# BEP32_6panel_Seed_wdrills.net
KiCad netlist of a schematic drawn in EAGLE
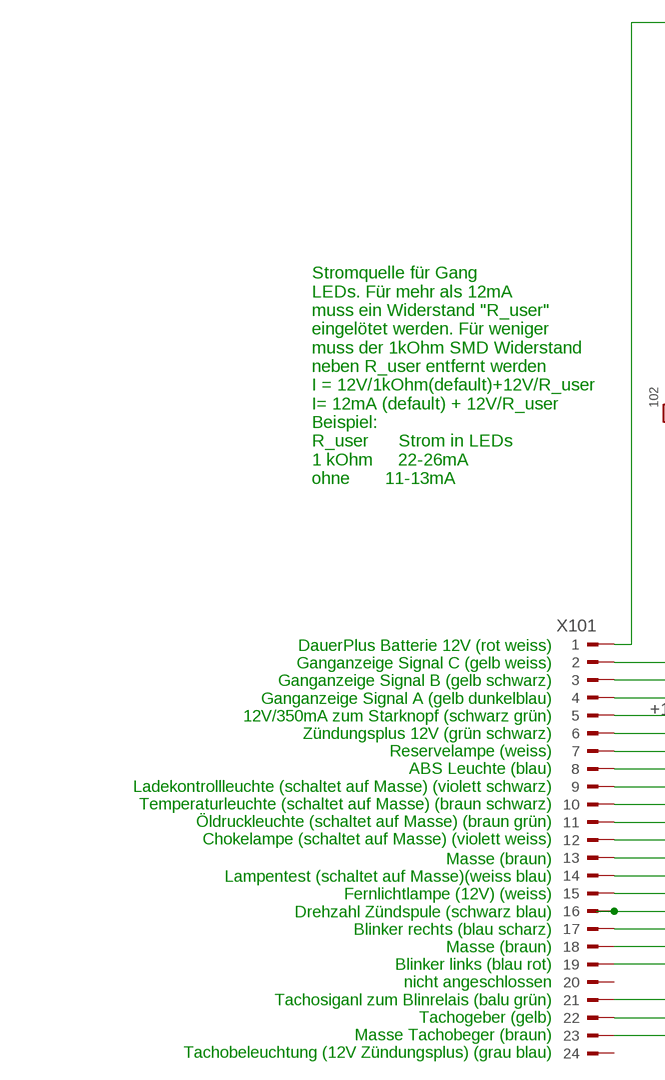
[diagram p0: schematic, sheet 1, part 1 of 2]
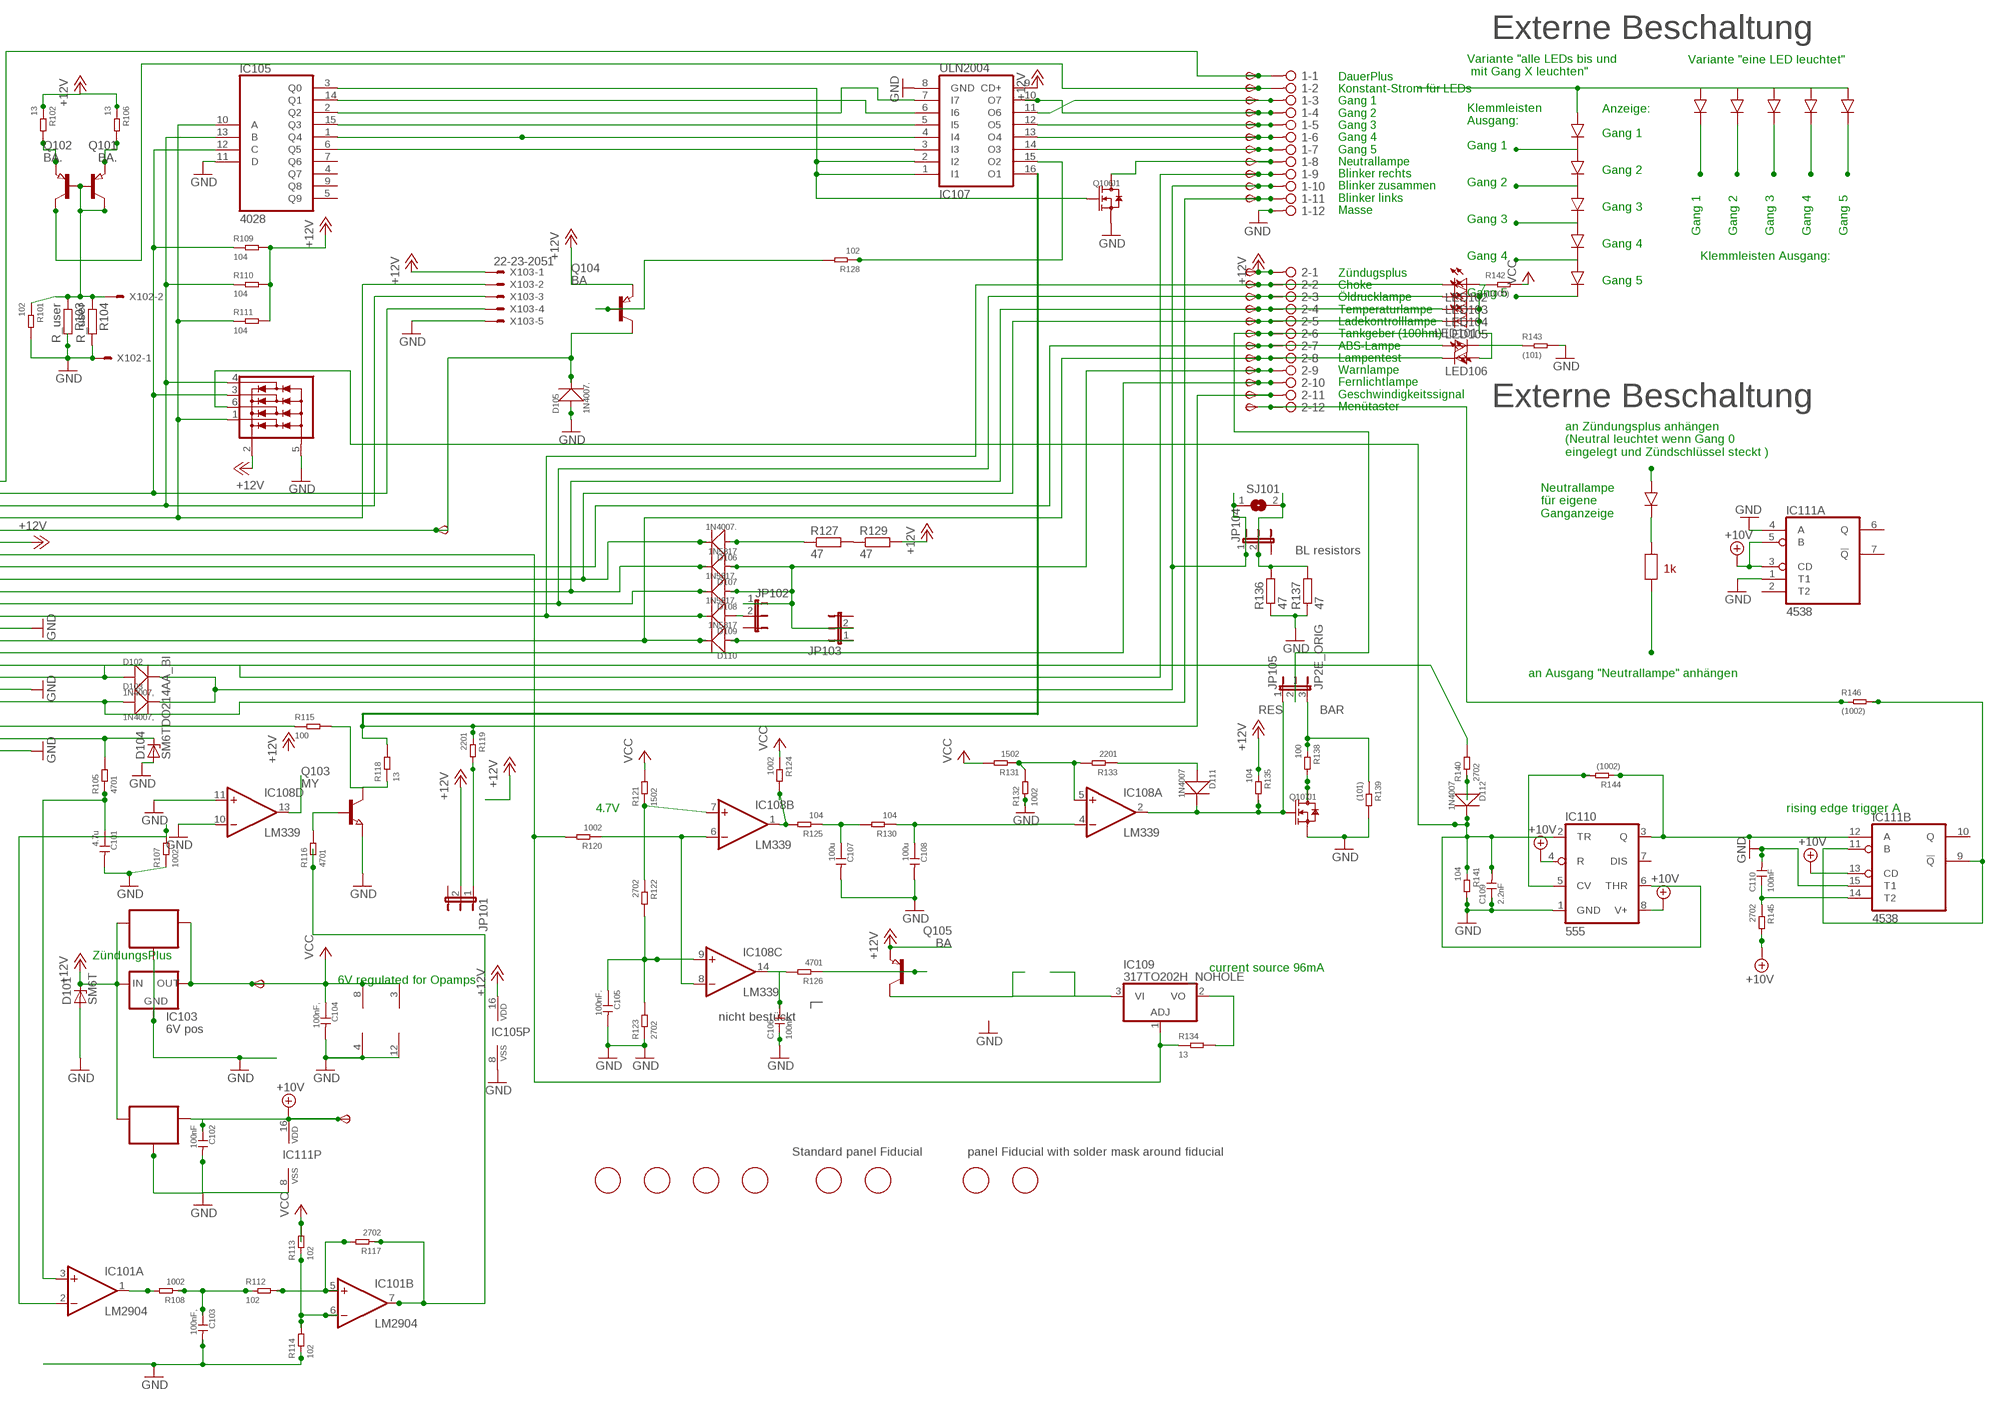
[diagram p1: schematic, sheet 1, part 2 of 2]
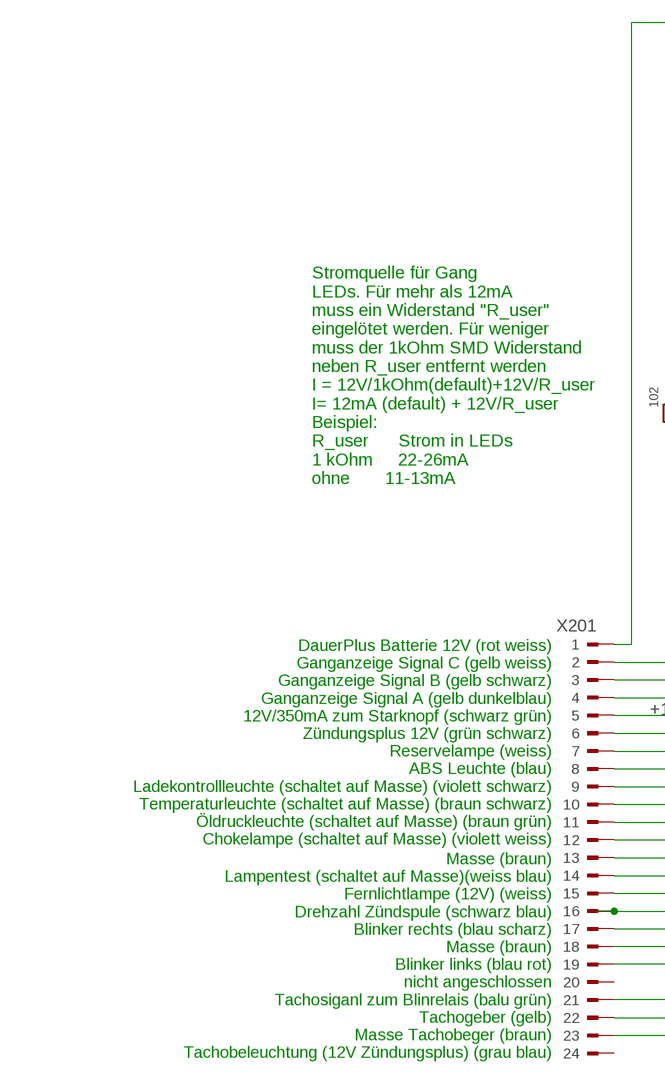
[diagram p2: schematic, sheet 2, part 1 of 2]
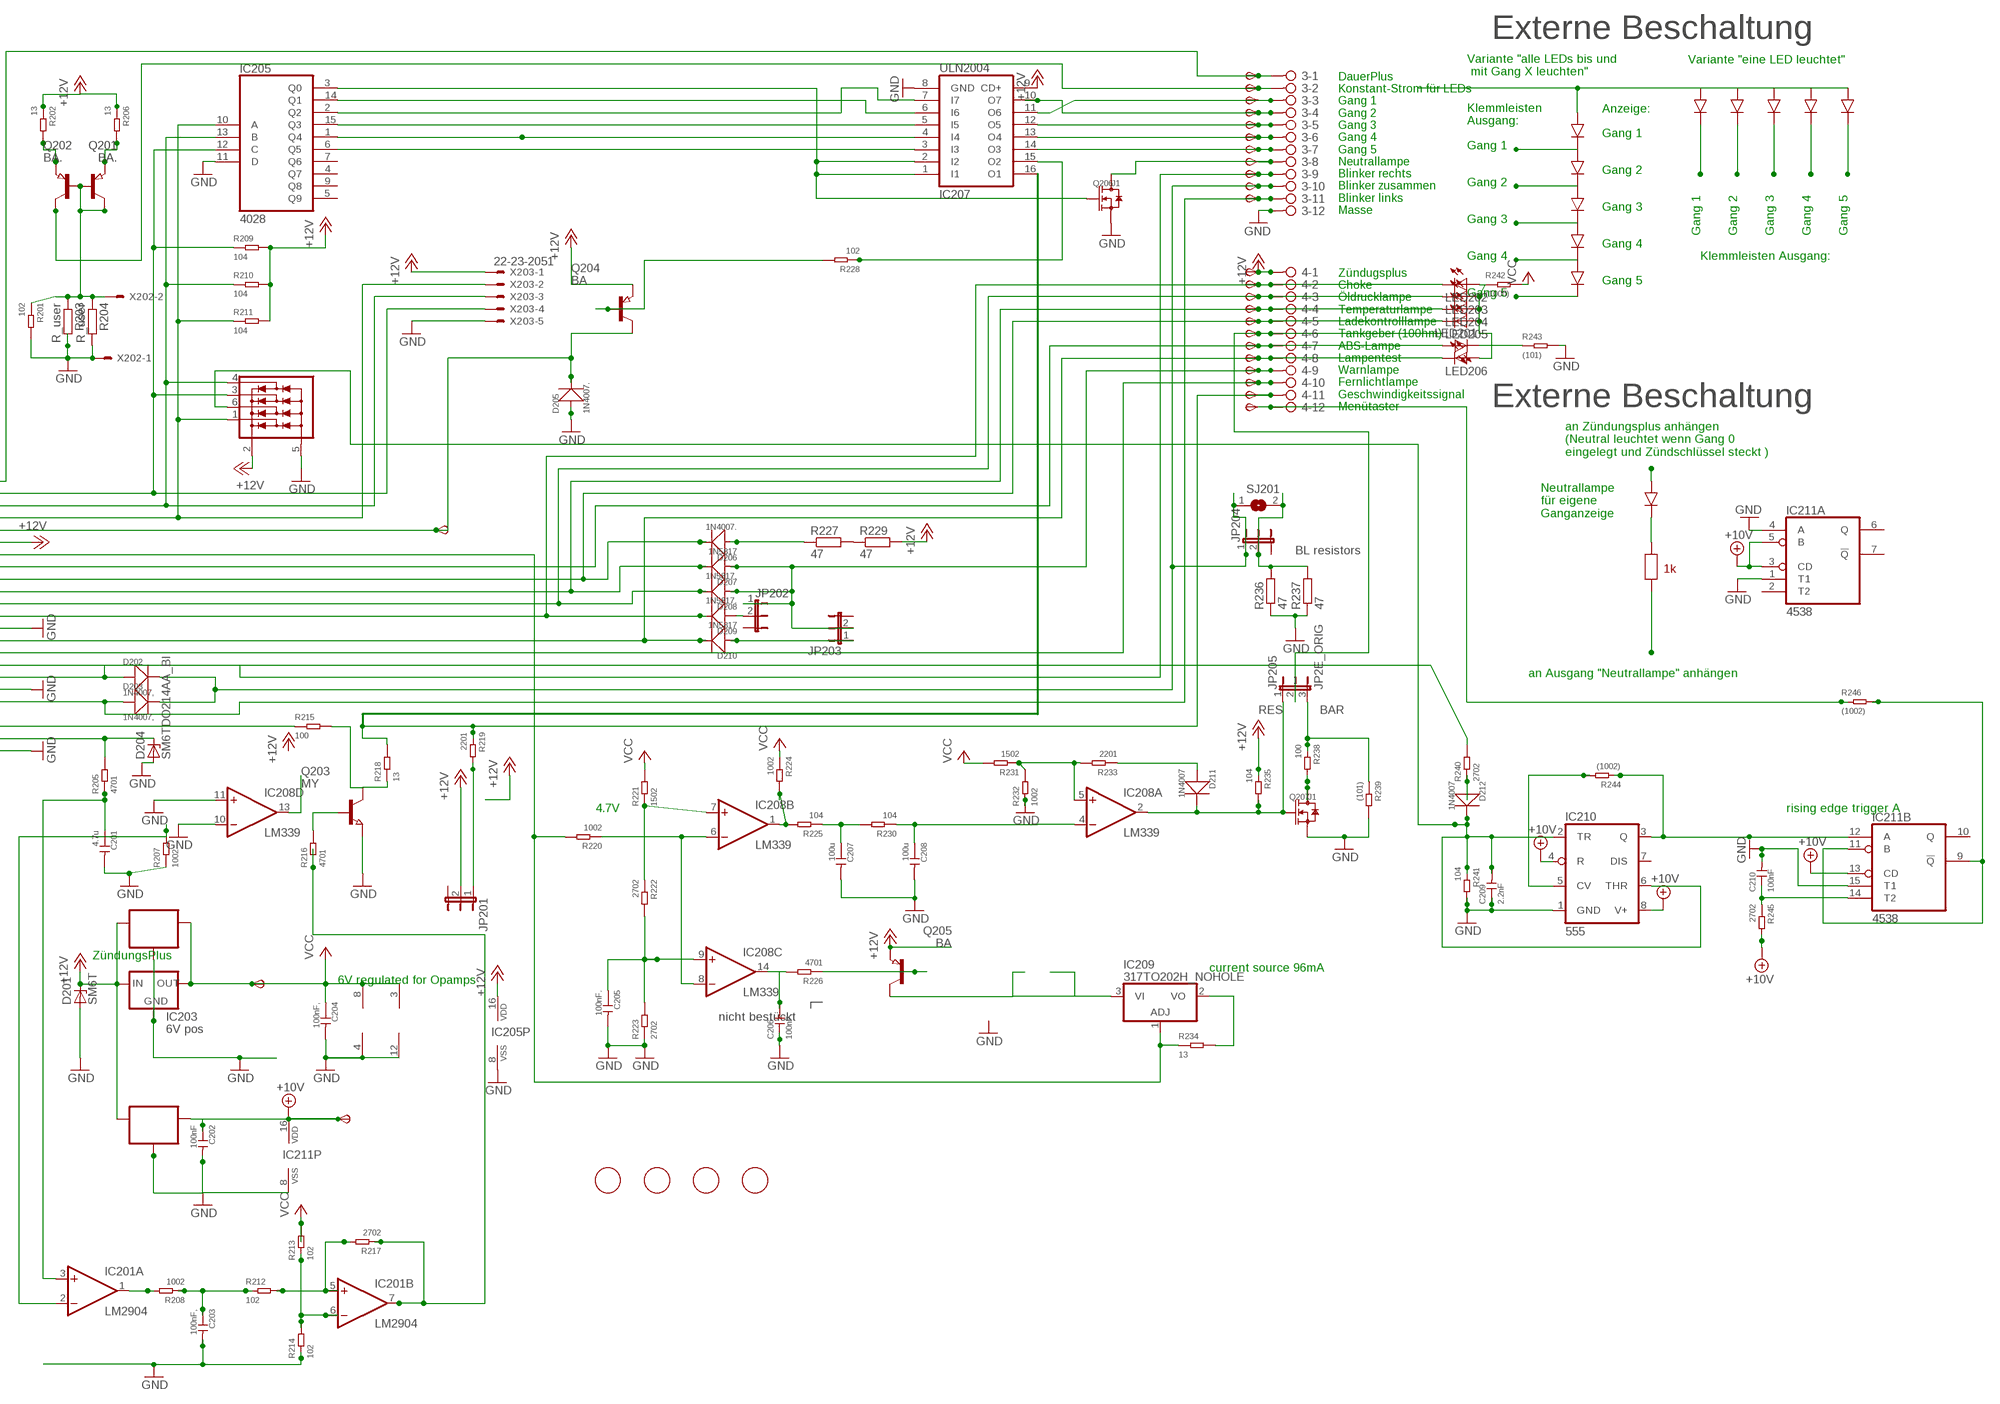
[diagram p3: schematic, sheet 2, part 2 of 2]
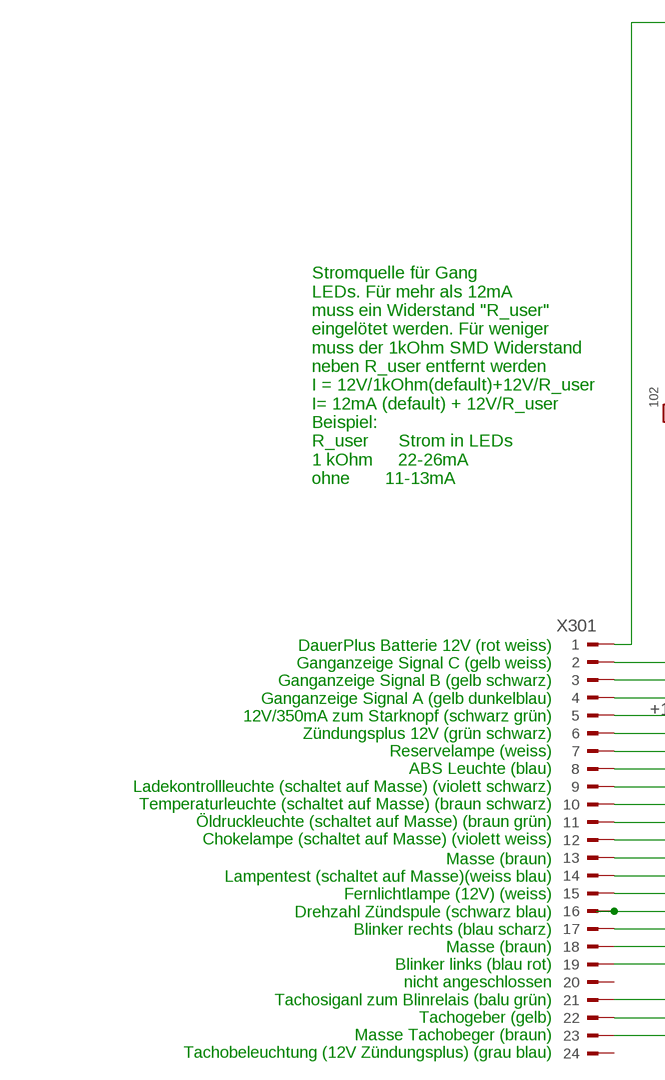
[diagram p4: schematic, sheet 3, part 1 of 2]
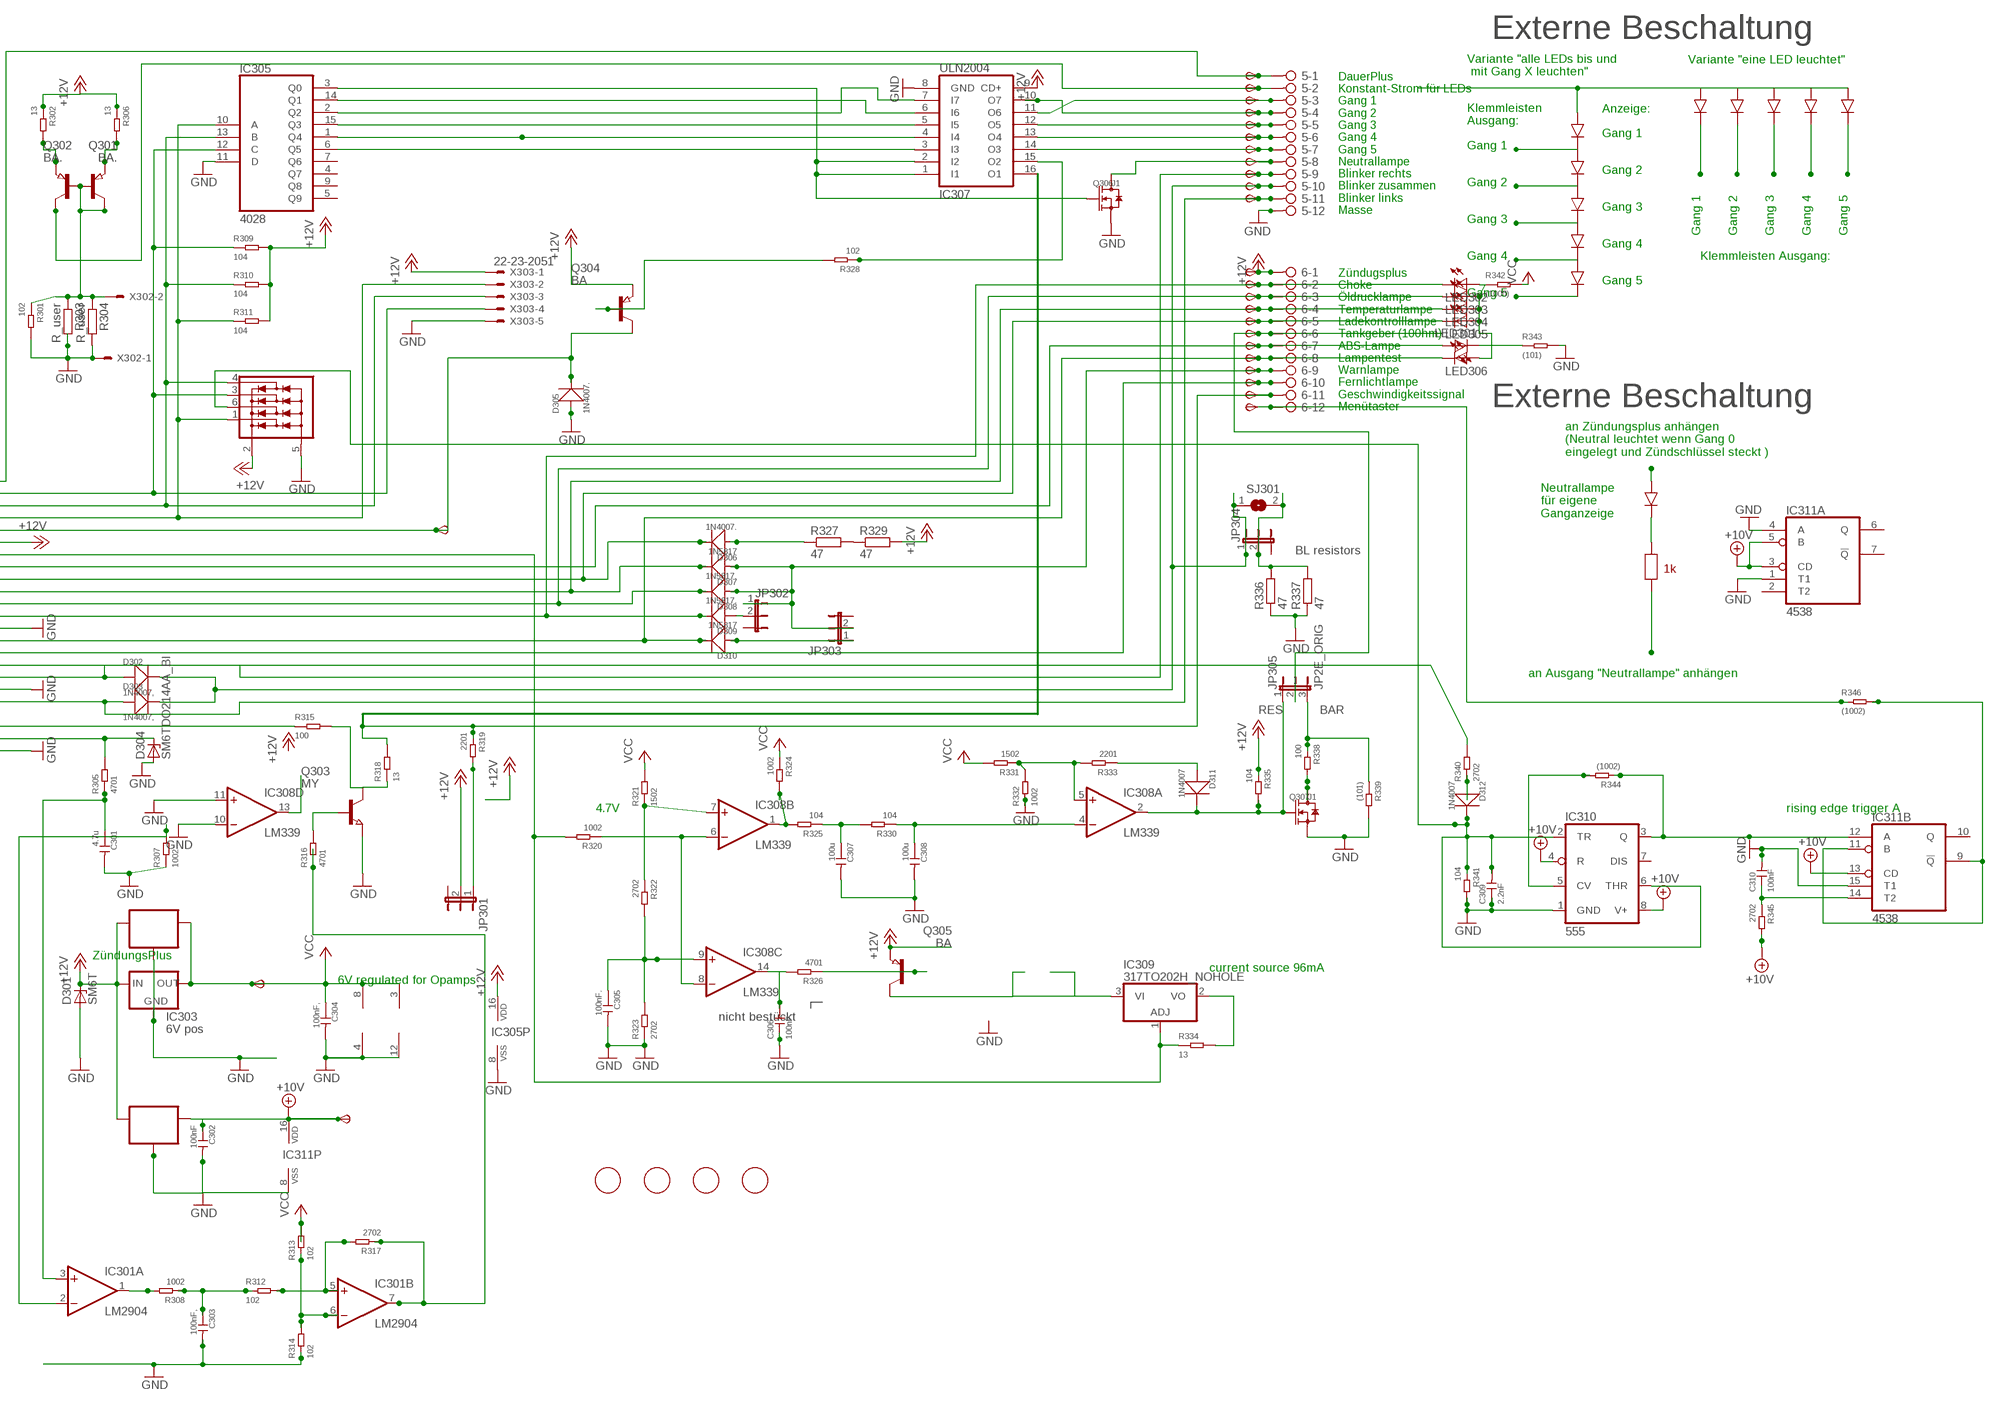
[diagram p5: schematic, sheet 3, part 2 of 2]
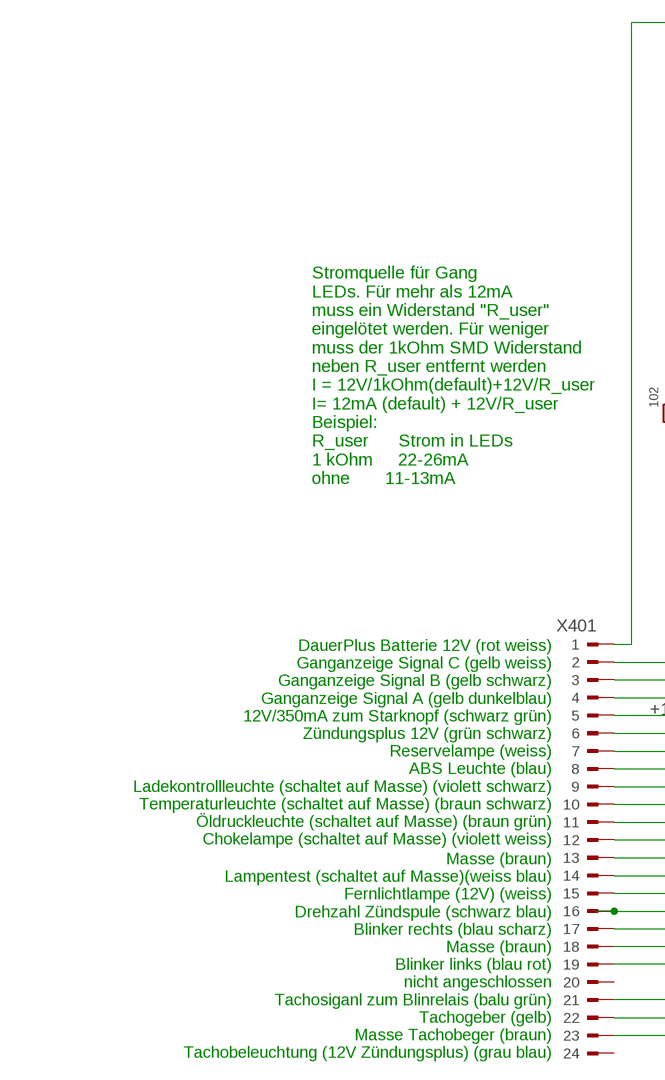
[diagram p6: schematic, sheet 4, part 1 of 2]
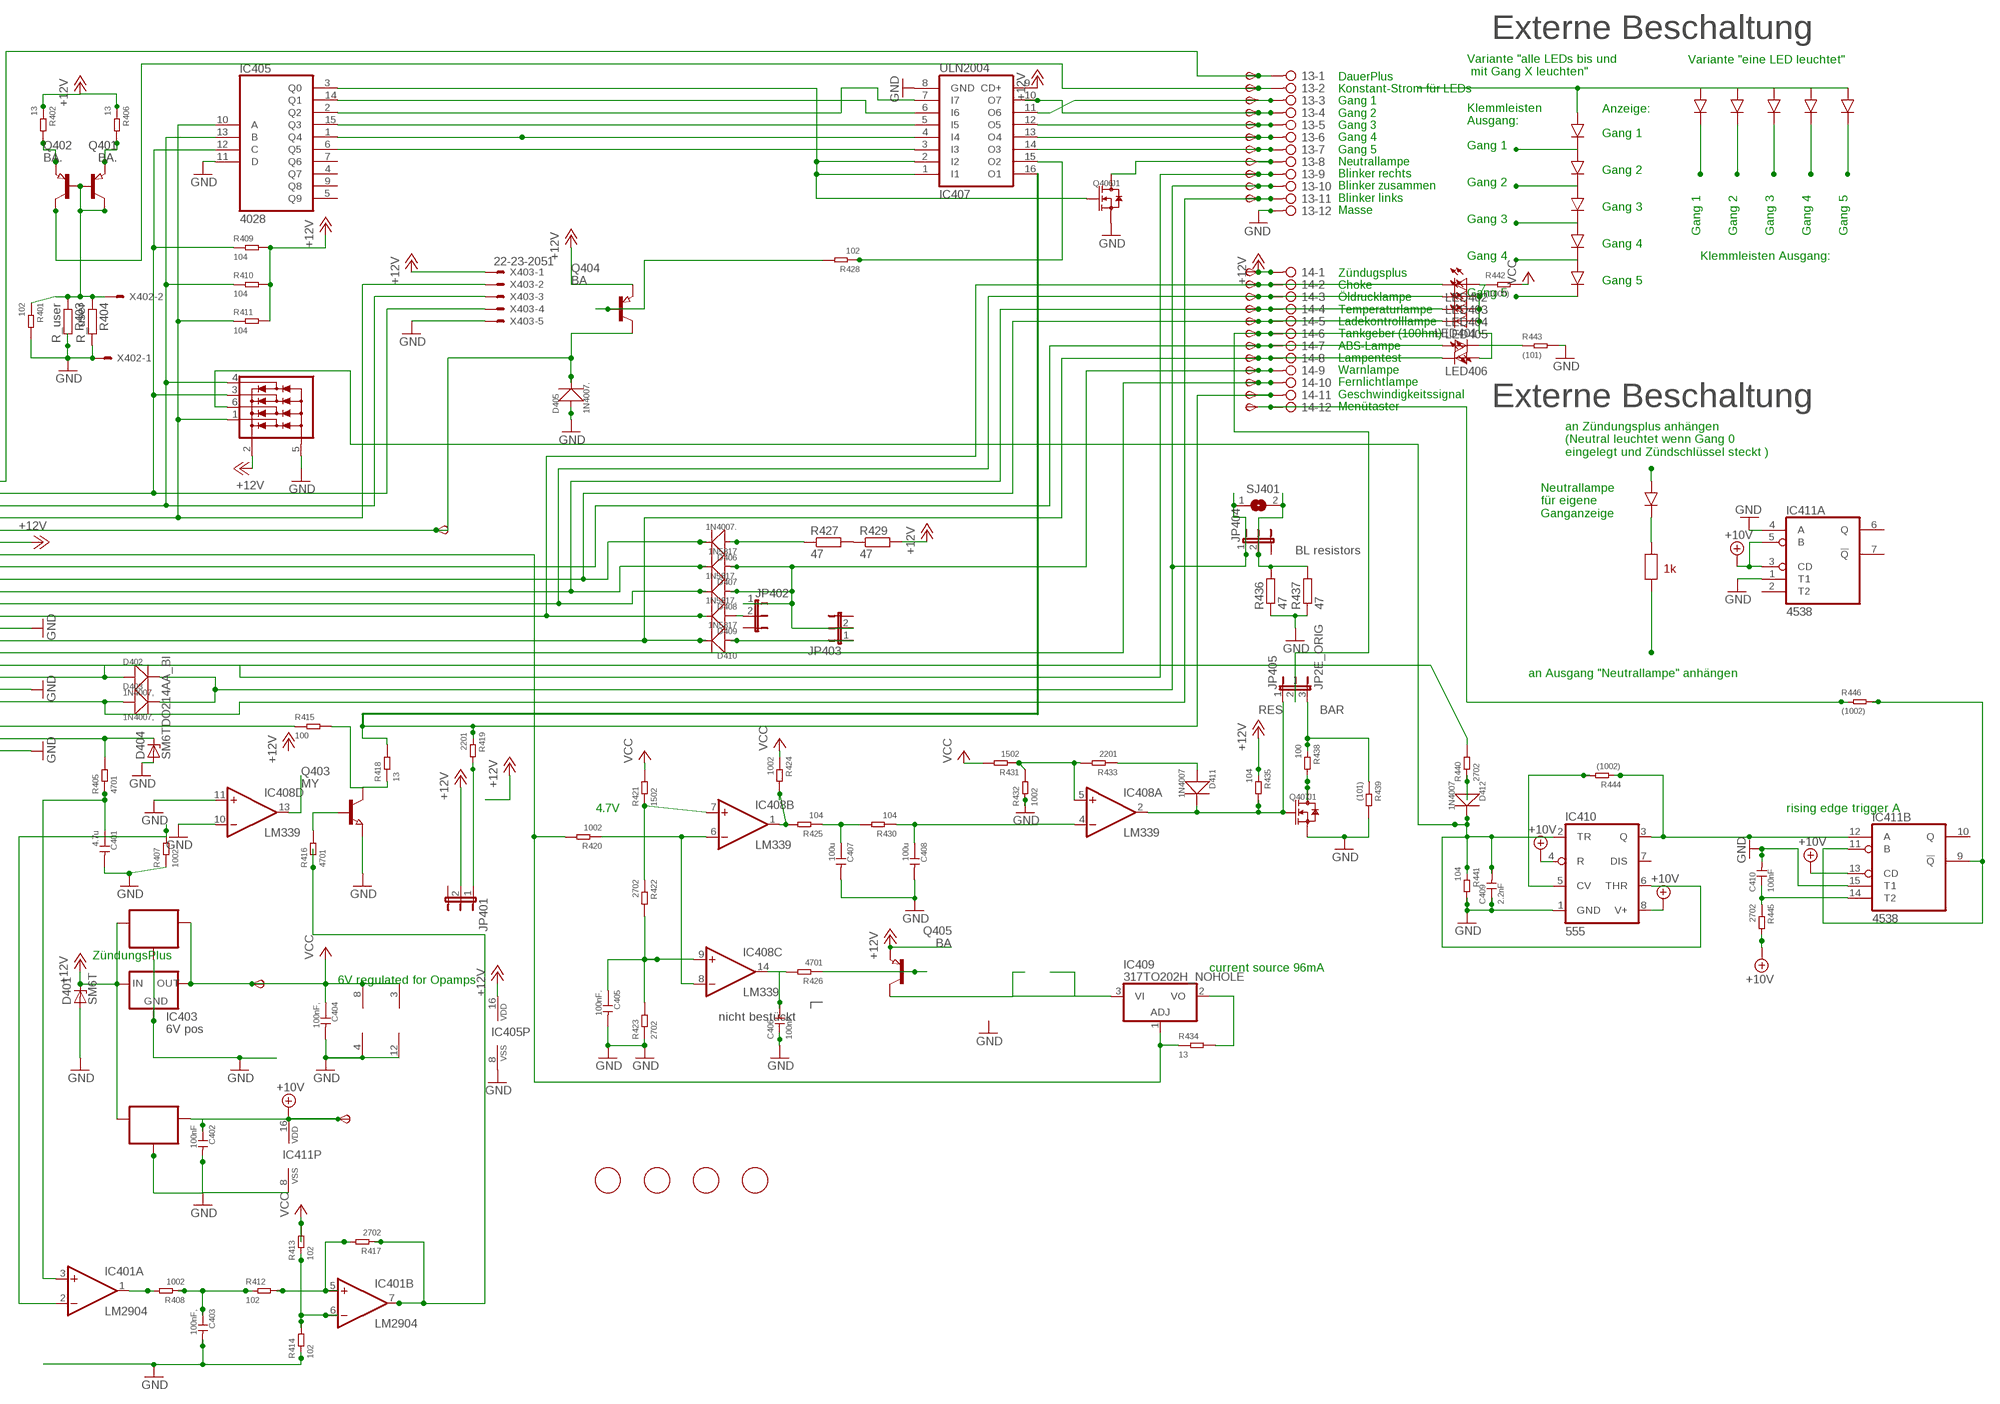
[diagram p7: schematic, sheet 4, part 2 of 2]
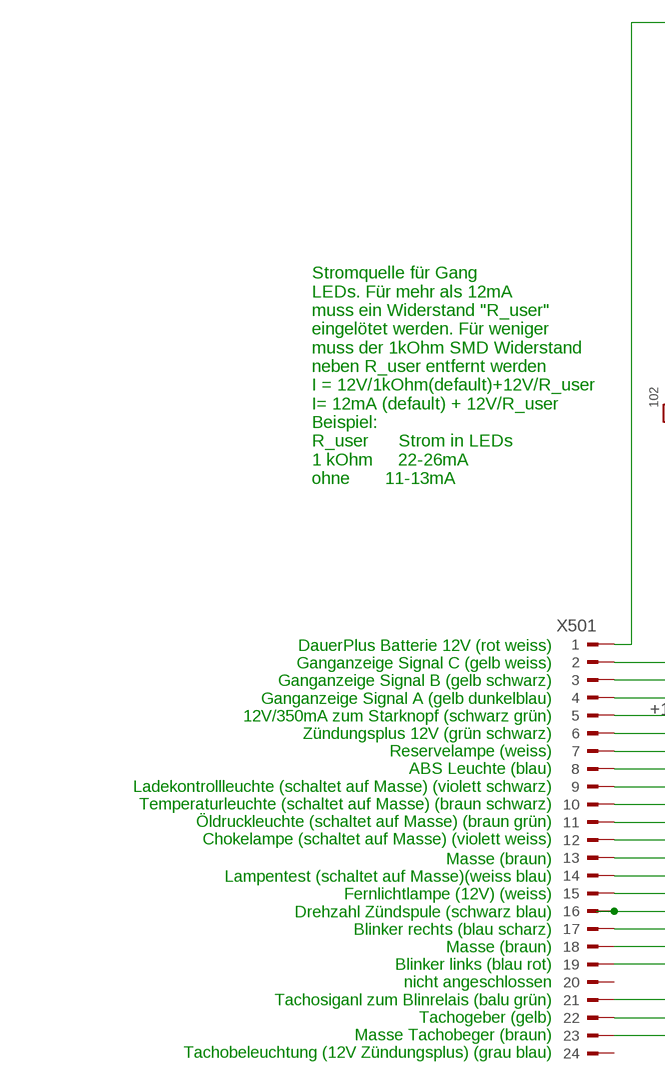
[diagram p8: schematic, sheet 5, part 1 of 2]
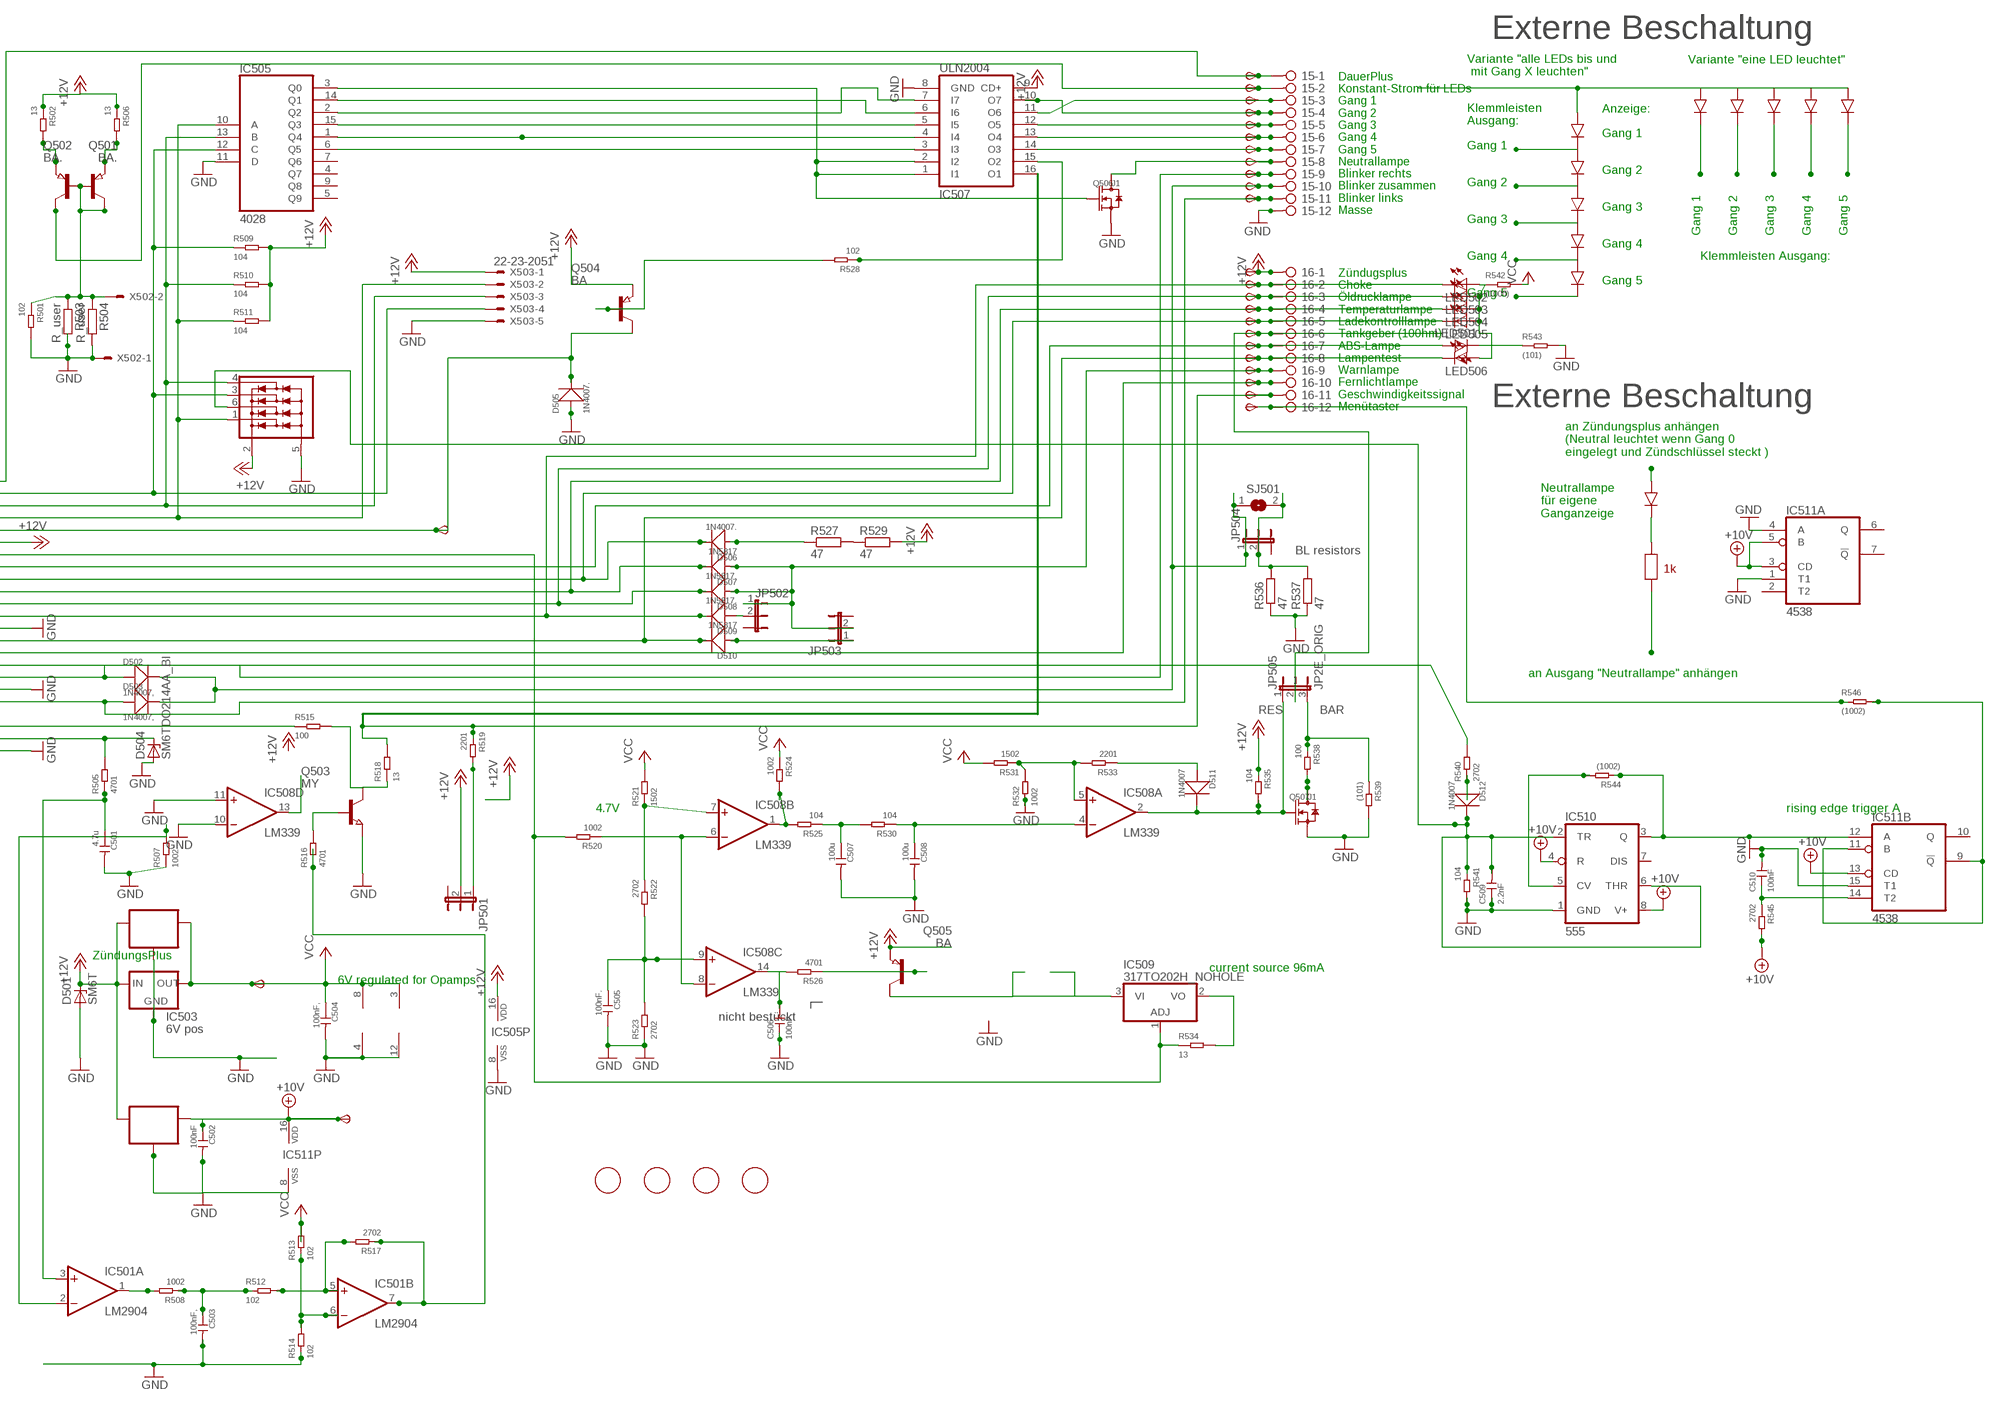
[diagram p9: schematic, sheet 5, part 2 of 2]
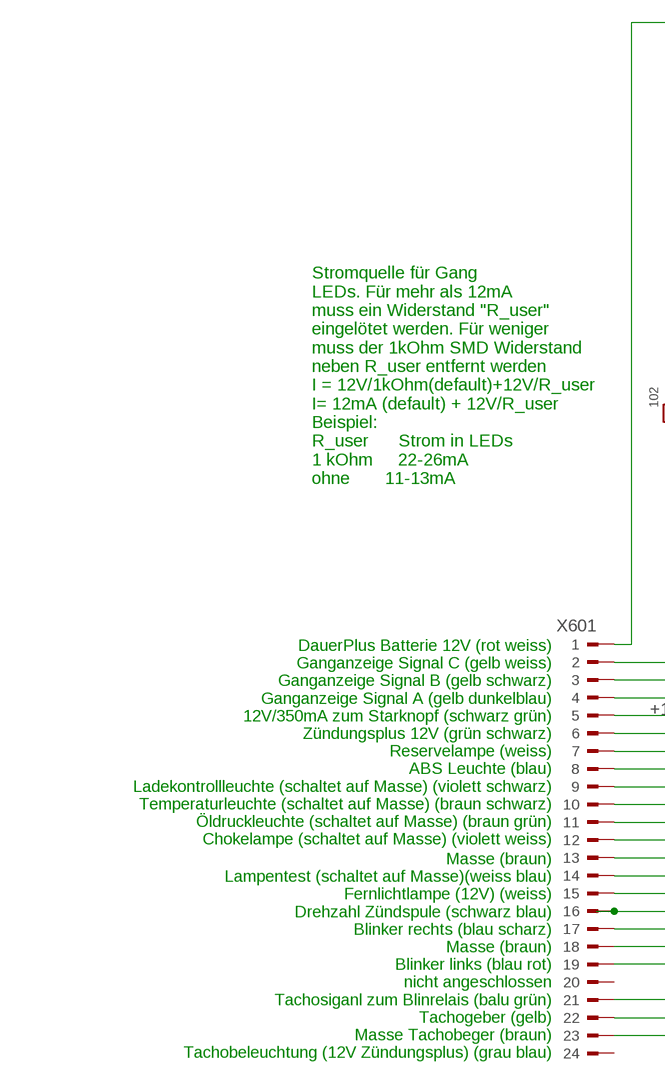
[diagram p10: schematic, sheet 6, part 1 of 2]
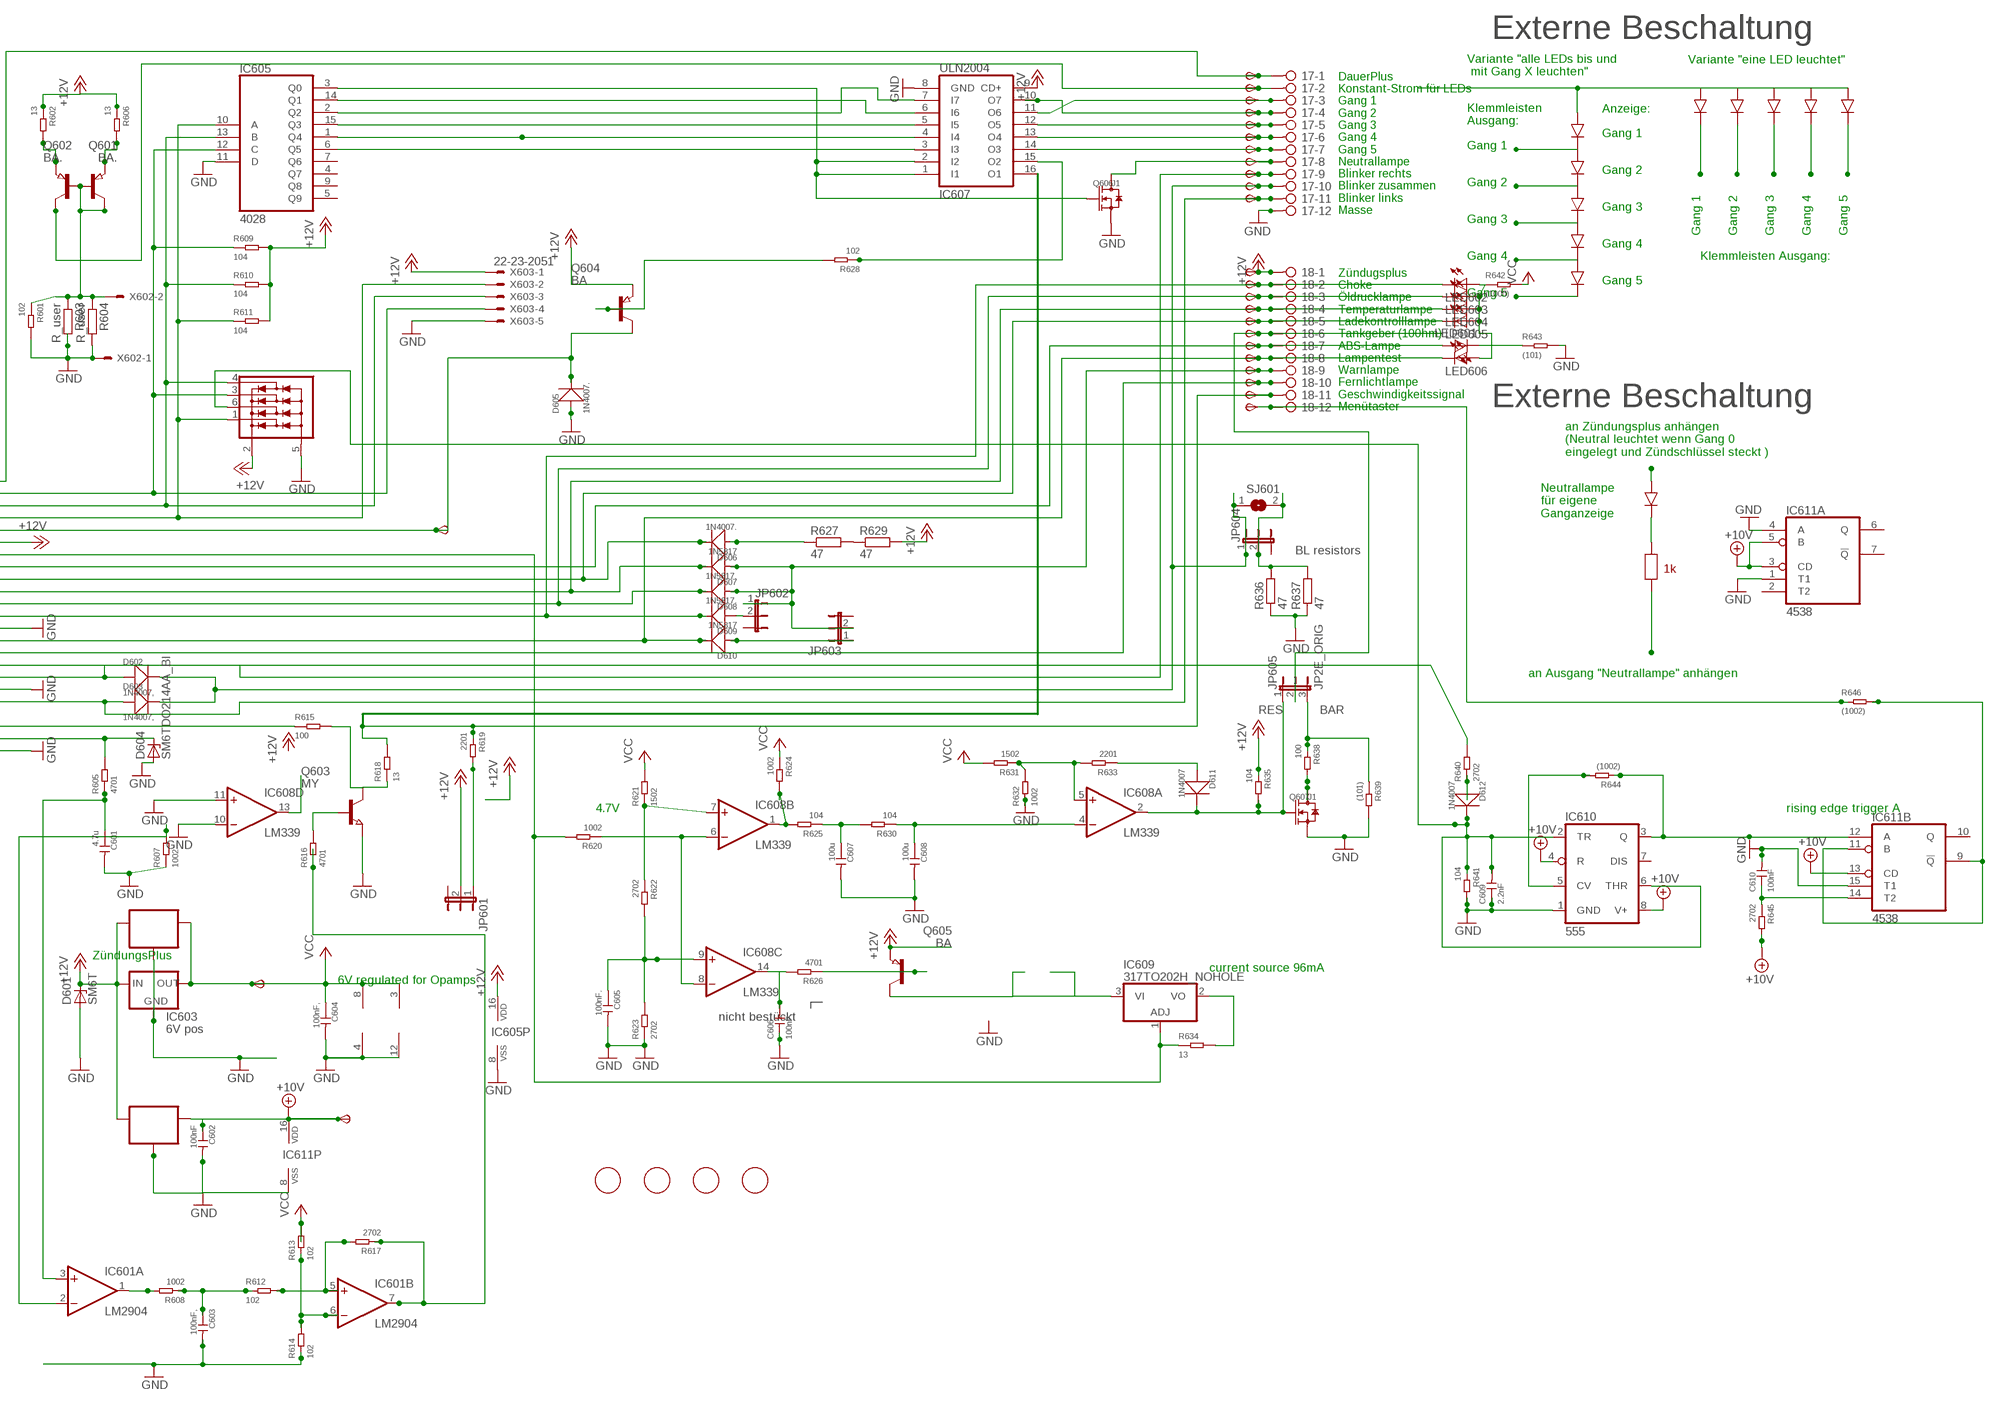
[diagram p11: schematic, sheet 6, part 2 of 2]

(export (version "E")
  (design (tool "Eeschema 10.0.6"))
  (components
    (comp (ref "6V401")
      (value "TPSB2.0")
      (footprint "eagle-import:B2.0")
      (libsource (lib "eagle-import") (part "TPSB2.0"))
    )
    (comp (ref "10V401")
      (value "TPSB2.0")
      (footprint "eagle-import:B2.0")
      (libsource (lib "eagle-import") (part "TPSB2.0"))
    )
    (comp (ref "13")
      (value "2081-1132")
      (footprint "eagle-import:12-PIN")
      (libsource (lib "eagle-import") (part "2081-1132"))
    )
    (comp (ref "14")
      (value "2081-1132")
      (footprint "eagle-import:12-PIN")
      (libsource (lib "eagle-import") (part "2081-1132"))
    )
    (comp (ref "C401")
      (value "4.7u")
      (footprint "eagle-import:C0805")
      (fields (field (name "MPN") "CC0805KKX5R8BB475"))
      (libsource (lib "eagle-import") (part "CERAMIC-4.7UF-25V-10%-X5R(0805)"))
    )
    (comp (ref "C402")
      (value "100nF")
      (footprint "eagle-import:C0805")
      (fields (field (name "MPN") "CC0805KRX7R9BB104"))
      (libsource (lib "eagle-import") (part "CERAMIC-100NF-50V-10%-X7R(0805)"))
    )
    (comp (ref "C403")
      (value "100nF,")
      (footprint "eagle-import:C0805")
      (fields (field (name "MPN") "CC0805KRX7R9BB104"))
      (libsource (lib "eagle-import") (part "CERAMIC-100NF-50V-10%-X7R(0805)"))
    )
    (comp (ref "C404")
      (value "100nF,")
      (footprint "eagle-import:C0805")
      (fields (field (name "MPN") "CC0805KRX7R9BB104"))
      (libsource (lib "eagle-import") (part "CERAMIC-100NF-50V-10%-X7R(0805)"))
    )
    (comp (ref "C405")
      (value "100nF.")
      (footprint "eagle-import:C0805")
      (fields (field (name "MPN") "CC0805KRX7R9BB104"))
      (libsource (lib "eagle-import") (part "CERAMIC-100NF-50V-10%-X7R(0805)"))
    )
    (comp (ref "C406")
      (value "100nF.")
      (footprint "eagle-import:C0805")
      (fields (field (name "MPN") "CC0805KRX7R9BB104"))
      (libsource (lib "eagle-import") (part "CERAMIC-100NF-50V-10%-X7R(0805)"))
    )
    (comp (ref "C407")
      (value "100u")
      (footprint "eagle-import:C1206")
      (fields (field (name "MPN") "GRM31CR60J107ME39L"))
      (libsource (lib "eagle-import") (part "CERAMIC-100UF-6.3V-20%-X5R(1206)"))
    )
    (comp (ref "C408")
      (value "100u")
      (footprint "eagle-import:C1206")
      (fields (field (name "MPN") "GRM31CR60J107ME39L"))
      (libsource (lib "eagle-import") (part "CERAMIC-100UF-6.3V-20%-X5R(1206)"))
    )
    (comp (ref "C409")
      (value "2.2nF")
      (footprint "eagle-import:C0805")
      (fields (field (name "MPN") "CC0805KRX7R9BB104"))
      (libsource (lib "eagle-import") (part "CERAMIC-100NF-50V-10%-X7R(0805)"))
    )
    (comp (ref "C410")
      (value "100nF")
      (footprint "eagle-import:C0805")
      (fields (field (name "MPN") "CC0805KRX7R9BB104"))
      (libsource (lib "eagle-import") (part "CERAMIC-100NF-50V-10%-X7R(0805)"))
    )
    (comp (ref "D401")
      (value "SM6T")
      (footprint "eagle-import:DO214AA")
      (libsource (lib "eagle-import") (part "SM6T"))
    )
    (comp (ref "D402")
      (value "1N4007,")
      (footprint "eagle-import:DO-214AC")
      (fields (field (name "MPN") "1N4007"))
      (libsource (lib "eagle-import") (part "DIODE-GEN-PURPOSE-1KV-1A(DO-214AC)"))
    )
    (comp (ref "D403")
      (value "1N4007,")
      (footprint "eagle-import:DO-214AC")
      (fields (field (name "MPN") "1N4007"))
      (libsource (lib "eagle-import") (part "DIODE-GEN-PURPOSE-1KV-1A(DO-214AC)"))
    )
    (comp (ref "D404")
      (value "SM6TDO214AA_BI")
      (footprint "eagle-import:DO214AA_BI")
      (libsource (lib "eagle-import") (part "SM6TDO214AA_BI"))
    )
    (comp (ref "D405")
      (value "1N4007.")
      (footprint "eagle-import:DO-214AC")
      (fields (field (name "MPN") "1N4007"))
      (libsource (lib "eagle-import") (part "DIODE-GEN-PURPOSE-1KV-1A(DO-214AC)"))
    )
    (comp (ref "D406")
      (value "1N4007.")
      (footprint "eagle-import:DO-214AC")
      (fields (field (name "MPN") "1N4007"))
      (libsource (lib "eagle-import") (part "DIODE-GEN-PURPOSE-1KV-1A(DO-214AC)"))
    )
    (comp (ref "D407")
      (value "1N5817")
      (footprint "eagle-import:DO-214AC_SLIM")
      (libsource (lib "eagle-import") (part "DIODE-GEN-PURPOSE-1KV-1A(DO-214AC)DO-214AC/1206"))
    )
    (comp (ref "D408")
      (value "1N5817.")
      (footprint "eagle-import:DO-214AC_SLIM")
      (libsource (lib "eagle-import") (part "DIODE-GEN-PURPOSE-1KV-1A(DO-214AC)DO-214AC/1206"))
    )
    (comp (ref "D409")
      (value "1N5817.")
      (footprint "eagle-import:DO-214AC_SLIM")
      (libsource (lib "eagle-import") (part "DIODE-GEN-PURPOSE-1KV-1A(DO-214AC)DO-214AC/1206"))
    )
    (comp (ref "D410")
      (value "1N5817")
      (footprint "eagle-import:DO-214AC_SLIM")
      (libsource (lib "eagle-import") (part "DIODE-GEN-PURPOSE-1KV-1A(DO-214AC)DO-214AC/1206"))
    )
    (comp (ref "D411")
      (value "1N4007")
      (footprint "eagle-import:DO-214AC")
      (libsource (lib "eagle-import") (part "DIODE-GEN-PURPOSE-1KV-1A(DO-214AC)"))
    )
    (comp (ref "D412")
      (value "1N4007")
      (footprint "eagle-import:DO-214AC")
      (libsource (lib "eagle-import") (part "DIODE-GEN-PURPOSE-1KV-1A(DO-214AC)"))
    )
    (comp (ref "FID401")
      (value "FIDUCIAL")
      (footprint "eagle-import:FIDUCIAL_1MM")
      (libsource (lib "eagle-import") (part "FIDUCIAL"))
    )
    (comp (ref "FID402")
      (value "FIDUCIAL")
      (footprint "eagle-import:FIDUCIAL_1MM")
      (libsource (lib "eagle-import") (part "FIDUCIAL"))
    )
    (comp (ref "FID403")
      (value "FIDUCIAL")
      (footprint "eagle-import:FIDUCIAL_1MM")
      (libsource (lib "eagle-import") (part "FIDUCIAL"))
    )
    (comp (ref "FID404")
      (value "FIDUCIAL")
      (footprint "eagle-import:FIDUCIAL_1MM")
      (libsource (lib "eagle-import") (part "FIDUCIAL"))
    )
    (comp (ref "IC401")
      (value "LM2904")
      (footprint "eagle-import:SO08")
      (libsource (lib "eagle-import") (part "LM358D"))
    )
    (comp (ref "IC402")
      (value "78L06")
      (footprint "eagle-import:SOT89_ROUND")
      (libsource (lib "eagle-import") (part "78LXXSOT89_ROUND"))
    )
    (comp (ref "IC403")
      (value "6V pos")
      (footprint "eagle-import:78LXX")
      (libsource (lib "eagle-import") (part "v-reg_78LXX"))
    )
    (comp (ref "IC404")
      (value "78L10")
      (footprint "eagle-import:SOT89_ROUND")
      (libsource (lib "eagle-import") (part "78LXXSOT89_ROUND"))
    )
    (comp (ref "IC405")
      (value "4028")
      (footprint "eagle-import:SO16")
      (libsource (lib "eagle-import") (part "4028D"))
    )
    (comp (ref "IC406")
      (value "NUP4304SOT457_R")
      (footprint "eagle-import:SOT457R_PHILIPS")
      (libsource (lib "eagle-import") (part "NUP4304SOT457_R"))
    )
    (comp (ref "IC407")
      (value "ULN2004")
      (footprint "eagle-import:SO16")
      (libsource (lib "eagle-import") (part "ULN2004AD"))
    )
    (comp (ref "IC408")
      (value "LM339")
      (footprint "eagle-import:SO14")
      (libsource (lib "eagle-import") (part "LM339D"))
    )
    (comp (ref "IC409")
      (value "317TO202H_NOHOLE")
      (footprint "eagle-import:TO220H_NOHOLE")
      (libsource (lib "eagle-import") (part "317TO202H_NOHOLE"))
    )
    (comp (ref "IC410")
      (value "555")
      (footprint "eagle-import:SO08")
      (libsource (lib "eagle-import") (part "555DNE"))
    )
    (comp (ref "IC411")
      (value "4538")
      (footprint "eagle-import:SO16")
      (libsource (lib "eagle-import") (part "4538D"))
    )
    (comp (ref "JP401")
      (value "JP2EJP2_SMALLPADS")
      (footprint "eagle-import:JP2_SMALLPADS")
      (libsource (lib "eagle-import") (part "JP2EJP2_SMALLPADS"))
    )
    (comp (ref "JP402")
      (value "JP2EJP2_SMALLPADS")
      (footprint "eagle-import:JP2_SMALLPADS")
      (libsource (lib "eagle-import") (part "JP2EJP2_SMALLPADS"))
    )
    (comp (ref "JP403")
      (value "JP2EJP2_SMALLPADS")
      (footprint "eagle-import:JP2_SMALLPADS")
      (libsource (lib "eagle-import") (part "JP2EJP2_SMALLPADS"))
    )
    (comp (ref "JP404")
      (value "JP2EJP2_SMALLPADS")
      (footprint "eagle-import:JP2_SMALLPADS")
      (libsource (lib "eagle-import") (part "JP2EJP2_SMALLPADS"))
    )
    (comp (ref "JP405")
      (value "JP2E_ORIG")
      (footprint "eagle-import:JP2_ORIG_SMALLPADS")
      (libsource (lib "eagle-import") (part "JP2E_ORIG"))
    )
    (comp (ref "LED401")
      (value "LEDLD260")
      (footprint "eagle-import:LD260")
      (libsource (lib "eagle-import") (part "LEDLD260"))
    )
    (comp (ref "LED402")
      (value "LEDLD260")
      (footprint "eagle-import:LD260")
      (libsource (lib "eagle-import") (part "LEDLD260"))
    )
    (comp (ref "LED403")
      (value "LEDLD260")
      (footprint "eagle-import:LD260")
      (libsource (lib "eagle-import") (part "LEDLD260"))
    )
    (comp (ref "LED404")
      (value "LEDLD260")
      (footprint "eagle-import:LD260")
      (libsource (lib "eagle-import") (part "LEDLD260"))
    )
    (comp (ref "LED405")
      (value "LEDLD260")
      (footprint "eagle-import:LD260")
      (libsource (lib "eagle-import") (part "LEDLD260"))
    )
    (comp (ref "LED406")
      (value "LEDLD260")
      (footprint "eagle-import:LD260")
      (libsource (lib "eagle-import") (part "LEDLD260"))
    )
    (comp (ref "Q401")
      (value "BA.")
      (footprint "eagle-import:SOT89")
      (libsource (lib "eagle-import") (part "PNP-TRANSISTOR_SOT89"))
    )
    (comp (ref "Q402")
      (value "BA.")
      (footprint "eagle-import:SOT89")
      (libsource (lib "eagle-import") (part "PNP-TRANSISTOR_SOT89"))
    )
    (comp (ref "Q403")
      (value "MY")
      (footprint "eagle-import:SOT89")
      (libsource (lib "eagle-import") (part "NPN-TRANSISTOR_SOT89"))
    )
    (comp (ref "Q404")
      (value "BA")
      (footprint "eagle-import:SOT89")
      (libsource (lib "eagle-import") (part "PNP-TRANSISTOR_SOT89"))
    )
    (comp (ref "Q405")
      (value "BA")
      (footprint "eagle-import:SOT89")
      (libsource (lib "eagle-import") (part "PNP-TRANSISTOR_SOT89"))
    )
    (comp (ref "Q406")
      (value "J1")
      (footprint "eagle-import:SOT-23")
      (fields (field (name "MPN") "BSS138W-7-F"))
      (libsource (lib "eagle-import") (part "SMD-MOSFET-N-CH-50V-200MA-BSS138W-7-F(SOT-23)"))
    )
    (comp (ref "Q407")
      (value "J1")
      (footprint "eagle-import:SOT-23")
      (fields (field (name "MPN") "BSS138W-7-F"))
      (libsource (lib "eagle-import") (part "SMD-MOSFET-N-CH-50V-200MA-BSS138W-7-F(SOT-23)"))
    )
    (comp (ref "R401")
      (value "102")
      (footprint "eagle-import:R0805")
      (fields (field (name "MPN") "RC0805JR-071KL"))
      (libsource (lib "eagle-import") (part "SMD-RES-1K-5%-1/8W(0805)"))
    )
    (comp (ref "R402")
      (value "13")
      (footprint "eagle-import:R1206")
      (fields (field (name "MPN") "RC1206JR-0713RL"))
      (libsource (lib "eagle-import") (part "SMD-RES-13R-5%-1/4W(1206)"))
    )
    (comp (ref "R403")
      (value "R_user")
      (footprint "eagle-import:R0805")
      (libsource (lib "eagle-import") (part "R-EU_R0805"))
    )
    (comp (ref "R404")
      (value "R_user")
      (footprint "eagle-import:R0805")
      (libsource (lib "eagle-import") (part "R-EU_R0805"))
    )
    (comp (ref "R405")
      (value "4701")
      (footprint "eagle-import:R0805")
      (fields (field (name "MPN") "RC0805JR-074K7L"))
      (libsource (lib "eagle-import") (part "SMD-RES-4.7K-5%-1/8W(0805)"))
    )
    (comp (ref "R406")
      (value "13")
      (footprint "eagle-import:R1206")
      (fields (field (name "MPN") "RC1206JR-0713RL"))
      (libsource (lib "eagle-import") (part "SMD-RES-13R-5%-1/4W(1206)"))
    )
    (comp (ref "R407")
      (value "1002")
      (footprint "eagle-import:R0805")
      (fields (field (name "MPN") "RC0805FR-0710KL"))
      (libsource (lib "eagle-import") (part "SMD-RES-10K-1%-1/8W(0805)"))
    )
    (comp (ref "R408")
      (value "1002")
      (footprint "eagle-import:R0805")
      (fields (field (name "MPN") "RC0805FR-0710KL"))
      (libsource (lib "eagle-import") (part "SMD-RES-10K-1%-1/8W(0805)"))
    )
    (comp (ref "R409")
      (value "104")
      (footprint "eagle-import:R0805")
      (fields (field (name "MPN") "RC0805FR-0710KL"))
      (libsource (lib "eagle-import") (part "SMD-RES-10K-1%-1/8W(0805)"))
    )
    (comp (ref "R410")
      (value "104")
      (footprint "eagle-import:R0805")
      (fields (field (name "MPN") "RC0805FR-0710KL"))
      (libsource (lib "eagle-import") (part "SMD-RES-10K-1%-1/8W(0805)"))
    )
    (comp (ref "R411")
      (value "104")
      (footprint "eagle-import:R0805")
      (fields (field (name "MPN") "RC0805FR-0710KL"))
      (libsource (lib "eagle-import") (part "SMD-RES-10K-1%-1/8W(0805)"))
    )
    (comp (ref "R412")
      (value "102")
      (footprint "eagle-import:R0805")
      (fields (field (name "MPN") "RC0805JR-071KL"))
      (libsource (lib "eagle-import") (part "SMD-RES-1K-5%-1/8W(0805)"))
    )
    (comp (ref "R413")
      (value "102")
      (footprint "eagle-import:R0805")
      (fields (field (name "MPN") "RC0805JR-071KL"))
      (libsource (lib "eagle-import") (part "SMD-RES-1K-5%-1/8W(0805)"))
    )
    (comp (ref "R414")
      (value "102")
      (footprint "eagle-import:R0805")
      (fields (field (name "MPN") "RC0805JR-071KL"))
      (libsource (lib "eagle-import") (part "SMD-RES-1K-5%-1/8W(0805)"))
    )
    (comp (ref "R415")
      (value "100")
      (footprint "eagle-import:R0805")
      (fields (field (name "MPN") "RC0805JR-07220RL"))
      (libsource (lib "eagle-import") (part "SMD-RES-220R-5%-1/8W(0805)"))
    )
    (comp (ref "R416")
      (value "4701")
      (footprint "eagle-import:R0805")
      (fields (field (name "MPN") "RC0805JR-074K7L"))
      (libsource (lib "eagle-import") (part "SMD-RES-4.7K-5%-1/8W(0805)"))
    )
    (comp (ref "R417")
      (value "2702")
      (footprint "eagle-import:R0805")
      (fields (field (name "MPN") "RC0805JR-074K7L"))
      (libsource (lib "eagle-import") (part "SMD-RES-4.7K-5%-1/8W(0805)"))
    )
    (comp (ref "R418")
      (value "13")
      (footprint "eagle-import:R1206")
      (fields (field (name "MPN") "RC1206JR-0713RL"))
      (libsource (lib "eagle-import") (part "SMD-RES-13R-5%-1/4W(1206)"))
    )
    (comp (ref "R419")
      (value "2201")
      (footprint "eagle-import:R0805")
      (fields (field (name "MPN") "RC0805JR-072K2L"))
      (libsource (lib "eagle-import") (part "SMD-RES-2.2K-5%-1/8W(0805)"))
    )
    (comp (ref "R420")
      (value "1002")
      (footprint "eagle-import:R0805")
      (fields (field (name "MPN") "RC0805FR-0710KL"))
      (libsource (lib "eagle-import") (part "SMD-RES-10K-1%-1/8W(0805)"))
    )
    (comp (ref "R421")
      (value "1502")
      (footprint "eagle-import:R0805")
      (fields (field (name "MPN") "RC0805FR-0710KL"))
      (libsource (lib "eagle-import") (part "SMD-RES-10K-1%-1/8W(0805)"))
    )
    (comp (ref "R422")
      (value "2702")
      (footprint "eagle-import:R0805")
      (fields (field (name "MPN") "RC0805JR-074K7L"))
      (libsource (lib "eagle-import") (part "SMD-RES-4.7K-5%-1/8W(0805)"))
    )
    (comp (ref "R423")
      (value "2702")
      (footprint "eagle-import:R0805")
      (fields (field (name "MPN") "RC0805JR-074K7L"))
      (libsource (lib "eagle-import") (part "SMD-RES-4.7K-5%-1/8W(0805)"))
    )
    (comp (ref "R424")
      (value "1002")
      (footprint "eagle-import:R0805")
      (fields (field (name "MPN") "RC0805FR-0710KL"))
      (libsource (lib "eagle-import") (part "SMD-RES-10K-1%-1/8W(0805)"))
    )
    (comp (ref "R425")
      (value "104")
      (footprint "eagle-import:R0805")
      (fields (field (name "MPN") "RC0805FR-0710KL"))
      (libsource (lib "eagle-import") (part "SMD-RES-10K-1%-1/8W(0805)"))
    )
    (comp (ref "R426")
      (value "4701")
      (footprint "eagle-import:R0805")
      (fields (field (name "MPN") "RC0805JR-074K7L"))
      (libsource (lib "eagle-import") (part "SMD-RES-4.7K-5%-1/8W(0805)"))
    )
    (comp (ref "R427")
      (value "47")
      (footprint "eagle-import:V235_17_1MM")
      (libsource (lib "eagle-import") (part "R-EU_V235/17_1MM"))
    )
    (comp (ref "R428")
      (value "102")
      (footprint "eagle-import:R0805")
      (fields (field (name "MPN") "RC0805JR-071KL"))
      (libsource (lib "eagle-import") (part "SMD-RES-1K-5%-1/8W(0805)"))
    )
    (comp (ref "R429")
      (value "47")
      (footprint "eagle-import:V235_17_1MM")
      (libsource (lib "eagle-import") (part "R-EU_V235/17_1MM"))
    )
    (comp (ref "R430")
      (value "104")
      (footprint "eagle-import:R0805")
      (fields (field (name "MPN") "RC0805FR-0710KL"))
      (libsource (lib "eagle-import") (part "SMD-RES-10K-1%-1/8W(0805)"))
    )
    (comp (ref "R431")
      (value "1502")
      (footprint "eagle-import:R0805")
      (fields (field (name "MPN") "RC0805FR-0710KL"))
      (libsource (lib "eagle-import") (part "SMD-RES-10K-1%-1/8W(0805)"))
    )
    (comp (ref "R432")
      (value "1002")
      (footprint "eagle-import:R0805")
      (fields (field (name "MPN") "RC0805FR-0710KL"))
      (libsource (lib "eagle-import") (part "SMD-RES-10K-1%-1/8W(0805)"))
    )
    (comp (ref "R433")
      (value "2201")
      (footprint "eagle-import:R0805")
      (fields (field (name "MPN") "RC0805JR-072K2L"))
      (libsource (lib "eagle-import") (part "SMD-RES-2.2K-5%-1/8W(0805)"))
    )
    (comp (ref "R434")
      (value "13")
      (footprint "eagle-import:R1206")
      (fields (field (name "MPN") "RC1206JR-0713RL"))
      (libsource (lib "eagle-import") (part "SMD-RES-13R-5%-1/4W(1206)"))
    )
    (comp (ref "R435")
      (value "104")
      (footprint "eagle-import:R0805")
      (fields (field (name "MPN") "RC0805FR-0710KL"))
      (libsource (lib "eagle-import") (part "SMD-RES-10K-1%-1/8W(0805)"))
    )
    (comp (ref "R436")
      (value "47")
      (footprint "eagle-import:V235_17_1MM")
      (libsource (lib "eagle-import") (part "R-EU_V235/17_1MM"))
    )
    (comp (ref "R437")
      (value "47")
      (footprint "eagle-import:V235_17_1MM")
      (libsource (lib "eagle-import") (part "R-EU_V235/17_1MM"))
    )
    (comp (ref "R438")
      (value "100")
      (footprint "eagle-import:R0805")
      (fields (field (name "MPN") "RC0805JR-072K2L"))
      (libsource (lib "eagle-import") (part "SMD-RES-2.2K-5%-1/8W(0805)"))
    )
    (comp (ref "R439")
      (value "(101)")
      (footprint "eagle-import:R0805")
      (fields (field (name "MPN") "RC0805JR-072K2L"))
      (libsource (lib "eagle-import") (part "SMD-RES-2.2K-5%-1/8W(0805)"))
    )
    (comp (ref "R440")
      (value "2702")
      (footprint "eagle-import:R0805")
      (fields (field (name "MPN") "RC0805FR-0710KL"))
      (libsource (lib "eagle-import") (part "SMD-RES-10K-1%-1/8W(0805)"))
    )
    (comp (ref "R441")
      (value "104")
      (footprint "eagle-import:R0805")
      (fields (field (name "MPN") "RC0805FR-0710KL"))
      (libsource (lib "eagle-import") (part "SMD-RES-10K-1%-1/8W(0805)"))
    )
    (comp (ref "R442")
      (value "(1000)")
      (footprint "eagle-import:R0805")
      (fields (field (name "MPN") "RC0805JR-07100RL"))
      (libsource (lib "eagle-import") (part "SMD-RES-100R-5%-1/8W(0805)"))
    )
    (comp (ref "R443")
      (value "(101)")
      (footprint "eagle-import:R0805")
      (fields (field (name "MPN") "RC0805JR-07100RL"))
      (libsource (lib "eagle-import") (part "SMD-RES-100R-5%-1/8W(0805)"))
    )
    (comp (ref "R444")
      (value "(1002)")
      (footprint "eagle-import:R0805")
      (fields (field (name "MPN") "RC0805FR-0710KL"))
      (libsource (lib "eagle-import") (part "SMD-RES-10K-1%-1/8W(0805)"))
    )
    (comp (ref "R445")
      (value "2702")
      (footprint "eagle-import:R0805")
      (fields (field (name "MPN") "RC0805JR-074K7L"))
      (libsource (lib "eagle-import") (part "SMD-RES-4.7K-5%-1/8W(0805)"))
    )
    (comp (ref "R446")
      (value "(1002)")
      (footprint "eagle-import:R0805")
      (fields (field (name "MPN") "RC0805JR-074K7L"))
      (libsource (lib "eagle-import") (part "SMD-RES-4.7K-5%-1/8W(0805)"))
    )
    (comp (ref "SJ401")
      (value "SJ")
      (footprint "eagle-import:SJ")
      (libsource (lib "eagle-import") (part "SJ"))
    )
    (comp (ref "START401")
      (value "TPSB2.0")
      (footprint "eagle-import:B2.0")
      (libsource (lib "eagle-import") (part "TPSB2.0"))
    )
    (comp (ref "TP139")
      (value "TPSB2.0")
      (footprint "eagle-import:B2.0")
      (libsource (lib "eagle-import") (part "TPSB2.0"))
    )
    (comp (ref "TP140")
      (value "TPSB2.0")
      (footprint "eagle-import:B2.0")
      (libsource (lib "eagle-import") (part "TPSB2.0"))
    )
    (comp (ref "TP141")
      (value "TPSB2.0")
      (footprint "eagle-import:B2.0")
      (libsource (lib "eagle-import") (part "TPSB2.0"))
    )
    (comp (ref "TP142")
      (value "TPSB2.0")
      (footprint "eagle-import:B2.0")
      (libsource (lib "eagle-import") (part "TPSB2.0"))
    )
    (comp (ref "TP143")
      (value "TPSB2.0")
      (footprint "eagle-import:B2.0")
      (libsource (lib "eagle-import") (part "TPSB2.0"))
    )
    (comp (ref "TP144")
      (value "TPSB2.0")
      (footprint "eagle-import:B2.0")
      (libsource (lib "eagle-import") (part "TPSB2.0"))
    )
    (comp (ref "TP145")
      (value "TPSB2.0")
      (footprint "eagle-import:B2.0")
      (libsource (lib "eagle-import") (part "TPSB2.0"))
    )
    (comp (ref "TP146")
      (value "TPSB2.0")
      (footprint "eagle-import:B2.0")
      (libsource (lib "eagle-import") (part "TPSB2.0"))
    )
    (comp (ref "TP147")
      (value "TPSB2.0")
      (footprint "eagle-import:B2.0")
      (libsource (lib "eagle-import") (part "TPSB2.0"))
    )
    (comp (ref "TP148")
      (value "TPSB2.0")
      (footprint "eagle-import:B2.0")
      (libsource (lib "eagle-import") (part "TPSB2.0"))
    )
    (comp (ref "TP149")
      (value "TPSB2.0")
      (footprint "eagle-import:B2.0")
      (libsource (lib "eagle-import") (part "TPSB2.0"))
    )
    (comp (ref "TP150")
      (value "TPSB2.0")
      (footprint "eagle-import:B2.0")
      (libsource (lib "eagle-import") (part "TPSB2.0"))
    )
    (comp (ref "TP151")
      (value "TPSB2.0")
      (footprint "eagle-import:B2.0")
      (libsource (lib "eagle-import") (part "TPSB2.0"))
    )
    (comp (ref "TP152")
      (value "TPSB2.0")
      (footprint "eagle-import:B2.0")
      (libsource (lib "eagle-import") (part "TPSB2.0"))
    )
    (comp (ref "TP153")
      (value "TPSB2.0")
      (footprint "eagle-import:B2.0")
      (libsource (lib "eagle-import") (part "TPSB2.0"))
    )
    (comp (ref "TP154")
      (value "TPSB2.0")
      (footprint "eagle-import:B2.0")
      (libsource (lib "eagle-import") (part "TPSB2.0"))
    )
    (comp (ref "TP155")
      (value "TPSB2.0")
      (footprint "eagle-import:B2.0")
      (libsource (lib "eagle-import") (part "TPSB2.0"))
    )
    (comp (ref "TP156")
      (value "TPSB2.0")
      (footprint "eagle-import:B2.0")
      (libsource (lib "eagle-import") (part "TPSB2.0"))
    )
    (comp (ref "TP157")
      (value "TPSB1,27")
      (footprint "eagle-import:B1,27")
      (libsource (lib "eagle-import") (part "TPSB1,27"))
    )
    (comp (ref "TP158")
      (value "TPSB2.0")
      (footprint "eagle-import:B2.0")
      (libsource (lib "eagle-import") (part "TPSB2.0"))
    )
    (comp (ref "TP159")
      (value "TPSB2.0")
      (footprint "eagle-import:B2.0")
      (libsource (lib "eagle-import") (part "TPSB2.0"))
    )
    (comp (ref "TP160")
      (value "TPSB2.0")
      (footprint "eagle-import:B2.0")
      (libsource (lib "eagle-import") (part "TPSB2.0"))
    )
    (comp (ref "TP161")
      (value "TPSB2.0")
      (footprint "eagle-import:B2.0")
      (libsource (lib "eagle-import") (part "TPSB2.0"))
    )
    (comp (ref "X401")
      (value "CON_BMWV2")
      (footprint "eagle-import:24-PIN_V2")
      (libsource (lib "eagle-import") (part "CON_BMWV2"))
    )
    (comp (ref "X402")
      (value "22-23-2021")
      (footprint "eagle-import:22-23-2021")
      (fields (field (name "MF") "MOLEX"))
      (libsource (lib "eagle-import") (part "22-23-2021"))
    )
    (comp (ref "X403")
      (value "22-23-2051")
      (footprint "eagle-import:22-23-2051")
      (fields (field (name "MF") "MOLEX"))
      (libsource (lib "eagle-import") (part "22-23-2051"))
    )
    (comp (ref "5")
      (value "2081-1132")
      (footprint "eagle-import:12-PIN")
      (libsource (lib "eagle-import") (part "2081-1132"))
    )
    (comp (ref "6")
      (value "2081-1132")
      (footprint "eagle-import:12-PIN")
      (libsource (lib "eagle-import") (part "2081-1132"))
    )
    (comp (ref "6V301")
      (value "TPSB2.0")
      (footprint "eagle-import:B2.0")
      (libsource (lib "eagle-import") (part "TPSB2.0"))
    )
    (comp (ref "10V301")
      (value "TPSB2.0")
      (footprint "eagle-import:B2.0")
      (libsource (lib "eagle-import") (part "TPSB2.0"))
    )
    (comp (ref "C301")
      (value "4.7u")
      (footprint "eagle-import:C0805")
      (fields (field (name "MPN") "CC0805KKX5R8BB475"))
      (libsource (lib "eagle-import") (part "CERAMIC-4.7UF-25V-10%-X5R(0805)"))
    )
    (comp (ref "C302")
      (value "100nF")
      (footprint "eagle-import:C0805")
      (fields (field (name "MPN") "CC0805KRX7R9BB104"))
      (libsource (lib "eagle-import") (part "CERAMIC-100NF-50V-10%-X7R(0805)"))
    )
    (comp (ref "C303")
      (value "100nF,")
      (footprint "eagle-import:C0805")
      (fields (field (name "MPN") "CC0805KRX7R9BB104"))
      (libsource (lib "eagle-import") (part "CERAMIC-100NF-50V-10%-X7R(0805)"))
    )
    (comp (ref "C304")
      (value "100nF,")
      (footprint "eagle-import:C0805")
      (fields (field (name "MPN") "CC0805KRX7R9BB104"))
      (libsource (lib "eagle-import") (part "CERAMIC-100NF-50V-10%-X7R(0805)"))
    )
    (comp (ref "C305")
      (value "100nF.")
      (footprint "eagle-import:C0805")
      (fields (field (name "MPN") "CC0805KRX7R9BB104"))
      (libsource (lib "eagle-import") (part "CERAMIC-100NF-50V-10%-X7R(0805)"))
    )
    (comp (ref "C306")
      (value "100nF.")
      (footprint "eagle-import:C0805")
      (fields (field (name "MPN") "CC0805KRX7R9BB104"))
      (libsource (lib "eagle-import") (part "CERAMIC-100NF-50V-10%-X7R(0805)"))
    )
    (comp (ref "C307")
      (value "100u")
      (footprint "eagle-import:C1206")
      (fields (field (name "MPN") "GRM31CR60J107ME39L"))
      (libsource (lib "eagle-import") (part "CERAMIC-100UF-6.3V-20%-X5R(1206)"))
    )
    (comp (ref "C308")
      (value "100u")
      (footprint "eagle-import:C1206")
      (fields (field (name "MPN") "GRM31CR60J107ME39L"))
      (libsource (lib "eagle-import") (part "CERAMIC-100UF-6.3V-20%-X5R(1206)"))
    )
    (comp (ref "C309")
      (value "2.2nF")
      (footprint "eagle-import:C0805")
      (fields (field (name "MPN") "CC0805KRX7R9BB104"))
      (libsource (lib "eagle-import") (part "CERAMIC-100NF-50V-10%-X7R(0805)"))
    )
    (comp (ref "C310")
      (value "100nF")
      (footprint "eagle-import:C0805")
      (fields (field (name "MPN") "CC0805KRX7R9BB104"))
      (libsource (lib "eagle-import") (part "CERAMIC-100NF-50V-10%-X7R(0805)"))
    )
    (comp (ref "D301")
      (value "SM6T")
      (footprint "eagle-import:DO214AA")
      (libsource (lib "eagle-import") (part "SM6T"))
    )
    (comp (ref "D302")
      (value "1N4007,")
      (footprint "eagle-import:DO-214AC")
      (fields (field (name "MPN") "1N4007"))
      (libsource (lib "eagle-import") (part "DIODE-GEN-PURPOSE-1KV-1A(DO-214AC)"))
    )
    (comp (ref "D303")
      (value "1N4007,")
      (footprint "eagle-import:DO-214AC")
      (fields (field (name "MPN") "1N4007"))
      (libsource (lib "eagle-import") (part "DIODE-GEN-PURPOSE-1KV-1A(DO-214AC)"))
    )
    (comp (ref "D304")
      (value "SM6TDO214AA_BI")
      (footprint "eagle-import:DO214AA_BI")
      (libsource (lib "eagle-import") (part "SM6TDO214AA_BI"))
    )
    (comp (ref "D305")
      (value "1N4007.")
      (footprint "eagle-import:DO-214AC")
      (fields (field (name "MPN") "1N4007"))
      (libsource (lib "eagle-import") (part "DIODE-GEN-PURPOSE-1KV-1A(DO-214AC)"))
    )
    (comp (ref "D306")
      (value "1N4007.")
      (footprint "eagle-import:DO-214AC")
      (fields (field (name "MPN") "1N4007"))
      (libsource (lib "eagle-import") (part "DIODE-GEN-PURPOSE-1KV-1A(DO-214AC)"))
    )
    (comp (ref "D307")
      (value "1N5817")
      (footprint "eagle-import:DO-214AC_SLIM")
      (libsource (lib "eagle-import") (part "DIODE-GEN-PURPOSE-1KV-1A(DO-214AC)DO-214AC/1206"))
    )
    (comp (ref "D308")
      (value "1N5817.")
      (footprint "eagle-import:DO-214AC_SLIM")
      (libsource (lib "eagle-import") (part "DIODE-GEN-PURPOSE-1KV-1A(DO-214AC)DO-214AC/1206"))
    )
    (comp (ref "D309")
      (value "1N5817.")
      (footprint "eagle-import:DO-214AC_SLIM")
      (libsource (lib "eagle-import") (part "DIODE-GEN-PURPOSE-1KV-1A(DO-214AC)DO-214AC/1206"))
    )
    (comp (ref "D310")
      (value "1N5817")
      (footprint "eagle-import:DO-214AC_SLIM")
      (libsource (lib "eagle-import") (part "DIODE-GEN-PURPOSE-1KV-1A(DO-214AC)DO-214AC/1206"))
    )
    (comp (ref "D311")
      (value "1N4007")
      (footprint "eagle-import:DO-214AC")
      (libsource (lib "eagle-import") (part "DIODE-GEN-PURPOSE-1KV-1A(DO-214AC)"))
    )
    (comp (ref "D312")
      (value "1N4007")
      (footprint "eagle-import:DO-214AC")
      (libsource (lib "eagle-import") (part "DIODE-GEN-PURPOSE-1KV-1A(DO-214AC)"))
    )
    (comp (ref "FID301")
      (value "FIDUCIAL")
      (footprint "eagle-import:FIDUCIAL_1MM")
      (libsource (lib "eagle-import") (part "FIDUCIAL"))
    )
    (comp (ref "FID302")
      (value "FIDUCIAL")
      (footprint "eagle-import:FIDUCIAL_1MM")
      (libsource (lib "eagle-import") (part "FIDUCIAL"))
    )
    (comp (ref "FID303")
      (value "FIDUCIAL")
      (footprint "eagle-import:FIDUCIAL_1MM")
      (libsource (lib "eagle-import") (part "FIDUCIAL"))
    )
    (comp (ref "FID304")
      (value "FIDUCIAL")
      (footprint "eagle-import:FIDUCIAL_1MM")
      (libsource (lib "eagle-import") (part "FIDUCIAL"))
    )
    (comp (ref "IC301")
      (value "LM2904")
      (footprint "eagle-import:SO08")
      (libsource (lib "eagle-import") (part "LM358D"))
    )
    (comp (ref "IC302")
      (value "78L06")
      (footprint "eagle-import:SOT89_ROUND")
      (libsource (lib "eagle-import") (part "78LXXSOT89_ROUND"))
    )
    (comp (ref "IC303")
      (value "6V pos")
      (footprint "eagle-import:78LXX")
      (libsource (lib "eagle-import") (part "v-reg_78LXX"))
    )
    (comp (ref "IC304")
      (value "78L10")
      (footprint "eagle-import:SOT89_ROUND")
      (libsource (lib "eagle-import") (part "78LXXSOT89_ROUND"))
    )
    (comp (ref "IC305")
      (value "4028")
      (footprint "eagle-import:SO16")
      (libsource (lib "eagle-import") (part "4028D"))
    )
    (comp (ref "IC306")
      (value "NUP4304SOT457_R")
      (footprint "eagle-import:SOT457R_PHILIPS")
      (libsource (lib "eagle-import") (part "NUP4304SOT457_R"))
    )
    (comp (ref "IC307")
      (value "ULN2004")
      (footprint "eagle-import:SO16")
      (libsource (lib "eagle-import") (part "ULN2004AD"))
    )
    (comp (ref "IC308")
      (value "LM339")
      (footprint "eagle-import:SO14")
      (libsource (lib "eagle-import") (part "LM339D"))
    )
    (comp (ref "IC309")
      (value "317TO202H_NOHOLE")
      (footprint "eagle-import:TO220H_NOHOLE")
      (libsource (lib "eagle-import") (part "317TO202H_NOHOLE"))
    )
    (comp (ref "IC310")
      (value "555")
      (footprint "eagle-import:SO08")
      (libsource (lib "eagle-import") (part "555DNE"))
    )
    (comp (ref "IC311")
      (value "4538")
      (footprint "eagle-import:SO16")
      (libsource (lib "eagle-import") (part "4538D"))
    )
    (comp (ref "JP301")
      (value "JP2EJP2_SMALLPADS")
      (footprint "eagle-import:JP2_SMALLPADS")
      (libsource (lib "eagle-import") (part "JP2EJP2_SMALLPADS"))
    )
    (comp (ref "JP302")
      (value "JP2EJP2_SMALLPADS")
      (footprint "eagle-import:JP2_SMALLPADS")
      (libsource (lib "eagle-import") (part "JP2EJP2_SMALLPADS"))
    )
    (comp (ref "JP303")
      (value "JP2EJP2_SMALLPADS")
      (footprint "eagle-import:JP2_SMALLPADS")
      (libsource (lib "eagle-import") (part "JP2EJP2_SMALLPADS"))
    )
    (comp (ref "JP304")
      (value "JP2EJP2_SMALLPADS")
      (footprint "eagle-import:JP2_SMALLPADS")
      (libsource (lib "eagle-import") (part "JP2EJP2_SMALLPADS"))
    )
    (comp (ref "JP305")
      (value "JP2E_ORIG")
      (footprint "eagle-import:JP2_ORIG_SMALLPADS")
      (libsource (lib "eagle-import") (part "JP2E_ORIG"))
    )
    (comp (ref "LED301")
      (value "LEDLD260")
      (footprint "eagle-import:LD260")
      (libsource (lib "eagle-import") (part "LEDLD260"))
    )
    (comp (ref "LED302")
      (value "LEDLD260")
      (footprint "eagle-import:LD260")
      (libsource (lib "eagle-import") (part "LEDLD260"))
    )
    (comp (ref "LED303")
      (value "LEDLD260")
      (footprint "eagle-import:LD260")
      (libsource (lib "eagle-import") (part "LEDLD260"))
    )
    (comp (ref "LED304")
      (value "LEDLD260")
      (footprint "eagle-import:LD260")
      (libsource (lib "eagle-import") (part "LEDLD260"))
    )
    (comp (ref "LED305")
      (value "LEDLD260")
      (footprint "eagle-import:LD260")
      (libsource (lib "eagle-import") (part "LEDLD260"))
    )
    (comp (ref "LED306")
      (value "LEDLD260")
      (footprint "eagle-import:LD260")
      (libsource (lib "eagle-import") (part "LEDLD260"))
    )
    (comp (ref "Q301")
      (value "BA.")
      (footprint "eagle-import:SOT89")
      (libsource (lib "eagle-import") (part "PNP-TRANSISTOR_SOT89"))
    )
    (comp (ref "Q302")
      (value "BA.")
      (footprint "eagle-import:SOT89")
      (libsource (lib "eagle-import") (part "PNP-TRANSISTOR_SOT89"))
    )
    (comp (ref "Q303")
      (value "MY")
      (footprint "eagle-import:SOT89")
      (libsource (lib "eagle-import") (part "NPN-TRANSISTOR_SOT89"))
    )
    (comp (ref "Q304")
      (value "BA")
      (footprint "eagle-import:SOT89")
      (libsource (lib "eagle-import") (part "PNP-TRANSISTOR_SOT89"))
    )
    (comp (ref "Q305")
      (value "BA")
      (footprint "eagle-import:SOT89")
      (libsource (lib "eagle-import") (part "PNP-TRANSISTOR_SOT89"))
    )
    (comp (ref "Q306")
      (value "J1")
      (footprint "eagle-import:SOT-23")
      (fields (field (name "MPN") "BSS138W-7-F"))
      (libsource (lib "eagle-import") (part "SMD-MOSFET-N-CH-50V-200MA-BSS138W-7-F(SOT-23)"))
    )
    (comp (ref "Q307")
      (value "J1")
      (footprint "eagle-import:SOT-23")
      (fields (field (name "MPN") "BSS138W-7-F"))
      (libsource (lib "eagle-import") (part "SMD-MOSFET-N-CH-50V-200MA-BSS138W-7-F(SOT-23)"))
    )
    (comp (ref "R301")
      (value "102")
      (footprint "eagle-import:R0805")
      (fields (field (name "MPN") "RC0805JR-071KL"))
      (libsource (lib "eagle-import") (part "SMD-RES-1K-5%-1/8W(0805)"))
    )
    (comp (ref "R302")
      (value "13")
      (footprint "eagle-import:R1206")
      (fields (field (name "MPN") "RC1206JR-0713RL"))
      (libsource (lib "eagle-import") (part "SMD-RES-13R-5%-1/4W(1206)"))
    )
    (comp (ref "R303")
      (value "R_user")
      (footprint "eagle-import:R0805")
      (libsource (lib "eagle-import") (part "R-EU_R0805"))
    )
    (comp (ref "R304")
      (value "R_user")
      (footprint "eagle-import:R0805")
      (libsource (lib "eagle-import") (part "R-EU_R0805"))
    )
    (comp (ref "R305")
      (value "4701")
      (footprint "eagle-import:R0805")
      (fields (field (name "MPN") "RC0805JR-074K7L"))
      (libsource (lib "eagle-import") (part "SMD-RES-4.7K-5%-1/8W(0805)"))
    )
    (comp (ref "R306")
      (value "13")
      (footprint "eagle-import:R1206")
      (fields (field (name "MPN") "RC1206JR-0713RL"))
      (libsource (lib "eagle-import") (part "SMD-RES-13R-5%-1/4W(1206)"))
    )
    (comp (ref "R307")
      (value "1002")
      (footprint "eagle-import:R0805")
      (fields (field (name "MPN") "RC0805FR-0710KL"))
      (libsource (lib "eagle-import") (part "SMD-RES-10K-1%-1/8W(0805)"))
    )
    (comp (ref "R308")
      (value "1002")
      (footprint "eagle-import:R0805")
      (fields (field (name "MPN") "RC0805FR-0710KL"))
      (libsource (lib "eagle-import") (part "SMD-RES-10K-1%-1/8W(0805)"))
    )
    (comp (ref "R309")
      (value "104")
      (footprint "eagle-import:R0805")
      (fields (field (name "MPN") "RC0805FR-0710KL"))
      (libsource (lib "eagle-import") (part "SMD-RES-10K-1%-1/8W(0805)"))
    )
    (comp (ref "R310")
      (value "104")
      (footprint "eagle-import:R0805")
      (fields (field (name "MPN") "RC0805FR-0710KL"))
      (libsource (lib "eagle-import") (part "SMD-RES-10K-1%-1/8W(0805)"))
    )
    (comp (ref "R311")
      (value "104")
      (footprint "eagle-import:R0805")
      (fields (field (name "MPN") "RC0805FR-0710KL"))
      (libsource (lib "eagle-import") (part "SMD-RES-10K-1%-1/8W(0805)"))
    )
    (comp (ref "R312")
      (value "102")
      (footprint "eagle-import:R0805")
      (fields (field (name "MPN") "RC0805JR-071KL"))
      (libsource (lib "eagle-import") (part "SMD-RES-1K-5%-1/8W(0805)"))
    )
    (comp (ref "R313")
      (value "102")
      (footprint "eagle-import:R0805")
      (fields (field (name "MPN") "RC0805JR-071KL"))
      (libsource (lib "eagle-import") (part "SMD-RES-1K-5%-1/8W(0805)"))
    )
    (comp (ref "R314")
      (value "102")
      (footprint "eagle-import:R0805")
      (fields (field (name "MPN") "RC0805JR-071KL"))
      (libsource (lib "eagle-import") (part "SMD-RES-1K-5%-1/8W(0805)"))
    )
    (comp (ref "R315")
      (value "100")
      (footprint "eagle-import:R0805")
      (fields (field (name "MPN") "RC0805JR-07220RL"))
      (libsource (lib "eagle-import") (part "SMD-RES-220R-5%-1/8W(0805)"))
    )
    (comp (ref "R316")
      (value "4701")
      (footprint "eagle-import:R0805")
      (fields (field (name "MPN") "RC0805JR-074K7L"))
      (libsource (lib "eagle-import") (part "SMD-RES-4.7K-5%-1/8W(0805)"))
    )
    (comp (ref "R317")
      (value "2702")
      (footprint "eagle-import:R0805")
      (fields (field (name "MPN") "RC0805JR-074K7L"))
      (libsource (lib "eagle-import") (part "SMD-RES-4.7K-5%-1/8W(0805)"))
    )
    (comp (ref "R318")
      (value "13")
      (footprint "eagle-import:R1206")
      (fields (field (name "MPN") "RC1206JR-0713RL"))
      (libsource (lib "eagle-import") (part "SMD-RES-13R-5%-1/4W(1206)"))
    )
    (comp (ref "R319")
      (value "2201")
      (footprint "eagle-import:R0805")
      (fields (field (name "MPN") "RC0805JR-072K2L"))
      (libsource (lib "eagle-import") (part "SMD-RES-2.2K-5%-1/8W(0805)"))
    )
    (comp (ref "R320")
      (value "1002")
      (footprint "eagle-import:R0805")
      (fields (field (name "MPN") "RC0805FR-0710KL"))
      (libsource (lib "eagle-import") (part "SMD-RES-10K-1%-1/8W(0805)"))
    )
    (comp (ref "R321")
      (value "1502")
      (footprint "eagle-import:R0805")
      (fields (field (name "MPN") "RC0805FR-0710KL"))
      (libsource (lib "eagle-import") (part "SMD-RES-10K-1%-1/8W(0805)"))
    )
    (comp (ref "R322")
      (value "2702")
      (footprint "eagle-import:R0805")
      (fields (field (name "MPN") "RC0805JR-074K7L"))
      (libsource (lib "eagle-import") (part "SMD-RES-4.7K-5%-1/8W(0805)"))
    )
    (comp (ref "R323")
      (value "2702")
      (footprint "eagle-import:R0805")
      (fields (field (name "MPN") "RC0805JR-074K7L"))
      (libsource (lib "eagle-import") (part "SMD-RES-4.7K-5%-1/8W(0805)"))
    )
    (comp (ref "R324")
      (value "1002")
      (footprint "eagle-import:R0805")
      (fields (field (name "MPN") "RC0805FR-0710KL"))
      (libsource (lib "eagle-import") (part "SMD-RES-10K-1%-1/8W(0805)"))
    )
    (comp (ref "R325")
      (value "104")
      (footprint "eagle-import:R0805")
      (fields (field (name "MPN") "RC0805FR-0710KL"))
      (libsource (lib "eagle-import") (part "SMD-RES-10K-1%-1/8W(0805)"))
    )
    (comp (ref "R326")
      (value "4701")
      (footprint "eagle-import:R0805")
      (fields (field (name "MPN") "RC0805JR-074K7L"))
      (libsource (lib "eagle-import") (part "SMD-RES-4.7K-5%-1/8W(0805)"))
    )
    (comp (ref "R327")
      (value "47")
      (footprint "eagle-import:V235_17_1MM")
      (libsource (lib "eagle-import") (part "R-EU_V235/17_1MM"))
    )
    (comp (ref "R328")
      (value "102")
      (footprint "eagle-import:R0805")
      (fields (field (name "MPN") "RC0805JR-071KL"))
      (libsource (lib "eagle-import") (part "SMD-RES-1K-5%-1/8W(0805)"))
    )
    (comp (ref "R329")
      (value "47")
      (footprint "eagle-import:V235_17_1MM")
      (libsource (lib "eagle-import") (part "R-EU_V235/17_1MM"))
    )
    (comp (ref "R330")
      (value "104")
      (footprint "eagle-import:R0805")
      (fields (field (name "MPN") "RC0805FR-0710KL"))
      (libsource (lib "eagle-import") (part "SMD-RES-10K-1%-1/8W(0805)"))
    )
    (comp (ref "R331")
      (value "1502")
      (footprint "eagle-import:R0805")
      (fields (field (name "MPN") "RC0805FR-0710KL"))
      (libsource (lib "eagle-import") (part "SMD-RES-10K-1%-1/8W(0805)"))
    )
    (comp (ref "R332")
      (value "1002")
      (footprint "eagle-import:R0805")
      (fields (field (name "MPN") "RC0805FR-0710KL"))
      (libsource (lib "eagle-import") (part "SMD-RES-10K-1%-1/8W(0805)"))
    )
    (comp (ref "R333")
      (value "2201")
      (footprint "eagle-import:R0805")
      (fields (field (name "MPN") "RC0805JR-072K2L"))
      (libsource (lib "eagle-import") (part "SMD-RES-2.2K-5%-1/8W(0805)"))
    )
    (comp (ref "R334")
      (value "13")
      (footprint "eagle-import:R1206")
      (fields (field (name "MPN") "RC1206JR-0713RL"))
      (libsource (lib "eagle-import") (part "SMD-RES-13R-5%-1/4W(1206)"))
    )
    (comp (ref "R335")
      (value "104")
      (footprint "eagle-import:R0805")
      (fields (field (name "MPN") "RC0805FR-0710KL"))
      (libsource (lib "eagle-import") (part "SMD-RES-10K-1%-1/8W(0805)"))
    )
    (comp (ref "R336")
      (value "47")
      (footprint "eagle-import:V235_17_1MM")
      (libsource (lib "eagle-import") (part "R-EU_V235/17_1MM"))
    )
    (comp (ref "R337")
      (value "47")
      (footprint "eagle-import:V235_17_1MM")
      (libsource (lib "eagle-import") (part "R-EU_V235/17_1MM"))
    )
    (comp (ref "R338")
      (value "100")
      (footprint "eagle-import:R0805")
      (fields (field (name "MPN") "RC0805JR-072K2L"))
      (libsource (lib "eagle-import") (part "SMD-RES-2.2K-5%-1/8W(0805)"))
    )
    (comp (ref "R339")
      (value "(101)")
      (footprint "eagle-import:R0805")
      (fields (field (name "MPN") "RC0805JR-072K2L"))
      (libsource (lib "eagle-import") (part "SMD-RES-2.2K-5%-1/8W(0805)"))
    )
    (comp (ref "R340")
      (value "2702")
      (footprint "eagle-import:R0805")
      (fields (field (name "MPN") "RC0805FR-0710KL"))
      (libsource (lib "eagle-import") (part "SMD-RES-10K-1%-1/8W(0805)"))
    )
    (comp (ref "R341")
      (value "104")
      (footprint "eagle-import:R0805")
      (fields (field (name "MPN") "RC0805FR-0710KL"))
      (libsource (lib "eagle-import") (part "SMD-RES-10K-1%-1/8W(0805)"))
    )
    (comp (ref "R342")
      (value "(1000)")
      (footprint "eagle-import:R0805")
      (fields (field (name "MPN") "RC0805JR-07100RL"))
      (libsource (lib "eagle-import") (part "SMD-RES-100R-5%-1/8W(0805)"))
    )
    (comp (ref "R343")
      (value "(101)")
      (footprint "eagle-import:R0805")
      (fields (field (name "MPN") "RC0805JR-07100RL"))
      (libsource (lib "eagle-import") (part "SMD-RES-100R-5%-1/8W(0805)"))
    )
    (comp (ref "R344")
      (value "(1002)")
      (footprint "eagle-import:R0805")
      (fields (field (name "MPN") "RC0805FR-0710KL"))
      (libsource (lib "eagle-import") (part "SMD-RES-10K-1%-1/8W(0805)"))
    )
    (comp (ref "R345")
      (value "2702")
      (footprint "eagle-import:R0805")
      (fields (field (name "MPN") "RC0805JR-074K7L"))
      (libsource (lib "eagle-import") (part "SMD-RES-4.7K-5%-1/8W(0805)"))
    )
    (comp (ref "R346")
      (value "(1002)")
      (footprint "eagle-import:R0805")
      (fields (field (name "MPN") "RC0805JR-074K7L"))
      (libsource (lib "eagle-import") (part "SMD-RES-4.7K-5%-1/8W(0805)"))
    )
    (comp (ref "SJ301")
      (value "SJ")
      (footprint "eagle-import:SJ")
      (libsource (lib "eagle-import") (part "SJ"))
    )
    (comp (ref "START301")
      (value "TPSB2.0")
      (footprint "eagle-import:B2.0")
      (libsource (lib "eagle-import") (part "TPSB2.0"))
    )
    (comp (ref "TP47")
      (value "TPSB2.0")
      (footprint "eagle-import:B2.0")
      (libsource (lib "eagle-import") (part "TPSB2.0"))
    )
    (comp (ref "TP48")
      (value "TPSB2.0")
      (footprint "eagle-import:B2.0")
      (libsource (lib "eagle-import") (part "TPSB2.0"))
    )
    (comp (ref "TP49")
      (value "TPSB2.0")
      (footprint "eagle-import:B2.0")
      (libsource (lib "eagle-import") (part "TPSB2.0"))
    )
    (comp (ref "TP50")
      (value "TPSB2.0")
      (footprint "eagle-import:B2.0")
      (libsource (lib "eagle-import") (part "TPSB2.0"))
    )
    (comp (ref "TP51")
      (value "TPSB2.0")
      (footprint "eagle-import:B2.0")
      (libsource (lib "eagle-import") (part "TPSB2.0"))
    )
    (comp (ref "TP52")
      (value "TPSB2.0")
      (footprint "eagle-import:B2.0")
      (libsource (lib "eagle-import") (part "TPSB2.0"))
    )
    (comp (ref "TP53")
      (value "TPSB2.0")
      (footprint "eagle-import:B2.0")
      (libsource (lib "eagle-import") (part "TPSB2.0"))
    )
    (comp (ref "TP54")
      (value "TPSB2.0")
      (footprint "eagle-import:B2.0")
      (libsource (lib "eagle-import") (part "TPSB2.0"))
    )
    (comp (ref "TP55")
      (value "TPSB2.0")
      (footprint "eagle-import:B2.0")
      (libsource (lib "eagle-import") (part "TPSB2.0"))
    )
    (comp (ref "TP56")
      (value "TPSB2.0")
      (footprint "eagle-import:B2.0")
      (libsource (lib "eagle-import") (part "TPSB2.0"))
    )
    (comp (ref "TP57")
      (value "TPSB2.0")
      (footprint "eagle-import:B2.0")
      (libsource (lib "eagle-import") (part "TPSB2.0"))
    )
    (comp (ref "TP58")
      (value "TPSB2.0")
      (footprint "eagle-import:B2.0")
      (libsource (lib "eagle-import") (part "TPSB2.0"))
    )
    (comp (ref "TP59")
      (value "TPSB2.0")
      (footprint "eagle-import:B2.0")
      (libsource (lib "eagle-import") (part "TPSB2.0"))
    )
    (comp (ref "TP60")
      (value "TPSB2.0")
      (footprint "eagle-import:B2.0")
      (libsource (lib "eagle-import") (part "TPSB2.0"))
    )
    (comp (ref "TP61")
      (value "TPSB2.0")
      (footprint "eagle-import:B2.0")
      (libsource (lib "eagle-import") (part "TPSB2.0"))
    )
    (comp (ref "TP62")
      (value "TPSB2.0")
      (footprint "eagle-import:B2.0")
      (libsource (lib "eagle-import") (part "TPSB2.0"))
    )
    (comp (ref "TP63")
      (value "TPSB2.0")
      (footprint "eagle-import:B2.0")
      (libsource (lib "eagle-import") (part "TPSB2.0"))
    )
    (comp (ref "TP64")
      (value "TPSB2.0")
      (footprint "eagle-import:B2.0")
      (libsource (lib "eagle-import") (part "TPSB2.0"))
    )
    (comp (ref "TP65")
      (value "TPSB1,27")
      (footprint "eagle-import:B1,27")
      (libsource (lib "eagle-import") (part "TPSB1,27"))
    )
    (comp (ref "TP66")
      (value "TPSB2.0")
      (footprint "eagle-import:B2.0")
      (libsource (lib "eagle-import") (part "TPSB2.0"))
    )
    (comp (ref "TP67")
      (value "TPSB2.0")
      (footprint "eagle-import:B2.0")
      (libsource (lib "eagle-import") (part "TPSB2.0"))
    )
    (comp (ref "TP68")
      (value "TPSB2.0")
      (footprint "eagle-import:B2.0")
      (libsource (lib "eagle-import") (part "TPSB2.0"))
    )
    (comp (ref "TP69")
      (value "TPSB2.0")
      (footprint "eagle-import:B2.0")
      (libsource (lib "eagle-import") (part "TPSB2.0"))
    )
    (comp (ref "X301")
      (value "CON_BMWV2")
      (footprint "eagle-import:24-PIN_V2")
      (libsource (lib "eagle-import") (part "CON_BMWV2"))
    )
    (comp (ref "X302")
      (value "22-23-2021")
      (footprint "eagle-import:22-23-2021")
      (fields (field (name "MF") "MOLEX"))
      (libsource (lib "eagle-import") (part "22-23-2021"))
    )
    (comp (ref "X303")
      (value "22-23-2051")
      (footprint "eagle-import:22-23-2051")
      (fields (field (name "MF") "MOLEX"))
      (libsource (lib "eagle-import") (part "22-23-2051"))
    )
    (comp (ref "1")
      (value "2081-1132")
      (footprint "eagle-import:12-PIN")
      (libsource (lib "eagle-import") (part "2081-1132"))
    )
    (comp (ref "2")
      (value "2081-1132")
      (footprint "eagle-import:12-PIN")
      (libsource (lib "eagle-import") (part "2081-1132"))
    )
    (comp (ref "6V")
      (value "TPSB2.0")
      (footprint "eagle-import:B2.0")
      (libsource (lib "eagle-import") (part "TPSB2.0"))
    )
    (comp (ref "10V")
      (value "TPSB2.0")
      (footprint "eagle-import:B2.0")
      (libsource (lib "eagle-import") (part "TPSB2.0"))
    )
    (comp (ref "C101")
      (value "4.7u")
      (footprint "eagle-import:C0805")
      (fields (field (name "MPN") "CC0805KKX5R8BB475"))
      (libsource (lib "eagle-import") (part "CERAMIC-4.7UF-25V-10%-X5R(0805)"))
    )
    (comp (ref "C102")
      (value "100nF")
      (footprint "eagle-import:C0805")
      (fields (field (name "MPN") "CC0805KRX7R9BB104"))
      (libsource (lib "eagle-import") (part "CERAMIC-100NF-50V-10%-X7R(0805)"))
    )
    (comp (ref "C103")
      (value "100nF,")
      (footprint "eagle-import:C0805")
      (fields (field (name "MPN") "CC0805KRX7R9BB104"))
      (libsource (lib "eagle-import") (part "CERAMIC-100NF-50V-10%-X7R(0805)"))
    )
    (comp (ref "C104")
      (value "100nF,")
      (footprint "eagle-import:C0805")
      (fields (field (name "MPN") "CC0805KRX7R9BB104"))
      (libsource (lib "eagle-import") (part "CERAMIC-100NF-50V-10%-X7R(0805)"))
    )
    (comp (ref "C105")
      (value "100nF.")
      (footprint "eagle-import:C0805")
      (fields (field (name "MPN") "CC0805KRX7R9BB104"))
      (libsource (lib "eagle-import") (part "CERAMIC-100NF-50V-10%-X7R(0805)"))
    )
    (comp (ref "C106")
      (value "100nF.")
      (footprint "eagle-import:C0805")
      (fields (field (name "MPN") "CC0805KRX7R9BB104"))
      (libsource (lib "eagle-import") (part "CERAMIC-100NF-50V-10%-X7R(0805)"))
    )
    (comp (ref "C107")
      (value "100u")
      (footprint "eagle-import:C1206")
      (fields (field (name "MPN") "GRM31CR60J107ME39L"))
      (libsource (lib "eagle-import") (part "CERAMIC-100UF-6.3V-20%-X5R(1206)"))
    )
    (comp (ref "C108")
      (value "100u")
      (footprint "eagle-import:C1206")
      (fields (field (name "MPN") "GRM31CR60J107ME39L"))
      (libsource (lib "eagle-import") (part "CERAMIC-100UF-6.3V-20%-X5R(1206)"))
    )
    (comp (ref "C109")
      (value "2.2nF")
      (footprint "eagle-import:C0805")
      (fields (field (name "MPN") "CC0805KRX7R9BB104"))
      (libsource (lib "eagle-import") (part "CERAMIC-100NF-50V-10%-X7R(0805)"))
    )
    (comp (ref "C110")
      (value "100nF")
      (footprint "eagle-import:C0805")
      (fields (field (name "MPN") "CC0805KRX7R9BB104"))
      (libsource (lib "eagle-import") (part "CERAMIC-100NF-50V-10%-X7R(0805)"))
    )
    (comp (ref "D101")
      (value "SM6T")
      (footprint "eagle-import:DO214AA")
      (libsource (lib "eagle-import") (part "SM6T"))
    )
    (comp (ref "D102")
      (value "1N4007,")
      (footprint "eagle-import:DO-214AC")
      (fields (field (name "MPN") "1N4007"))
      (libsource (lib "eagle-import") (part "DIODE-GEN-PURPOSE-1KV-1A(DO-214AC)"))
    )
    (comp (ref "D103")
      (value "1N4007,")
      (footprint "eagle-import:DO-214AC")
      (fields (field (name "MPN") "1N4007"))
      (libsource (lib "eagle-import") (part "DIODE-GEN-PURPOSE-1KV-1A(DO-214AC)"))
    )
    (comp (ref "D104")
      (value "SM6TDO214AA_BI")
      (footprint "eagle-import:DO214AA_BI")
      (libsource (lib "eagle-import") (part "SM6TDO214AA_BI"))
    )
    (comp (ref "D105")
      (value "1N4007.")
      (footprint "eagle-import:DO-214AC")
      (fields (field (name "MPN") "1N4007"))
      (libsource (lib "eagle-import") (part "DIODE-GEN-PURPOSE-1KV-1A(DO-214AC)"))
    )
    (comp (ref "D106")
      (value "1N4007.")
      (footprint "eagle-import:DO-214AC")
      (fields (field (name "MPN") "1N4007"))
      (libsource (lib "eagle-import") (part "DIODE-GEN-PURPOSE-1KV-1A(DO-214AC)"))
    )
    (comp (ref "D107")
      (value "1N5817")
      (footprint "eagle-import:DO-214AC_SLIM")
      (libsource (lib "eagle-import") (part "DIODE-GEN-PURPOSE-1KV-1A(DO-214AC)DO-214AC/1206"))
    )
    (comp (ref "D108")
      (value "1N5817.")
      (footprint "eagle-import:DO-214AC_SLIM")
      (libsource (lib "eagle-import") (part "DIODE-GEN-PURPOSE-1KV-1A(DO-214AC)DO-214AC/1206"))
    )
    (comp (ref "D109")
      (value "1N5817.")
      (footprint "eagle-import:DO-214AC_SLIM")
      (libsource (lib "eagle-import") (part "DIODE-GEN-PURPOSE-1KV-1A(DO-214AC)DO-214AC/1206"))
    )
    (comp (ref "D110")
      (value "1N5817")
      (footprint "eagle-import:DO-214AC_SLIM")
      (libsource (lib "eagle-import") (part "DIODE-GEN-PURPOSE-1KV-1A(DO-214AC)DO-214AC/1206"))
    )
    (comp (ref "D111")
      (value "1N4007")
      (footprint "eagle-import:DO-214AC")
      (libsource (lib "eagle-import") (part "DIODE-GEN-PURPOSE-1KV-1A(DO-214AC)"))
    )
    (comp (ref "D112")
      (value "1N4007")
      (footprint "eagle-import:DO-214AC")
      (libsource (lib "eagle-import") (part "DIODE-GEN-PURPOSE-1KV-1A(DO-214AC)"))
    )
    (comp (ref "FID1")
      (value "FIDUCIAL")
      (footprint "eagle-import:FIDUCIAL_1MM")
      (libsource (lib "eagle-import") (part "FIDUCIAL"))
    )
    (comp (ref "FID1B")
      (value "FIDUCIALFIDUCIAL_1MM_WITH_SOLDERMASK")
      (footprint "eagle-import:FIDUCIAL_1MM_WITH_SOLDERMASK")
      (libsource (lib "eagle-import") (part "FIDUCIALFIDUCIAL_1MM_WITH_SOLDERMASK"))
    )
    (comp (ref "FID2")
      (value "FIDUCIAL")
      (footprint "eagle-import:FIDUCIAL_1MM")
      (libsource (lib "eagle-import") (part "FIDUCIAL"))
    )
    (comp (ref "FID2B")
      (value "FIDUCIALFIDUCIAL_1MM_WITH_SOLDERMASK")
      (footprint "eagle-import:FIDUCIAL_1MM_WITH_SOLDERMASK")
      (libsource (lib "eagle-import") (part "FIDUCIALFIDUCIAL_1MM_WITH_SOLDERMASK"))
    )
    (comp (ref "FID101")
      (value "FIDUCIAL")
      (footprint "eagle-import:FIDUCIAL_1MM")
      (libsource (lib "eagle-import") (part "FIDUCIAL"))
    )
    (comp (ref "FID102")
      (value "FIDUCIAL")
      (footprint "eagle-import:FIDUCIAL_1MM")
      (libsource (lib "eagle-import") (part "FIDUCIAL"))
    )
    (comp (ref "FID103")
      (value "FIDUCIAL")
      (footprint "eagle-import:FIDUCIAL_1MM")
      (libsource (lib "eagle-import") (part "FIDUCIAL"))
    )
    (comp (ref "FID104")
      (value "FIDUCIAL")
      (footprint "eagle-import:FIDUCIAL_1MM")
      (libsource (lib "eagle-import") (part "FIDUCIAL"))
    )
    (comp (ref "IC101")
      (value "LM2904")
      (footprint "eagle-import:SO08")
      (libsource (lib "eagle-import") (part "LM358D"))
    )
    (comp (ref "IC102")
      (value "78L06")
      (footprint "eagle-import:SOT89_ROUND")
      (libsource (lib "eagle-import") (part "78LXXSOT89_ROUND"))
    )
    (comp (ref "IC103")
      (value "6V pos")
      (footprint "eagle-import:78LXX")
      (libsource (lib "eagle-import") (part "v-reg_78LXX"))
    )
    (comp (ref "IC104")
      (value "78L10")
      (footprint "eagle-import:SOT89_ROUND")
      (libsource (lib "eagle-import") (part "78LXXSOT89_ROUND"))
    )
    (comp (ref "IC105")
      (value "4028")
      (footprint "eagle-import:SO16")
      (libsource (lib "eagle-import") (part "4028D"))
    )
    (comp (ref "IC106")
      (value "NUP4304SOT457_R")
      (footprint "eagle-import:SOT457R_PHILIPS")
      (libsource (lib "eagle-import") (part "NUP4304SOT457_R"))
    )
    (comp (ref "IC107")
      (value "ULN2004")
      (footprint "eagle-import:SO16")
      (libsource (lib "eagle-import") (part "ULN2004AD"))
    )
    (comp (ref "IC108")
      (value "LM339")
      (footprint "eagle-import:SO14")
      (libsource (lib "eagle-import") (part "LM339D"))
    )
    (comp (ref "IC109")
      (value "317TO202H_NOHOLE")
      (footprint "eagle-import:TO220H_NOHOLE")
      (libsource (lib "eagle-import") (part "317TO202H_NOHOLE"))
    )
    (comp (ref "IC110")
      (value "555")
      (footprint "eagle-import:SO08")
      (libsource (lib "eagle-import") (part "555DNE"))
    )
    (comp (ref "IC111")
      (value "4538")
      (footprint "eagle-import:SO16")
      (libsource (lib "eagle-import") (part "4538D"))
    )
    (comp (ref "JP101")
      (value "JP2EJP2_SMALLPADS")
      (footprint "eagle-import:JP2_SMALLPADS")
      (libsource (lib "eagle-import") (part "JP2EJP2_SMALLPADS"))
    )
    (comp (ref "JP102")
      (value "JP2EJP2_SMALLPADS")
      (footprint "eagle-import:JP2_SMALLPADS")
      (libsource (lib "eagle-import") (part "JP2EJP2_SMALLPADS"))
    )
    (comp (ref "JP103")
      (value "JP2EJP2_SMALLPADS")
      (footprint "eagle-import:JP2_SMALLPADS")
      (libsource (lib "eagle-import") (part "JP2EJP2_SMALLPADS"))
    )
    (comp (ref "JP104")
      (value "JP2EJP2_SMALLPADS")
      (footprint "eagle-import:JP2_SMALLPADS")
      (libsource (lib "eagle-import") (part "JP2EJP2_SMALLPADS"))
    )
    (comp (ref "JP105")
      (value "JP2E_ORIG")
      (footprint "eagle-import:JP2_ORIG_SMALLPADS")
      (libsource (lib "eagle-import") (part "JP2E_ORIG"))
    )
    (comp (ref "LED101")
      (value "LEDLD260")
      (footprint "eagle-import:LD260")
      (libsource (lib "eagle-import") (part "LEDLD260"))
    )
    (comp (ref "LED102")
      (value "LEDLD260")
      (footprint "eagle-import:LD260")
      (libsource (lib "eagle-import") (part "LEDLD260"))
    )
    (comp (ref "LED103")
      (value "LEDLD260")
      (footprint "eagle-import:LD260")
      (libsource (lib "eagle-import") (part "LEDLD260"))
    )
    (comp (ref "LED104")
      (value "LEDLD260")
      (footprint "eagle-import:LD260")
      (libsource (lib "eagle-import") (part "LEDLD260"))
    )
    (comp (ref "LED105")
      (value "LEDLD260")
      (footprint "eagle-import:LD260")
      (libsource (lib "eagle-import") (part "LEDLD260"))
    )
    (comp (ref "LED106")
      (value "LEDLD260")
      (footprint "eagle-import:LD260")
      (libsource (lib "eagle-import") (part "LEDLD260"))
    )
    (comp (ref "Q101")
      (value "BA.")
      (footprint "eagle-import:SOT89")
      (libsource (lib "eagle-import") (part "PNP-TRANSISTOR_SOT89"))
    )
    (comp (ref "Q102")
      (value "BA.")
      (footprint "eagle-import:SOT89")
      (libsource (lib "eagle-import") (part "PNP-TRANSISTOR_SOT89"))
    )
    (comp (ref "Q103")
      (value "MY")
      (footprint "eagle-import:SOT89")
      (libsource (lib "eagle-import") (part "NPN-TRANSISTOR_SOT89"))
    )
    (comp (ref "Q104")
      (value "BA")
      (footprint "eagle-import:SOT89")
      (libsource (lib "eagle-import") (part "PNP-TRANSISTOR_SOT89"))
    )
    (comp (ref "Q105")
      (value "BA")
      (footprint "eagle-import:SOT89")
      (libsource (lib "eagle-import") (part "PNP-TRANSISTOR_SOT89"))
    )
    (comp (ref "Q106")
      (value "J1")
      (footprint "eagle-import:SOT-23")
      (fields (field (name "MPN") "BSS138W-7-F"))
      (libsource (lib "eagle-import") (part "SMD-MOSFET-N-CH-50V-200MA-BSS138W-7-F(SOT-23)"))
    )
    (comp (ref "Q107")
      (value "J1")
      (footprint "eagle-import:SOT-23")
      (fields (field (name "MPN") "BSS138W-7-F"))
      (libsource (lib "eagle-import") (part "SMD-MOSFET-N-CH-50V-200MA-BSS138W-7-F(SOT-23)"))
    )
    (comp (ref "R101")
      (value "102")
      (footprint "eagle-import:R0805")
      (fields (field (name "MPN") "RC0805JR-071KL"))
      (libsource (lib "eagle-import") (part "SMD-RES-1K-5%-1/8W(0805)"))
    )
    (comp (ref "R102")
      (value "13")
      (footprint "eagle-import:R1206")
      (fields (field (name "MPN") "RC1206JR-0713RL"))
      (libsource (lib "eagle-import") (part "SMD-RES-13R-5%-1/4W(1206)"))
    )
    (comp (ref "R103")
      (value "R_user")
      (footprint "eagle-import:R0805")
      (libsource (lib "eagle-import") (part "R-EU_R0805"))
    )
    (comp (ref "R104")
      (value "R_user")
      (footprint "eagle-import:R0805")
      (libsource (lib "eagle-import") (part "R-EU_R0805"))
    )
    (comp (ref "R105")
      (value "4701")
      (footprint "eagle-import:R0805")
      (fields (field (name "MPN") "RC0805JR-074K7L"))
      (libsource (lib "eagle-import") (part "SMD-RES-4.7K-5%-1/8W(0805)"))
    )
    (comp (ref "R106")
      (value "13")
      (footprint "eagle-import:R1206")
      (fields (field (name "MPN") "RC1206JR-0713RL"))
      (libsource (lib "eagle-import") (part "SMD-RES-13R-5%-1/4W(1206)"))
    )
    (comp (ref "R107")
      (value "1002")
      (footprint "eagle-import:R0805")
      (fields (field (name "MPN") "RC0805FR-0710KL"))
      (libsource (lib "eagle-import") (part "SMD-RES-10K-1%-1/8W(0805)"))
    )
    (comp (ref "R108")
      (value "1002")
      (footprint "eagle-import:R0805")
      (fields (field (name "MPN") "RC0805FR-0710KL"))
      (libsource (lib "eagle-import") (part "SMD-RES-10K-1%-1/8W(0805)"))
    )
    (comp (ref "R109")
      (value "104")
      (footprint "eagle-import:R0805")
      (fields (field (name "MPN") "RC0805FR-0710KL"))
      (libsource (lib "eagle-import") (part "SMD-RES-10K-1%-1/8W(0805)"))
    )
    (comp (ref "R110")
      (value "104")
      (footprint "eagle-import:R0805")
      (fields (field (name "MPN") "RC0805FR-0710KL"))
      (libsource (lib "eagle-import") (part "SMD-RES-10K-1%-1/8W(0805)"))
    )
    (comp (ref "R111")
      (value "104")
      (footprint "eagle-import:R0805")
      (fields (field (name "MPN") "RC0805FR-0710KL"))
      (libsource (lib "eagle-import") (part "SMD-RES-10K-1%-1/8W(0805)"))
    )
    (comp (ref "R112")
      (value "102")
      (footprint "eagle-import:R0805")
      (fields (field (name "MPN") "RC0805JR-071KL"))
      (libsource (lib "eagle-import") (part "SMD-RES-1K-5%-1/8W(0805)"))
    )
    (comp (ref "R113")
      (value "102")
      (footprint "eagle-import:R0805")
      (fields (field (name "MPN") "RC0805JR-071KL"))
      (libsource (lib "eagle-import") (part "SMD-RES-1K-5%-1/8W(0805)"))
    )
    (comp (ref "R114")
      (value "102")
      (footprint "eagle-import:R0805")
      (fields (field (name "MPN") "RC0805JR-071KL"))
      (libsource (lib "eagle-import") (part "SMD-RES-1K-5%-1/8W(0805)"))
    )
    (comp (ref "R115")
      (value "100")
      (footprint "eagle-import:R0805")
      (fields (field (name "MPN") "RC0805JR-07220RL"))
      (libsource (lib "eagle-import") (part "SMD-RES-220R-5%-1/8W(0805)"))
    )
    (comp (ref "R116")
      (value "4701")
      (footprint "eagle-import:R0805")
      (fields (field (name "MPN") "RC0805JR-074K7L"))
      (libsource (lib "eagle-import") (part "SMD-RES-4.7K-5%-1/8W(0805)"))
    )
    (comp (ref "R117")
      (value "2702")
      (footprint "eagle-import:R0805")
      (fields (field (name "MPN") "RC0805JR-074K7L"))
      (libsource (lib "eagle-import") (part "SMD-RES-4.7K-5%-1/8W(0805)"))
    )
    (comp (ref "R118")
      (value "13")
      (footprint "eagle-import:R1206")
      (fields (field (name "MPN") "RC1206JR-0713RL"))
      (libsource (lib "eagle-import") (part "SMD-RES-13R-5%-1/4W(1206)"))
    )
    (comp (ref "R119")
      (value "2201")
      (footprint "eagle-import:R0805")
      (fields (field (name "MPN") "RC0805JR-072K2L"))
      (libsource (lib "eagle-import") (part "SMD-RES-2.2K-5%-1/8W(0805)"))
    )
    (comp (ref "R120")
      (value "1002")
      (footprint "eagle-import:R0805")
      (fields (field (name "MPN") "RC0805FR-0710KL"))
      (libsource (lib "eagle-import") (part "SMD-RES-10K-1%-1/8W(0805)"))
    )
    (comp (ref "R121")
      (value "1502")
      (footprint "eagle-import:R0805")
      (fields (field (name "MPN") "RC0805FR-0710KL"))
      (libsource (lib "eagle-import") (part "SMD-RES-10K-1%-1/8W(0805)"))
    )
    (comp (ref "R122")
      (value "2702")
      (footprint "eagle-import:R0805")
      (fields (field (name "MPN") "RC0805JR-074K7L"))
      (libsource (lib "eagle-import") (part "SMD-RES-4.7K-5%-1/8W(0805)"))
    )
    (comp (ref "R123")
      (value "2702")
      (footprint "eagle-import:R0805")
      (fields (field (name "MPN") "RC0805JR-074K7L"))
      (libsource (lib "eagle-import") (part "SMD-RES-4.7K-5%-1/8W(0805)"))
    )
    (comp (ref "R124")
      (value "1002")
      (footprint "eagle-import:R0805")
      (fields (field (name "MPN") "RC0805FR-0710KL"))
      (libsource (lib "eagle-import") (part "SMD-RES-10K-1%-1/8W(0805)"))
    )
    (comp (ref "R125")
      (value "104")
      (footprint "eagle-import:R0805")
      (fields (field (name "MPN") "RC0805FR-0710KL"))
      (libsource (lib "eagle-import") (part "SMD-RES-10K-1%-1/8W(0805)"))
    )
    (comp (ref "R126")
      (value "4701")
      (footprint "eagle-import:R0805")
      (fields (field (name "MPN") "RC0805JR-074K7L"))
      (libsource (lib "eagle-import") (part "SMD-RES-4.7K-5%-1/8W(0805)"))
    )
    (comp (ref "R127")
      (value "47")
      (footprint "eagle-import:V235_17_1MM")
      (libsource (lib "eagle-import") (part "R-EU_V235/17_1MM"))
    )
    (comp (ref "R128")
      (value "102")
      (footprint "eagle-import:R0805")
      (fields (field (name "MPN") "RC0805JR-071KL"))
      (libsource (lib "eagle-import") (part "SMD-RES-1K-5%-1/8W(0805)"))
    )
    (comp (ref "R129")
      (value "47")
      (footprint "eagle-import:V235_17_1MM")
      (libsource (lib "eagle-import") (part "R-EU_V235/17_1MM"))
    )
    (comp (ref "R130")
      (value "104")
      (footprint "eagle-import:R0805")
      (fields (field (name "MPN") "RC0805FR-0710KL"))
      (libsource (lib "eagle-import") (part "SMD-RES-10K-1%-1/8W(0805)"))
    )
    (comp (ref "R131")
      (value "1502")
      (footprint "eagle-import:R0805")
      (fields (field (name "MPN") "RC0805FR-0710KL"))
      (libsource (lib "eagle-import") (part "SMD-RES-10K-1%-1/8W(0805)"))
    )
    (comp (ref "R132")
      (value "1002")
      (footprint "eagle-import:R0805")
      (fields (field (name "MPN") "RC0805FR-0710KL"))
      (libsource (lib "eagle-import") (part "SMD-RES-10K-1%-1/8W(0805)"))
    )
    (comp (ref "R133")
      (value "2201")
      (footprint "eagle-import:R0805")
      (fields (field (name "MPN") "RC0805JR-072K2L"))
      (libsource (lib "eagle-import") (part "SMD-RES-2.2K-5%-1/8W(0805)"))
    )
    (comp (ref "R134")
      (value "13")
      (footprint "eagle-import:R1206")
      (fields (field (name "MPN") "RC1206JR-0713RL"))
      (libsource (lib "eagle-import") (part "SMD-RES-13R-5%-1/4W(1206)"))
    )
    (comp (ref "R135")
      (value "104")
      (footprint "eagle-import:R0805")
      (fields (field (name "MPN") "RC0805FR-0710KL"))
      (libsource (lib "eagle-import") (part "SMD-RES-10K-1%-1/8W(0805)"))
    )
    (comp (ref "R136")
      (value "47")
      (footprint "eagle-import:V235_17_1MM")
      (libsource (lib "eagle-import") (part "R-EU_V235/17_1MM"))
    )
    (comp (ref "R137")
      (value "47")
      (footprint "eagle-import:V235_17_1MM")
      (libsource (lib "eagle-import") (part "R-EU_V235/17_1MM"))
    )
    (comp (ref "R138")
      (value "100")
      (footprint "eagle-import:R0805")
      (fields (field (name "MPN") "RC0805JR-072K2L"))
      (libsource (lib "eagle-import") (part "SMD-RES-2.2K-5%-1/8W(0805)"))
    )
    (comp (ref "R139")
      (value "(101)")
      (footprint "eagle-import:R0805")
      (fields (field (name "MPN") "RC0805JR-072K2L"))
      (libsource (lib "eagle-import") (part "SMD-RES-2.2K-5%-1/8W(0805)"))
    )
    (comp (ref "R140")
      (value "2702")
      (footprint "eagle-import:R0805")
      (fields (field (name "MPN") "RC0805FR-0710KL"))
      (libsource (lib "eagle-import") (part "SMD-RES-10K-1%-1/8W(0805)"))
    )
    (comp (ref "R141")
      (value "104")
      (footprint "eagle-import:R0805")
      (fields (field (name "MPN") "RC0805FR-0710KL"))
      (libsource (lib "eagle-import") (part "SMD-RES-10K-1%-1/8W(0805)"))
    )
    (comp (ref "R142")
      (value "(1000)")
      (footprint "eagle-import:R0805")
      (fields (field (name "MPN") "RC0805JR-07100RL"))
      (libsource (lib "eagle-import") (part "SMD-RES-100R-5%-1/8W(0805)"))
    )
    (comp (ref "R143")
      (value "(101)")
      (footprint "eagle-import:R0805")
      (fields (field (name "MPN") "RC0805JR-07100RL"))
      (libsource (lib "eagle-import") (part "SMD-RES-100R-5%-1/8W(0805)"))
    )
    (comp (ref "R144")
      (value "(1002)")
      (footprint "eagle-import:R0805")
      (fields (field (name "MPN") "RC0805FR-0710KL"))
      (libsource (lib "eagle-import") (part "SMD-RES-10K-1%-1/8W(0805)"))
    )
    (comp (ref "R145")
      (value "2702")
      (footprint "eagle-import:R0805")
      (fields (field (name "MPN") "RC0805JR-074K7L"))
      (libsource (lib "eagle-import") (part "SMD-RES-4.7K-5%-1/8W(0805)"))
    )
    (comp (ref "R146")
      (value "(1002)")
      (footprint "eagle-import:R0805")
      (fields (field (name "MPN") "RC0805JR-074K7L"))
      (libsource (lib "eagle-import") (part "SMD-RES-4.7K-5%-1/8W(0805)"))
    )
    (comp (ref "SJ101")
      (value "SJ")
      (footprint "eagle-import:SJ")
      (libsource (lib "eagle-import") (part "SJ"))
    )
    (comp (ref "START")
      (value "TPSB2.0")
      (footprint "eagle-import:B2.0")
      (libsource (lib "eagle-import") (part "TPSB2.0"))
    )
    (comp (ref "TP1")
      (value "TPSB2.0")
      (footprint "eagle-import:B2.0")
      (libsource (lib "eagle-import") (part "TPSB2.0"))
    )
    (comp (ref "TP2")
      (value "TPSB2.0")
      (footprint "eagle-import:B2.0")
      (libsource (lib "eagle-import") (part "TPSB2.0"))
    )
    (comp (ref "TP3")
      (value "TPSB2.0")
      (footprint "eagle-import:B2.0")
      (libsource (lib "eagle-import") (part "TPSB2.0"))
    )
    (comp (ref "TP4")
      (value "TPSB2.0")
      (footprint "eagle-import:B2.0")
      (libsource (lib "eagle-import") (part "TPSB2.0"))
    )
    (comp (ref "TP5")
      (value "TPSB2.0")
      (footprint "eagle-import:B2.0")
      (libsource (lib "eagle-import") (part "TPSB2.0"))
    )
    (comp (ref "TP6")
      (value "TPSB2.0")
      (footprint "eagle-import:B2.0")
      (libsource (lib "eagle-import") (part "TPSB2.0"))
    )
    (comp (ref "TP7")
      (value "TPSB2.0")
      (footprint "eagle-import:B2.0")
      (libsource (lib "eagle-import") (part "TPSB2.0"))
    )
    (comp (ref "TP8")
      (value "TPSB2.0")
      (footprint "eagle-import:B2.0")
      (libsource (lib "eagle-import") (part "TPSB2.0"))
    )
    (comp (ref "TP9")
      (value "TPSB2.0")
      (footprint "eagle-import:B2.0")
      (libsource (lib "eagle-import") (part "TPSB2.0"))
    )
    (comp (ref "TP10")
      (value "TPSB2.0")
      (footprint "eagle-import:B2.0")
      (libsource (lib "eagle-import") (part "TPSB2.0"))
    )
    (comp (ref "TP11")
      (value "TPSB2.0")
      (footprint "eagle-import:B2.0")
      (libsource (lib "eagle-import") (part "TPSB2.0"))
    )
    (comp (ref "TP12")
      (value "TPSB2.0")
      (footprint "eagle-import:B2.0")
      (libsource (lib "eagle-import") (part "TPSB2.0"))
    )
    (comp (ref "TP13")
      (value "TPSB2.0")
      (footprint "eagle-import:B2.0")
      (libsource (lib "eagle-import") (part "TPSB2.0"))
    )
    (comp (ref "TP16")
      (value "TPSB2.0")
      (footprint "eagle-import:B2.0")
      (libsource (lib "eagle-import") (part "TPSB2.0"))
    )
    (comp (ref "TP17")
      (value "TPSB2.0")
      (footprint "eagle-import:B2.0")
      (libsource (lib "eagle-import") (part "TPSB2.0"))
    )
    (comp (ref "TP18")
      (value "TPSB2.0")
      (footprint "eagle-import:B2.0")
      (libsource (lib "eagle-import") (part "TPSB2.0"))
    )
    (comp (ref "TP19")
      (value "TPSB2.0")
      (footprint "eagle-import:B2.0")
      (libsource (lib "eagle-import") (part "TPSB2.0"))
    )
    (comp (ref "TP21")
      (value "TPSB2.0")
      (footprint "eagle-import:B2.0")
      (libsource (lib "eagle-import") (part "TPSB2.0"))
    )
    (comp (ref "TP22")
      (value "TPSB2.0")
      (footprint "eagle-import:B2.0")
      (libsource (lib "eagle-import") (part "TPSB2.0"))
    )
    (comp (ref "TP23")
      (value "TPSB2.0")
      (footprint "eagle-import:B2.0")
      (libsource (lib "eagle-import") (part "TPSB2.0"))
    )
    (comp (ref "TP24")
      (value "TPSB1,27")
      (footprint "eagle-import:B1,27")
      (libsource (lib "eagle-import") (part "TPSB1,27"))
    )
    (comp (ref "TP25")
      (value "TPSB2.0")
      (footprint "eagle-import:B2.0")
      (libsource (lib "eagle-import") (part "TPSB2.0"))
    )
    (comp (ref "TP26")
      (value "TPSB2.0")
      (footprint "eagle-import:B2.0")
      (libsource (lib "eagle-import") (part "TPSB2.0"))
    )
    (comp (ref "X101")
      (value "CON_BMWV2")
      (footprint "eagle-import:24-PIN_V2")
      (libsource (lib "eagle-import") (part "CON_BMWV2"))
    )
    (comp (ref "X102")
      (value "22-23-2021")
      (footprint "eagle-import:22-23-2021")
      (fields (field (name "MF") "MOLEX"))
      (libsource (lib "eagle-import") (part "22-23-2021"))
    )
    (comp (ref "X103")
      (value "22-23-2051")
      (footprint "eagle-import:22-23-2051")
      (fields (field (name "MF") "MOLEX"))
      (libsource (lib "eagle-import") (part "22-23-2051"))
    )
    (comp (ref "6V501")
      (value "TPSB2.0")
      (footprint "eagle-import:B2.0")
      (libsource (lib "eagle-import") (part "TPSB2.0"))
    )
    (comp (ref "10V501")
      (value "TPSB2.0")
      (footprint "eagle-import:B2.0")
      (libsource (lib "eagle-import") (part "TPSB2.0"))
    )
    (comp (ref "15")
      (value "2081-1132")
      (footprint "eagle-import:12-PIN")
      (libsource (lib "eagle-import") (part "2081-1132"))
    )
    (comp (ref "16")
      (value "2081-1132")
      (footprint "eagle-import:12-PIN")
      (libsource (lib "eagle-import") (part "2081-1132"))
    )
    (comp (ref "C501")
      (value "4.7u")
      (footprint "eagle-import:C0805")
      (fields (field (name "MPN") "CC0805KKX5R8BB475"))
      (libsource (lib "eagle-import") (part "CERAMIC-4.7UF-25V-10%-X5R(0805)"))
    )
    (comp (ref "C502")
      (value "100nF")
      (footprint "eagle-import:C0805")
      (fields (field (name "MPN") "CC0805KRX7R9BB104"))
      (libsource (lib "eagle-import") (part "CERAMIC-100NF-50V-10%-X7R(0805)"))
    )
    (comp (ref "C503")
      (value "100nF,")
      (footprint "eagle-import:C0805")
      (fields (field (name "MPN") "CC0805KRX7R9BB104"))
      (libsource (lib "eagle-import") (part "CERAMIC-100NF-50V-10%-X7R(0805)"))
    )
    (comp (ref "C504")
      (value "100nF,")
      (footprint "eagle-import:C0805")
      (fields (field (name "MPN") "CC0805KRX7R9BB104"))
      (libsource (lib "eagle-import") (part "CERAMIC-100NF-50V-10%-X7R(0805)"))
    )
    (comp (ref "C505")
      (value "100nF.")
      (footprint "eagle-import:C0805")
      (fields (field (name "MPN") "CC0805KRX7R9BB104"))
      (libsource (lib "eagle-import") (part "CERAMIC-100NF-50V-10%-X7R(0805)"))
    )
    (comp (ref "C506")
      (value "100nF.")
      (footprint "eagle-import:C0805")
      (fields (field (name "MPN") "CC0805KRX7R9BB104"))
      (libsource (lib "eagle-import") (part "CERAMIC-100NF-50V-10%-X7R(0805)"))
    )
    (comp (ref "C507")
      (value "100u")
      (footprint "eagle-import:C1206")
      (fields (field (name "MPN") "GRM31CR60J107ME39L"))
      (libsource (lib "eagle-import") (part "CERAMIC-100UF-6.3V-20%-X5R(1206)"))
    )
    (comp (ref "C508")
      (value "100u")
      (footprint "eagle-import:C1206")
      (fields (field (name "MPN") "GRM31CR60J107ME39L"))
      (libsource (lib "eagle-import") (part "CERAMIC-100UF-6.3V-20%-X5R(1206)"))
    )
    (comp (ref "C509")
      (value "2.2nF")
      (footprint "eagle-import:C0805")
      (fields (field (name "MPN") "CC0805KRX7R9BB104"))
      (libsource (lib "eagle-import") (part "CERAMIC-100NF-50V-10%-X7R(0805)"))
    )
    (comp (ref "C510")
      (value "100nF")
      (footprint "eagle-import:C0805")
      (fields (field (name "MPN") "CC0805KRX7R9BB104"))
      (libsource (lib "eagle-import") (part "CERAMIC-100NF-50V-10%-X7R(0805)"))
    )
    (comp (ref "D501")
      (value "SM6T")
      (footprint "eagle-import:DO214AA")
      (libsource (lib "eagle-import") (part "SM6T"))
    )
    (comp (ref "D502")
      (value "1N4007,")
      (footprint "eagle-import:DO-214AC")
      (fields (field (name "MPN") "1N4007"))
      (libsource (lib "eagle-import") (part "DIODE-GEN-PURPOSE-1KV-1A(DO-214AC)"))
    )
    (comp (ref "D503")
      (value "1N4007,")
      (footprint "eagle-import:DO-214AC")
      (fields (field (name "MPN") "1N4007"))
      (libsource (lib "eagle-import") (part "DIODE-GEN-PURPOSE-1KV-1A(DO-214AC)"))
    )
    (comp (ref "D504")
      (value "SM6TDO214AA_BI")
      (footprint "eagle-import:DO214AA_BI")
      (libsource (lib "eagle-import") (part "SM6TDO214AA_BI"))
    )
    (comp (ref "D505")
      (value "1N4007.")
      (footprint "eagle-import:DO-214AC")
      (fields (field (name "MPN") "1N4007"))
      (libsource (lib "eagle-import") (part "DIODE-GEN-PURPOSE-1KV-1A(DO-214AC)"))
    )
    (comp (ref "D506")
      (value "1N4007.")
      (footprint "eagle-import:DO-214AC")
      (fields (field (name "MPN") "1N4007"))
      (libsource (lib "eagle-import") (part "DIODE-GEN-PURPOSE-1KV-1A(DO-214AC)"))
    )
    (comp (ref "D507")
      (value "1N5817")
      (footprint "eagle-import:DO-214AC_SLIM")
      (libsource (lib "eagle-import") (part "DIODE-GEN-PURPOSE-1KV-1A(DO-214AC)DO-214AC/1206"))
    )
    (comp (ref "D508")
      (value "1N5817.")
      (footprint "eagle-import:DO-214AC_SLIM")
      (libsource (lib "eagle-import") (part "DIODE-GEN-PURPOSE-1KV-1A(DO-214AC)DO-214AC/1206"))
    )
    (comp (ref "D509")
      (value "1N5817.")
      (footprint "eagle-import:DO-214AC_SLIM")
      (libsource (lib "eagle-import") (part "DIODE-GEN-PURPOSE-1KV-1A(DO-214AC)DO-214AC/1206"))
    )
    (comp (ref "D510")
      (value "1N5817")
      (footprint "eagle-import:DO-214AC_SLIM")
      (libsource (lib "eagle-import") (part "DIODE-GEN-PURPOSE-1KV-1A(DO-214AC)DO-214AC/1206"))
    )
    (comp (ref "D511")
      (value "1N4007")
      (footprint "eagle-import:DO-214AC")
      (libsource (lib "eagle-import") (part "DIODE-GEN-PURPOSE-1KV-1A(DO-214AC)"))
    )
    (comp (ref "D512")
      (value "1N4007")
      (footprint "eagle-import:DO-214AC")
      (libsource (lib "eagle-import") (part "DIODE-GEN-PURPOSE-1KV-1A(DO-214AC)"))
    )
    (comp (ref "FID501")
      (value "FIDUCIAL")
      (footprint "eagle-import:FIDUCIAL_1MM")
      (libsource (lib "eagle-import") (part "FIDUCIAL"))
    )
    (comp (ref "FID502")
      (value "FIDUCIAL")
      (footprint "eagle-import:FIDUCIAL_1MM")
      (libsource (lib "eagle-import") (part "FIDUCIAL"))
    )
    (comp (ref "FID503")
      (value "FIDUCIAL")
      (footprint "eagle-import:FIDUCIAL_1MM")
      (libsource (lib "eagle-import") (part "FIDUCIAL"))
    )
    (comp (ref "FID504")
      (value "FIDUCIAL")
      (footprint "eagle-import:FIDUCIAL_1MM")
      (libsource (lib "eagle-import") (part "FIDUCIAL"))
    )
    (comp (ref "IC501")
      (value "LM2904")
      (footprint "eagle-import:SO08")
      (libsource (lib "eagle-import") (part "LM358D"))
    )
    (comp (ref "IC502")
      (value "78L06")
      (footprint "eagle-import:SOT89_ROUND")
      (libsource (lib "eagle-import") (part "78LXXSOT89_ROUND"))
    )
    (comp (ref "IC503")
      (value "6V pos")
      (footprint "eagle-import:78LXX")
      (libsource (lib "eagle-import") (part "v-reg_78LXX"))
    )
    (comp (ref "IC504")
      (value "78L10")
      (footprint "eagle-import:SOT89_ROUND")
      (libsource (lib "eagle-import") (part "78LXXSOT89_ROUND"))
    )
    (comp (ref "IC505")
      (value "4028")
      (footprint "eagle-import:SO16")
      (libsource (lib "eagle-import") (part "4028D"))
    )
    (comp (ref "IC506")
      (value "NUP4304SOT457_R")
      (footprint "eagle-import:SOT457R_PHILIPS")
      (libsource (lib "eagle-import") (part "NUP4304SOT457_R"))
    )
    (comp (ref "IC507")
      (value "ULN2004")
      (footprint "eagle-import:SO16")
      (libsource (lib "eagle-import") (part "ULN2004AD"))
    )
    (comp (ref "IC508")
      (value "LM339")
      (footprint "eagle-import:SO14")
      (libsource (lib "eagle-import") (part "LM339D"))
    )
    (comp (ref "IC509")
      (value "317TO202H_NOHOLE")
      (footprint "eagle-import:TO220H_NOHOLE")
      (libsource (lib "eagle-import") (part "317TO202H_NOHOLE"))
    )
    (comp (ref "IC510")
      (value "555")
      (footprint "eagle-import:SO08")
      (libsource (lib "eagle-import") (part "555DNE"))
    )
    (comp (ref "IC511")
      (value "4538")
      (footprint "eagle-import:SO16")
      (libsource (lib "eagle-import") (part "4538D"))
    )
    (comp (ref "JP501")
      (value "JP2EJP2_SMALLPADS")
      (footprint "eagle-import:JP2_SMALLPADS")
      (libsource (lib "eagle-import") (part "JP2EJP2_SMALLPADS"))
    )
    (comp (ref "JP502")
      (value "JP2EJP2_SMALLPADS")
      (footprint "eagle-import:JP2_SMALLPADS")
      (libsource (lib "eagle-import") (part "JP2EJP2_SMALLPADS"))
    )
    (comp (ref "JP503")
      (value "JP2EJP2_SMALLPADS")
      (footprint "eagle-import:JP2_SMALLPADS")
      (libsource (lib "eagle-import") (part "JP2EJP2_SMALLPADS"))
    )
    (comp (ref "JP504")
      (value "JP2EJP2_SMALLPADS")
      (footprint "eagle-import:JP2_SMALLPADS")
      (libsource (lib "eagle-import") (part "JP2EJP2_SMALLPADS"))
    )
    (comp (ref "JP505")
      (value "JP2E_ORIG")
      (footprint "eagle-import:JP2_ORIG_SMALLPADS")
      (libsource (lib "eagle-import") (part "JP2E_ORIG"))
    )
    (comp (ref "LED501")
      (value "LEDLD260")
      (footprint "eagle-import:LD260")
      (libsource (lib "eagle-import") (part "LEDLD260"))
    )
    (comp (ref "LED502")
      (value "LEDLD260")
      (footprint "eagle-import:LD260")
      (libsource (lib "eagle-import") (part "LEDLD260"))
    )
    (comp (ref "LED503")
      (value "LEDLD260")
      (footprint "eagle-import:LD260")
      (libsource (lib "eagle-import") (part "LEDLD260"))
    )
    (comp (ref "LED504")
      (value "LEDLD260")
      (footprint "eagle-import:LD260")
      (libsource (lib "eagle-import") (part "LEDLD260"))
    )
    (comp (ref "LED505")
      (value "LEDLD260")
      (footprint "eagle-import:LD260")
      (libsource (lib "eagle-import") (part "LEDLD260"))
    )
    (comp (ref "LED506")
      (value "LEDLD260")
      (footprint "eagle-import:LD260")
      (libsource (lib "eagle-import") (part "LEDLD260"))
    )
    (comp (ref "Q501")
      (value "BA.")
      (footprint "eagle-import:SOT89")
      (libsource (lib "eagle-import") (part "PNP-TRANSISTOR_SOT89"))
    )
    (comp (ref "Q502")
      (value "BA.")
      (footprint "eagle-import:SOT89")
      (libsource (lib "eagle-import") (part "PNP-TRANSISTOR_SOT89"))
    )
    (comp (ref "Q503")
      (value "MY")
      (footprint "eagle-import:SOT89")
      (libsource (lib "eagle-import") (part "NPN-TRANSISTOR_SOT89"))
    )
    (comp (ref "Q504")
      (value "BA")
      (footprint "eagle-import:SOT89")
      (libsource (lib "eagle-import") (part "PNP-TRANSISTOR_SOT89"))
    )
    (comp (ref "Q505")
      (value "BA")
      (footprint "eagle-import:SOT89")
      (libsource (lib "eagle-import") (part "PNP-TRANSISTOR_SOT89"))
    )
    (comp (ref "Q506")
      (value "J1")
      (footprint "eagle-import:SOT-23")
      (fields (field (name "MPN") "BSS138W-7-F"))
      (libsource (lib "eagle-import") (part "SMD-MOSFET-N-CH-50V-200MA-BSS138W-7-F(SOT-23)"))
    )
    (comp (ref "Q507")
      (value "J1")
      (footprint "eagle-import:SOT-23")
      (fields (field (name "MPN") "BSS138W-7-F"))
      (libsource (lib "eagle-import") (part "SMD-MOSFET-N-CH-50V-200MA-BSS138W-7-F(SOT-23)"))
    )
    (comp (ref "R501")
      (value "102")
      (footprint "eagle-import:R0805")
      (fields (field (name "MPN") "RC0805JR-071KL"))
      (libsource (lib "eagle-import") (part "SMD-RES-1K-5%-1/8W(0805)"))
    )
    (comp (ref "R502")
      (value "13")
      (footprint "eagle-import:R1206")
      (fields (field (name "MPN") "RC1206JR-0713RL"))
      (libsource (lib "eagle-import") (part "SMD-RES-13R-5%-1/4W(1206)"))
    )
    (comp (ref "R503")
      (value "R_user")
      (footprint "eagle-import:R0805")
      (libsource (lib "eagle-import") (part "R-EU_R0805"))
    )
    (comp (ref "R504")
      (value "R_user")
      (footprint "eagle-import:R0805")
      (libsource (lib "eagle-import") (part "R-EU_R0805"))
    )
    (comp (ref "R505")
      (value "4701")
      (footprint "eagle-import:R0805")
      (fields (field (name "MPN") "RC0805JR-074K7L"))
      (libsource (lib "eagle-import") (part "SMD-RES-4.7K-5%-1/8W(0805)"))
    )
    (comp (ref "R506")
      (value "13")
      (footprint "eagle-import:R1206")
      (fields (field (name "MPN") "RC1206JR-0713RL"))
      (libsource (lib "eagle-import") (part "SMD-RES-13R-5%-1/4W(1206)"))
    )
    (comp (ref "R507")
      (value "1002")
      (footprint "eagle-import:R0805")
      (fields (field (name "MPN") "RC0805FR-0710KL"))
      (libsource (lib "eagle-import") (part "SMD-RES-10K-1%-1/8W(0805)"))
    )
    (comp (ref "R508")
      (value "1002")
      (footprint "eagle-import:R0805")
      (fields (field (name "MPN") "RC0805FR-0710KL"))
      (libsource (lib "eagle-import") (part "SMD-RES-10K-1%-1/8W(0805)"))
    )
    (comp (ref "R509")
      (value "104")
      (footprint "eagle-import:R0805")
      (fields (field (name "MPN") "RC0805FR-0710KL"))
      (libsource (lib "eagle-import") (part "SMD-RES-10K-1%-1/8W(0805)"))
    )
    (comp (ref "R510")
      (value "104")
      (footprint "eagle-import:R0805")
      (fields (field (name "MPN") "RC0805FR-0710KL"))
      (libsource (lib "eagle-import") (part "SMD-RES-10K-1%-1/8W(0805)"))
    )
    (comp (ref "R511")
      (value "104")
      (footprint "eagle-import:R0805")
      (fields (field (name "MPN") "RC0805FR-0710KL"))
      (libsource (lib "eagle-import") (part "SMD-RES-10K-1%-1/8W(0805)"))
    )
    (comp (ref "R512")
      (value "102")
      (footprint "eagle-import:R0805")
      (fields (field (name "MPN") "RC0805JR-071KL"))
      (libsource (lib "eagle-import") (part "SMD-RES-1K-5%-1/8W(0805)"))
    )
    (comp (ref "R513")
      (value "102")
      (footprint "eagle-import:R0805")
      (fields (field (name "MPN") "RC0805JR-071KL"))
      (libsource (lib "eagle-import") (part "SMD-RES-1K-5%-1/8W(0805)"))
    )
    (comp (ref "R514")
      (value "102")
      (footprint "eagle-import:R0805")
      (fields (field (name "MPN") "RC0805JR-071KL"))
      (libsource (lib "eagle-import") (part "SMD-RES-1K-5%-1/8W(0805)"))
    )
    (comp (ref "R515")
      (value "100")
      (footprint "eagle-import:R0805")
      (fields (field (name "MPN") "RC0805JR-07220RL"))
      (libsource (lib "eagle-import") (part "SMD-RES-220R-5%-1/8W(0805)"))
    )
    (comp (ref "R516")
      (value "4701")
      (footprint "eagle-import:R0805")
      (fields (field (name "MPN") "RC0805JR-074K7L"))
      (libsource (lib "eagle-import") (part "SMD-RES-4.7K-5%-1/8W(0805)"))
    )
    (comp (ref "R517")
      (value "2702")
      (footprint "eagle-import:R0805")
      (fields (field (name "MPN") "RC0805JR-074K7L"))
      (libsource (lib "eagle-import") (part "SMD-RES-4.7K-5%-1/8W(0805)"))
    )
    (comp (ref "R518")
      (value "13")
      (footprint "eagle-import:R1206")
      (fields (field (name "MPN") "RC1206JR-0713RL"))
      (libsource (lib "eagle-import") (part "SMD-RES-13R-5%-1/4W(1206)"))
    )
    (comp (ref "R519")
      (value "2201")
      (footprint "eagle-import:R0805")
      (fields (field (name "MPN") "RC0805JR-072K2L"))
      (libsource (lib "eagle-import") (part "SMD-RES-2.2K-5%-1/8W(0805)"))
    )
    (comp (ref "R520")
      (value "1002")
      (footprint "eagle-import:R0805")
      (fields (field (name "MPN") "RC0805FR-0710KL"))
      (libsource (lib "eagle-import") (part "SMD-RES-10K-1%-1/8W(0805)"))
    )
    (comp (ref "R521")
      (value "1502")
      (footprint "eagle-import:R0805")
      (fields (field (name "MPN") "RC0805FR-0710KL"))
      (libsource (lib "eagle-import") (part "SMD-RES-10K-1%-1/8W(0805)"))
    )
    (comp (ref "R522")
      (value "2702")
      (footprint "eagle-import:R0805")
      (fields (field (name "MPN") "RC0805JR-074K7L"))
      (libsource (lib "eagle-import") (part "SMD-RES-4.7K-5%-1/8W(0805)"))
    )
    (comp (ref "R523")
      (value "2702")
      (footprint "eagle-import:R0805")
      (fields (field (name "MPN") "RC0805JR-074K7L"))
      (libsource (lib "eagle-import") (part "SMD-RES-4.7K-5%-1/8W(0805)"))
    )
    (comp (ref "R524")
      (value "1002")
      (footprint "eagle-import:R0805")
      (fields (field (name "MPN") "RC0805FR-0710KL"))
      (libsource (lib "eagle-import") (part "SMD-RES-10K-1%-1/8W(0805)"))
    )
    (comp (ref "R525")
      (value "104")
      (footprint "eagle-import:R0805")
      (fields (field (name "MPN") "RC0805FR-0710KL"))
      (libsource (lib "eagle-import") (part "SMD-RES-10K-1%-1/8W(0805)"))
    )
    (comp (ref "R526")
      (value "4701")
      (footprint "eagle-import:R0805")
      (fields (field (name "MPN") "RC0805JR-074K7L"))
      (libsource (lib "eagle-import") (part "SMD-RES-4.7K-5%-1/8W(0805)"))
    )
    (comp (ref "R527")
      (value "47")
      (footprint "eagle-import:V235_17_1MM")
      (libsource (lib "eagle-import") (part "R-EU_V235/17_1MM"))
    )
    (comp (ref "R528")
      (value "102")
      (footprint "eagle-import:R0805")
      (fields (field (name "MPN") "RC0805JR-071KL"))
      (libsource (lib "eagle-import") (part "SMD-RES-1K-5%-1/8W(0805)"))
    )
    (comp (ref "R529")
      (value "47")
      (footprint "eagle-import:V235_17_1MM")
      (libsource (lib "eagle-import") (part "R-EU_V235/17_1MM"))
    )
    (comp (ref "R530")
      (value "104")
      (footprint "eagle-import:R0805")
      (fields (field (name "MPN") "RC0805FR-0710KL"))
      (libsource (lib "eagle-import") (part "SMD-RES-10K-1%-1/8W(0805)"))
    )
    (comp (ref "R531")
      (value "1502")
      (footprint "eagle-import:R0805")
      (fields (field (name "MPN") "RC0805FR-0710KL"))
      (libsource (lib "eagle-import") (part "SMD-RES-10K-1%-1/8W(0805)"))
    )
    (comp (ref "R532")
      (value "1002")
      (footprint "eagle-import:R0805")
      (fields (field (name "MPN") "RC0805FR-0710KL"))
      (libsource (lib "eagle-import") (part "SMD-RES-10K-1%-1/8W(0805)"))
    )
    (comp (ref "R533")
      (value "2201")
      (footprint "eagle-import:R0805")
      (fields (field (name "MPN") "RC0805JR-072K2L"))
      (libsource (lib "eagle-import") (part "SMD-RES-2.2K-5%-1/8W(0805)"))
    )
    (comp (ref "R534")
      (value "13")
      (footprint "eagle-import:R1206")
      (fields (field (name "MPN") "RC1206JR-0713RL"))
      (libsource (lib "eagle-import") (part "SMD-RES-13R-5%-1/4W(1206)"))
    )
    (comp (ref "R535")
      (value "104")
      (footprint "eagle-import:R0805")
      (fields (field (name "MPN") "RC0805FR-0710KL"))
      (libsource (lib "eagle-import") (part "SMD-RES-10K-1%-1/8W(0805)"))
    )
    (comp (ref "R536")
      (value "47")
      (footprint "eagle-import:V235_17_1MM")
      (libsource (lib "eagle-import") (part "R-EU_V235/17_1MM"))
    )
    (comp (ref "R537")
      (value "47")
      (footprint "eagle-import:V235_17_1MM")
      (libsource (lib "eagle-import") (part "R-EU_V235/17_1MM"))
    )
    (comp (ref "R538")
      (value "100")
      (footprint "eagle-import:R0805")
      (fields (field (name "MPN") "RC0805JR-072K2L"))
      (libsource (lib "eagle-import") (part "SMD-RES-2.2K-5%-1/8W(0805)"))
    )
    (comp (ref "R539")
      (value "(101)")
      (footprint "eagle-import:R0805")
      (fields (field (name "MPN") "RC0805JR-072K2L"))
      (libsource (lib "eagle-import") (part "SMD-RES-2.2K-5%-1/8W(0805)"))
    )
    (comp (ref "R540")
      (value "2702")
      (footprint "eagle-import:R0805")
      (fields (field (name "MPN") "RC0805FR-0710KL"))
      (libsource (lib "eagle-import") (part "SMD-RES-10K-1%-1/8W(0805)"))
    )
    (comp (ref "R541")
      (value "104")
      (footprint "eagle-import:R0805")
      (fields (field (name "MPN") "RC0805FR-0710KL"))
      (libsource (lib "eagle-import") (part "SMD-RES-10K-1%-1/8W(0805)"))
    )
    (comp (ref "R542")
      (value "(1000)")
      (footprint "eagle-import:R0805")
      (fields (field (name "MPN") "RC0805JR-07100RL"))
      (libsource (lib "eagle-import") (part "SMD-RES-100R-5%-1/8W(0805)"))
    )
    (comp (ref "R543")
      (value "(101)")
      (footprint "eagle-import:R0805")
      (fields (field (name "MPN") "RC0805JR-07100RL"))
      (libsource (lib "eagle-import") (part "SMD-RES-100R-5%-1/8W(0805)"))
    )
    (comp (ref "R544")
      (value "(1002)")
      (footprint "eagle-import:R0805")
      (fields (field (name "MPN") "RC0805FR-0710KL"))
      (libsource (lib "eagle-import") (part "SMD-RES-10K-1%-1/8W(0805)"))
    )
    (comp (ref "R545")
      (value "2702")
      (footprint "eagle-import:R0805")
      (fields (field (name "MPN") "RC0805JR-074K7L"))
      (libsource (lib "eagle-import") (part "SMD-RES-4.7K-5%-1/8W(0805)"))
    )
    (comp (ref "R546")
      (value "(1002)")
      (footprint "eagle-import:R0805")
      (fields (field (name "MPN") "RC0805JR-074K7L"))
      (libsource (lib "eagle-import") (part "SMD-RES-4.7K-5%-1/8W(0805)"))
    )
    (comp (ref "SJ501")
      (value "SJ")
      (footprint "eagle-import:SJ")
      (libsource (lib "eagle-import") (part "SJ"))
    )
    (comp (ref "START501")
      (value "TPSB2.0")
      (footprint "eagle-import:B2.0")
      (libsource (lib "eagle-import") (part "TPSB2.0"))
    )
    (comp (ref "TP162")
      (value "TPSB2.0")
      (footprint "eagle-import:B2.0")
      (libsource (lib "eagle-import") (part "TPSB2.0"))
    )
    (comp (ref "TP163")
      (value "TPSB2.0")
      (footprint "eagle-import:B2.0")
      (libsource (lib "eagle-import") (part "TPSB2.0"))
    )
    (comp (ref "TP164")
      (value "TPSB2.0")
      (footprint "eagle-import:B2.0")
      (libsource (lib "eagle-import") (part "TPSB2.0"))
    )
    (comp (ref "TP165")
      (value "TPSB2.0")
      (footprint "eagle-import:B2.0")
      (libsource (lib "eagle-import") (part "TPSB2.0"))
    )
    (comp (ref "TP166")
      (value "TPSB2.0")
      (footprint "eagle-import:B2.0")
      (libsource (lib "eagle-import") (part "TPSB2.0"))
    )
    (comp (ref "TP167")
      (value "TPSB2.0")
      (footprint "eagle-import:B2.0")
      (libsource (lib "eagle-import") (part "TPSB2.0"))
    )
    (comp (ref "TP168")
      (value "TPSB2.0")
      (footprint "eagle-import:B2.0")
      (libsource (lib "eagle-import") (part "TPSB2.0"))
    )
    (comp (ref "TP169")
      (value "TPSB2.0")
      (footprint "eagle-import:B2.0")
      (libsource (lib "eagle-import") (part "TPSB2.0"))
    )
    (comp (ref "TP170")
      (value "TPSB2.0")
      (footprint "eagle-import:B2.0")
      (libsource (lib "eagle-import") (part "TPSB2.0"))
    )
    (comp (ref "TP171")
      (value "TPSB2.0")
      (footprint "eagle-import:B2.0")
      (libsource (lib "eagle-import") (part "TPSB2.0"))
    )
    (comp (ref "TP172")
      (value "TPSB2.0")
      (footprint "eagle-import:B2.0")
      (libsource (lib "eagle-import") (part "TPSB2.0"))
    )
    (comp (ref "TP173")
      (value "TPSB2.0")
      (footprint "eagle-import:B2.0")
      (libsource (lib "eagle-import") (part "TPSB2.0"))
    )
    (comp (ref "TP174")
      (value "TPSB2.0")
      (footprint "eagle-import:B2.0")
      (libsource (lib "eagle-import") (part "TPSB2.0"))
    )
    (comp (ref "TP175")
      (value "TPSB2.0")
      (footprint "eagle-import:B2.0")
      (libsource (lib "eagle-import") (part "TPSB2.0"))
    )
    (comp (ref "TP176")
      (value "TPSB2.0")
      (footprint "eagle-import:B2.0")
      (libsource (lib "eagle-import") (part "TPSB2.0"))
    )
    (comp (ref "TP177")
      (value "TPSB2.0")
      (footprint "eagle-import:B2.0")
      (libsource (lib "eagle-import") (part "TPSB2.0"))
    )
    (comp (ref "TP178")
      (value "TPSB2.0")
      (footprint "eagle-import:B2.0")
      (libsource (lib "eagle-import") (part "TPSB2.0"))
    )
    (comp (ref "TP179")
      (value "TPSB2.0")
      (footprint "eagle-import:B2.0")
      (libsource (lib "eagle-import") (part "TPSB2.0"))
    )
    (comp (ref "TP180")
      (value "TPSB1,27")
      (footprint "eagle-import:B1,27")
      (libsource (lib "eagle-import") (part "TPSB1,27"))
    )
    (comp (ref "TP181")
      (value "TPSB2.0")
      (footprint "eagle-import:B2.0")
      (libsource (lib "eagle-import") (part "TPSB2.0"))
    )
    (comp (ref "TP182")
      (value "TPSB2.0")
      (footprint "eagle-import:B2.0")
      (libsource (lib "eagle-import") (part "TPSB2.0"))
    )
    (comp (ref "TP183")
      (value "TPSB2.0")
      (footprint "eagle-import:B2.0")
      (libsource (lib "eagle-import") (part "TPSB2.0"))
    )
    (comp (ref "TP184")
      (value "TPSB2.0")
      (footprint "eagle-import:B2.0")
      (libsource (lib "eagle-import") (part "TPSB2.0"))
    )
    (comp (ref "X501")
      (value "CON_BMWV2")
      (footprint "eagle-import:24-PIN_V2")
      (libsource (lib "eagle-import") (part "CON_BMWV2"))
    )
    (comp (ref "X502")
      (value "22-23-2021")
      (footprint "eagle-import:22-23-2021")
      (fields (field (name "MF") "MOLEX"))
      (libsource (lib "eagle-import") (part "22-23-2021"))
    )
    (comp (ref "X503")
      (value "22-23-2051")
      (footprint "eagle-import:22-23-2051")
      (fields (field (name "MF") "MOLEX"))
      (libsource (lib "eagle-import") (part "22-23-2051"))
    )
    (comp (ref "3")
      (value "2081-1132")
      (footprint "eagle-import:12-PIN")
      (libsource (lib "eagle-import") (part "2081-1132"))
    )
    (comp (ref "4")
      (value "2081-1132")
      (footprint "eagle-import:12-PIN")
      (libsource (lib "eagle-import") (part "2081-1132"))
    )
    (comp (ref "6V201")
      (value "TPSB2.0")
      (footprint "eagle-import:B2.0")
      (libsource (lib "eagle-import") (part "TPSB2.0"))
    )
    (comp (ref "10V201")
      (value "TPSB2.0")
      (footprint "eagle-import:B2.0")
      (libsource (lib "eagle-import") (part "TPSB2.0"))
    )
    (comp (ref "C201")
      (value "4.7u")
      (footprint "eagle-import:C0805")
      (fields (field (name "MPN") "CC0805KKX5R8BB475"))
      (libsource (lib "eagle-import") (part "CERAMIC-4.7UF-25V-10%-X5R(0805)"))
    )
    (comp (ref "C202")
      (value "100nF")
      (footprint "eagle-import:C0805")
      (fields (field (name "MPN") "CC0805KRX7R9BB104"))
      (libsource (lib "eagle-import") (part "CERAMIC-100NF-50V-10%-X7R(0805)"))
    )
    (comp (ref "C203")
      (value "100nF,")
      (footprint "eagle-import:C0805")
      (fields (field (name "MPN") "CC0805KRX7R9BB104"))
      (libsource (lib "eagle-import") (part "CERAMIC-100NF-50V-10%-X7R(0805)"))
    )
    (comp (ref "C204")
      (value "100nF,")
      (footprint "eagle-import:C0805")
      (fields (field (name "MPN") "CC0805KRX7R9BB104"))
      (libsource (lib "eagle-import") (part "CERAMIC-100NF-50V-10%-X7R(0805)"))
    )
    (comp (ref "C205")
      (value "100nF.")
      (footprint "eagle-import:C0805")
      (fields (field (name "MPN") "CC0805KRX7R9BB104"))
      (libsource (lib "eagle-import") (part "CERAMIC-100NF-50V-10%-X7R(0805)"))
    )
    (comp (ref "C206")
      (value "100nF.")
      (footprint "eagle-import:C0805")
      (fields (field (name "MPN") "CC0805KRX7R9BB104"))
      (libsource (lib "eagle-import") (part "CERAMIC-100NF-50V-10%-X7R(0805)"))
    )
    (comp (ref "C207")
      (value "100u")
      (footprint "eagle-import:C1206")
      (fields (field (name "MPN") "GRM31CR60J107ME39L"))
      (libsource (lib "eagle-import") (part "CERAMIC-100UF-6.3V-20%-X5R(1206)"))
    )
    (comp (ref "C208")
      (value "100u")
      (footprint "eagle-import:C1206")
      (fields (field (name "MPN") "GRM31CR60J107ME39L"))
      (libsource (lib "eagle-import") (part "CERAMIC-100UF-6.3V-20%-X5R(1206)"))
    )
    (comp (ref "C209")
      (value "2.2nF")
      (footprint "eagle-import:C0805")
      (fields (field (name "MPN") "CC0805KRX7R9BB104"))
      (libsource (lib "eagle-import") (part "CERAMIC-100NF-50V-10%-X7R(0805)"))
    )
    (comp (ref "C210")
      (value "100nF")
      (footprint "eagle-import:C0805")
      (fields (field (name "MPN") "CC0805KRX7R9BB104"))
      (libsource (lib "eagle-import") (part "CERAMIC-100NF-50V-10%-X7R(0805)"))
    )
    (comp (ref "D201")
      (value "SM6T")
      (footprint "eagle-import:DO214AA")
      (libsource (lib "eagle-import") (part "SM6T"))
    )
    (comp (ref "D202")
      (value "1N4007,")
      (footprint "eagle-import:DO-214AC")
      (fields (field (name "MPN") "1N4007"))
      (libsource (lib "eagle-import") (part "DIODE-GEN-PURPOSE-1KV-1A(DO-214AC)"))
    )
    (comp (ref "D203")
      (value "1N4007,")
      (footprint "eagle-import:DO-214AC")
      (fields (field (name "MPN") "1N4007"))
      (libsource (lib "eagle-import") (part "DIODE-GEN-PURPOSE-1KV-1A(DO-214AC)"))
    )
    (comp (ref "D204")
      (value "SM6TDO214AA_BI")
      (footprint "eagle-import:DO214AA_BI")
      (libsource (lib "eagle-import") (part "SM6TDO214AA_BI"))
    )
    (comp (ref "D205")
      (value "1N4007.")
      (footprint "eagle-import:DO-214AC")
      (fields (field (name "MPN") "1N4007"))
      (libsource (lib "eagle-import") (part "DIODE-GEN-PURPOSE-1KV-1A(DO-214AC)"))
    )
    (comp (ref "D206")
      (value "1N4007.")
      (footprint "eagle-import:DO-214AC")
      (fields (field (name "MPN") "1N4007"))
      (libsource (lib "eagle-import") (part "DIODE-GEN-PURPOSE-1KV-1A(DO-214AC)"))
    )
    (comp (ref "D207")
      (value "1N5817")
      (footprint "eagle-import:DO-214AC_SLIM")
      (libsource (lib "eagle-import") (part "DIODE-GEN-PURPOSE-1KV-1A(DO-214AC)DO-214AC/1206"))
    )
    (comp (ref "D208")
      (value "1N5817.")
      (footprint "eagle-import:DO-214AC_SLIM")
      (libsource (lib "eagle-import") (part "DIODE-GEN-PURPOSE-1KV-1A(DO-214AC)DO-214AC/1206"))
    )
    (comp (ref "D209")
      (value "1N5817.")
      (footprint "eagle-import:DO-214AC_SLIM")
      (libsource (lib "eagle-import") (part "DIODE-GEN-PURPOSE-1KV-1A(DO-214AC)DO-214AC/1206"))
    )
    (comp (ref "D210")
      (value "1N5817")
      (footprint "eagle-import:DO-214AC_SLIM")
      (libsource (lib "eagle-import") (part "DIODE-GEN-PURPOSE-1KV-1A(DO-214AC)DO-214AC/1206"))
    )
    (comp (ref "D211")
      (value "1N4007")
      (footprint "eagle-import:DO-214AC")
      (libsource (lib "eagle-import") (part "DIODE-GEN-PURPOSE-1KV-1A(DO-214AC)"))
    )
    (comp (ref "D212")
      (value "1N4007")
      (footprint "eagle-import:DO-214AC")
      (libsource (lib "eagle-import") (part "DIODE-GEN-PURPOSE-1KV-1A(DO-214AC)"))
    )
    (comp (ref "FID201")
      (value "FIDUCIAL")
      (footprint "eagle-import:FIDUCIAL_1MM")
      (libsource (lib "eagle-import") (part "FIDUCIAL"))
    )
    (comp (ref "FID202")
      (value "FIDUCIAL")
      (footprint "eagle-import:FIDUCIAL_1MM")
      (libsource (lib "eagle-import") (part "FIDUCIAL"))
    )
    (comp (ref "FID203")
      (value "FIDUCIAL")
      (footprint "eagle-import:FIDUCIAL_1MM")
      (libsource (lib "eagle-import") (part "FIDUCIAL"))
    )
    (comp (ref "FID204")
      (value "FIDUCIAL")
      (footprint "eagle-import:FIDUCIAL_1MM")
      (libsource (lib "eagle-import") (part "FIDUCIAL"))
    )
    (comp (ref "IC201")
      (value "LM2904")
      (footprint "eagle-import:SO08")
      (libsource (lib "eagle-import") (part "LM358D"))
    )
    (comp (ref "IC202")
      (value "78L06")
      (footprint "eagle-import:SOT89_ROUND")
      (libsource (lib "eagle-import") (part "78LXXSOT89_ROUND"))
    )
    (comp (ref "IC203")
      (value "6V pos")
      (footprint "eagle-import:78LXX")
      (libsource (lib "eagle-import") (part "v-reg_78LXX"))
    )
    (comp (ref "IC204")
      (value "78L10")
      (footprint "eagle-import:SOT89_ROUND")
      (libsource (lib "eagle-import") (part "78LXXSOT89_ROUND"))
    )
    (comp (ref "IC205")
      (value "4028")
      (footprint "eagle-import:SO16")
      (libsource (lib "eagle-import") (part "4028D"))
    )
    (comp (ref "IC206")
      (value "NUP4304SOT457_R")
      (footprint "eagle-import:SOT457R_PHILIPS")
      (libsource (lib "eagle-import") (part "NUP4304SOT457_R"))
    )
    (comp (ref "IC207")
      (value "ULN2004")
      (footprint "eagle-import:SO16")
      (libsource (lib "eagle-import") (part "ULN2004AD"))
    )
    (comp (ref "IC208")
      (value "LM339")
      (footprint "eagle-import:SO14")
      (libsource (lib "eagle-import") (part "LM339D"))
    )
    (comp (ref "IC209")
      (value "317TO202H_NOHOLE")
      (footprint "eagle-import:TO220H_NOHOLE")
      (libsource (lib "eagle-import") (part "317TO202H_NOHOLE"))
    )
    (comp (ref "IC210")
      (value "555")
      (footprint "eagle-import:SO08")
      (libsource (lib "eagle-import") (part "555DNE"))
    )
    (comp (ref "IC211")
      (value "4538")
      (footprint "eagle-import:SO16")
      (libsource (lib "eagle-import") (part "4538D"))
    )
    (comp (ref "JP201")
      (value "JP2EJP2_SMALLPADS")
      (footprint "eagle-import:JP2_SMALLPADS")
      (libsource (lib "eagle-import") (part "JP2EJP2_SMALLPADS"))
    )
    (comp (ref "JP202")
      (value "JP2EJP2_SMALLPADS")
      (footprint "eagle-import:JP2_SMALLPADS")
      (libsource (lib "eagle-import") (part "JP2EJP2_SMALLPADS"))
    )
    (comp (ref "JP203")
      (value "JP2EJP2_SMALLPADS")
      (footprint "eagle-import:JP2_SMALLPADS")
      (libsource (lib "eagle-import") (part "JP2EJP2_SMALLPADS"))
    )
    (comp (ref "JP204")
      (value "JP2EJP2_SMALLPADS")
      (footprint "eagle-import:JP2_SMALLPADS")
      (libsource (lib "eagle-import") (part "JP2EJP2_SMALLPADS"))
    )
    (comp (ref "JP205")
      (value "JP2E_ORIG")
      (footprint "eagle-import:JP2_ORIG_SMALLPADS")
      (libsource (lib "eagle-import") (part "JP2E_ORIG"))
    )
    (comp (ref "LED201")
      (value "LEDLD260")
      (footprint "eagle-import:LD260")
      (libsource (lib "eagle-import") (part "LEDLD260"))
    )
    (comp (ref "LED202")
      (value "LEDLD260")
      (footprint "eagle-import:LD260")
      (libsource (lib "eagle-import") (part "LEDLD260"))
    )
    (comp (ref "LED203")
      (value "LEDLD260")
      (footprint "eagle-import:LD260")
      (libsource (lib "eagle-import") (part "LEDLD260"))
    )
    (comp (ref "LED204")
      (value "LEDLD260")
      (footprint "eagle-import:LD260")
      (libsource (lib "eagle-import") (part "LEDLD260"))
    )
    (comp (ref "LED205")
      (value "LEDLD260")
      (footprint "eagle-import:LD260")
      (libsource (lib "eagle-import") (part "LEDLD260"))
    )
    (comp (ref "LED206")
      (value "LEDLD260")
      (footprint "eagle-import:LD260")
      (libsource (lib "eagle-import") (part "LEDLD260"))
    )
    (comp (ref "Q201")
      (value "BA.")
      (footprint "eagle-import:SOT89")
      (libsource (lib "eagle-import") (part "PNP-TRANSISTOR_SOT89"))
    )
    (comp (ref "Q202")
      (value "BA.")
      (footprint "eagle-import:SOT89")
      (libsource (lib "eagle-import") (part "PNP-TRANSISTOR_SOT89"))
    )
    (comp (ref "Q203")
      (value "MY")
      (footprint "eagle-import:SOT89")
      (libsource (lib "eagle-import") (part "NPN-TRANSISTOR_SOT89"))
    )
    (comp (ref "Q204")
      (value "BA")
      (footprint "eagle-import:SOT89")
      (libsource (lib "eagle-import") (part "PNP-TRANSISTOR_SOT89"))
    )
    (comp (ref "Q205")
      (value "BA")
      (footprint "eagle-import:SOT89")
      (libsource (lib "eagle-import") (part "PNP-TRANSISTOR_SOT89"))
    )
    (comp (ref "Q206")
      (value "J1")
      (footprint "eagle-import:SOT-23")
      (fields (field (name "MPN") "BSS138W-7-F"))
      (libsource (lib "eagle-import") (part "SMD-MOSFET-N-CH-50V-200MA-BSS138W-7-F(SOT-23)"))
    )
    (comp (ref "Q207")
      (value "J1")
      (footprint "eagle-import:SOT-23")
      (fields (field (name "MPN") "BSS138W-7-F"))
      (libsource (lib "eagle-import") (part "SMD-MOSFET-N-CH-50V-200MA-BSS138W-7-F(SOT-23)"))
    )
    (comp (ref "R201")
      (value "102")
      (footprint "eagle-import:R0805")
      (fields (field (name "MPN") "RC0805JR-071KL"))
      (libsource (lib "eagle-import") (part "SMD-RES-1K-5%-1/8W(0805)"))
    )
    (comp (ref "R202")
      (value "13")
      (footprint "eagle-import:R1206")
      (fields (field (name "MPN") "RC1206JR-0713RL"))
      (libsource (lib "eagle-import") (part "SMD-RES-13R-5%-1/4W(1206)"))
    )
    (comp (ref "R203")
      (value "R_user")
      (footprint "eagle-import:R0805")
      (libsource (lib "eagle-import") (part "R-EU_R0805"))
    )
    (comp (ref "R204")
      (value "R_user")
      (footprint "eagle-import:R0805")
      (libsource (lib "eagle-import") (part "R-EU_R0805"))
    )
    (comp (ref "R205")
      (value "4701")
      (footprint "eagle-import:R0805")
      (fields (field (name "MPN") "RC0805JR-074K7L"))
      (libsource (lib "eagle-import") (part "SMD-RES-4.7K-5%-1/8W(0805)"))
    )
    (comp (ref "R206")
      (value "13")
      (footprint "eagle-import:R1206")
      (fields (field (name "MPN") "RC1206JR-0713RL"))
      (libsource (lib "eagle-import") (part "SMD-RES-13R-5%-1/4W(1206)"))
    )
    (comp (ref "R207")
      (value "1002")
      (footprint "eagle-import:R0805")
      (fields (field (name "MPN") "RC0805FR-0710KL"))
      (libsource (lib "eagle-import") (part "SMD-RES-10K-1%-1/8W(0805)"))
    )
    (comp (ref "R208")
      (value "1002")
      (footprint "eagle-import:R0805")
      (fields (field (name "MPN") "RC0805FR-0710KL"))
      (libsource (lib "eagle-import") (part "SMD-RES-10K-1%-1/8W(0805)"))
    )
    (comp (ref "R209")
      (value "104")
      (footprint "eagle-import:R0805")
      (fields (field (name "MPN") "RC0805FR-0710KL"))
      (libsource (lib "eagle-import") (part "SMD-RES-10K-1%-1/8W(0805)"))
    )
    (comp (ref "R210")
      (value "104")
      (footprint "eagle-import:R0805")
      (fields (field (name "MPN") "RC0805FR-0710KL"))
      (libsource (lib "eagle-import") (part "SMD-RES-10K-1%-1/8W(0805)"))
    )
    (comp (ref "R211")
      (value "104")
      (footprint "eagle-import:R0805")
      (fields (field (name "MPN") "RC0805FR-0710KL"))
      (libsource (lib "eagle-import") (part "SMD-RES-10K-1%-1/8W(0805)"))
    )
    (comp (ref "R212")
      (value "102")
      (footprint "eagle-import:R0805")
      (fields (field (name "MPN") "RC0805JR-071KL"))
      (libsource (lib "eagle-import") (part "SMD-RES-1K-5%-1/8W(0805)"))
    )
    (comp (ref "R213")
      (value "102")
      (footprint "eagle-import:R0805")
      (fields (field (name "MPN") "RC0805JR-071KL"))
      (libsource (lib "eagle-import") (part "SMD-RES-1K-5%-1/8W(0805)"))
    )
    (comp (ref "R214")
      (value "102")
      (footprint "eagle-import:R0805")
      (fields (field (name "MPN") "RC0805JR-071KL"))
      (libsource (lib "eagle-import") (part "SMD-RES-1K-5%-1/8W(0805)"))
    )
    (comp (ref "R215")
      (value "100")
      (footprint "eagle-import:R0805")
      (fields (field (name "MPN") "RC0805JR-07220RL"))
      (libsource (lib "eagle-import") (part "SMD-RES-220R-5%-1/8W(0805)"))
    )
    (comp (ref "R216")
      (value "4701")
      (footprint "eagle-import:R0805")
      (fields (field (name "MPN") "RC0805JR-074K7L"))
      (libsource (lib "eagle-import") (part "SMD-RES-4.7K-5%-1/8W(0805)"))
    )
    (comp (ref "R217")
      (value "2702")
      (footprint "eagle-import:R0805")
      (fields (field (name "MPN") "RC0805JR-074K7L"))
      (libsource (lib "eagle-import") (part "SMD-RES-4.7K-5%-1/8W(0805)"))
    )
    (comp (ref "R218")
      (value "13")
      (footprint "eagle-import:R1206")
      (fields (field (name "MPN") "RC1206JR-0713RL"))
      (libsource (lib "eagle-import") (part "SMD-RES-13R-5%-1/4W(1206)"))
    )
    (comp (ref "R219")
      (value "2201")
      (footprint "eagle-import:R0805")
      (fields (field (name "MPN") "RC0805JR-072K2L"))
      (libsource (lib "eagle-import") (part "SMD-RES-2.2K-5%-1/8W(0805)"))
    )
    (comp (ref "R220")
      (value "1002")
      (footprint "eagle-import:R0805")
      (fields (field (name "MPN") "RC0805FR-0710KL"))
      (libsource (lib "eagle-import") (part "SMD-RES-10K-1%-1/8W(0805)"))
    )
    (comp (ref "R221")
      (value "1502")
      (footprint "eagle-import:R0805")
      (fields (field (name "MPN") "RC0805FR-0710KL"))
      (libsource (lib "eagle-import") (part "SMD-RES-10K-1%-1/8W(0805)"))
    )
    (comp (ref "R222")
      (value "2702")
      (footprint "eagle-import:R0805")
      (fields (field (name "MPN") "RC0805JR-074K7L"))
      (libsource (lib "eagle-import") (part "SMD-RES-4.7K-5%-1/8W(0805)"))
    )
    (comp (ref "R223")
      (value "2702")
      (footprint "eagle-import:R0805")
      (fields (field (name "MPN") "RC0805JR-074K7L"))
      (libsource (lib "eagle-import") (part "SMD-RES-4.7K-5%-1/8W(0805)"))
    )
    (comp (ref "R224")
      (value "1002")
      (footprint "eagle-import:R0805")
      (fields (field (name "MPN") "RC0805FR-0710KL"))
      (libsource (lib "eagle-import") (part "SMD-RES-10K-1%-1/8W(0805)"))
    )
    (comp (ref "R225")
      (value "104")
      (footprint "eagle-import:R0805")
      (fields (field (name "MPN") "RC0805FR-0710KL"))
      (libsource (lib "eagle-import") (part "SMD-RES-10K-1%-1/8W(0805)"))
    )
    (comp (ref "R226")
      (value "4701")
      (footprint "eagle-import:R0805")
      (fields (field (name "MPN") "RC0805JR-074K7L"))
      (libsource (lib "eagle-import") (part "SMD-RES-4.7K-5%-1/8W(0805)"))
    )
    (comp (ref "R227")
      (value "47")
      (footprint "eagle-import:V235_17_1MM")
      (libsource (lib "eagle-import") (part "R-EU_V235/17_1MM"))
    )
    (comp (ref "R228")
      (value "102")
      (footprint "eagle-import:R0805")
      (fields (field (name "MPN") "RC0805JR-071KL"))
      (libsource (lib "eagle-import") (part "SMD-RES-1K-5%-1/8W(0805)"))
    )
    (comp (ref "R229")
      (value "47")
      (footprint "eagle-import:V235_17_1MM")
      (libsource (lib "eagle-import") (part "R-EU_V235/17_1MM"))
    )
    (comp (ref "R230")
      (value "104")
      (footprint "eagle-import:R0805")
      (fields (field (name "MPN") "RC0805FR-0710KL"))
      (libsource (lib "eagle-import") (part "SMD-RES-10K-1%-1/8W(0805)"))
    )
    (comp (ref "R231")
      (value "1502")
      (footprint "eagle-import:R0805")
      (fields (field (name "MPN") "RC0805FR-0710KL"))
      (libsource (lib "eagle-import") (part "SMD-RES-10K-1%-1/8W(0805)"))
    )
    (comp (ref "R232")
      (value "1002")
      (footprint "eagle-import:R0805")
      (fields (field (name "MPN") "RC0805FR-0710KL"))
      (libsource (lib "eagle-import") (part "SMD-RES-10K-1%-1/8W(0805)"))
    )
    (comp (ref "R233")
      (value "2201")
      (footprint "eagle-import:R0805")
      (fields (field (name "MPN") "RC0805JR-072K2L"))
      (libsource (lib "eagle-import") (part "SMD-RES-2.2K-5%-1/8W(0805)"))
    )
    (comp (ref "R234")
      (value "13")
      (footprint "eagle-import:R1206")
      (fields (field (name "MPN") "RC1206JR-0713RL"))
      (libsource (lib "eagle-import") (part "SMD-RES-13R-5%-1/4W(1206)"))
    )
    (comp (ref "R235")
      (value "104")
      (footprint "eagle-import:R0805")
      (fields (field (name "MPN") "RC0805FR-0710KL"))
      (libsource (lib "eagle-import") (part "SMD-RES-10K-1%-1/8W(0805)"))
    )
    (comp (ref "R236")
      (value "47")
      (footprint "eagle-import:V235_17_1MM")
      (libsource (lib "eagle-import") (part "R-EU_V235/17_1MM"))
    )
    (comp (ref "R237")
      (value "47")
      (footprint "eagle-import:V235_17_1MM")
      (libsource (lib "eagle-import") (part "R-EU_V235/17_1MM"))
    )
    (comp (ref "R238")
      (value "100")
      (footprint "eagle-import:R0805")
      (fields (field (name "MPN") "RC0805JR-072K2L"))
      (libsource (lib "eagle-import") (part "SMD-RES-2.2K-5%-1/8W(0805)"))
    )
    (comp (ref "R239")
      (value "(101)")
      (footprint "eagle-import:R0805")
      (fields (field (name "MPN") "RC0805JR-072K2L"))
      (libsource (lib "eagle-import") (part "SMD-RES-2.2K-5%-1/8W(0805)"))
    )
    (comp (ref "R240")
      (value "2702")
      (footprint "eagle-import:R0805")
      (fields (field (name "MPN") "RC0805FR-0710KL"))
      (libsource (lib "eagle-import") (part "SMD-RES-10K-1%-1/8W(0805)"))
    )
    (comp (ref "R241")
      (value "104")
      (footprint "eagle-import:R0805")
      (fields (field (name "MPN") "RC0805FR-0710KL"))
      (libsource (lib "eagle-import") (part "SMD-RES-10K-1%-1/8W(0805)"))
    )
    (comp (ref "R242")
      (value "(1000)")
      (footprint "eagle-import:R0805")
      (fields (field (name "MPN") "RC0805JR-07100RL"))
      (libsource (lib "eagle-import") (part "SMD-RES-100R-5%-1/8W(0805)"))
    )
    (comp (ref "R243")
      (value "(101)")
      (footprint "eagle-import:R0805")
      (fields (field (name "MPN") "RC0805JR-07100RL"))
      (libsource (lib "eagle-import") (part "SMD-RES-100R-5%-1/8W(0805)"))
    )
    (comp (ref "R244")
      (value "(1002)")
      (footprint "eagle-import:R0805")
      (fields (field (name "MPN") "RC0805FR-0710KL"))
      (libsource (lib "eagle-import") (part "SMD-RES-10K-1%-1/8W(0805)"))
    )
    (comp (ref "R245")
      (value "2702")
      (footprint "eagle-import:R0805")
      (fields (field (name "MPN") "RC0805JR-074K7L"))
      (libsource (lib "eagle-import") (part "SMD-RES-4.7K-5%-1/8W(0805)"))
    )
    (comp (ref "R246")
      (value "(1002)")
      (footprint "eagle-import:R0805")
      (fields (field (name "MPN") "RC0805JR-074K7L"))
      (libsource (lib "eagle-import") (part "SMD-RES-4.7K-5%-1/8W(0805)"))
    )
    (comp (ref "SJ201")
      (value "SJ")
      (footprint "eagle-import:SJ")
      (libsource (lib "eagle-import") (part "SJ"))
    )
    (comp (ref "START201")
      (value "TPSB2.0")
      (footprint "eagle-import:B2.0")
      (libsource (lib "eagle-import") (part "TPSB2.0"))
    )
    (comp (ref "TP14")
      (value "TPSB2.0")
      (footprint "eagle-import:B2.0")
      (libsource (lib "eagle-import") (part "TPSB2.0"))
    )
    (comp (ref "TP15")
      (value "TPSB2.0")
      (footprint "eagle-import:B2.0")
      (libsource (lib "eagle-import") (part "TPSB2.0"))
    )
    (comp (ref "TP20")
      (value "TPSB2.0")
      (footprint "eagle-import:B2.0")
      (libsource (lib "eagle-import") (part "TPSB2.0"))
    )
    (comp (ref "TP27")
      (value "TPSB2.0")
      (footprint "eagle-import:B2.0")
      (libsource (lib "eagle-import") (part "TPSB2.0"))
    )
    (comp (ref "TP28")
      (value "TPSB2.0")
      (footprint "eagle-import:B2.0")
      (libsource (lib "eagle-import") (part "TPSB2.0"))
    )
    (comp (ref "TP29")
      (value "TPSB2.0")
      (footprint "eagle-import:B2.0")
      (libsource (lib "eagle-import") (part "TPSB2.0"))
    )
    (comp (ref "TP30")
      (value "TPSB2.0")
      (footprint "eagle-import:B2.0")
      (libsource (lib "eagle-import") (part "TPSB2.0"))
    )
    (comp (ref "TP31")
      (value "TPSB2.0")
      (footprint "eagle-import:B2.0")
      (libsource (lib "eagle-import") (part "TPSB2.0"))
    )
    (comp (ref "TP32")
      (value "TPSB2.0")
      (footprint "eagle-import:B2.0")
      (libsource (lib "eagle-import") (part "TPSB2.0"))
    )
    (comp (ref "TP33")
      (value "TPSB2.0")
      (footprint "eagle-import:B2.0")
      (libsource (lib "eagle-import") (part "TPSB2.0"))
    )
    (comp (ref "TP34")
      (value "TPSB2.0")
      (footprint "eagle-import:B2.0")
      (libsource (lib "eagle-import") (part "TPSB2.0"))
    )
    (comp (ref "TP35")
      (value "TPSB2.0")
      (footprint "eagle-import:B2.0")
      (libsource (lib "eagle-import") (part "TPSB2.0"))
    )
    (comp (ref "TP36")
      (value "TPSB2.0")
      (footprint "eagle-import:B2.0")
      (libsource (lib "eagle-import") (part "TPSB2.0"))
    )
    (comp (ref "TP37")
      (value "TPSB2.0")
      (footprint "eagle-import:B2.0")
      (libsource (lib "eagle-import") (part "TPSB2.0"))
    )
    (comp (ref "TP38")
      (value "TPSB2.0")
      (footprint "eagle-import:B2.0")
      (libsource (lib "eagle-import") (part "TPSB2.0"))
    )
    (comp (ref "TP39")
      (value "TPSB2.0")
      (footprint "eagle-import:B2.0")
      (libsource (lib "eagle-import") (part "TPSB2.0"))
    )
    (comp (ref "TP40")
      (value "TPSB2.0")
      (footprint "eagle-import:B2.0")
      (libsource (lib "eagle-import") (part "TPSB2.0"))
    )
    (comp (ref "TP41")
      (value "TPSB2.0")
      (footprint "eagle-import:B2.0")
      (libsource (lib "eagle-import") (part "TPSB2.0"))
    )
    (comp (ref "TP42")
      (value "TPSB1,27")
      (footprint "eagle-import:B1,27")
      (libsource (lib "eagle-import") (part "TPSB1,27"))
    )
    (comp (ref "TP43")
      (value "TPSB2.0")
      (footprint "eagle-import:B2.0")
      (libsource (lib "eagle-import") (part "TPSB2.0"))
    )
    (comp (ref "TP44")
      (value "TPSB2.0")
      (footprint "eagle-import:B2.0")
      (libsource (lib "eagle-import") (part "TPSB2.0"))
    )
    (comp (ref "TP45")
      (value "TPSB2.0")
      (footprint "eagle-import:B2.0")
      (libsource (lib "eagle-import") (part "TPSB2.0"))
    )
    (comp (ref "TP46")
      (value "TPSB2.0")
      (footprint "eagle-import:B2.0")
      (libsource (lib "eagle-import") (part "TPSB2.0"))
    )
    (comp (ref "X201")
      (value "CON_BMWV2")
      (footprint "eagle-import:24-PIN_V2")
      (libsource (lib "eagle-import") (part "CON_BMWV2"))
    )
    (comp (ref "X202")
      (value "22-23-2021")
      (footprint "eagle-import:22-23-2021")
      (fields (field (name "MF") "MOLEX"))
      (libsource (lib "eagle-import") (part "22-23-2021"))
    )
    (comp (ref "X203")
      (value "22-23-2051")
      (footprint "eagle-import:22-23-2051")
      (fields (field (name "MF") "MOLEX"))
      (libsource (lib "eagle-import") (part "22-23-2051"))
    )
    (comp (ref "6V601")
      (value "TPSB2.0")
      (footprint "eagle-import:B2.0")
      (libsource (lib "eagle-import") (part "TPSB2.0"))
    )
    (comp (ref "10V601")
      (value "TPSB2.0")
      (footprint "eagle-import:B2.0")
      (libsource (lib "eagle-import") (part "TPSB2.0"))
    )
    (comp (ref "17")
      (value "2081-1132")
      (footprint "eagle-import:12-PIN")
      (libsource (lib "eagle-import") (part "2081-1132"))
    )
    (comp (ref "18")
      (value "2081-1132")
      (footprint "eagle-import:12-PIN")
      (libsource (lib "eagle-import") (part "2081-1132"))
    )
    (comp (ref "C601")
      (value "4.7u")
      (footprint "eagle-import:C0805")
      (fields (field (name "MPN") "CC0805KKX5R8BB475"))
      (libsource (lib "eagle-import") (part "CERAMIC-4.7UF-25V-10%-X5R(0805)"))
    )
    (comp (ref "C602")
      (value "100nF")
      (footprint "eagle-import:C0805")
      (fields (field (name "MPN") "CC0805KRX7R9BB104"))
      (libsource (lib "eagle-import") (part "CERAMIC-100NF-50V-10%-X7R(0805)"))
    )
    (comp (ref "C603")
      (value "100nF,")
      (footprint "eagle-import:C0805")
      (fields (field (name "MPN") "CC0805KRX7R9BB104"))
      (libsource (lib "eagle-import") (part "CERAMIC-100NF-50V-10%-X7R(0805)"))
    )
    (comp (ref "C604")
      (value "100nF,")
      (footprint "eagle-import:C0805")
      (fields (field (name "MPN") "CC0805KRX7R9BB104"))
      (libsource (lib "eagle-import") (part "CERAMIC-100NF-50V-10%-X7R(0805)"))
    )
    (comp (ref "C605")
      (value "100nF.")
      (footprint "eagle-import:C0805")
      (fields (field (name "MPN") "CC0805KRX7R9BB104"))
      (libsource (lib "eagle-import") (part "CERAMIC-100NF-50V-10%-X7R(0805)"))
    )
    (comp (ref "C606")
      (value "100nF.")
      (footprint "eagle-import:C0805")
      (fields (field (name "MPN") "CC0805KRX7R9BB104"))
      (libsource (lib "eagle-import") (part "CERAMIC-100NF-50V-10%-X7R(0805)"))
    )
    (comp (ref "C607")
      (value "100u")
      (footprint "eagle-import:C1206")
      (fields (field (name "MPN") "GRM31CR60J107ME39L"))
      (libsource (lib "eagle-import") (part "CERAMIC-100UF-6.3V-20%-X5R(1206)"))
    )
    (comp (ref "C608")
      (value "100u")
      (footprint "eagle-import:C1206")
      (fields (field (name "MPN") "GRM31CR60J107ME39L"))
      (libsource (lib "eagle-import") (part "CERAMIC-100UF-6.3V-20%-X5R(1206)"))
    )
    (comp (ref "C609")
      (value "2.2nF")
      (footprint "eagle-import:C0805")
      (fields (field (name "MPN") "CC0805KRX7R9BB104"))
      (libsource (lib "eagle-import") (part "CERAMIC-100NF-50V-10%-X7R(0805)"))
    )
    (comp (ref "C610")
      (value "100nF")
      (footprint "eagle-import:C0805")
      (fields (field (name "MPN") "CC0805KRX7R9BB104"))
      (libsource (lib "eagle-import") (part "CERAMIC-100NF-50V-10%-X7R(0805)"))
    )
    (comp (ref "D601")
      (value "SM6T")
      (footprint "eagle-import:DO214AA")
      (libsource (lib "eagle-import") (part "SM6T"))
    )
    (comp (ref "D602")
      (value "1N4007,")
      (footprint "eagle-import:DO-214AC")
      (fields (field (name "MPN") "1N4007"))
      (libsource (lib "eagle-import") (part "DIODE-GEN-PURPOSE-1KV-1A(DO-214AC)"))
    )
    (comp (ref "D603")
      (value "1N4007,")
      (footprint "eagle-import:DO-214AC")
      (fields (field (name "MPN") "1N4007"))
      (libsource (lib "eagle-import") (part "DIODE-GEN-PURPOSE-1KV-1A(DO-214AC)"))
    )
    (comp (ref "D604")
      (value "SM6TDO214AA_BI")
      (footprint "eagle-import:DO214AA_BI")
      (libsource (lib "eagle-import") (part "SM6TDO214AA_BI"))
    )
    (comp (ref "D605")
      (value "1N4007.")
      (footprint "eagle-import:DO-214AC")
      (fields (field (name "MPN") "1N4007"))
      (libsource (lib "eagle-import") (part "DIODE-GEN-PURPOSE-1KV-1A(DO-214AC)"))
    )
    (comp (ref "D606")
      (value "1N4007.")
      (footprint "eagle-import:DO-214AC")
      (fields (field (name "MPN") "1N4007"))
      (libsource (lib "eagle-import") (part "DIODE-GEN-PURPOSE-1KV-1A(DO-214AC)"))
    )
    (comp (ref "D607")
      (value "1N5817")
      (footprint "eagle-import:DO-214AC_SLIM")
      (libsource (lib "eagle-import") (part "DIODE-GEN-PURPOSE-1KV-1A(DO-214AC)DO-214AC/1206"))
    )
    (comp (ref "D608")
      (value "1N5817.")
      (footprint "eagle-import:DO-214AC_SLIM")
      (libsource (lib "eagle-import") (part "DIODE-GEN-PURPOSE-1KV-1A(DO-214AC)DO-214AC/1206"))
    )
    (comp (ref "D609")
      (value "1N5817.")
      (footprint "eagle-import:DO-214AC_SLIM")
      (libsource (lib "eagle-import") (part "DIODE-GEN-PURPOSE-1KV-1A(DO-214AC)DO-214AC/1206"))
    )
    (comp (ref "D610")
      (value "1N5817")
      (footprint "eagle-import:DO-214AC_SLIM")
      (libsource (lib "eagle-import") (part "DIODE-GEN-PURPOSE-1KV-1A(DO-214AC)DO-214AC/1206"))
    )
    (comp (ref "D611")
      (value "1N4007")
      (footprint "eagle-import:DO-214AC")
      (libsource (lib "eagle-import") (part "DIODE-GEN-PURPOSE-1KV-1A(DO-214AC)"))
    )
    (comp (ref "D612")
      (value "1N4007")
      (footprint "eagle-import:DO-214AC")
      (libsource (lib "eagle-import") (part "DIODE-GEN-PURPOSE-1KV-1A(DO-214AC)"))
    )
    (comp (ref "FID601")
      (value "FIDUCIAL")
      (footprint "eagle-import:FIDUCIAL_1MM")
      (libsource (lib "eagle-import") (part "FIDUCIAL"))
    )
    (comp (ref "FID602")
      (value "FIDUCIAL")
      (footprint "eagle-import:FIDUCIAL_1MM")
      (libsource (lib "eagle-import") (part "FIDUCIAL"))
    )
    (comp (ref "FID603")
      (value "FIDUCIAL")
      (footprint "eagle-import:FIDUCIAL_1MM")
      (libsource (lib "eagle-import") (part "FIDUCIAL"))
    )
    (comp (ref "FID604")
      (value "FIDUCIAL")
      (footprint "eagle-import:FIDUCIAL_1MM")
      (libsource (lib "eagle-import") (part "FIDUCIAL"))
    )
    (comp (ref "IC601")
      (value "LM2904")
      (footprint "eagle-import:SO08")
      (libsource (lib "eagle-import") (part "LM358D"))
    )
    (comp (ref "IC602")
      (value "78L06")
      (footprint "eagle-import:SOT89_ROUND")
      (libsource (lib "eagle-import") (part "78LXXSOT89_ROUND"))
    )
    (comp (ref "IC603")
      (value "6V pos")
      (footprint "eagle-import:78LXX")
      (libsource (lib "eagle-import") (part "v-reg_78LXX"))
    )
    (comp (ref "IC604")
      (value "78L10")
      (footprint "eagle-import:SOT89_ROUND")
      (libsource (lib "eagle-import") (part "78LXXSOT89_ROUND"))
    )
    (comp (ref "IC605")
      (value "4028")
      (footprint "eagle-import:SO16")
      (libsource (lib "eagle-import") (part "4028D"))
    )
    (comp (ref "IC606")
      (value "NUP4304SOT457_R")
      (footprint "eagle-import:SOT457R_PHILIPS")
      (libsource (lib "eagle-import") (part "NUP4304SOT457_R"))
    )
    (comp (ref "IC607")
      (value "ULN2004")
      (footprint "eagle-import:SO16")
      (libsource (lib "eagle-import") (part "ULN2004AD"))
    )
    (comp (ref "IC608")
      (value "LM339")
      (footprint "eagle-import:SO14")
      (libsource (lib "eagle-import") (part "LM339D"))
    )
    (comp (ref "IC609")
      (value "317TO202H_NOHOLE")
      (footprint "eagle-import:TO220H_NOHOLE")
      (libsource (lib "eagle-import") (part "317TO202H_NOHOLE"))
    )
    (comp (ref "IC610")
      (value "555")
      (footprint "eagle-import:SO08")
      (libsource (lib "eagle-import") (part "555DNE"))
    )
    (comp (ref "IC611")
      (value "4538")
      (footprint "eagle-import:SO16")
      (libsource (lib "eagle-import") (part "4538D"))
    )
    (comp (ref "JP601")
      (value "JP2EJP2_SMALLPADS")
      (footprint "eagle-import:JP2_SMALLPADS")
      (libsource (lib "eagle-import") (part "JP2EJP2_SMALLPADS"))
    )
    (comp (ref "JP602")
      (value "JP2EJP2_SMALLPADS")
      (footprint "eagle-import:JP2_SMALLPADS")
      (libsource (lib "eagle-import") (part "JP2EJP2_SMALLPADS"))
    )
    (comp (ref "JP603")
      (value "JP2EJP2_SMALLPADS")
      (footprint "eagle-import:JP2_SMALLPADS")
      (libsource (lib "eagle-import") (part "JP2EJP2_SMALLPADS"))
    )
    (comp (ref "JP604")
      (value "JP2EJP2_SMALLPADS")
      (footprint "eagle-import:JP2_SMALLPADS")
      (libsource (lib "eagle-import") (part "JP2EJP2_SMALLPADS"))
    )
    (comp (ref "JP605")
      (value "JP2E_ORIG")
      (footprint "eagle-import:JP2_ORIG_SMALLPADS")
      (libsource (lib "eagle-import") (part "JP2E_ORIG"))
    )
    (comp (ref "LED601")
      (value "LEDLD260")
      (footprint "eagle-import:LD260")
      (libsource (lib "eagle-import") (part "LEDLD260"))
    )
    (comp (ref "LED602")
      (value "LEDLD260")
      (footprint "eagle-import:LD260")
      (libsource (lib "eagle-import") (part "LEDLD260"))
    )
    (comp (ref "LED603")
      (value "LEDLD260")
      (footprint "eagle-import:LD260")
      (libsource (lib "eagle-import") (part "LEDLD260"))
    )
    (comp (ref "LED604")
      (value "LEDLD260")
      (footprint "eagle-import:LD260")
      (libsource (lib "eagle-import") (part "LEDLD260"))
    )
    (comp (ref "LED605")
      (value "LEDLD260")
      (footprint "eagle-import:LD260")
      (libsource (lib "eagle-import") (part "LEDLD260"))
    )
    (comp (ref "LED606")
      (value "LEDLD260")
      (footprint "eagle-import:LD260")
      (libsource (lib "eagle-import") (part "LEDLD260"))
    )
    (comp (ref "Q601")
      (value "BA.")
      (footprint "eagle-import:SOT89")
      (libsource (lib "eagle-import") (part "PNP-TRANSISTOR_SOT89"))
    )
    (comp (ref "Q602")
      (value "BA.")
      (footprint "eagle-import:SOT89")
      (libsource (lib "eagle-import") (part "PNP-TRANSISTOR_SOT89"))
    )
    (comp (ref "Q603")
      (value "MY")
      (footprint "eagle-import:SOT89")
      (libsource (lib "eagle-import") (part "NPN-TRANSISTOR_SOT89"))
    )
    (comp (ref "Q604")
      (value "BA")
      (footprint "eagle-import:SOT89")
      (libsource (lib "eagle-import") (part "PNP-TRANSISTOR_SOT89"))
    )
    (comp (ref "Q605")
      (value "BA")
      (footprint "eagle-import:SOT89")
      (libsource (lib "eagle-import") (part "PNP-TRANSISTOR_SOT89"))
    )
    (comp (ref "Q606")
      (value "J1")
      (footprint "eagle-import:SOT-23")
      (fields (field (name "MPN") "BSS138W-7-F"))
      (libsource (lib "eagle-import") (part "SMD-MOSFET-N-CH-50V-200MA-BSS138W-7-F(SOT-23)"))
    )
    (comp (ref "Q607")
      (value "J1")
      (footprint "eagle-import:SOT-23")
      (fields (field (name "MPN") "BSS138W-7-F"))
      (libsource (lib "eagle-import") (part "SMD-MOSFET-N-CH-50V-200MA-BSS138W-7-F(SOT-23)"))
    )
    (comp (ref "R601")
      (value "102")
      (footprint "eagle-import:R0805")
      (fields (field (name "MPN") "RC0805JR-071KL"))
      (libsource (lib "eagle-import") (part "SMD-RES-1K-5%-1/8W(0805)"))
    )
    (comp (ref "R602")
      (value "13")
      (footprint "eagle-import:R1206")
      (fields (field (name "MPN") "RC1206JR-0713RL"))
      (libsource (lib "eagle-import") (part "SMD-RES-13R-5%-1/4W(1206)"))
    )
    (comp (ref "R603")
      (value "R_user")
      (footprint "eagle-import:R0805")
      (libsource (lib "eagle-import") (part "R-EU_R0805"))
    )
    (comp (ref "R604")
      (value "R_user")
      (footprint "eagle-import:R0805")
      (libsource (lib "eagle-import") (part "R-EU_R0805"))
    )
    (comp (ref "R605")
      (value "4701")
      (footprint "eagle-import:R0805")
      (fields (field (name "MPN") "RC0805JR-074K7L"))
      (libsource (lib "eagle-import") (part "SMD-RES-4.7K-5%-1/8W(0805)"))
    )
    (comp (ref "R606")
      (value "13")
      (footprint "eagle-import:R1206")
      (fields (field (name "MPN") "RC1206JR-0713RL"))
      (libsource (lib "eagle-import") (part "SMD-RES-13R-5%-1/4W(1206)"))
    )
    (comp (ref "R607")
      (value "1002")
      (footprint "eagle-import:R0805")
      (fields (field (name "MPN") "RC0805FR-0710KL"))
      (libsource (lib "eagle-import") (part "SMD-RES-10K-1%-1/8W(0805)"))
    )
    (comp (ref "R608")
      (value "1002")
      (footprint "eagle-import:R0805")
      (fields (field (name "MPN") "RC0805FR-0710KL"))
      (libsource (lib "eagle-import") (part "SMD-RES-10K-1%-1/8W(0805)"))
    )
    (comp (ref "R609")
      (value "104")
      (footprint "eagle-import:R0805")
      (fields (field (name "MPN") "RC0805FR-0710KL"))
      (libsource (lib "eagle-import") (part "SMD-RES-10K-1%-1/8W(0805)"))
    )
    (comp (ref "R610")
      (value "104")
      (footprint "eagle-import:R0805")
      (fields (field (name "MPN") "RC0805FR-0710KL"))
      (libsource (lib "eagle-import") (part "SMD-RES-10K-1%-1/8W(0805)"))
    )
    (comp (ref "R611")
      (value "104")
      (footprint "eagle-import:R0805")
      (fields (field (name "MPN") "RC0805FR-0710KL"))
      (libsource (lib "eagle-import") (part "SMD-RES-10K-1%-1/8W(0805)"))
    )
    (comp (ref "R612")
      (value "102")
      (footprint "eagle-import:R0805")
      (fields (field (name "MPN") "RC0805JR-071KL"))
      (libsource (lib "eagle-import") (part "SMD-RES-1K-5%-1/8W(0805)"))
    )
    (comp (ref "R613")
      (value "102")
      (footprint "eagle-import:R0805")
      (fields (field (name "MPN") "RC0805JR-071KL"))
      (libsource (lib "eagle-import") (part "SMD-RES-1K-5%-1/8W(0805)"))
    )
    (comp (ref "R614")
      (value "102")
      (footprint "eagle-import:R0805")
      (fields (field (name "MPN") "RC0805JR-071KL"))
      (libsource (lib "eagle-import") (part "SMD-RES-1K-5%-1/8W(0805)"))
    )
    (comp (ref "R615")
      (value "100")
      (footprint "eagle-import:R0805")
      (fields (field (name "MPN") "RC0805JR-07220RL"))
      (libsource (lib "eagle-import") (part "SMD-RES-220R-5%-1/8W(0805)"))
    )
    (comp (ref "R616")
      (value "4701")
      (footprint "eagle-import:R0805")
      (fields (field (name "MPN") "RC0805JR-074K7L"))
      (libsource (lib "eagle-import") (part "SMD-RES-4.7K-5%-1/8W(0805)"))
    )
    (comp (ref "R617")
      (value "2702")
      (footprint "eagle-import:R0805")
      (fields (field (name "MPN") "RC0805JR-074K7L"))
      (libsource (lib "eagle-import") (part "SMD-RES-4.7K-5%-1/8W(0805)"))
    )
    (comp (ref "R618")
      (value "13")
      (footprint "eagle-import:R1206")
      (fields (field (name "MPN") "RC1206JR-0713RL"))
      (libsource (lib "eagle-import") (part "SMD-RES-13R-5%-1/4W(1206)"))
    )
    (comp (ref "R619")
      (value "2201")
      (footprint "eagle-import:R0805")
      (fields (field (name "MPN") "RC0805JR-072K2L"))
      (libsource (lib "eagle-import") (part "SMD-RES-2.2K-5%-1/8W(0805)"))
    )
    (comp (ref "R620")
      (value "1002")
      (footprint "eagle-import:R0805")
      (fields (field (name "MPN") "RC0805FR-0710KL"))
      (libsource (lib "eagle-import") (part "SMD-RES-10K-1%-1/8W(0805)"))
    )
    (comp (ref "R621")
      (value "1502")
      (footprint "eagle-import:R0805")
      (fields (field (name "MPN") "RC0805FR-0710KL"))
      (libsource (lib "eagle-import") (part "SMD-RES-10K-1%-1/8W(0805)"))
    )
    (comp (ref "R622")
      (value "2702")
      (footprint "eagle-import:R0805")
      (fields (field (name "MPN") "RC0805JR-074K7L"))
      (libsource (lib "eagle-import") (part "SMD-RES-4.7K-5%-1/8W(0805)"))
    )
    (comp (ref "R623")
      (value "2702")
      (footprint "eagle-import:R0805")
      (fields (field (name "MPN") "RC0805JR-074K7L"))
      (libsource (lib "eagle-import") (part "SMD-RES-4.7K-5%-1/8W(0805)"))
    )
    (comp (ref "R624")
      (value "1002")
      (footprint "eagle-import:R0805")
      (fields (field (name "MPN") "RC0805FR-0710KL"))
      (libsource (lib "eagle-import") (part "SMD-RES-10K-1%-1/8W(0805)"))
    )
    (comp (ref "R625")
      (value "104")
      (footprint "eagle-import:R0805")
      (fields (field (name "MPN") "RC0805FR-0710KL"))
      (libsource (lib "eagle-import") (part "SMD-RES-10K-1%-1/8W(0805)"))
    )
    (comp (ref "R626")
      (value "4701")
      (footprint "eagle-import:R0805")
      (fields (field (name "MPN") "RC0805JR-074K7L"))
      (libsource (lib "eagle-import") (part "SMD-RES-4.7K-5%-1/8W(0805)"))
    )
    (comp (ref "R627")
      (value "47")
      (footprint "eagle-import:V235_17_1MM")
      (libsource (lib "eagle-import") (part "R-EU_V235/17_1MM"))
    )
    (comp (ref "R628")
      (value "102")
      (footprint "eagle-import:R0805")
      (fields (field (name "MPN") "RC0805JR-071KL"))
      (libsource (lib "eagle-import") (part "SMD-RES-1K-5%-1/8W(0805)"))
    )
    (comp (ref "R629")
      (value "47")
      (footprint "eagle-import:V235_17_1MM")
      (libsource (lib "eagle-import") (part "R-EU_V235/17_1MM"))
    )
    (comp (ref "R630")
      (value "104")
      (footprint "eagle-import:R0805")
      (fields (field (name "MPN") "RC0805FR-0710KL"))
      (libsource (lib "eagle-import") (part "SMD-RES-10K-1%-1/8W(0805)"))
    )
    (comp (ref "R631")
      (value "1502")
      (footprint "eagle-import:R0805")
      (fields (field (name "MPN") "RC0805FR-0710KL"))
      (libsource (lib "eagle-import") (part "SMD-RES-10K-1%-1/8W(0805)"))
    )
    (comp (ref "R632")
      (value "1002")
      (footprint "eagle-import:R0805")
      (fields (field (name "MPN") "RC0805FR-0710KL"))
      (libsource (lib "eagle-import") (part "SMD-RES-10K-1%-1/8W(0805)"))
    )
    (comp (ref "R633")
      (value "2201")
      (footprint "eagle-import:R0805")
      (fields (field (name "MPN") "RC0805JR-072K2L"))
      (libsource (lib "eagle-import") (part "SMD-RES-2.2K-5%-1/8W(0805)"))
    )
    (comp (ref "R634")
      (value "13")
      (footprint "eagle-import:R1206")
      (fields (field (name "MPN") "RC1206JR-0713RL"))
      (libsource (lib "eagle-import") (part "SMD-RES-13R-5%-1/4W(1206)"))
    )
    (comp (ref "R635")
      (value "104")
      (footprint "eagle-import:R0805")
      (fields (field (name "MPN") "RC0805FR-0710KL"))
      (libsource (lib "eagle-import") (part "SMD-RES-10K-1%-1/8W(0805)"))
    )
    (comp (ref "R636")
      (value "47")
      (footprint "eagle-import:V235_17_1MM")
      (libsource (lib "eagle-import") (part "R-EU_V235/17_1MM"))
    )
    (comp (ref "R637")
      (value "47")
      (footprint "eagle-import:V235_17_1MM")
      (libsource (lib "eagle-import") (part "R-EU_V235/17_1MM"))
    )
    (comp (ref "R638")
      (value "100")
      (footprint "eagle-import:R0805")
      (fields (field (name "MPN") "RC0805JR-072K2L"))
      (libsource (lib "eagle-import") (part "SMD-RES-2.2K-5%-1/8W(0805)"))
    )
    (comp (ref "R639")
      (value "(101)")
      (footprint "eagle-import:R0805")
      (fields (field (name "MPN") "RC0805JR-072K2L"))
      (libsource (lib "eagle-import") (part "SMD-RES-2.2K-5%-1/8W(0805)"))
    )
    (comp (ref "R640")
      (value "2702")
      (footprint "eagle-import:R0805")
      (fields (field (name "MPN") "RC0805FR-0710KL"))
      (libsource (lib "eagle-import") (part "SMD-RES-10K-1%-1/8W(0805)"))
    )
    (comp (ref "R641")
      (value "104")
      (footprint "eagle-import:R0805")
      (fields (field (name "MPN") "RC0805FR-0710KL"))
      (libsource (lib "eagle-import") (part "SMD-RES-10K-1%-1/8W(0805)"))
    )
    (comp (ref "R642")
      (value "(1000)")
      (footprint "eagle-import:R0805")
      (fields (field (name "MPN") "RC0805JR-07100RL"))
      (libsource (lib "eagle-import") (part "SMD-RES-100R-5%-1/8W(0805)"))
    )
    (comp (ref "R643")
      (value "(101)")
      (footprint "eagle-import:R0805")
      (fields (field (name "MPN") "RC0805JR-07100RL"))
      (libsource (lib "eagle-import") (part "SMD-RES-100R-5%-1/8W(0805)"))
    )
    (comp (ref "R644")
      (value "(1002)")
      (footprint "eagle-import:R0805")
      (fields (field (name "MPN") "RC0805FR-0710KL"))
      (libsource (lib "eagle-import") (part "SMD-RES-10K-1%-1/8W(0805)"))
    )
    (comp (ref "R645")
      (value "2702")
      (footprint "eagle-import:R0805")
      (fields (field (name "MPN") "RC0805JR-074K7L"))
      (libsource (lib "eagle-import") (part "SMD-RES-4.7K-5%-1/8W(0805)"))
    )
    (comp (ref "R646")
      (value "(1002)")
      (footprint "eagle-import:R0805")
      (fields (field (name "MPN") "RC0805JR-074K7L"))
      (libsource (lib "eagle-import") (part "SMD-RES-4.7K-5%-1/8W(0805)"))
    )
    (comp (ref "SJ601")
      (value "SJ")
      (footprint "eagle-import:SJ")
      (libsource (lib "eagle-import") (part "SJ"))
    )
    (comp (ref "START601")
      (value "TPSB2.0")
      (footprint "eagle-import:B2.0")
      (libsource (lib "eagle-import") (part "TPSB2.0"))
    )
    (comp (ref "TP185")
      (value "TPSB2.0")
      (footprint "eagle-import:B2.0")
      (libsource (lib "eagle-import") (part "TPSB2.0"))
    )
    (comp (ref "TP186")
      (value "TPSB2.0")
      (footprint "eagle-import:B2.0")
      (libsource (lib "eagle-import") (part "TPSB2.0"))
    )
    (comp (ref "TP187")
      (value "TPSB2.0")
      (footprint "eagle-import:B2.0")
      (libsource (lib "eagle-import") (part "TPSB2.0"))
    )
    (comp (ref "TP188")
      (value "TPSB2.0")
      (footprint "eagle-import:B2.0")
      (libsource (lib "eagle-import") (part "TPSB2.0"))
    )
    (comp (ref "TP189")
      (value "TPSB2.0")
      (footprint "eagle-import:B2.0")
      (libsource (lib "eagle-import") (part "TPSB2.0"))
    )
    (comp (ref "TP190")
      (value "TPSB2.0")
      (footprint "eagle-import:B2.0")
      (libsource (lib "eagle-import") (part "TPSB2.0"))
    )
    (comp (ref "TP191")
      (value "TPSB2.0")
      (footprint "eagle-import:B2.0")
      (libsource (lib "eagle-import") (part "TPSB2.0"))
    )
    (comp (ref "TP192")
      (value "TPSB2.0")
      (footprint "eagle-import:B2.0")
      (libsource (lib "eagle-import") (part "TPSB2.0"))
    )
    (comp (ref "TP193")
      (value "TPSB2.0")
      (footprint "eagle-import:B2.0")
      (libsource (lib "eagle-import") (part "TPSB2.0"))
    )
    (comp (ref "TP194")
      (value "TPSB2.0")
      (footprint "eagle-import:B2.0")
      (libsource (lib "eagle-import") (part "TPSB2.0"))
    )
    (comp (ref "TP195")
      (value "TPSB2.0")
      (footprint "eagle-import:B2.0")
      (libsource (lib "eagle-import") (part "TPSB2.0"))
    )
    (comp (ref "TP196")
      (value "TPSB2.0")
      (footprint "eagle-import:B2.0")
      (libsource (lib "eagle-import") (part "TPSB2.0"))
    )
    (comp (ref "TP197")
      (value "TPSB2.0")
      (footprint "eagle-import:B2.0")
      (libsource (lib "eagle-import") (part "TPSB2.0"))
    )
    (comp (ref "TP198")
      (value "TPSB2.0")
      (footprint "eagle-import:B2.0")
      (libsource (lib "eagle-import") (part "TPSB2.0"))
    )
    (comp (ref "TP199")
      (value "TPSB2.0")
      (footprint "eagle-import:B2.0")
      (libsource (lib "eagle-import") (part "TPSB2.0"))
    )
    (comp (ref "TP200")
      (value "TPSB2.0")
      (footprint "eagle-import:B2.0")
      (libsource (lib "eagle-import") (part "TPSB2.0"))
    )
    (comp (ref "TP201")
      (value "TPSB2.0")
      (footprint "eagle-import:B2.0")
      (libsource (lib "eagle-import") (part "TPSB2.0"))
    )
    (comp (ref "TP202")
      (value "TPSB2.0")
      (footprint "eagle-import:B2.0")
      (libsource (lib "eagle-import") (part "TPSB2.0"))
    )
    (comp (ref "TP203")
      (value "TPSB1,27")
      (footprint "eagle-import:B1,27")
      (libsource (lib "eagle-import") (part "TPSB1,27"))
    )
    (comp (ref "TP204")
      (value "TPSB2.0")
      (footprint "eagle-import:B2.0")
      (libsource (lib "eagle-import") (part "TPSB2.0"))
    )
    (comp (ref "TP205")
      (value "TPSB2.0")
      (footprint "eagle-import:B2.0")
      (libsource (lib "eagle-import") (part "TPSB2.0"))
    )
    (comp (ref "TP206")
      (value "TPSB2.0")
      (footprint "eagle-import:B2.0")
      (libsource (lib "eagle-import") (part "TPSB2.0"))
    )
    (comp (ref "TP207")
      (value "TPSB2.0")
      (footprint "eagle-import:B2.0")
      (libsource (lib "eagle-import") (part "TPSB2.0"))
    )
    (comp (ref "X601")
      (value "CON_BMWV2")
      (footprint "eagle-import:24-PIN_V2")
      (libsource (lib "eagle-import") (part "CON_BMWV2"))
    )
    (comp (ref "X602")
      (value "22-23-2021")
      (footprint "eagle-import:22-23-2021")
      (fields (field (name "MF") "MOLEX"))
      (libsource (lib "eagle-import") (part "22-23-2021"))
    )
    (comp (ref "X603")
      (value "22-23-2051")
      (footprint "eagle-import:22-23-2051")
      (fields (field (name "MF") "MOLEX"))
      (libsource (lib "eagle-import") (part "22-23-2051"))
    )
  )
  (nets
    (net (code "1") (name "+10V") (class "Default")
      (node (ref "10V") (pin "TP") (pinfunction "PP_TP") (pintype "input"))
      (node (ref "10V201") (pin "TP") (pinfunction "PP_TP") (pintype "input"))
      (node (ref "10V301") (pin "TP") (pinfunction "PP_TP") (pintype "input"))
      (node (ref "10V401") (pin "TP") (pinfunction "PP_TP") (pintype "input"))
      (node (ref "10V501") (pin "TP") (pinfunction "PP_TP") (pintype "input"))
      (node (ref "10V601") (pin "TP") (pinfunction "PP_TP") (pintype "input"))
      (node (ref "C102") (pin "1") (pinfunction "1_1") (pintype "passive"))
      (node (ref "C202") (pin "1") (pinfunction "1_1") (pintype "passive"))
      (node (ref "C302") (pin "1") (pinfunction "1_1") (pintype "passive"))
      (node (ref "C402") (pin "1") (pinfunction "1_1") (pintype "passive"))
      (node (ref "C502") (pin "1") (pinfunction "1_1") (pintype "passive"))
      (node (ref "C602") (pin "1") (pinfunction "1_1") (pintype "passive"))
      (node (ref "IC104") (pin "1") (pinfunction "OUT_1") (pintype "passive"))
      (node (ref "IC110") (pin "4") (pinfunction "R_4") (pintype "input"))
      (node (ref "IC110") (pin "8") (pinfunction "V+_8") (pintype "power_in"))
      (node (ref "IC111") (pin "13") (pinfunction "CD_13") (pintype "input"))
      (node (ref "IC111") (pin "16") (pinfunction "VDD_16") (pintype "power_in"))
      (node (ref "IC111") (pin "3") (pinfunction "CD_3") (pintype "input"))
      (node (ref "IC111") (pin "5") (pinfunction "B_5") (pintype "input"))
      (node (ref "IC204") (pin "1") (pinfunction "OUT_1") (pintype "passive"))
      (node (ref "IC210") (pin "4") (pinfunction "R_4") (pintype "input"))
      (node (ref "IC210") (pin "8") (pinfunction "V+_8") (pintype "power_in"))
      (node (ref "IC211") (pin "13") (pinfunction "CD_13") (pintype "input"))
      (node (ref "IC211") (pin "16") (pinfunction "VDD_16") (pintype "power_in"))
      (node (ref "IC211") (pin "3") (pinfunction "CD_3") (pintype "input"))
      (node (ref "IC211") (pin "5") (pinfunction "B_5") (pintype "input"))
      (node (ref "IC304") (pin "1") (pinfunction "OUT_1") (pintype "passive"))
      (node (ref "IC310") (pin "4") (pinfunction "R_4") (pintype "input"))
      (node (ref "IC310") (pin "8") (pinfunction "V+_8") (pintype "power_in"))
      (node (ref "IC311") (pin "13") (pinfunction "CD_13") (pintype "input"))
      (node (ref "IC311") (pin "16") (pinfunction "VDD_16") (pintype "power_in"))
      (node (ref "IC311") (pin "3") (pinfunction "CD_3") (pintype "input"))
      (node (ref "IC311") (pin "5") (pinfunction "B_5") (pintype "input"))
      (node (ref "IC404") (pin "1") (pinfunction "OUT_1") (pintype "passive"))
      (node (ref "IC410") (pin "4") (pinfunction "R_4") (pintype "input"))
      (node (ref "IC410") (pin "8") (pinfunction "V+_8") (pintype "power_in"))
      (node (ref "IC411") (pin "13") (pinfunction "CD_13") (pintype "input"))
      (node (ref "IC411") (pin "16") (pinfunction "VDD_16") (pintype "power_in"))
      (node (ref "IC411") (pin "3") (pinfunction "CD_3") (pintype "input"))
      (node (ref "IC411") (pin "5") (pinfunction "B_5") (pintype "input"))
      (node (ref "IC504") (pin "1") (pinfunction "OUT_1") (pintype "passive"))
      (node (ref "IC510") (pin "4") (pinfunction "R_4") (pintype "input"))
      (node (ref "IC510") (pin "8") (pinfunction "V+_8") (pintype "power_in"))
      (node (ref "IC511") (pin "13") (pinfunction "CD_13") (pintype "input"))
      (node (ref "IC511") (pin "16") (pinfunction "VDD_16") (pintype "power_in"))
      (node (ref "IC511") (pin "3") (pinfunction "CD_3") (pintype "input"))
      (node (ref "IC511") (pin "5") (pinfunction "B_5") (pintype "input"))
      (node (ref "IC604") (pin "1") (pinfunction "OUT_1") (pintype "passive"))
      (node (ref "IC610") (pin "4") (pinfunction "R_4") (pintype "input"))
      (node (ref "IC610") (pin "8") (pinfunction "V+_8") (pintype "power_in"))
      (node (ref "IC611") (pin "13") (pinfunction "CD_13") (pintype "input"))
      (node (ref "IC611") (pin "16") (pinfunction "VDD_16") (pintype "power_in"))
      (node (ref "IC611") (pin "3") (pinfunction "CD_3") (pintype "input"))
      (node (ref "IC611") (pin "5") (pinfunction "B_5") (pintype "input"))
      (node (ref "R145") (pin "2") (pinfunction "2_2") (pintype "passive"))
      (node (ref "R245") (pin "2") (pinfunction "2_2") (pintype "passive"))
      (node (ref "R345") (pin "2") (pinfunction "2_2") (pintype "passive"))
      (node (ref "R445") (pin "2") (pinfunction "2_2") (pintype "passive"))
      (node (ref "R545") (pin "2") (pinfunction "2_2") (pintype "passive"))
      (node (ref "R645") (pin "2") (pinfunction "2_2") (pintype "passive"))
    )
    (net (code "2") (name "+12V") (class "Default")
      (node (ref "14") (pin "1") (pinfunction "KL_1") (pintype "passive"))
      (node (ref "16") (pin "1") (pinfunction "KL_1") (pintype "passive"))
      (node (ref "18") (pin "1") (pinfunction "KL_1") (pintype "passive"))
      (node (ref "2") (pin "1") (pinfunction "KL_1") (pintype "passive"))
      (node (ref "4") (pin "1") (pinfunction "KL_1") (pintype "passive"))
      (node (ref "6") (pin "1") (pinfunction "KL_1") (pintype "passive"))
      (node (ref "D101") (pin "C") (pinfunction "C_C") (pintype "passive"))
      (node (ref "D201") (pin "C") (pinfunction "C_C") (pintype "passive"))
      (node (ref "D301") (pin "C") (pinfunction "C_C") (pintype "passive"))
      (node (ref "D401") (pin "C") (pinfunction "C_C") (pintype "passive"))
      (node (ref "D501") (pin "C") (pinfunction "C_C") (pintype "passive"))
      (node (ref "D601") (pin "C") (pinfunction "C_C") (pintype "passive"))
      (node (ref "IC102") (pin "3") (pinfunction "IN_3") (pintype "input"))
      (node (ref "IC103") (pin "IN") (pinfunction "IN_IN") (pintype "input"))
      (node (ref "IC104") (pin "3") (pinfunction "IN_3") (pintype "input"))
      (node (ref "IC105") (pin "16") (pinfunction "VDD_16") (pintype "power_in"))
      (node (ref "IC106") (pin "2") (pinfunction "V+_2") (pintype "passive"))
      (node (ref "IC107") (pin "9") (pinfunction "CD+_9") (pintype "passive"))
      (node (ref "IC202") (pin "3") (pinfunction "IN_3") (pintype "input"))
      (node (ref "IC203") (pin "IN") (pinfunction "IN_IN") (pintype "input"))
      (node (ref "IC204") (pin "3") (pinfunction "IN_3") (pintype "input"))
      (node (ref "IC205") (pin "16") (pinfunction "VDD_16") (pintype "power_in"))
      (node (ref "IC206") (pin "2") (pinfunction "V+_2") (pintype "passive"))
      (node (ref "IC207") (pin "9") (pinfunction "CD+_9") (pintype "passive"))
      (node (ref "IC302") (pin "3") (pinfunction "IN_3") (pintype "input"))
      (node (ref "IC303") (pin "IN") (pinfunction "IN_IN") (pintype "input"))
      (node (ref "IC304") (pin "3") (pinfunction "IN_3") (pintype "input"))
      (node (ref "IC305") (pin "16") (pinfunction "VDD_16") (pintype "power_in"))
      (node (ref "IC306") (pin "2") (pinfunction "V+_2") (pintype "passive"))
      (node (ref "IC307") (pin "9") (pinfunction "CD+_9") (pintype "passive"))
      (node (ref "IC402") (pin "3") (pinfunction "IN_3") (pintype "input"))
      (node (ref "IC403") (pin "IN") (pinfunction "IN_IN") (pintype "input"))
      (node (ref "IC404") (pin "3") (pinfunction "IN_3") (pintype "input"))
      (node (ref "IC405") (pin "16") (pinfunction "VDD_16") (pintype "power_in"))
      (node (ref "IC406") (pin "2") (pinfunction "V+_2") (pintype "passive"))
      (node (ref "IC407") (pin "9") (pinfunction "CD+_9") (pintype "passive"))
      (node (ref "IC502") (pin "3") (pinfunction "IN_3") (pintype "input"))
      (node (ref "IC503") (pin "IN") (pinfunction "IN_IN") (pintype "input"))
      (node (ref "IC504") (pin "3") (pinfunction "IN_3") (pintype "input"))
      (node (ref "IC505") (pin "16") (pinfunction "VDD_16") (pintype "power_in"))
      (node (ref "IC506") (pin "2") (pinfunction "V+_2") (pintype "passive"))
      (node (ref "IC507") (pin "9") (pinfunction "CD+_9") (pintype "passive"))
      (node (ref "IC602") (pin "3") (pinfunction "IN_3") (pintype "input"))
      (node (ref "IC603") (pin "IN") (pinfunction "IN_IN") (pintype "input"))
      (node (ref "IC604") (pin "3") (pinfunction "IN_3") (pintype "input"))
      (node (ref "IC605") (pin "16") (pinfunction "VDD_16") (pintype "power_in"))
      (node (ref "IC606") (pin "2") (pinfunction "V+_2") (pintype "passive"))
      (node (ref "IC607") (pin "9") (pinfunction "CD+_9") (pintype "passive"))
      (node (ref "JP101") (pin "2") (pinfunction "2_2") (pintype "passive"))
      (node (ref "JP201") (pin "2") (pinfunction "2_2") (pintype "passive"))
      (node (ref "JP301") (pin "2") (pinfunction "2_2") (pintype "passive"))
      (node (ref "JP401") (pin "2") (pinfunction "2_2") (pintype "passive"))
      (node (ref "JP501") (pin "2") (pinfunction "2_2") (pintype "passive"))
      (node (ref "JP601") (pin "2") (pinfunction "2_2") (pintype "passive"))
      (node (ref "Q104") (pin "3") (pinfunction "E_3") (pintype "passive"))
      (node (ref "Q105") (pin "3") (pinfunction "E_3") (pintype "passive"))
      (node (ref "Q204") (pin "3") (pinfunction "E_3") (pintype "passive"))
      (node (ref "Q205") (pin "3") (pinfunction "E_3") (pintype "passive"))
      (node (ref "Q304") (pin "3") (pinfunction "E_3") (pintype "passive"))
      (node (ref "Q305") (pin "3") (pinfunction "E_3") (pintype "passive"))
      (node (ref "Q404") (pin "3") (pinfunction "E_3") (pintype "passive"))
      (node (ref "Q405") (pin "3") (pinfunction "E_3") (pintype "passive"))
      (node (ref "Q504") (pin "3") (pinfunction "E_3") (pintype "passive"))
      (node (ref "Q505") (pin "3") (pinfunction "E_3") (pintype "passive"))
      (node (ref "Q604") (pin "3") (pinfunction "E_3") (pintype "passive"))
      (node (ref "Q605") (pin "3") (pinfunction "E_3") (pintype "passive"))
      (node (ref "R102") (pin "1") (pinfunction "1_1") (pintype "passive"))
      (node (ref "R106") (pin "1") (pinfunction "1_1") (pintype "passive"))
      (node (ref "R109") (pin "2") (pinfunction "2_2") (pintype "passive"))
      (node (ref "R110") (pin "2") (pinfunction "2_2") (pintype "passive"))
      (node (ref "R111") (pin "2") (pinfunction "2_2") (pintype "passive"))
      (node (ref "R129") (pin "2") (pinfunction "2_2") (pintype "passive"))
      (node (ref "R135") (pin "1") (pinfunction "1_1") (pintype "passive"))
      (node (ref "R202") (pin "1") (pinfunction "1_1") (pintype "passive"))
      (node (ref "R206") (pin "1") (pinfunction "1_1") (pintype "passive"))
      (node (ref "R209") (pin "2") (pinfunction "2_2") (pintype "passive"))
      (node (ref "R210") (pin "2") (pinfunction "2_2") (pintype "passive"))
      (node (ref "R211") (pin "2") (pinfunction "2_2") (pintype "passive"))
      (node (ref "R229") (pin "2") (pinfunction "2_2") (pintype "passive"))
      (node (ref "R235") (pin "1") (pinfunction "1_1") (pintype "passive"))
      (node (ref "R302") (pin "1") (pinfunction "1_1") (pintype "passive"))
      (node (ref "R306") (pin "1") (pinfunction "1_1") (pintype "passive"))
      (node (ref "R309") (pin "2") (pinfunction "2_2") (pintype "passive"))
      (node (ref "R310") (pin "2") (pinfunction "2_2") (pintype "passive"))
      (node (ref "R311") (pin "2") (pinfunction "2_2") (pintype "passive"))
      (node (ref "R329") (pin "2") (pinfunction "2_2") (pintype "passive"))
      (node (ref "R335") (pin "1") (pinfunction "1_1") (pintype "passive"))
      (node (ref "R402") (pin "1") (pinfunction "1_1") (pintype "passive"))
      (node (ref "R406") (pin "1") (pinfunction "1_1") (pintype "passive"))
      (node (ref "R409") (pin "2") (pinfunction "2_2") (pintype "passive"))
      (node (ref "R410") (pin "2") (pinfunction "2_2") (pintype "passive"))
      (node (ref "R411") (pin "2") (pinfunction "2_2") (pintype "passive"))
      (node (ref "R429") (pin "2") (pinfunction "2_2") (pintype "passive"))
      (node (ref "R435") (pin "1") (pinfunction "1_1") (pintype "passive"))
      (node (ref "R502") (pin "1") (pinfunction "1_1") (pintype "passive"))
      (node (ref "R506") (pin "1") (pinfunction "1_1") (pintype "passive"))
      (node (ref "R509") (pin "2") (pinfunction "2_2") (pintype "passive"))
      (node (ref "R510") (pin "2") (pinfunction "2_2") (pintype "passive"))
      (node (ref "R511") (pin "2") (pinfunction "2_2") (pintype "passive"))
      (node (ref "R529") (pin "2") (pinfunction "2_2") (pintype "passive"))
      (node (ref "R535") (pin "1") (pinfunction "1_1") (pintype "passive"))
      (node (ref "R602") (pin "1") (pinfunction "1_1") (pintype "passive"))
      (node (ref "R606") (pin "1") (pinfunction "1_1") (pintype "passive"))
      (node (ref "R609") (pin "2") (pinfunction "2_2") (pintype "passive"))
      (node (ref "R610") (pin "2") (pinfunction "2_2") (pintype "passive"))
      (node (ref "R611") (pin "2") (pinfunction "2_2") (pintype "passive"))
      (node (ref "R629") (pin "2") (pinfunction "2_2") (pintype "passive"))
      (node (ref "R635") (pin "1") (pinfunction "1_1") (pintype "passive"))
      (node (ref "TP12") (pin "TP") (pinfunction "PP_TP") (pintype "input"))
      (node (ref "TP160") (pin "TP") (pinfunction "PP_TP") (pintype "input"))
      (node (ref "TP183") (pin "TP") (pinfunction "PP_TP") (pintype "input"))
      (node (ref "TP206") (pin "TP") (pinfunction "PP_TP") (pintype "input"))
      (node (ref "TP45") (pin "TP") (pinfunction "PP_TP") (pintype "input"))
      (node (ref "TP68") (pin "TP") (pinfunction "PP_TP") (pintype "input"))
      (node (ref "X101") (pin "6") (pinfunction "6_6") (pintype "passive"))
      (node (ref "X103") (pin "1") (pinfunction "S_1") (pintype "passive"))
      (node (ref "X201") (pin "6") (pinfunction "6_6") (pintype "passive"))
      (node (ref "X203") (pin "1") (pinfunction "S_1") (pintype "passive"))
      (node (ref "X301") (pin "6") (pinfunction "6_6") (pintype "passive"))
      (node (ref "X303") (pin "1") (pinfunction "S_1") (pintype "passive"))
      (node (ref "X401") (pin "6") (pinfunction "6_6") (pintype "passive"))
      (node (ref "X403") (pin "1") (pinfunction "S_1") (pintype "passive"))
      (node (ref "X501") (pin "6") (pinfunction "6_6") (pintype "passive"))
      (node (ref "X503") (pin "1") (pinfunction "S_1") (pintype "passive"))
      (node (ref "X601") (pin "6") (pinfunction "6_6") (pintype "passive"))
      (node (ref "X603") (pin "1") (pinfunction "S_1") (pintype "passive"))
    )
    (net (code "3") (name "GND") (class "Default")
      (node (ref "1") (pin "12") (pinfunction "KL_12") (pintype "passive"))
      (node (ref "13") (pin "12") (pinfunction "KL_12") (pintype "passive"))
      (node (ref "15") (pin "12") (pinfunction "KL_12") (pintype "passive"))
      (node (ref "17") (pin "12") (pinfunction "KL_12") (pintype "passive"))
      (node (ref "3") (pin "12") (pinfunction "KL_12") (pintype "passive"))
      (node (ref "5") (pin "12") (pinfunction "KL_12") (pintype "passive"))
      (node (ref "C101") (pin "2") (pinfunction "2_2") (pintype "passive"))
      (node (ref "C102") (pin "2") (pinfunction "2_2") (pintype "passive"))
      (node (ref "C103") (pin "2") (pinfunction "2_2") (pintype "passive"))
      (node (ref "C104") (pin "2") (pinfunction "2_2") (pintype "passive"))
      (node (ref "C105") (pin "2") (pinfunction "2_2") (pintype "passive"))
      (node (ref "C106") (pin "1") (pinfunction "1_1") (pintype "passive"))
      (node (ref "C107") (pin "2") (pinfunction "2_2") (pintype "passive"))
      (node (ref "C108") (pin "2") (pinfunction "2_2") (pintype "passive"))
      (node (ref "C109") (pin "1") (pinfunction "1_1") (pintype "passive"))
      (node (ref "C110") (pin "2") (pinfunction "2_2") (pintype "passive"))
      (node (ref "C201") (pin "2") (pinfunction "2_2") (pintype "passive"))
      (node (ref "C202") (pin "2") (pinfunction "2_2") (pintype "passive"))
      (node (ref "C203") (pin "2") (pinfunction "2_2") (pintype "passive"))
      (node (ref "C204") (pin "2") (pinfunction "2_2") (pintype "passive"))
      (node (ref "C205") (pin "2") (pinfunction "2_2") (pintype "passive"))
      (node (ref "C206") (pin "1") (pinfunction "1_1") (pintype "passive"))
      (node (ref "C207") (pin "2") (pinfunction "2_2") (pintype "passive"))
      (node (ref "C208") (pin "2") (pinfunction "2_2") (pintype "passive"))
      (node (ref "C209") (pin "1") (pinfunction "1_1") (pintype "passive"))
      (node (ref "C210") (pin "2") (pinfunction "2_2") (pintype "passive"))
      (node (ref "C301") (pin "2") (pinfunction "2_2") (pintype "passive"))
      (node (ref "C302") (pin "2") (pinfunction "2_2") (pintype "passive"))
      (node (ref "C303") (pin "2") (pinfunction "2_2") (pintype "passive"))
      (node (ref "C304") (pin "2") (pinfunction "2_2") (pintype "passive"))
      (node (ref "C305") (pin "2") (pinfunction "2_2") (pintype "passive"))
      (node (ref "C306") (pin "1") (pinfunction "1_1") (pintype "passive"))
      (node (ref "C307") (pin "2") (pinfunction "2_2") (pintype "passive"))
      (node (ref "C308") (pin "2") (pinfunction "2_2") (pintype "passive"))
      (node (ref "C309") (pin "1") (pinfunction "1_1") (pintype "passive"))
      (node (ref "C310") (pin "2") (pinfunction "2_2") (pintype "passive"))
      (node (ref "C401") (pin "2") (pinfunction "2_2") (pintype "passive"))
      (node (ref "C402") (pin "2") (pinfunction "2_2") (pintype "passive"))
      (node (ref "C403") (pin "2") (pinfunction "2_2") (pintype "passive"))
      (node (ref "C404") (pin "2") (pinfunction "2_2") (pintype "passive"))
      (node (ref "C405") (pin "2") (pinfunction "2_2") (pintype "passive"))
      (node (ref "C406") (pin "1") (pinfunction "1_1") (pintype "passive"))
      (node (ref "C407") (pin "2") (pinfunction "2_2") (pintype "passive"))
      (node (ref "C408") (pin "2") (pinfunction "2_2") (pintype "passive"))
      (node (ref "C409") (pin "1") (pinfunction "1_1") (pintype "passive"))
      (node (ref "C410") (pin "2") (pinfunction "2_2") (pintype "passive"))
      (node (ref "C501") (pin "2") (pinfunction "2_2") (pintype "passive"))
      (node (ref "C502") (pin "2") (pinfunction "2_2") (pintype "passive"))
      (node (ref "C503") (pin "2") (pinfunction "2_2") (pintype "passive"))
      (node (ref "C504") (pin "2") (pinfunction "2_2") (pintype "passive"))
      (node (ref "C505") (pin "2") (pinfunction "2_2") (pintype "passive"))
      (node (ref "C506") (pin "1") (pinfunction "1_1") (pintype "passive"))
      (node (ref "C507") (pin "2") (pinfunction "2_2") (pintype "passive"))
      (node (ref "C508") (pin "2") (pinfunction "2_2") (pintype "passive"))
      (node (ref "C509") (pin "1") (pinfunction "1_1") (pintype "passive"))
      (node (ref "C510") (pin "2") (pinfunction "2_2") (pintype "passive"))
      (node (ref "C601") (pin "2") (pinfunction "2_2") (pintype "passive"))
      (node (ref "C602") (pin "2") (pinfunction "2_2") (pintype "passive"))
      (node (ref "C603") (pin "2") (pinfunction "2_2") (pintype "passive"))
      (node (ref "C604") (pin "2") (pinfunction "2_2") (pintype "passive"))
      (node (ref "C605") (pin "2") (pinfunction "2_2") (pintype "passive"))
      (node (ref "C606") (pin "1") (pinfunction "1_1") (pintype "passive"))
      (node (ref "C607") (pin "2") (pinfunction "2_2") (pintype "passive"))
      (node (ref "C608") (pin "2") (pinfunction "2_2") (pintype "passive"))
      (node (ref "C609") (pin "1") (pinfunction "1_1") (pintype "passive"))
      (node (ref "C610") (pin "2") (pinfunction "2_2") (pintype "passive"))
      (node (ref "D101") (pin "A") (pinfunction "A_A") (pintype "passive"))
      (node (ref "D104") (pin "A") (pinfunction "A_A") (pintype "passive"))
      (node (ref "D105") (pin "1") (pinfunction "+_1") (pintype "passive"))
      (node (ref "D201") (pin "A") (pinfunction "A_A") (pintype "passive"))
      (node (ref "D204") (pin "A") (pinfunction "A_A") (pintype "passive"))
      (node (ref "D205") (pin "1") (pinfunction "+_1") (pintype "passive"))
      (node (ref "D301") (pin "A") (pinfunction "A_A") (pintype "passive"))
      (node (ref "D304") (pin "A") (pinfunction "A_A") (pintype "passive"))
      (node (ref "D305") (pin "1") (pinfunction "+_1") (pintype "passive"))
      (node (ref "D401") (pin "A") (pinfunction "A_A") (pintype "passive"))
      (node (ref "D404") (pin "A") (pinfunction "A_A") (pintype "passive"))
      (node (ref "D405") (pin "1") (pinfunction "+_1") (pintype "passive"))
      (node (ref "D501") (pin "A") (pinfunction "A_A") (pintype "passive"))
      (node (ref "D504") (pin "A") (pinfunction "A_A") (pintype "passive"))
      (node (ref "D505") (pin "1") (pinfunction "+_1") (pintype "passive"))
      (node (ref "D601") (pin "A") (pinfunction "A_A") (pintype "passive"))
      (node (ref "D604") (pin "A") (pinfunction "A_A") (pintype "passive"))
      (node (ref "D605") (pin "1") (pinfunction "+_1") (pintype "passive"))
      (node (ref "IC101") (pin "4") (pinfunction "V-_4") (pintype "power_in"))
      (node (ref "IC102") (pin "2") (pinfunction "GND_2") (pintype "input"))
      (node (ref "IC102") (pin "2@1") (pinfunction "GND_2@1") (pintype "input"))
      (node (ref "IC103") (pin "GND") (pinfunction "GND_GND") (pintype "input"))
      (node (ref "IC104") (pin "2") (pinfunction "GND_2") (pintype "input"))
      (node (ref "IC104") (pin "2@1") (pinfunction "GND_2@1") (pintype "input"))
      (node (ref "IC105") (pin "11") (pinfunction "D_11") (pintype "input"))
      (node (ref "IC105") (pin "8") (pinfunction "VSS_8") (pintype "power_in"))
      (node (ref "IC106") (pin "5") (pinfunction "V-_5") (pintype "passive"))
      (node (ref "IC107") (pin "8") (pinfunction "GND_8") (pintype "power_in"))
      (node (ref "IC108") (pin "10") (pinfunction "-IN_10") (pintype "input"))
      (node (ref "IC108") (pin "11") (pinfunction "+IN_11") (pintype "input"))
      (node (ref "IC108") (pin "12") (pinfunction "GND_12") (pintype "power_in"))
      (node (ref "IC110") (pin "1") (pinfunction "GND_1") (pintype "power_in"))
      (node (ref "IC111") (pin "1") (pinfunction "T1_1") (pintype "input"))
      (node (ref "IC111") (pin "15") (pinfunction "T1_15") (pintype "input"))
      (node (ref "IC111") (pin "4") (pinfunction "A_4") (pintype "input"))
      (node (ref "IC111") (pin "8") (pinfunction "VSS_8") (pintype "power_in"))
      (node (ref "IC201") (pin "4") (pinfunction "V-_4") (pintype "power_in"))
      (node (ref "IC202") (pin "2") (pinfunction "GND_2") (pintype "input"))
      (node (ref "IC202") (pin "2@1") (pinfunction "GND_2@1") (pintype "input"))
      (node (ref "IC203") (pin "GND") (pinfunction "GND_GND") (pintype "input"))
      (node (ref "IC204") (pin "2") (pinfunction "GND_2") (pintype "input"))
      (node (ref "IC204") (pin "2@1") (pinfunction "GND_2@1") (pintype "input"))
      (node (ref "IC205") (pin "11") (pinfunction "D_11") (pintype "input"))
      (node (ref "IC205") (pin "8") (pinfunction "VSS_8") (pintype "power_in"))
      (node (ref "IC206") (pin "5") (pinfunction "V-_5") (pintype "passive"))
      (node (ref "IC207") (pin "8") (pinfunction "GND_8") (pintype "power_in"))
      (node (ref "IC208") (pin "10") (pinfunction "-IN_10") (pintype "input"))
      (node (ref "IC208") (pin "11") (pinfunction "+IN_11") (pintype "input"))
      (node (ref "IC208") (pin "12") (pinfunction "GND_12") (pintype "power_in"))
      (node (ref "IC210") (pin "1") (pinfunction "GND_1") (pintype "power_in"))
      (node (ref "IC211") (pin "1") (pinfunction "T1_1") (pintype "input"))
      (node (ref "IC211") (pin "15") (pinfunction "T1_15") (pintype "input"))
      (node (ref "IC211") (pin "4") (pinfunction "A_4") (pintype "input"))
      (node (ref "IC211") (pin "8") (pinfunction "VSS_8") (pintype "power_in"))
      (node (ref "IC301") (pin "4") (pinfunction "V-_4") (pintype "power_in"))
      (node (ref "IC302") (pin "2") (pinfunction "GND_2") (pintype "input"))
      (node (ref "IC302") (pin "2@1") (pinfunction "GND_2@1") (pintype "input"))
      (node (ref "IC303") (pin "GND") (pinfunction "GND_GND") (pintype "input"))
      (node (ref "IC304") (pin "2") (pinfunction "GND_2") (pintype "input"))
      (node (ref "IC304") (pin "2@1") (pinfunction "GND_2@1") (pintype "input"))
      (node (ref "IC305") (pin "11") (pinfunction "D_11") (pintype "input"))
      (node (ref "IC305") (pin "8") (pinfunction "VSS_8") (pintype "power_in"))
      (node (ref "IC306") (pin "5") (pinfunction "V-_5") (pintype "passive"))
      (node (ref "IC307") (pin "8") (pinfunction "GND_8") (pintype "power_in"))
      (node (ref "IC308") (pin "10") (pinfunction "-IN_10") (pintype "input"))
      (node (ref "IC308") (pin "11") (pinfunction "+IN_11") (pintype "input"))
      (node (ref "IC308") (pin "12") (pinfunction "GND_12") (pintype "power_in"))
      (node (ref "IC310") (pin "1") (pinfunction "GND_1") (pintype "power_in"))
      (node (ref "IC311") (pin "1") (pinfunction "T1_1") (pintype "input"))
      (node (ref "IC311") (pin "15") (pinfunction "T1_15") (pintype "input"))
      (node (ref "IC311") (pin "4") (pinfunction "A_4") (pintype "input"))
      (node (ref "IC311") (pin "8") (pinfunction "VSS_8") (pintype "power_in"))
      (node (ref "IC401") (pin "4") (pinfunction "V-_4") (pintype "power_in"))
      (node (ref "IC402") (pin "2") (pinfunction "GND_2") (pintype "input"))
      (node (ref "IC402") (pin "2@1") (pinfunction "GND_2@1") (pintype "input"))
      (node (ref "IC403") (pin "GND") (pinfunction "GND_GND") (pintype "input"))
      (node (ref "IC404") (pin "2") (pinfunction "GND_2") (pintype "input"))
      (node (ref "IC404") (pin "2@1") (pinfunction "GND_2@1") (pintype "input"))
      (node (ref "IC405") (pin "11") (pinfunction "D_11") (pintype "input"))
      (node (ref "IC405") (pin "8") (pinfunction "VSS_8") (pintype "power_in"))
      (node (ref "IC406") (pin "5") (pinfunction "V-_5") (pintype "passive"))
      (node (ref "IC407") (pin "8") (pinfunction "GND_8") (pintype "power_in"))
      (node (ref "IC408") (pin "10") (pinfunction "-IN_10") (pintype "input"))
      (node (ref "IC408") (pin "11") (pinfunction "+IN_11") (pintype "input"))
      (node (ref "IC408") (pin "12") (pinfunction "GND_12") (pintype "power_in"))
      (node (ref "IC410") (pin "1") (pinfunction "GND_1") (pintype "power_in"))
      (node (ref "IC411") (pin "1") (pinfunction "T1_1") (pintype "input"))
      (node (ref "IC411") (pin "15") (pinfunction "T1_15") (pintype "input"))
      (node (ref "IC411") (pin "4") (pinfunction "A_4") (pintype "input"))
      (node (ref "IC411") (pin "8") (pinfunction "VSS_8") (pintype "power_in"))
      (node (ref "IC501") (pin "4") (pinfunction "V-_4") (pintype "power_in"))
      (node (ref "IC502") (pin "2") (pinfunction "GND_2") (pintype "input"))
      (node (ref "IC502") (pin "2@1") (pinfunction "GND_2@1") (pintype "input"))
      (node (ref "IC503") (pin "GND") (pinfunction "GND_GND") (pintype "input"))
      (node (ref "IC504") (pin "2") (pinfunction "GND_2") (pintype "input"))
      (node (ref "IC504") (pin "2@1") (pinfunction "GND_2@1") (pintype "input"))
      (node (ref "IC505") (pin "11") (pinfunction "D_11") (pintype "input"))
      (node (ref "IC505") (pin "8") (pinfunction "VSS_8") (pintype "power_in"))
      (node (ref "IC506") (pin "5") (pinfunction "V-_5") (pintype "passive"))
      (node (ref "IC507") (pin "8") (pinfunction "GND_8") (pintype "power_in"))
      (node (ref "IC508") (pin "10") (pinfunction "-IN_10") (pintype "input"))
      (node (ref "IC508") (pin "11") (pinfunction "+IN_11") (pintype "input"))
      (node (ref "IC508") (pin "12") (pinfunction "GND_12") (pintype "power_in"))
      (node (ref "IC510") (pin "1") (pinfunction "GND_1") (pintype "power_in"))
      (node (ref "IC511") (pin "1") (pinfunction "T1_1") (pintype "input"))
      (node (ref "IC511") (pin "15") (pinfunction "T1_15") (pintype "input"))
      (node (ref "IC511") (pin "4") (pinfunction "A_4") (pintype "input"))
      (node (ref "IC511") (pin "8") (pinfunction "VSS_8") (pintype "power_in"))
      (node (ref "IC601") (pin "4") (pinfunction "V-_4") (pintype "power_in"))
      (node (ref "IC602") (pin "2") (pinfunction "GND_2") (pintype "input"))
      (node (ref "IC602") (pin "2@1") (pinfunction "GND_2@1") (pintype "input"))
      (node (ref "IC603") (pin "GND") (pinfunction "GND_GND") (pintype "input"))
      (node (ref "IC604") (pin "2") (pinfunction "GND_2") (pintype "input"))
      (node (ref "IC604") (pin "2@1") (pinfunction "GND_2@1") (pintype "input"))
      (node (ref "IC605") (pin "11") (pinfunction "D_11") (pintype "input"))
      (node (ref "IC605") (pin "8") (pinfunction "VSS_8") (pintype "power_in"))
      (node (ref "IC606") (pin "5") (pinfunction "V-_5") (pintype "passive"))
      (node (ref "IC607") (pin "8") (pinfunction "GND_8") (pintype "power_in"))
      (node (ref "IC608") (pin "10") (pinfunction "-IN_10") (pintype "input"))
      (node (ref "IC608") (pin "11") (pinfunction "+IN_11") (pintype "input"))
      (node (ref "IC608") (pin "12") (pinfunction "GND_12") (pintype "power_in"))
      (node (ref "IC610") (pin "1") (pinfunction "GND_1") (pintype "power_in"))
      (node (ref "IC611") (pin "1") (pinfunction "T1_1") (pintype "input"))
      (node (ref "IC611") (pin "15") (pinfunction "T1_15") (pintype "input"))
      (node (ref "IC611") (pin "4") (pinfunction "A_4") (pintype "input"))
      (node (ref "IC611") (pin "8") (pinfunction "VSS_8") (pintype "power_in"))
      (node (ref "Q103") (pin "3") (pinfunction "E_3") (pintype "passive"))
      (node (ref "Q106") (pin "2") (pinfunction "S_2") (pintype "passive"))
      (node (ref "Q107") (pin "2") (pinfunction "S_2") (pintype "passive"))
      (node (ref "Q203") (pin "3") (pinfunction "E_3") (pintype "passive"))
      (node (ref "Q206") (pin "2") (pinfunction "S_2") (pintype "passive"))
      (node (ref "Q207") (pin "2") (pinfunction "S_2") (pintype "passive"))
      (node (ref "Q303") (pin "3") (pinfunction "E_3") (pintype "passive"))
      (node (ref "Q306") (pin "2") (pinfunction "S_2") (pintype "passive"))
      (node (ref "Q307") (pin "2") (pinfunction "S_2") (pintype "passive"))
      (node (ref "Q403") (pin "3") (pinfunction "E_3") (pintype "passive"))
      (node (ref "Q406") (pin "2") (pinfunction "S_2") (pintype "passive"))
      (node (ref "Q407") (pin "2") (pinfunction "S_2") (pintype "passive"))
      (node (ref "Q503") (pin "3") (pinfunction "E_3") (pintype "passive"))
      (node (ref "Q506") (pin "2") (pinfunction "S_2") (pintype "passive"))
      (node (ref "Q507") (pin "2") (pinfunction "S_2") (pintype "passive"))
      (node (ref "Q603") (pin "3") (pinfunction "E_3") (pintype "passive"))
      (node (ref "Q606") (pin "2") (pinfunction "S_2") (pintype "passive"))
      (node (ref "Q607") (pin "2") (pinfunction "S_2") (pintype "passive"))
      (node (ref "R101") (pin "2") (pinfunction "2_2") (pintype "passive"))
      (node (ref "R103") (pin "2") (pinfunction "2_2") (pintype "passive"))
      (node (ref "R104") (pin "2") (pinfunction "2_2") (pintype "passive"))
      (node (ref "R107") (pin "1") (pinfunction "1_1") (pintype "passive"))
      (node (ref "R114") (pin "1") (pinfunction "1_1") (pintype "passive"))
      (node (ref "R123") (pin "1") (pinfunction "1_1") (pintype "passive"))
      (node (ref "R132") (pin "1") (pinfunction "1_1") (pintype "passive"))
      (node (ref "R136") (pin "1") (pinfunction "1_1") (pintype "passive"))
      (node (ref "R137") (pin "1") (pinfunction "1_1") (pintype "passive"))
      (node (ref "R139") (pin "2") (pinfunction "2_2") (pintype "passive"))
      (node (ref "R141") (pin "2") (pinfunction "2_2") (pintype "passive"))
      (node (ref "R143") (pin "2") (pinfunction "2_2") (pintype "passive"))
      (node (ref "R201") (pin "2") (pinfunction "2_2") (pintype "passive"))
      (node (ref "R203") (pin "2") (pinfunction "2_2") (pintype "passive"))
      (node (ref "R204") (pin "2") (pinfunction "2_2") (pintype "passive"))
      (node (ref "R207") (pin "1") (pinfunction "1_1") (pintype "passive"))
      (node (ref "R214") (pin "1") (pinfunction "1_1") (pintype "passive"))
      (node (ref "R223") (pin "1") (pinfunction "1_1") (pintype "passive"))
      (node (ref "R232") (pin "1") (pinfunction "1_1") (pintype "passive"))
      (node (ref "R236") (pin "1") (pinfunction "1_1") (pintype "passive"))
      (node (ref "R237") (pin "1") (pinfunction "1_1") (pintype "passive"))
      (node (ref "R239") (pin "2") (pinfunction "2_2") (pintype "passive"))
      (node (ref "R241") (pin "2") (pinfunction "2_2") (pintype "passive"))
      (node (ref "R243") (pin "2") (pinfunction "2_2") (pintype "passive"))
      (node (ref "R301") (pin "2") (pinfunction "2_2") (pintype "passive"))
      (node (ref "R303") (pin "2") (pinfunction "2_2") (pintype "passive"))
      (node (ref "R304") (pin "2") (pinfunction "2_2") (pintype "passive"))
      (node (ref "R307") (pin "1") (pinfunction "1_1") (pintype "passive"))
      (node (ref "R314") (pin "1") (pinfunction "1_1") (pintype "passive"))
      (node (ref "R323") (pin "1") (pinfunction "1_1") (pintype "passive"))
      (node (ref "R332") (pin "1") (pinfunction "1_1") (pintype "passive"))
      (node (ref "R336") (pin "1") (pinfunction "1_1") (pintype "passive"))
      (node (ref "R337") (pin "1") (pinfunction "1_1") (pintype "passive"))
      (node (ref "R339") (pin "2") (pinfunction "2_2") (pintype "passive"))
      (node (ref "R341") (pin "2") (pinfunction "2_2") (pintype "passive"))
      (node (ref "R343") (pin "2") (pinfunction "2_2") (pintype "passive"))
      (node (ref "R401") (pin "2") (pinfunction "2_2") (pintype "passive"))
      (node (ref "R403") (pin "2") (pinfunction "2_2") (pintype "passive"))
      (node (ref "R404") (pin "2") (pinfunction "2_2") (pintype "passive"))
      (node (ref "R407") (pin "1") (pinfunction "1_1") (pintype "passive"))
      (node (ref "R414") (pin "1") (pinfunction "1_1") (pintype "passive"))
      (node (ref "R423") (pin "1") (pinfunction "1_1") (pintype "passive"))
      (node (ref "R432") (pin "1") (pinfunction "1_1") (pintype "passive"))
      (node (ref "R436") (pin "1") (pinfunction "1_1") (pintype "passive"))
      (node (ref "R437") (pin "1") (pinfunction "1_1") (pintype "passive"))
      (node (ref "R439") (pin "2") (pinfunction "2_2") (pintype "passive"))
      (node (ref "R441") (pin "2") (pinfunction "2_2") (pintype "passive"))
      (node (ref "R443") (pin "2") (pinfunction "2_2") (pintype "passive"))
      (node (ref "R501") (pin "2") (pinfunction "2_2") (pintype "passive"))
      (node (ref "R503") (pin "2") (pinfunction "2_2") (pintype "passive"))
      (node (ref "R504") (pin "2") (pinfunction "2_2") (pintype "passive"))
      (node (ref "R507") (pin "1") (pinfunction "1_1") (pintype "passive"))
      (node (ref "R514") (pin "1") (pinfunction "1_1") (pintype "passive"))
      (node (ref "R523") (pin "1") (pinfunction "1_1") (pintype "passive"))
      (node (ref "R532") (pin "1") (pinfunction "1_1") (pintype "passive"))
      (node (ref "R536") (pin "1") (pinfunction "1_1") (pintype "passive"))
      (node (ref "R537") (pin "1") (pinfunction "1_1") (pintype "passive"))
      (node (ref "R539") (pin "2") (pinfunction "2_2") (pintype "passive"))
      (node (ref "R541") (pin "2") (pinfunction "2_2") (pintype "passive"))
      (node (ref "R543") (pin "2") (pinfunction "2_2") (pintype "passive"))
      (node (ref "R601") (pin "2") (pinfunction "2_2") (pintype "passive"))
      (node (ref "R603") (pin "2") (pinfunction "2_2") (pintype "passive"))
      (node (ref "R604") (pin "2") (pinfunction "2_2") (pintype "passive"))
      (node (ref "R607") (pin "1") (pinfunction "1_1") (pintype "passive"))
      (node (ref "R614") (pin "1") (pinfunction "1_1") (pintype "passive"))
      (node (ref "R623") (pin "1") (pinfunction "1_1") (pintype "passive"))
      (node (ref "R632") (pin "1") (pinfunction "1_1") (pintype "passive"))
      (node (ref "R636") (pin "1") (pinfunction "1_1") (pintype "passive"))
      (node (ref "R637") (pin "1") (pinfunction "1_1") (pintype "passive"))
      (node (ref "R639") (pin "2") (pinfunction "2_2") (pintype "passive"))
      (node (ref "R641") (pin "2") (pinfunction "2_2") (pintype "passive"))
      (node (ref "R643") (pin "2") (pinfunction "2_2") (pintype "passive"))
      (node (ref "X101") (pin "13") (pinfunction "13_13") (pintype "passive"))
      (node (ref "X101") (pin "18") (pinfunction "18_18") (pintype "passive"))
      (node (ref "X101") (pin "23") (pinfunction "23_23") (pintype "passive"))
      (node (ref "X102") (pin "1") (pinfunction "S_1") (pintype "passive"))
      (node (ref "X103") (pin "5") (pinfunction "S_5") (pintype "passive"))
      (node (ref "X201") (pin "13") (pinfunction "13_13") (pintype "passive"))
      (node (ref "X201") (pin "18") (pinfunction "18_18") (pintype "passive"))
      (node (ref "X201") (pin "23") (pinfunction "23_23") (pintype "passive"))
      (node (ref "X202") (pin "1") (pinfunction "S_1") (pintype "passive"))
      (node (ref "X203") (pin "5") (pinfunction "S_5") (pintype "passive"))
      (node (ref "X301") (pin "13") (pinfunction "13_13") (pintype "passive"))
      (node (ref "X301") (pin "18") (pinfunction "18_18") (pintype "passive"))
      (node (ref "X301") (pin "23") (pinfunction "23_23") (pintype "passive"))
      (node (ref "X302") (pin "1") (pinfunction "S_1") (pintype "passive"))
      (node (ref "X303") (pin "5") (pinfunction "S_5") (pintype "passive"))
      (node (ref "X401") (pin "13") (pinfunction "13_13") (pintype "passive"))
      (node (ref "X401") (pin "18") (pinfunction "18_18") (pintype "passive"))
      (node (ref "X401") (pin "23") (pinfunction "23_23") (pintype "passive"))
      (node (ref "X402") (pin "1") (pinfunction "S_1") (pintype "passive"))
      (node (ref "X403") (pin "5") (pinfunction "S_5") (pintype "passive"))
      (node (ref "X501") (pin "13") (pinfunction "13_13") (pintype "passive"))
      (node (ref "X501") (pin "18") (pinfunction "18_18") (pintype "passive"))
      (node (ref "X501") (pin "23") (pinfunction "23_23") (pintype "passive"))
      (node (ref "X502") (pin "1") (pinfunction "S_1") (pintype "passive"))
      (node (ref "X503") (pin "5") (pinfunction "S_5") (pintype "passive"))
      (node (ref "X601") (pin "13") (pinfunction "13_13") (pintype "passive"))
      (node (ref "X601") (pin "18") (pinfunction "18_18") (pintype "passive"))
      (node (ref "X601") (pin "23") (pinfunction "23_23") (pintype "passive"))
      (node (ref "X602") (pin "1") (pinfunction "S_1") (pintype "passive"))
      (node (ref "X603") (pin "5") (pinfunction "S_5") (pintype "passive"))
    )
    (net (code "4") (name "Net-(1A-KL)") (class "Default")
      (node (ref "1") (pin "1") (pinfunction "KL_1") (pintype "passive"))
      (node (ref "TP1") (pin "TP") (pinfunction "PP_TP") (pintype "input"))
      (node (ref "X101") (pin "1") (pinfunction "1_1") (pintype "passive"))
    )
    (net (code "5") (name "Net-(1B-KL)") (class "Default")
      (node (ref "1") (pin "10") (pinfunction "KL_10") (pintype "passive"))
      (node (ref "D102") (pin "2") (pinfunction "-_2") (pintype "passive"))
      (node (ref "D103") (pin "2") (pinfunction "-_2") (pintype "passive"))
      (node (ref "JP104") (pin "1") (pinfunction "1_1") (pintype "passive"))
      (node (ref "SJ101") (pin "1") (pinfunction "1_1") (pintype "passive"))
      (node (ref "TP10") (pin "TP") (pinfunction "PP_TP") (pintype "input"))
    )
    (net (code "6") (name "Net-(1C-KL)") (class "Default")
      (node (ref "1") (pin "11") (pinfunction "KL_11") (pintype "passive"))
      (node (ref "D103") (pin "1") (pinfunction "+_1") (pintype "passive"))
      (node (ref "TP11") (pin "TP") (pinfunction "PP_TP") (pintype "input"))
      (node (ref "X101") (pin "19") (pinfunction "19_19") (pintype "passive"))
    )
    (net (code "7") (name "Net-(1E-KL)") (class "Default")
      (node (ref "1") (pin "2") (pinfunction "KL_2") (pintype "passive"))
      (node (ref "Q101") (pin "2") (pinfunction "C_2") (pintype "passive"))
      (node (ref "TP2") (pin "TP") (pinfunction "PP_TP") (pintype "input"))
    )
    (net (code "8") (name "Net-(1F-KL)") (class "Default")
      (node (ref "1") (pin "3") (pinfunction "KL_3") (pintype "passive"))
      (node (ref "IC107") (pin "11") (pinfunction "O6_11") (pintype "open_collector"))
      (node (ref "TP3") (pin "TP") (pinfunction "PP_TP") (pintype "input"))
    )
    (net (code "9") (name "Net-(1G-KL)") (class "Default")
      (node (ref "1") (pin "4") (pinfunction "KL_4") (pintype "passive"))
      (node (ref "IC107") (pin "10") (pinfunction "O7_10") (pintype "open_collector"))
      (node (ref "TP4") (pin "TP") (pinfunction "PP_TP") (pintype "input"))
    )
    (net (code "10") (name "Net-(1H-KL)") (class "Default")
      (node (ref "1") (pin "5") (pinfunction "KL_5") (pintype "passive"))
      (node (ref "IC107") (pin "12") (pinfunction "O5_12") (pintype "open_collector"))
      (node (ref "TP5") (pin "TP") (pinfunction "PP_TP") (pintype "input"))
    )
    (net (code "11") (name "Net-(1I-KL)") (class "Default")
      (node (ref "1") (pin "6") (pinfunction "KL_6") (pintype "passive"))
      (node (ref "IC107") (pin "13") (pinfunction "O4_13") (pintype "open_collector"))
      (node (ref "TP6") (pin "TP") (pinfunction "PP_TP") (pintype "input"))
    )
    (net (code "12") (name "Net-(1J-KL)") (class "Default")
      (node (ref "1") (pin "7") (pinfunction "KL_7") (pintype "passive"))
      (node (ref "IC107") (pin "14") (pinfunction "O3_14") (pintype "open_collector"))
      (node (ref "TP7") (pin "TP") (pinfunction "PP_TP") (pintype "input"))
    )
    (net (code "13") (name "Net-(1K-KL)") (class "Default")
      (node (ref "1") (pin "8") (pinfunction "KL_8") (pintype "passive"))
      (node (ref "Q106") (pin "3") (pinfunction "D_3") (pintype "passive"))
      (node (ref "TP8") (pin "TP") (pinfunction "PP_TP") (pintype "input"))
    )
    (net (code "14") (name "Net-(1L-KL)") (class "Default")
      (node (ref "1") (pin "9") (pinfunction "KL_9") (pintype "passive"))
      (node (ref "D102") (pin "1") (pinfunction "+_1") (pintype "passive"))
      (node (ref "TP9") (pin "TP") (pinfunction "PP_TP") (pintype "input"))
      (node (ref "X101") (pin "17") (pinfunction "17_17") (pintype "passive"))
    )
    (net (code "15") (name "Net-(2B-KL)") (class "Default")
      (node (ref "2") (pin "10") (pinfunction "KL_10") (pintype "passive"))
      (node (ref "TP25") (pin "TP") (pinfunction "PP_TP") (pintype "input"))
      (node (ref "X101") (pin "15") (pinfunction "15_15") (pintype "passive"))
    )
    (net (code "16") (name "Net-(2C-KL)") (class "Default")
      (node (ref "2") (pin "11") (pinfunction "KL_11") (pintype "passive"))
      (node (ref "IC107") (pin "16") (pinfunction "O1_16") (pintype "open_collector"))
      (node (ref "R118") (pin "2") (pinfunction "2_2") (pintype "passive"))
      (node (ref "R119") (pin "1") (pinfunction "1_1") (pintype "passive"))
      (node (ref "TP26") (pin "TP") (pinfunction "PP_TP") (pintype "input"))
    )
    (net (code "17") (name "Net-(2D-KL)") (class "Default")
      (node (ref "2") (pin "12") (pinfunction "KL_12") (pintype "passive"))
      (node (ref "R146") (pin "1") (pinfunction "1_1") (pintype "passive"))
      (node (ref "TP13") (pin "TP") (pinfunction "PP_TP") (pintype "input"))
    )
    (net (code "18") (name "Net-(2E-KL)") (class "Default")
      (node (ref "2") (pin "2") (pinfunction "KL_2") (pintype "passive"))
      (node (ref "D109") (pin "2") (pinfunction "-_2") (pintype "passive"))
      (node (ref "LED102") (pin "K") (pinfunction "C_K") (pintype "passive"))
      (node (ref "TP16") (pin "TP") (pinfunction "PP_TP") (pintype "input"))
      (node (ref "X101") (pin "12") (pinfunction "12_12") (pintype "passive"))
    )
    (net (code "19") (name "Net-(2F-KL)") (class "Default")
      (node (ref "2") (pin "3") (pinfunction "KL_3") (pintype "passive"))
      (node (ref "D108") (pin "2") (pinfunction "-_2") (pintype "passive"))
      (node (ref "LED103") (pin "K") (pinfunction "C_K") (pintype "passive"))
      (node (ref "TP17") (pin "TP") (pinfunction "PP_TP") (pintype "input"))
      (node (ref "X101") (pin "11") (pinfunction "11_11") (pintype "passive"))
    )
    (net (code "20") (name "Net-(2G-KL)") (class "Default")
      (node (ref "2") (pin "4") (pinfunction "KL_4") (pintype "passive"))
      (node (ref "D107") (pin "2") (pinfunction "-_2") (pintype "passive"))
      (node (ref "LED104") (pin "K") (pinfunction "C_K") (pintype "passive"))
      (node (ref "TP18") (pin "TP") (pinfunction "PP_TP") (pintype "input"))
      (node (ref "X101") (pin "10") (pinfunction "10_10") (pintype "passive"))
    )
    (net (code "21") (name "Net-(2H-KL)") (class "Default")
      (node (ref "2") (pin "5") (pinfunction "KL_5") (pintype "passive"))
      (node (ref "D106") (pin "2") (pinfunction "-_2") (pintype "passive"))
      (node (ref "LED105") (pin "K") (pinfunction "C_K") (pintype "passive"))
      (node (ref "TP19") (pin "TP") (pinfunction "PP_TP") (pintype "input"))
      (node (ref "X101") (pin "9") (pinfunction "9_9") (pintype "passive"))
    )
    (net (code "22") (name "Net-(2I-KL)") (class "Default")
      (node (ref "2") (pin "6") (pinfunction "KL_6") (pintype "passive"))
      (node (ref "JP105") (pin "2") (pinfunction "2_2") (pintype "passive"))
      (node (ref "TP21") (pin "TP") (pinfunction "PP_TP") (pintype "input"))
    )
    (net (code "23") (name "Net-(2J-KL)") (class "Default")
      (node (ref "2") (pin "7") (pinfunction "KL_7") (pintype "passive"))
      (node (ref "LED101") (pin "A") (pinfunction "A_A") (pintype "passive"))
      (node (ref "TP22") (pin "TP") (pinfunction "PP_TP") (pintype "input"))
      (node (ref "X101") (pin "8") (pinfunction "8_8") (pintype "passive"))
    )
    (net (code "24") (name "Net-(2K-KL)") (class "Default")
      (node (ref "2") (pin "8") (pinfunction "KL_8") (pintype "passive"))
      (node (ref "D110") (pin "2") (pinfunction "-_2") (pintype "passive"))
      (node (ref "LED106") (pin "K") (pinfunction "C_K") (pintype "passive"))
      (node (ref "TP23") (pin "TP") (pinfunction "PP_TP") (pintype "input"))
      (node (ref "X101") (pin "14") (pinfunction "14_14") (pintype "passive"))
    )
    (net (code "25") (name "Net-(2L-KL)") (class "Default")
      (node (ref "2") (pin "9") (pinfunction "KL_9") (pintype "passive"))
      (node (ref "D107") (pin "1") (pinfunction "+_1") (pintype "passive"))
      (node (ref "D108") (pin "1") (pinfunction "+_1") (pintype "passive"))
      (node (ref "JP102") (pin "1") (pinfunction "1_1") (pintype "passive"))
      (node (ref "JP103") (pin "2") (pinfunction "2_2") (pintype "passive"))
      (node (ref "TP24") (pin "TP") (pinfunction "PP_TP") (pintype "input"))
    )
    (net (code "26") (name "Net-(3A-KL)") (class "Default")
      (node (ref "3") (pin "1") (pinfunction "KL_1") (pintype "passive"))
      (node (ref "TP14") (pin "TP") (pinfunction "PP_TP") (pintype "input"))
      (node (ref "X201") (pin "1") (pinfunction "1_1") (pintype "passive"))
    )
    (net (code "27") (name "Net-(3B-KL)") (class "Default")
      (node (ref "3") (pin "10") (pinfunction "KL_10") (pintype "passive"))
      (node (ref "D202") (pin "2") (pinfunction "-_2") (pintype "passive"))
      (node (ref "D203") (pin "2") (pinfunction "-_2") (pintype "passive"))
      (node (ref "JP204") (pin "1") (pinfunction "1_1") (pintype "passive"))
      (node (ref "SJ201") (pin "1") (pinfunction "1_1") (pintype "passive"))
      (node (ref "TP33") (pin "TP") (pinfunction "PP_TP") (pintype "input"))
    )
    (net (code "28") (name "Net-(3C-KL)") (class "Default")
      (node (ref "3") (pin "11") (pinfunction "KL_11") (pintype "passive"))
      (node (ref "D203") (pin "1") (pinfunction "+_1") (pintype "passive"))
      (node (ref "TP34") (pin "TP") (pinfunction "PP_TP") (pintype "input"))
      (node (ref "X201") (pin "19") (pinfunction "19_19") (pintype "passive"))
    )
    (net (code "29") (name "Net-(3E-KL)") (class "Default")
      (node (ref "3") (pin "2") (pinfunction "KL_2") (pintype "passive"))
      (node (ref "Q201") (pin "2") (pinfunction "C_2") (pintype "passive"))
      (node (ref "TP15") (pin "TP") (pinfunction "PP_TP") (pintype "input"))
    )
    (net (code "30") (name "Net-(3F-KL)") (class "Default")
      (node (ref "3") (pin "3") (pinfunction "KL_3") (pintype "passive"))
      (node (ref "IC207") (pin "11") (pinfunction "O6_11") (pintype "open_collector"))
      (node (ref "TP20") (pin "TP") (pinfunction "PP_TP") (pintype "input"))
    )
    (net (code "31") (name "Net-(3G-KL)") (class "Default")
      (node (ref "3") (pin "4") (pinfunction "KL_4") (pintype "passive"))
      (node (ref "IC207") (pin "10") (pinfunction "O7_10") (pintype "open_collector"))
      (node (ref "TP27") (pin "TP") (pinfunction "PP_TP") (pintype "input"))
    )
    (net (code "32") (name "Net-(3H-KL)") (class "Default")
      (node (ref "3") (pin "5") (pinfunction "KL_5") (pintype "passive"))
      (node (ref "IC207") (pin "12") (pinfunction "O5_12") (pintype "open_collector"))
      (node (ref "TP28") (pin "TP") (pinfunction "PP_TP") (pintype "input"))
    )
    (net (code "33") (name "Net-(3I-KL)") (class "Default")
      (node (ref "3") (pin "6") (pinfunction "KL_6") (pintype "passive"))
      (node (ref "IC207") (pin "13") (pinfunction "O4_13") (pintype "open_collector"))
      (node (ref "TP29") (pin "TP") (pinfunction "PP_TP") (pintype "input"))
    )
    (net (code "34") (name "Net-(3J-KL)") (class "Default")
      (node (ref "3") (pin "7") (pinfunction "KL_7") (pintype "passive"))
      (node (ref "IC207") (pin "14") (pinfunction "O3_14") (pintype "open_collector"))
      (node (ref "TP30") (pin "TP") (pinfunction "PP_TP") (pintype "input"))
    )
    (net (code "35") (name "Net-(3K-KL)") (class "Default")
      (node (ref "3") (pin "8") (pinfunction "KL_8") (pintype "passive"))
      (node (ref "Q206") (pin "3") (pinfunction "D_3") (pintype "passive"))
      (node (ref "TP31") (pin "TP") (pinfunction "PP_TP") (pintype "input"))
    )
    (net (code "36") (name "Net-(3L-KL)") (class "Default")
      (node (ref "3") (pin "9") (pinfunction "KL_9") (pintype "passive"))
      (node (ref "D202") (pin "1") (pinfunction "+_1") (pintype "passive"))
      (node (ref "TP32") (pin "TP") (pinfunction "PP_TP") (pintype "input"))
      (node (ref "X201") (pin "17") (pinfunction "17_17") (pintype "passive"))
    )
    (net (code "37") (name "Net-(4B-KL)") (class "Default")
      (node (ref "4") (pin "10") (pinfunction "KL_10") (pintype "passive"))
      (node (ref "TP43") (pin "TP") (pinfunction "PP_TP") (pintype "input"))
      (node (ref "X201") (pin "15") (pinfunction "15_15") (pintype "passive"))
    )
    (net (code "38") (name "Net-(4C-KL)") (class "Default")
      (node (ref "4") (pin "11") (pinfunction "KL_11") (pintype "passive"))
      (node (ref "IC207") (pin "16") (pinfunction "O1_16") (pintype "open_collector"))
      (node (ref "R218") (pin "2") (pinfunction "2_2") (pintype "passive"))
      (node (ref "R219") (pin "1") (pinfunction "1_1") (pintype "passive"))
      (node (ref "TP44") (pin "TP") (pinfunction "PP_TP") (pintype "input"))
    )
    (net (code "39") (name "Net-(4D-KL)") (class "Default")
      (node (ref "4") (pin "12") (pinfunction "KL_12") (pintype "passive"))
      (node (ref "R246") (pin "1") (pinfunction "1_1") (pintype "passive"))
      (node (ref "TP46") (pin "TP") (pinfunction "PP_TP") (pintype "input"))
    )
    (net (code "40") (name "Net-(4E-KL)") (class "Default")
      (node (ref "4") (pin "2") (pinfunction "KL_2") (pintype "passive"))
      (node (ref "D209") (pin "2") (pinfunction "-_2") (pintype "passive"))
      (node (ref "LED202") (pin "K") (pinfunction "C_K") (pintype "passive"))
      (node (ref "TP35") (pin "TP") (pinfunction "PP_TP") (pintype "input"))
      (node (ref "X201") (pin "12") (pinfunction "12_12") (pintype "passive"))
    )
    (net (code "41") (name "Net-(4F-KL)") (class "Default")
      (node (ref "4") (pin "3") (pinfunction "KL_3") (pintype "passive"))
      (node (ref "D208") (pin "2") (pinfunction "-_2") (pintype "passive"))
      (node (ref "LED203") (pin "K") (pinfunction "C_K") (pintype "passive"))
      (node (ref "TP36") (pin "TP") (pinfunction "PP_TP") (pintype "input"))
      (node (ref "X201") (pin "11") (pinfunction "11_11") (pintype "passive"))
    )
    (net (code "42") (name "Net-(4G-KL)") (class "Default")
      (node (ref "4") (pin "4") (pinfunction "KL_4") (pintype "passive"))
      (node (ref "D207") (pin "2") (pinfunction "-_2") (pintype "passive"))
      (node (ref "LED204") (pin "K") (pinfunction "C_K") (pintype "passive"))
      (node (ref "TP37") (pin "TP") (pinfunction "PP_TP") (pintype "input"))
      (node (ref "X201") (pin "10") (pinfunction "10_10") (pintype "passive"))
    )
    (net (code "43") (name "Net-(4H-KL)") (class "Default")
      (node (ref "4") (pin "5") (pinfunction "KL_5") (pintype "passive"))
      (node (ref "D206") (pin "2") (pinfunction "-_2") (pintype "passive"))
      (node (ref "LED205") (pin "K") (pinfunction "C_K") (pintype "passive"))
      (node (ref "TP38") (pin "TP") (pinfunction "PP_TP") (pintype "input"))
      (node (ref "X201") (pin "9") (pinfunction "9_9") (pintype "passive"))
    )
    (net (code "44") (name "Net-(4I-KL)") (class "Default")
      (node (ref "4") (pin "6") (pinfunction "KL_6") (pintype "passive"))
      (node (ref "JP205") (pin "2") (pinfunction "2_2") (pintype "passive"))
      (node (ref "TP39") (pin "TP") (pinfunction "PP_TP") (pintype "input"))
    )
    (net (code "45") (name "Net-(4J-KL)") (class "Default")
      (node (ref "4") (pin "7") (pinfunction "KL_7") (pintype "passive"))
      (node (ref "LED201") (pin "A") (pinfunction "A_A") (pintype "passive"))
      (node (ref "TP40") (pin "TP") (pinfunction "PP_TP") (pintype "input"))
      (node (ref "X201") (pin "8") (pinfunction "8_8") (pintype "passive"))
    )
    (net (code "46") (name "Net-(4K-KL)") (class "Default")
      (node (ref "4") (pin "8") (pinfunction "KL_8") (pintype "passive"))
      (node (ref "D210") (pin "2") (pinfunction "-_2") (pintype "passive"))
      (node (ref "LED206") (pin "K") (pinfunction "C_K") (pintype "passive"))
      (node (ref "TP41") (pin "TP") (pinfunction "PP_TP") (pintype "input"))
      (node (ref "X201") (pin "14") (pinfunction "14_14") (pintype "passive"))
    )
    (net (code "47") (name "Net-(4L-KL)") (class "Default")
      (node (ref "4") (pin "9") (pinfunction "KL_9") (pintype "passive"))
      (node (ref "D207") (pin "1") (pinfunction "+_1") (pintype "passive"))
      (node (ref "D208") (pin "1") (pinfunction "+_1") (pintype "passive"))
      (node (ref "JP202") (pin "1") (pinfunction "1_1") (pintype "passive"))
      (node (ref "JP203") (pin "2") (pinfunction "2_2") (pintype "passive"))
      (node (ref "TP42") (pin "TP") (pinfunction "PP_TP") (pintype "input"))
    )
    (net (code "48") (name "Net-(5A-KL)") (class "Default")
      (node (ref "5") (pin "1") (pinfunction "KL_1") (pintype "passive"))
      (node (ref "TP47") (pin "TP") (pinfunction "PP_TP") (pintype "input"))
      (node (ref "X301") (pin "1") (pinfunction "1_1") (pintype "passive"))
    )
    (net (code "49") (name "Net-(5B-KL)") (class "Default")
      (node (ref "5") (pin "10") (pinfunction "KL_10") (pintype "passive"))
      (node (ref "D302") (pin "2") (pinfunction "-_2") (pintype "passive"))
      (node (ref "D303") (pin "2") (pinfunction "-_2") (pintype "passive"))
      (node (ref "JP304") (pin "1") (pinfunction "1_1") (pintype "passive"))
      (node (ref "SJ301") (pin "1") (pinfunction "1_1") (pintype "passive"))
      (node (ref "TP56") (pin "TP") (pinfunction "PP_TP") (pintype "input"))
    )
    (net (code "50") (name "Net-(5C-KL)") (class "Default")
      (node (ref "5") (pin "11") (pinfunction "KL_11") (pintype "passive"))
      (node (ref "D303") (pin "1") (pinfunction "+_1") (pintype "passive"))
      (node (ref "TP57") (pin "TP") (pinfunction "PP_TP") (pintype "input"))
      (node (ref "X301") (pin "19") (pinfunction "19_19") (pintype "passive"))
    )
    (net (code "51") (name "Net-(5E-KL)") (class "Default")
      (node (ref "5") (pin "2") (pinfunction "KL_2") (pintype "passive"))
      (node (ref "Q301") (pin "2") (pinfunction "C_2") (pintype "passive"))
      (node (ref "TP48") (pin "TP") (pinfunction "PP_TP") (pintype "input"))
    )
    (net (code "52") (name "Net-(5F-KL)") (class "Default")
      (node (ref "5") (pin "3") (pinfunction "KL_3") (pintype "passive"))
      (node (ref "IC307") (pin "11") (pinfunction "O6_11") (pintype "open_collector"))
      (node (ref "TP49") (pin "TP") (pinfunction "PP_TP") (pintype "input"))
    )
    (net (code "53") (name "Net-(5G-KL)") (class "Default")
      (node (ref "5") (pin "4") (pinfunction "KL_4") (pintype "passive"))
      (node (ref "IC307") (pin "10") (pinfunction "O7_10") (pintype "open_collector"))
      (node (ref "TP50") (pin "TP") (pinfunction "PP_TP") (pintype "input"))
    )
    (net (code "54") (name "Net-(5H-KL)") (class "Default")
      (node (ref "5") (pin "5") (pinfunction "KL_5") (pintype "passive"))
      (node (ref "IC307") (pin "12") (pinfunction "O5_12") (pintype "open_collector"))
      (node (ref "TP51") (pin "TP") (pinfunction "PP_TP") (pintype "input"))
    )
    (net (code "55") (name "Net-(5I-KL)") (class "Default")
      (node (ref "5") (pin "6") (pinfunction "KL_6") (pintype "passive"))
      (node (ref "IC307") (pin "13") (pinfunction "O4_13") (pintype "open_collector"))
      (node (ref "TP52") (pin "TP") (pinfunction "PP_TP") (pintype "input"))
    )
    (net (code "56") (name "Net-(5J-KL)") (class "Default")
      (node (ref "5") (pin "7") (pinfunction "KL_7") (pintype "passive"))
      (node (ref "IC307") (pin "14") (pinfunction "O3_14") (pintype "open_collector"))
      (node (ref "TP53") (pin "TP") (pinfunction "PP_TP") (pintype "input"))
    )
    (net (code "57") (name "Net-(5K-KL)") (class "Default")
      (node (ref "5") (pin "8") (pinfunction "KL_8") (pintype "passive"))
      (node (ref "Q306") (pin "3") (pinfunction "D_3") (pintype "passive"))
      (node (ref "TP54") (pin "TP") (pinfunction "PP_TP") (pintype "input"))
    )
    (net (code "58") (name "Net-(5L-KL)") (class "Default")
      (node (ref "5") (pin "9") (pinfunction "KL_9") (pintype "passive"))
      (node (ref "D302") (pin "1") (pinfunction "+_1") (pintype "passive"))
      (node (ref "TP55") (pin "TP") (pinfunction "PP_TP") (pintype "input"))
      (node (ref "X301") (pin "17") (pinfunction "17_17") (pintype "passive"))
    )
    (net (code "59") (name "Net-(6B-KL)") (class "Default")
      (node (ref "6") (pin "10") (pinfunction "KL_10") (pintype "passive"))
      (node (ref "TP66") (pin "TP") (pinfunction "PP_TP") (pintype "input"))
      (node (ref "X301") (pin "15") (pinfunction "15_15") (pintype "passive"))
    )
    (net (code "60") (name "Net-(6C-KL)") (class "Default")
      (node (ref "6") (pin "11") (pinfunction "KL_11") (pintype "passive"))
      (node (ref "IC307") (pin "16") (pinfunction "O1_16") (pintype "open_collector"))
      (node (ref "R318") (pin "2") (pinfunction "2_2") (pintype "passive"))
      (node (ref "R319") (pin "1") (pinfunction "1_1") (pintype "passive"))
      (node (ref "TP67") (pin "TP") (pinfunction "PP_TP") (pintype "input"))
    )
    (net (code "61") (name "Net-(6D-KL)") (class "Default")
      (node (ref "6") (pin "12") (pinfunction "KL_12") (pintype "passive"))
      (node (ref "R346") (pin "1") (pinfunction "1_1") (pintype "passive"))
      (node (ref "TP69") (pin "TP") (pinfunction "PP_TP") (pintype "input"))
    )
    (net (code "62") (name "Net-(6E-KL)") (class "Default")
      (node (ref "6") (pin "2") (pinfunction "KL_2") (pintype "passive"))
      (node (ref "D309") (pin "2") (pinfunction "-_2") (pintype "passive"))
      (node (ref "LED302") (pin "K") (pinfunction "C_K") (pintype "passive"))
      (node (ref "TP58") (pin "TP") (pinfunction "PP_TP") (pintype "input"))
      (node (ref "X301") (pin "12") (pinfunction "12_12") (pintype "passive"))
    )
    (net (code "63") (name "Net-(6F-KL)") (class "Default")
      (node (ref "6") (pin "3") (pinfunction "KL_3") (pintype "passive"))
      (node (ref "D308") (pin "2") (pinfunction "-_2") (pintype "passive"))
      (node (ref "LED303") (pin "K") (pinfunction "C_K") (pintype "passive"))
      (node (ref "TP59") (pin "TP") (pinfunction "PP_TP") (pintype "input"))
      (node (ref "X301") (pin "11") (pinfunction "11_11") (pintype "passive"))
    )
    (net (code "64") (name "Net-(6G-KL)") (class "Default")
      (node (ref "6") (pin "4") (pinfunction "KL_4") (pintype "passive"))
      (node (ref "D307") (pin "2") (pinfunction "-_2") (pintype "passive"))
      (node (ref "LED304") (pin "K") (pinfunction "C_K") (pintype "passive"))
      (node (ref "TP60") (pin "TP") (pinfunction "PP_TP") (pintype "input"))
      (node (ref "X301") (pin "10") (pinfunction "10_10") (pintype "passive"))
    )
    (net (code "65") (name "Net-(6H-KL)") (class "Default")
      (node (ref "6") (pin "5") (pinfunction "KL_5") (pintype "passive"))
      (node (ref "D306") (pin "2") (pinfunction "-_2") (pintype "passive"))
      (node (ref "LED305") (pin "K") (pinfunction "C_K") (pintype "passive"))
      (node (ref "TP61") (pin "TP") (pinfunction "PP_TP") (pintype "input"))
      (node (ref "X301") (pin "9") (pinfunction "9_9") (pintype "passive"))
    )
    (net (code "66") (name "Net-(6I-KL)") (class "Default")
      (node (ref "6") (pin "6") (pinfunction "KL_6") (pintype "passive"))
      (node (ref "JP305") (pin "2") (pinfunction "2_2") (pintype "passive"))
      (node (ref "TP62") (pin "TP") (pinfunction "PP_TP") (pintype "input"))
    )
    (net (code "67") (name "Net-(6J-KL)") (class "Default")
      (node (ref "6") (pin "7") (pinfunction "KL_7") (pintype "passive"))
      (node (ref "LED301") (pin "A") (pinfunction "A_A") (pintype "passive"))
      (node (ref "TP63") (pin "TP") (pinfunction "PP_TP") (pintype "input"))
      (node (ref "X301") (pin "8") (pinfunction "8_8") (pintype "passive"))
    )
    (net (code "68") (name "Net-(6K-KL)") (class "Default")
      (node (ref "6") (pin "8") (pinfunction "KL_8") (pintype "passive"))
      (node (ref "D310") (pin "2") (pinfunction "-_2") (pintype "passive"))
      (node (ref "LED306") (pin "K") (pinfunction "C_K") (pintype "passive"))
      (node (ref "TP64") (pin "TP") (pinfunction "PP_TP") (pintype "input"))
      (node (ref "X301") (pin "14") (pinfunction "14_14") (pintype "passive"))
    )
    (net (code "69") (name "Net-(6L-KL)") (class "Default")
      (node (ref "6") (pin "9") (pinfunction "KL_9") (pintype "passive"))
      (node (ref "D307") (pin "1") (pinfunction "+_1") (pintype "passive"))
      (node (ref "D308") (pin "1") (pinfunction "+_1") (pintype "passive"))
      (node (ref "JP302") (pin "1") (pinfunction "1_1") (pintype "passive"))
      (node (ref "JP303") (pin "2") (pinfunction "2_2") (pintype "passive"))
      (node (ref "TP65") (pin "TP") (pinfunction "PP_TP") (pintype "input"))
    )
    (net (code "70") (name "Net-(13A-KL)") (class "Default")
      (node (ref "13") (pin "1") (pinfunction "KL_1") (pintype "passive"))
      (node (ref "TP139") (pin "TP") (pinfunction "PP_TP") (pintype "input"))
      (node (ref "X401") (pin "1") (pinfunction "1_1") (pintype "passive"))
    )
    (net (code "71") (name "Net-(13B-KL)") (class "Default")
      (node (ref "13") (pin "10") (pinfunction "KL_10") (pintype "passive"))
      (node (ref "D402") (pin "2") (pinfunction "-_2") (pintype "passive"))
      (node (ref "D403") (pin "2") (pinfunction "-_2") (pintype "passive"))
      (node (ref "JP404") (pin "1") (pinfunction "1_1") (pintype "passive"))
      (node (ref "SJ401") (pin "1") (pinfunction "1_1") (pintype "passive"))
      (node (ref "TP148") (pin "TP") (pinfunction "PP_TP") (pintype "input"))
    )
    (net (code "72") (name "Net-(13C-KL)") (class "Default")
      (node (ref "13") (pin "11") (pinfunction "KL_11") (pintype "passive"))
      (node (ref "D403") (pin "1") (pinfunction "+_1") (pintype "passive"))
      (node (ref "TP149") (pin "TP") (pinfunction "PP_TP") (pintype "input"))
      (node (ref "X401") (pin "19") (pinfunction "19_19") (pintype "passive"))
    )
    (net (code "73") (name "Net-(13E-KL)") (class "Default")
      (node (ref "13") (pin "2") (pinfunction "KL_2") (pintype "passive"))
      (node (ref "Q401") (pin "2") (pinfunction "C_2") (pintype "passive"))
      (node (ref "TP140") (pin "TP") (pinfunction "PP_TP") (pintype "input"))
    )
    (net (code "74") (name "Net-(13F-KL)") (class "Default")
      (node (ref "13") (pin "3") (pinfunction "KL_3") (pintype "passive"))
      (node (ref "IC407") (pin "11") (pinfunction "O6_11") (pintype "open_collector"))
      (node (ref "TP141") (pin "TP") (pinfunction "PP_TP") (pintype "input"))
    )
    (net (code "75") (name "Net-(13G-KL)") (class "Default")
      (node (ref "13") (pin "4") (pinfunction "KL_4") (pintype "passive"))
      (node (ref "IC407") (pin "10") (pinfunction "O7_10") (pintype "open_collector"))
      (node (ref "TP142") (pin "TP") (pinfunction "PP_TP") (pintype "input"))
    )
    (net (code "76") (name "Net-(13H-KL)") (class "Default")
      (node (ref "13") (pin "5") (pinfunction "KL_5") (pintype "passive"))
      (node (ref "IC407") (pin "12") (pinfunction "O5_12") (pintype "open_collector"))
      (node (ref "TP143") (pin "TP") (pinfunction "PP_TP") (pintype "input"))
    )
    (net (code "77") (name "Net-(13I-KL)") (class "Default")
      (node (ref "13") (pin "6") (pinfunction "KL_6") (pintype "passive"))
      (node (ref "IC407") (pin "13") (pinfunction "O4_13") (pintype "open_collector"))
      (node (ref "TP144") (pin "TP") (pinfunction "PP_TP") (pintype "input"))
    )
    (net (code "78") (name "Net-(13J-KL)") (class "Default")
      (node (ref "13") (pin "7") (pinfunction "KL_7") (pintype "passive"))
      (node (ref "IC407") (pin "14") (pinfunction "O3_14") (pintype "open_collector"))
      (node (ref "TP145") (pin "TP") (pinfunction "PP_TP") (pintype "input"))
    )
    (net (code "79") (name "Net-(13K-KL)") (class "Default")
      (node (ref "13") (pin "8") (pinfunction "KL_8") (pintype "passive"))
      (node (ref "Q406") (pin "3") (pinfunction "D_3") (pintype "passive"))
      (node (ref "TP146") (pin "TP") (pinfunction "PP_TP") (pintype "input"))
    )
    (net (code "80") (name "Net-(13L-KL)") (class "Default")
      (node (ref "13") (pin "9") (pinfunction "KL_9") (pintype "passive"))
      (node (ref "D402") (pin "1") (pinfunction "+_1") (pintype "passive"))
      (node (ref "TP147") (pin "TP") (pinfunction "PP_TP") (pintype "input"))
      (node (ref "X401") (pin "17") (pinfunction "17_17") (pintype "passive"))
    )
    (net (code "81") (name "Net-(14B-KL)") (class "Default")
      (node (ref "14") (pin "10") (pinfunction "KL_10") (pintype "passive"))
      (node (ref "TP158") (pin "TP") (pinfunction "PP_TP") (pintype "input"))
      (node (ref "X401") (pin "15") (pinfunction "15_15") (pintype "passive"))
    )
    (net (code "82") (name "Net-(14C-KL)") (class "Default")
      (node (ref "14") (pin "11") (pinfunction "KL_11") (pintype "passive"))
      (node (ref "IC407") (pin "16") (pinfunction "O1_16") (pintype "open_collector"))
      (node (ref "R418") (pin "2") (pinfunction "2_2") (pintype "passive"))
      (node (ref "R419") (pin "1") (pinfunction "1_1") (pintype "passive"))
      (node (ref "TP159") (pin "TP") (pinfunction "PP_TP") (pintype "input"))
    )
    (net (code "83") (name "Net-(14D-KL)") (class "Default")
      (node (ref "14") (pin "12") (pinfunction "KL_12") (pintype "passive"))
      (node (ref "R446") (pin "1") (pinfunction "1_1") (pintype "passive"))
      (node (ref "TP161") (pin "TP") (pinfunction "PP_TP") (pintype "input"))
    )
    (net (code "84") (name "Net-(14E-KL)") (class "Default")
      (node (ref "14") (pin "2") (pinfunction "KL_2") (pintype "passive"))
      (node (ref "D409") (pin "2") (pinfunction "-_2") (pintype "passive"))
      (node (ref "LED402") (pin "K") (pinfunction "C_K") (pintype "passive"))
      (node (ref "TP150") (pin "TP") (pinfunction "PP_TP") (pintype "input"))
      (node (ref "X401") (pin "12") (pinfunction "12_12") (pintype "passive"))
    )
    (net (code "85") (name "Net-(14F-KL)") (class "Default")
      (node (ref "14") (pin "3") (pinfunction "KL_3") (pintype "passive"))
      (node (ref "D408") (pin "2") (pinfunction "-_2") (pintype "passive"))
      (node (ref "LED403") (pin "K") (pinfunction "C_K") (pintype "passive"))
      (node (ref "TP151") (pin "TP") (pinfunction "PP_TP") (pintype "input"))
      (node (ref "X401") (pin "11") (pinfunction "11_11") (pintype "passive"))
    )
    (net (code "86") (name "Net-(14G-KL)") (class "Default")
      (node (ref "14") (pin "4") (pinfunction "KL_4") (pintype "passive"))
      (node (ref "D407") (pin "2") (pinfunction "-_2") (pintype "passive"))
      (node (ref "LED404") (pin "K") (pinfunction "C_K") (pintype "passive"))
      (node (ref "TP152") (pin "TP") (pinfunction "PP_TP") (pintype "input"))
      (node (ref "X401") (pin "10") (pinfunction "10_10") (pintype "passive"))
    )
    (net (code "87") (name "Net-(14H-KL)") (class "Default")
      (node (ref "14") (pin "5") (pinfunction "KL_5") (pintype "passive"))
      (node (ref "D406") (pin "2") (pinfunction "-_2") (pintype "passive"))
      (node (ref "LED405") (pin "K") (pinfunction "C_K") (pintype "passive"))
      (node (ref "TP153") (pin "TP") (pinfunction "PP_TP") (pintype "input"))
      (node (ref "X401") (pin "9") (pinfunction "9_9") (pintype "passive"))
    )
    (net (code "88") (name "Net-(14I-KL)") (class "Default")
      (node (ref "14") (pin "6") (pinfunction "KL_6") (pintype "passive"))
      (node (ref "JP405") (pin "2") (pinfunction "2_2") (pintype "passive"))
      (node (ref "TP154") (pin "TP") (pinfunction "PP_TP") (pintype "input"))
    )
    (net (code "89") (name "Net-(14J-KL)") (class "Default")
      (node (ref "14") (pin "7") (pinfunction "KL_7") (pintype "passive"))
      (node (ref "LED401") (pin "A") (pinfunction "A_A") (pintype "passive"))
      (node (ref "TP155") (pin "TP") (pinfunction "PP_TP") (pintype "input"))
      (node (ref "X401") (pin "8") (pinfunction "8_8") (pintype "passive"))
    )
    (net (code "90") (name "Net-(14K-KL)") (class "Default")
      (node (ref "14") (pin "8") (pinfunction "KL_8") (pintype "passive"))
      (node (ref "D410") (pin "2") (pinfunction "-_2") (pintype "passive"))
      (node (ref "LED406") (pin "K") (pinfunction "C_K") (pintype "passive"))
      (node (ref "TP156") (pin "TP") (pinfunction "PP_TP") (pintype "input"))
      (node (ref "X401") (pin "14") (pinfunction "14_14") (pintype "passive"))
    )
    (net (code "91") (name "Net-(14L-KL)") (class "Default")
      (node (ref "14") (pin "9") (pinfunction "KL_9") (pintype "passive"))
      (node (ref "D407") (pin "1") (pinfunction "+_1") (pintype "passive"))
      (node (ref "D408") (pin "1") (pinfunction "+_1") (pintype "passive"))
      (node (ref "JP402") (pin "1") (pinfunction "1_1") (pintype "passive"))
      (node (ref "JP403") (pin "2") (pinfunction "2_2") (pintype "passive"))
      (node (ref "TP157") (pin "TP") (pinfunction "PP_TP") (pintype "input"))
    )
    (net (code "92") (name "Net-(15A-KL)") (class "Default")
      (node (ref "15") (pin "1") (pinfunction "KL_1") (pintype "passive"))
      (node (ref "TP162") (pin "TP") (pinfunction "PP_TP") (pintype "input"))
      (node (ref "X501") (pin "1") (pinfunction "1_1") (pintype "passive"))
    )
    (net (code "93") (name "Net-(15B-KL)") (class "Default")
      (node (ref "15") (pin "10") (pinfunction "KL_10") (pintype "passive"))
      (node (ref "D502") (pin "2") (pinfunction "-_2") (pintype "passive"))
      (node (ref "D503") (pin "2") (pinfunction "-_2") (pintype "passive"))
      (node (ref "JP504") (pin "1") (pinfunction "1_1") (pintype "passive"))
      (node (ref "SJ501") (pin "1") (pinfunction "1_1") (pintype "passive"))
      (node (ref "TP171") (pin "TP") (pinfunction "PP_TP") (pintype "input"))
    )
    (net (code "94") (name "Net-(15C-KL)") (class "Default")
      (node (ref "15") (pin "11") (pinfunction "KL_11") (pintype "passive"))
      (node (ref "D503") (pin "1") (pinfunction "+_1") (pintype "passive"))
      (node (ref "TP172") (pin "TP") (pinfunction "PP_TP") (pintype "input"))
      (node (ref "X501") (pin "19") (pinfunction "19_19") (pintype "passive"))
    )
    (net (code "95") (name "Net-(15E-KL)") (class "Default")
      (node (ref "15") (pin "2") (pinfunction "KL_2") (pintype "passive"))
      (node (ref "Q501") (pin "2") (pinfunction "C_2") (pintype "passive"))
      (node (ref "TP163") (pin "TP") (pinfunction "PP_TP") (pintype "input"))
    )
    (net (code "96") (name "Net-(15F-KL)") (class "Default")
      (node (ref "15") (pin "3") (pinfunction "KL_3") (pintype "passive"))
      (node (ref "IC507") (pin "11") (pinfunction "O6_11") (pintype "open_collector"))
      (node (ref "TP164") (pin "TP") (pinfunction "PP_TP") (pintype "input"))
    )
    (net (code "97") (name "Net-(15G-KL)") (class "Default")
      (node (ref "15") (pin "4") (pinfunction "KL_4") (pintype "passive"))
      (node (ref "IC507") (pin "10") (pinfunction "O7_10") (pintype "open_collector"))
      (node (ref "TP165") (pin "TP") (pinfunction "PP_TP") (pintype "input"))
    )
    (net (code "98") (name "Net-(15H-KL)") (class "Default")
      (node (ref "15") (pin "5") (pinfunction "KL_5") (pintype "passive"))
      (node (ref "IC507") (pin "12") (pinfunction "O5_12") (pintype "open_collector"))
      (node (ref "TP166") (pin "TP") (pinfunction "PP_TP") (pintype "input"))
    )
    (net (code "99") (name "Net-(15I-KL)") (class "Default")
      (node (ref "15") (pin "6") (pinfunction "KL_6") (pintype "passive"))
      (node (ref "IC507") (pin "13") (pinfunction "O4_13") (pintype "open_collector"))
      (node (ref "TP167") (pin "TP") (pinfunction "PP_TP") (pintype "input"))
    )
    (net (code "100") (name "Net-(15J-KL)") (class "Default")
      (node (ref "15") (pin "7") (pinfunction "KL_7") (pintype "passive"))
      (node (ref "IC507") (pin "14") (pinfunction "O3_14") (pintype "open_collector"))
      (node (ref "TP168") (pin "TP") (pinfunction "PP_TP") (pintype "input"))
    )
    (net (code "101") (name "Net-(15K-KL)") (class "Default")
      (node (ref "15") (pin "8") (pinfunction "KL_8") (pintype "passive"))
      (node (ref "Q506") (pin "3") (pinfunction "D_3") (pintype "passive"))
      (node (ref "TP169") (pin "TP") (pinfunction "PP_TP") (pintype "input"))
    )
    (net (code "102") (name "Net-(15L-KL)") (class "Default")
      (node (ref "15") (pin "9") (pinfunction "KL_9") (pintype "passive"))
      (node (ref "D502") (pin "1") (pinfunction "+_1") (pintype "passive"))
      (node (ref "TP170") (pin "TP") (pinfunction "PP_TP") (pintype "input"))
      (node (ref "X501") (pin "17") (pinfunction "17_17") (pintype "passive"))
    )
    (net (code "103") (name "Net-(16B-KL)") (class "Default")
      (node (ref "16") (pin "10") (pinfunction "KL_10") (pintype "passive"))
      (node (ref "TP181") (pin "TP") (pinfunction "PP_TP") (pintype "input"))
      (node (ref "X501") (pin "15") (pinfunction "15_15") (pintype "passive"))
    )
    (net (code "104") (name "Net-(16C-KL)") (class "Default")
      (node (ref "16") (pin "11") (pinfunction "KL_11") (pintype "passive"))
      (node (ref "IC507") (pin "16") (pinfunction "O1_16") (pintype "open_collector"))
      (node (ref "R518") (pin "2") (pinfunction "2_2") (pintype "passive"))
      (node (ref "R519") (pin "1") (pinfunction "1_1") (pintype "passive"))
      (node (ref "TP182") (pin "TP") (pinfunction "PP_TP") (pintype "input"))
    )
    (net (code "105") (name "Net-(16D-KL)") (class "Default")
      (node (ref "16") (pin "12") (pinfunction "KL_12") (pintype "passive"))
      (node (ref "R546") (pin "1") (pinfunction "1_1") (pintype "passive"))
      (node (ref "TP184") (pin "TP") (pinfunction "PP_TP") (pintype "input"))
    )
    (net (code "106") (name "Net-(16E-KL)") (class "Default")
      (node (ref "16") (pin "2") (pinfunction "KL_2") (pintype "passive"))
      (node (ref "D509") (pin "2") (pinfunction "-_2") (pintype "passive"))
      (node (ref "LED502") (pin "K") (pinfunction "C_K") (pintype "passive"))
      (node (ref "TP173") (pin "TP") (pinfunction "PP_TP") (pintype "input"))
      (node (ref "X501") (pin "12") (pinfunction "12_12") (pintype "passive"))
    )
    (net (code "107") (name "Net-(16F-KL)") (class "Default")
      (node (ref "16") (pin "3") (pinfunction "KL_3") (pintype "passive"))
      (node (ref "D508") (pin "2") (pinfunction "-_2") (pintype "passive"))
      (node (ref "LED503") (pin "K") (pinfunction "C_K") (pintype "passive"))
      (node (ref "TP174") (pin "TP") (pinfunction "PP_TP") (pintype "input"))
      (node (ref "X501") (pin "11") (pinfunction "11_11") (pintype "passive"))
    )
    (net (code "108") (name "Net-(16G-KL)") (class "Default")
      (node (ref "16") (pin "4") (pinfunction "KL_4") (pintype "passive"))
      (node (ref "D507") (pin "2") (pinfunction "-_2") (pintype "passive"))
      (node (ref "LED504") (pin "K") (pinfunction "C_K") (pintype "passive"))
      (node (ref "TP175") (pin "TP") (pinfunction "PP_TP") (pintype "input"))
      (node (ref "X501") (pin "10") (pinfunction "10_10") (pintype "passive"))
    )
    (net (code "109") (name "Net-(16H-KL)") (class "Default")
      (node (ref "16") (pin "5") (pinfunction "KL_5") (pintype "passive"))
      (node (ref "D506") (pin "2") (pinfunction "-_2") (pintype "passive"))
      (node (ref "LED505") (pin "K") (pinfunction "C_K") (pintype "passive"))
      (node (ref "TP176") (pin "TP") (pinfunction "PP_TP") (pintype "input"))
      (node (ref "X501") (pin "9") (pinfunction "9_9") (pintype "passive"))
    )
    (net (code "110") (name "Net-(16I-KL)") (class "Default")
      (node (ref "16") (pin "6") (pinfunction "KL_6") (pintype "passive"))
      (node (ref "JP505") (pin "2") (pinfunction "2_2") (pintype "passive"))
      (node (ref "TP177") (pin "TP") (pinfunction "PP_TP") (pintype "input"))
    )
    (net (code "111") (name "Net-(16J-KL)") (class "Default")
      (node (ref "16") (pin "7") (pinfunction "KL_7") (pintype "passive"))
      (node (ref "LED501") (pin "A") (pinfunction "A_A") (pintype "passive"))
      (node (ref "TP178") (pin "TP") (pinfunction "PP_TP") (pintype "input"))
      (node (ref "X501") (pin "8") (pinfunction "8_8") (pintype "passive"))
    )
    (net (code "112") (name "Net-(16K-KL)") (class "Default")
      (node (ref "16") (pin "8") (pinfunction "KL_8") (pintype "passive"))
      (node (ref "D510") (pin "2") (pinfunction "-_2") (pintype "passive"))
      (node (ref "LED506") (pin "K") (pinfunction "C_K") (pintype "passive"))
      (node (ref "TP179") (pin "TP") (pinfunction "PP_TP") (pintype "input"))
      (node (ref "X501") (pin "14") (pinfunction "14_14") (pintype "passive"))
    )
    (net (code "113") (name "Net-(16L-KL)") (class "Default")
      (node (ref "16") (pin "9") (pinfunction "KL_9") (pintype "passive"))
      (node (ref "D507") (pin "1") (pinfunction "+_1") (pintype "passive"))
      (node (ref "D508") (pin "1") (pinfunction "+_1") (pintype "passive"))
      (node (ref "JP502") (pin "1") (pinfunction "1_1") (pintype "passive"))
      (node (ref "JP503") (pin "2") (pinfunction "2_2") (pintype "passive"))
      (node (ref "TP180") (pin "TP") (pinfunction "PP_TP") (pintype "input"))
    )
    (net (code "114") (name "Net-(17A-KL)") (class "Default")
      (node (ref "17") (pin "1") (pinfunction "KL_1") (pintype "passive"))
      (node (ref "TP185") (pin "TP") (pinfunction "PP_TP") (pintype "input"))
      (node (ref "X601") (pin "1") (pinfunction "1_1") (pintype "passive"))
    )
    (net (code "115") (name "Net-(17B-KL)") (class "Default")
      (node (ref "17") (pin "10") (pinfunction "KL_10") (pintype "passive"))
      (node (ref "D602") (pin "2") (pinfunction "-_2") (pintype "passive"))
      (node (ref "D603") (pin "2") (pinfunction "-_2") (pintype "passive"))
      (node (ref "JP604") (pin "1") (pinfunction "1_1") (pintype "passive"))
      (node (ref "SJ601") (pin "1") (pinfunction "1_1") (pintype "passive"))
      (node (ref "TP194") (pin "TP") (pinfunction "PP_TP") (pintype "input"))
    )
    (net (code "116") (name "Net-(17C-KL)") (class "Default")
      (node (ref "17") (pin "11") (pinfunction "KL_11") (pintype "passive"))
      (node (ref "D603") (pin "1") (pinfunction "+_1") (pintype "passive"))
      (node (ref "TP195") (pin "TP") (pinfunction "PP_TP") (pintype "input"))
      (node (ref "X601") (pin "19") (pinfunction "19_19") (pintype "passive"))
    )
    (net (code "117") (name "Net-(17E-KL)") (class "Default")
      (node (ref "17") (pin "2") (pinfunction "KL_2") (pintype "passive"))
      (node (ref "Q601") (pin "2") (pinfunction "C_2") (pintype "passive"))
      (node (ref "TP186") (pin "TP") (pinfunction "PP_TP") (pintype "input"))
    )
    (net (code "118") (name "Net-(17F-KL)") (class "Default")
      (node (ref "17") (pin "3") (pinfunction "KL_3") (pintype "passive"))
      (node (ref "IC607") (pin "11") (pinfunction "O6_11") (pintype "open_collector"))
      (node (ref "TP187") (pin "TP") (pinfunction "PP_TP") (pintype "input"))
    )
    (net (code "119") (name "Net-(17G-KL)") (class "Default")
      (node (ref "17") (pin "4") (pinfunction "KL_4") (pintype "passive"))
      (node (ref "IC607") (pin "10") (pinfunction "O7_10") (pintype "open_collector"))
      (node (ref "TP188") (pin "TP") (pinfunction "PP_TP") (pintype "input"))
    )
    (net (code "120") (name "Net-(17H-KL)") (class "Default")
      (node (ref "17") (pin "5") (pinfunction "KL_5") (pintype "passive"))
      (node (ref "IC607") (pin "12") (pinfunction "O5_12") (pintype "open_collector"))
      (node (ref "TP189") (pin "TP") (pinfunction "PP_TP") (pintype "input"))
    )
    (net (code "121") (name "Net-(17I-KL)") (class "Default")
      (node (ref "17") (pin "6") (pinfunction "KL_6") (pintype "passive"))
      (node (ref "IC607") (pin "13") (pinfunction "O4_13") (pintype "open_collector"))
      (node (ref "TP190") (pin "TP") (pinfunction "PP_TP") (pintype "input"))
    )
    (net (code "122") (name "Net-(17J-KL)") (class "Default")
      (node (ref "17") (pin "7") (pinfunction "KL_7") (pintype "passive"))
      (node (ref "IC607") (pin "14") (pinfunction "O3_14") (pintype "open_collector"))
      (node (ref "TP191") (pin "TP") (pinfunction "PP_TP") (pintype "input"))
    )
    (net (code "123") (name "Net-(17K-KL)") (class "Default")
      (node (ref "17") (pin "8") (pinfunction "KL_8") (pintype "passive"))
      (node (ref "Q606") (pin "3") (pinfunction "D_3") (pintype "passive"))
      (node (ref "TP192") (pin "TP") (pinfunction "PP_TP") (pintype "input"))
    )
    (net (code "124") (name "Net-(17L-KL)") (class "Default")
      (node (ref "17") (pin "9") (pinfunction "KL_9") (pintype "passive"))
      (node (ref "D602") (pin "1") (pinfunction "+_1") (pintype "passive"))
      (node (ref "TP193") (pin "TP") (pinfunction "PP_TP") (pintype "input"))
      (node (ref "X601") (pin "17") (pinfunction "17_17") (pintype "passive"))
    )
    (net (code "125") (name "Net-(18B-KL)") (class "Default")
      (node (ref "18") (pin "10") (pinfunction "KL_10") (pintype "passive"))
      (node (ref "TP204") (pin "TP") (pinfunction "PP_TP") (pintype "input"))
      (node (ref "X601") (pin "15") (pinfunction "15_15") (pintype "passive"))
    )
    (net (code "126") (name "Net-(18C-KL)") (class "Default")
      (node (ref "18") (pin "11") (pinfunction "KL_11") (pintype "passive"))
      (node (ref "IC607") (pin "16") (pinfunction "O1_16") (pintype "open_collector"))
      (node (ref "R618") (pin "2") (pinfunction "2_2") (pintype "passive"))
      (node (ref "R619") (pin "1") (pinfunction "1_1") (pintype "passive"))
      (node (ref "TP205") (pin "TP") (pinfunction "PP_TP") (pintype "input"))
    )
    (net (code "127") (name "Net-(18D-KL)") (class "Default")
      (node (ref "18") (pin "12") (pinfunction "KL_12") (pintype "passive"))
      (node (ref "R646") (pin "1") (pinfunction "1_1") (pintype "passive"))
      (node (ref "TP207") (pin "TP") (pinfunction "PP_TP") (pintype "input"))
    )
    (net (code "128") (name "Net-(18E-KL)") (class "Default")
      (node (ref "18") (pin "2") (pinfunction "KL_2") (pintype "passive"))
      (node (ref "D609") (pin "2") (pinfunction "-_2") (pintype "passive"))
      (node (ref "LED602") (pin "K") (pinfunction "C_K") (pintype "passive"))
      (node (ref "TP196") (pin "TP") (pinfunction "PP_TP") (pintype "input"))
      (node (ref "X601") (pin "12") (pinfunction "12_12") (pintype "passive"))
    )
    (net (code "129") (name "Net-(18F-KL)") (class "Default")
      (node (ref "18") (pin "3") (pinfunction "KL_3") (pintype "passive"))
      (node (ref "D608") (pin "2") (pinfunction "-_2") (pintype "passive"))
      (node (ref "LED603") (pin "K") (pinfunction "C_K") (pintype "passive"))
      (node (ref "TP197") (pin "TP") (pinfunction "PP_TP") (pintype "input"))
      (node (ref "X601") (pin "11") (pinfunction "11_11") (pintype "passive"))
    )
    (net (code "130") (name "Net-(18G-KL)") (class "Default")
      (node (ref "18") (pin "4") (pinfunction "KL_4") (pintype "passive"))
      (node (ref "D607") (pin "2") (pinfunction "-_2") (pintype "passive"))
      (node (ref "LED604") (pin "K") (pinfunction "C_K") (pintype "passive"))
      (node (ref "TP198") (pin "TP") (pinfunction "PP_TP") (pintype "input"))
      (node (ref "X601") (pin "10") (pinfunction "10_10") (pintype "passive"))
    )
    (net (code "131") (name "Net-(18H-KL)") (class "Default")
      (node (ref "18") (pin "5") (pinfunction "KL_5") (pintype "passive"))
      (node (ref "D606") (pin "2") (pinfunction "-_2") (pintype "passive"))
      (node (ref "LED605") (pin "K") (pinfunction "C_K") (pintype "passive"))
      (node (ref "TP199") (pin "TP") (pinfunction "PP_TP") (pintype "input"))
      (node (ref "X601") (pin "9") (pinfunction "9_9") (pintype "passive"))
    )
    (net (code "132") (name "Net-(18I-KL)") (class "Default")
      (node (ref "18") (pin "6") (pinfunction "KL_6") (pintype "passive"))
      (node (ref "JP605") (pin "2") (pinfunction "2_2") (pintype "passive"))
      (node (ref "TP200") (pin "TP") (pinfunction "PP_TP") (pintype "input"))
    )
    (net (code "133") (name "Net-(18J-KL)") (class "Default")
      (node (ref "18") (pin "7") (pinfunction "KL_7") (pintype "passive"))
      (node (ref "LED601") (pin "A") (pinfunction "A_A") (pintype "passive"))
      (node (ref "TP201") (pin "TP") (pinfunction "PP_TP") (pintype "input"))
      (node (ref "X601") (pin "8") (pinfunction "8_8") (pintype "passive"))
    )
    (net (code "134") (name "Net-(18K-KL)") (class "Default")
      (node (ref "18") (pin "8") (pinfunction "KL_8") (pintype "passive"))
      (node (ref "D610") (pin "2") (pinfunction "-_2") (pintype "passive"))
      (node (ref "LED606") (pin "K") (pinfunction "C_K") (pintype "passive"))
      (node (ref "TP202") (pin "TP") (pinfunction "PP_TP") (pintype "input"))
      (node (ref "X601") (pin "14") (pinfunction "14_14") (pintype "passive"))
    )
    (net (code "135") (name "Net-(18L-KL)") (class "Default")
      (node (ref "18") (pin "9") (pinfunction "KL_9") (pintype "passive"))
      (node (ref "D607") (pin "1") (pinfunction "+_1") (pintype "passive"))
      (node (ref "D608") (pin "1") (pinfunction "+_1") (pintype "passive"))
      (node (ref "JP602") (pin "1") (pinfunction "1_1") (pintype "passive"))
      (node (ref "JP603") (pin "2") (pinfunction "2_2") (pintype "passive"))
      (node (ref "TP203") (pin "TP") (pinfunction "PP_TP") (pintype "input"))
    )
    (net (code "136") (name "Net-(C103-Pad1)") (class "Default")
      (node (ref "C103") (pin "1") (pinfunction "1_1") (pintype "passive"))
      (node (ref "R108") (pin "1") (pinfunction "1_1") (pintype "passive"))
      (node (ref "R112") (pin "1") (pinfunction "1_1") (pintype "passive"))
    )
    (net (code "137") (name "Net-(C107-Pad1)") (class "Default")
      (node (ref "C107") (pin "1") (pinfunction "1_1") (pintype "passive"))
      (node (ref "R125") (pin "1") (pinfunction "1_1") (pintype "passive"))
      (node (ref "R130") (pin "2") (pinfunction "2_2") (pintype "passive"))
    )
    (net (code "138") (name "Net-(C203-Pad1)") (class "Default")
      (node (ref "C203") (pin "1") (pinfunction "1_1") (pintype "passive"))
      (node (ref "R208") (pin "1") (pinfunction "1_1") (pintype "passive"))
      (node (ref "R212") (pin "1") (pinfunction "1_1") (pintype "passive"))
    )
    (net (code "139") (name "Net-(C207-Pad1)") (class "Default")
      (node (ref "C207") (pin "1") (pinfunction "1_1") (pintype "passive"))
      (node (ref "R225") (pin "1") (pinfunction "1_1") (pintype "passive"))
      (node (ref "R230") (pin "2") (pinfunction "2_2") (pintype "passive"))
    )
    (net (code "140") (name "Net-(C303-Pad1)") (class "Default")
      (node (ref "C303") (pin "1") (pinfunction "1_1") (pintype "passive"))
      (node (ref "R308") (pin "1") (pinfunction "1_1") (pintype "passive"))
      (node (ref "R312") (pin "1") (pinfunction "1_1") (pintype "passive"))
    )
    (net (code "141") (name "Net-(C307-Pad1)") (class "Default")
      (node (ref "C307") (pin "1") (pinfunction "1_1") (pintype "passive"))
      (node (ref "R325") (pin "1") (pinfunction "1_1") (pintype "passive"))
      (node (ref "R330") (pin "2") (pinfunction "2_2") (pintype "passive"))
    )
    (net (code "142") (name "Net-(C403-Pad1)") (class "Default")
      (node (ref "C403") (pin "1") (pinfunction "1_1") (pintype "passive"))
      (node (ref "R408") (pin "1") (pinfunction "1_1") (pintype "passive"))
      (node (ref "R412") (pin "1") (pinfunction "1_1") (pintype "passive"))
    )
    (net (code "143") (name "Net-(C407-Pad1)") (class "Default")
      (node (ref "C407") (pin "1") (pinfunction "1_1") (pintype "passive"))
      (node (ref "R425") (pin "1") (pinfunction "1_1") (pintype "passive"))
      (node (ref "R430") (pin "2") (pinfunction "2_2") (pintype "passive"))
    )
    (net (code "144") (name "Net-(C503-Pad1)") (class "Default")
      (node (ref "C503") (pin "1") (pinfunction "1_1") (pintype "passive"))
      (node (ref "R508") (pin "1") (pinfunction "1_1") (pintype "passive"))
      (node (ref "R512") (pin "1") (pinfunction "1_1") (pintype "passive"))
    )
    (net (code "145") (name "Net-(C507-Pad1)") (class "Default")
      (node (ref "C507") (pin "1") (pinfunction "1_1") (pintype "passive"))
      (node (ref "R525") (pin "1") (pinfunction "1_1") (pintype "passive"))
      (node (ref "R530") (pin "2") (pinfunction "2_2") (pintype "passive"))
    )
    (net (code "146") (name "Net-(C603-Pad1)") (class "Default")
      (node (ref "C603") (pin "1") (pinfunction "1_1") (pintype "passive"))
      (node (ref "R608") (pin "1") (pinfunction "1_1") (pintype "passive"))
      (node (ref "R612") (pin "1") (pinfunction "1_1") (pintype "passive"))
    )
    (net (code "147") (name "Net-(C607-Pad1)") (class "Default")
      (node (ref "C607") (pin "1") (pinfunction "1_1") (pintype "passive"))
      (node (ref "R625") (pin "1") (pinfunction "1_1") (pintype "passive"))
      (node (ref "R630") (pin "2") (pinfunction "2_2") (pintype "passive"))
    )
    (net (code "148") (name "Net-(D104-PadC)") (class "Default")
      (node (ref "D104") (pin "C") (pinfunction "C_C") (pintype "passive"))
      (node (ref "R105") (pin "2") (pinfunction "2_2") (pintype "passive"))
      (node (ref "X101") (pin "22") (pinfunction "22_22") (pintype "passive"))
    )
    (net (code "149") (name "Net-(D105--)") (class "Default")
      (node (ref "D105") (pin "2") (pinfunction "-_2") (pintype "passive"))
      (node (ref "Q104") (pin "2") (pinfunction "C_2") (pintype "passive"))
      (node (ref "START") (pin "TP") (pinfunction "PP_TP") (pintype "input"))
      (node (ref "X101") (pin "5") (pinfunction "5_5") (pintype "passive"))
    )
    (net (code "150") (name "Net-(D106-+)") (class "Default")
      (node (ref "D106") (pin "1") (pinfunction "+_1") (pintype "passive"))
      (node (ref "R127") (pin "1") (pinfunction "1_1") (pintype "passive"))
    )
    (net (code "151") (name "Net-(D109-+)") (class "Default")
      (node (ref "D109") (pin "1") (pinfunction "+_1") (pintype "passive"))
      (node (ref "JP102") (pin "2") (pinfunction "2_2") (pintype "passive"))
    )
    (net (code "152") (name "Net-(D110-+)") (class "Default")
      (node (ref "D110") (pin "1") (pinfunction "+_1") (pintype "passive"))
      (node (ref "JP103") (pin "1") (pinfunction "1_1") (pintype "passive"))
    )
    (net (code "153") (name "Net-(D111-+)") (class "Default")
      (node (ref "D111") (pin "1") (pinfunction "+_1") (pintype "passive"))
      (node (ref "R133") (pin "1") (pinfunction "1_1") (pintype "passive"))
    )
    (net (code "154") (name "Net-(D111--)") (class "Default")
      (node (ref "D111") (pin "2") (pinfunction "-_2") (pintype "passive"))
      (node (ref "IC108") (pin "2") (pinfunction "OUT_2") (pintype "open_collector"))
      (node (ref "JP105") (pin "1") (pinfunction "1_1") (pintype "passive"))
      (node (ref "Q107") (pin "1") (pinfunction "G_1") (pintype "passive"))
      (node (ref "R135") (pin "2") (pinfunction "2_2") (pintype "passive"))
    )
    (net (code "155") (name "Net-(D112-+)") (class "Default")
      (node (ref "D112") (pin "1") (pinfunction "+_1") (pintype "passive"))
      (node (ref "R140") (pin "1") (pinfunction "1_1") (pintype "passive"))
    )
    (net (code "156") (name "Net-(D112--)") (class "Default")
      (node (ref "C109") (pin "2") (pinfunction "2_2") (pintype "passive"))
      (node (ref "D112") (pin "2") (pinfunction "-_2") (pintype "passive"))
      (node (ref "IC106") (pin "6") (pinfunction "D2_6") (pintype "passive"))
      (node (ref "IC110") (pin "2") (pinfunction "TR_2") (pintype "input"))
      (node (ref "IC110") (pin "6") (pinfunction "THR_6") (pintype "input"))
      (node (ref "R141") (pin "1") (pinfunction "1_1") (pintype "passive"))
    )
    (net (code "157") (name "Net-(D204-PadC)") (class "Default")
      (node (ref "D204") (pin "C") (pinfunction "C_C") (pintype "passive"))
      (node (ref "R205") (pin "2") (pinfunction "2_2") (pintype "passive"))
      (node (ref "X201") (pin "22") (pinfunction "22_22") (pintype "passive"))
    )
    (net (code "158") (name "Net-(D205--)") (class "Default")
      (node (ref "D205") (pin "2") (pinfunction "-_2") (pintype "passive"))
      (node (ref "Q204") (pin "2") (pinfunction "C_2") (pintype "passive"))
      (node (ref "START201") (pin "TP") (pinfunction "PP_TP") (pintype "input"))
      (node (ref "X201") (pin "5") (pinfunction "5_5") (pintype "passive"))
    )
    (net (code "159") (name "Net-(D206-+)") (class "Default")
      (node (ref "D206") (pin "1") (pinfunction "+_1") (pintype "passive"))
      (node (ref "R227") (pin "1") (pinfunction "1_1") (pintype "passive"))
    )
    (net (code "160") (name "Net-(D209-+)") (class "Default")
      (node (ref "D209") (pin "1") (pinfunction "+_1") (pintype "passive"))
      (node (ref "JP202") (pin "2") (pinfunction "2_2") (pintype "passive"))
    )
    (net (code "161") (name "Net-(D210-+)") (class "Default")
      (node (ref "D210") (pin "1") (pinfunction "+_1") (pintype "passive"))
      (node (ref "JP203") (pin "1") (pinfunction "1_1") (pintype "passive"))
    )
    (net (code "162") (name "Net-(D211-+)") (class "Default")
      (node (ref "D211") (pin "1") (pinfunction "+_1") (pintype "passive"))
      (node (ref "R233") (pin "1") (pinfunction "1_1") (pintype "passive"))
    )
    (net (code "163") (name "Net-(D211--)") (class "Default")
      (node (ref "D211") (pin "2") (pinfunction "-_2") (pintype "passive"))
      (node (ref "IC208") (pin "2") (pinfunction "OUT_2") (pintype "open_collector"))
      (node (ref "JP205") (pin "1") (pinfunction "1_1") (pintype "passive"))
      (node (ref "Q207") (pin "1") (pinfunction "G_1") (pintype "passive"))
      (node (ref "R235") (pin "2") (pinfunction "2_2") (pintype "passive"))
    )
    (net (code "164") (name "Net-(D212-+)") (class "Default")
      (node (ref "D212") (pin "1") (pinfunction "+_1") (pintype "passive"))
      (node (ref "R240") (pin "1") (pinfunction "1_1") (pintype "passive"))
    )
    (net (code "165") (name "Net-(D212--)") (class "Default")
      (node (ref "C209") (pin "2") (pinfunction "2_2") (pintype "passive"))
      (node (ref "D212") (pin "2") (pinfunction "-_2") (pintype "passive"))
      (node (ref "IC206") (pin "6") (pinfunction "D2_6") (pintype "passive"))
      (node (ref "IC210") (pin "2") (pinfunction "TR_2") (pintype "input"))
      (node (ref "IC210") (pin "6") (pinfunction "THR_6") (pintype "input"))
      (node (ref "R241") (pin "1") (pinfunction "1_1") (pintype "passive"))
    )
    (net (code "166") (name "Net-(D304-PadC)") (class "Default")
      (node (ref "D304") (pin "C") (pinfunction "C_C") (pintype "passive"))
      (node (ref "R305") (pin "2") (pinfunction "2_2") (pintype "passive"))
      (node (ref "X301") (pin "22") (pinfunction "22_22") (pintype "passive"))
    )
    (net (code "167") (name "Net-(D305--)") (class "Default")
      (node (ref "D305") (pin "2") (pinfunction "-_2") (pintype "passive"))
      (node (ref "Q304") (pin "2") (pinfunction "C_2") (pintype "passive"))
      (node (ref "START301") (pin "TP") (pinfunction "PP_TP") (pintype "input"))
      (node (ref "X301") (pin "5") (pinfunction "5_5") (pintype "passive"))
    )
    (net (code "168") (name "Net-(D306-+)") (class "Default")
      (node (ref "D306") (pin "1") (pinfunction "+_1") (pintype "passive"))
      (node (ref "R327") (pin "1") (pinfunction "1_1") (pintype "passive"))
    )
    (net (code "169") (name "Net-(D309-+)") (class "Default")
      (node (ref "D309") (pin "1") (pinfunction "+_1") (pintype "passive"))
      (node (ref "JP302") (pin "2") (pinfunction "2_2") (pintype "passive"))
    )
    (net (code "170") (name "Net-(D310-+)") (class "Default")
      (node (ref "D310") (pin "1") (pinfunction "+_1") (pintype "passive"))
      (node (ref "JP303") (pin "1") (pinfunction "1_1") (pintype "passive"))
    )
    (net (code "171") (name "Net-(D311-+)") (class "Default")
      (node (ref "D311") (pin "1") (pinfunction "+_1") (pintype "passive"))
      (node (ref "R333") (pin "1") (pinfunction "1_1") (pintype "passive"))
    )
    (net (code "172") (name "Net-(D311--)") (class "Default")
      (node (ref "D311") (pin "2") (pinfunction "-_2") (pintype "passive"))
      (node (ref "IC308") (pin "2") (pinfunction "OUT_2") (pintype "open_collector"))
      (node (ref "JP305") (pin "1") (pinfunction "1_1") (pintype "passive"))
      (node (ref "Q307") (pin "1") (pinfunction "G_1") (pintype "passive"))
      (node (ref "R335") (pin "2") (pinfunction "2_2") (pintype "passive"))
    )
    (net (code "173") (name "Net-(D312-+)") (class "Default")
      (node (ref "D312") (pin "1") (pinfunction "+_1") (pintype "passive"))
      (node (ref "R340") (pin "1") (pinfunction "1_1") (pintype "passive"))
    )
    (net (code "174") (name "Net-(D312--)") (class "Default")
      (node (ref "C309") (pin "2") (pinfunction "2_2") (pintype "passive"))
      (node (ref "D312") (pin "2") (pinfunction "-_2") (pintype "passive"))
      (node (ref "IC306") (pin "6") (pinfunction "D2_6") (pintype "passive"))
      (node (ref "IC310") (pin "2") (pinfunction "TR_2") (pintype "input"))
      (node (ref "IC310") (pin "6") (pinfunction "THR_6") (pintype "input"))
      (node (ref "R341") (pin "1") (pinfunction "1_1") (pintype "passive"))
    )
    (net (code "175") (name "Net-(D404-PadC)") (class "Default")
      (node (ref "D404") (pin "C") (pinfunction "C_C") (pintype "passive"))
      (node (ref "R405") (pin "2") (pinfunction "2_2") (pintype "passive"))
      (node (ref "X401") (pin "22") (pinfunction "22_22") (pintype "passive"))
    )
    (net (code "176") (name "Net-(D405--)") (class "Default")
      (node (ref "D405") (pin "2") (pinfunction "-_2") (pintype "passive"))
      (node (ref "Q404") (pin "2") (pinfunction "C_2") (pintype "passive"))
      (node (ref "START401") (pin "TP") (pinfunction "PP_TP") (pintype "input"))
      (node (ref "X401") (pin "5") (pinfunction "5_5") (pintype "passive"))
    )
    (net (code "177") (name "Net-(D406-+)") (class "Default")
      (node (ref "D406") (pin "1") (pinfunction "+_1") (pintype "passive"))
      (node (ref "R427") (pin "1") (pinfunction "1_1") (pintype "passive"))
    )
    (net (code "178") (name "Net-(D409-+)") (class "Default")
      (node (ref "D409") (pin "1") (pinfunction "+_1") (pintype "passive"))
      (node (ref "JP402") (pin "2") (pinfunction "2_2") (pintype "passive"))
    )
    (net (code "179") (name "Net-(D410-+)") (class "Default")
      (node (ref "D410") (pin "1") (pinfunction "+_1") (pintype "passive"))
      (node (ref "JP403") (pin "1") (pinfunction "1_1") (pintype "passive"))
    )
    (net (code "180") (name "Net-(D411-+)") (class "Default")
      (node (ref "D411") (pin "1") (pinfunction "+_1") (pintype "passive"))
      (node (ref "R433") (pin "1") (pinfunction "1_1") (pintype "passive"))
    )
    (net (code "181") (name "Net-(D411--)") (class "Default")
      (node (ref "D411") (pin "2") (pinfunction "-_2") (pintype "passive"))
      (node (ref "IC408") (pin "2") (pinfunction "OUT_2") (pintype "open_collector"))
      (node (ref "JP405") (pin "1") (pinfunction "1_1") (pintype "passive"))
      (node (ref "Q407") (pin "1") (pinfunction "G_1") (pintype "passive"))
      (node (ref "R435") (pin "2") (pinfunction "2_2") (pintype "passive"))
    )
    (net (code "182") (name "Net-(D412-+)") (class "Default")
      (node (ref "D412") (pin "1") (pinfunction "+_1") (pintype "passive"))
      (node (ref "R440") (pin "1") (pinfunction "1_1") (pintype "passive"))
    )
    (net (code "183") (name "Net-(D412--)") (class "Default")
      (node (ref "C409") (pin "2") (pinfunction "2_2") (pintype "passive"))
      (node (ref "D412") (pin "2") (pinfunction "-_2") (pintype "passive"))
      (node (ref "IC406") (pin "6") (pinfunction "D2_6") (pintype "passive"))
      (node (ref "IC410") (pin "2") (pinfunction "TR_2") (pintype "input"))
      (node (ref "IC410") (pin "6") (pinfunction "THR_6") (pintype "input"))
      (node (ref "R441") (pin "1") (pinfunction "1_1") (pintype "passive"))
    )
    (net (code "184") (name "Net-(D504-PadC)") (class "Default")
      (node (ref "D504") (pin "C") (pinfunction "C_C") (pintype "passive"))
      (node (ref "R505") (pin "2") (pinfunction "2_2") (pintype "passive"))
      (node (ref "X501") (pin "22") (pinfunction "22_22") (pintype "passive"))
    )
    (net (code "185") (name "Net-(D505--)") (class "Default")
      (node (ref "D505") (pin "2") (pinfunction "-_2") (pintype "passive"))
      (node (ref "Q504") (pin "2") (pinfunction "C_2") (pintype "passive"))
      (node (ref "START501") (pin "TP") (pinfunction "PP_TP") (pintype "input"))
      (node (ref "X501") (pin "5") (pinfunction "5_5") (pintype "passive"))
    )
    (net (code "186") (name "Net-(D506-+)") (class "Default")
      (node (ref "D506") (pin "1") (pinfunction "+_1") (pintype "passive"))
      (node (ref "R527") (pin "1") (pinfunction "1_1") (pintype "passive"))
    )
    (net (code "187") (name "Net-(D509-+)") (class "Default")
      (node (ref "D509") (pin "1") (pinfunction "+_1") (pintype "passive"))
      (node (ref "JP502") (pin "2") (pinfunction "2_2") (pintype "passive"))
    )
    (net (code "188") (name "Net-(D510-+)") (class "Default")
      (node (ref "D510") (pin "1") (pinfunction "+_1") (pintype "passive"))
      (node (ref "JP503") (pin "1") (pinfunction "1_1") (pintype "passive"))
    )
    (net (code "189") (name "Net-(D511-+)") (class "Default")
      (node (ref "D511") (pin "1") (pinfunction "+_1") (pintype "passive"))
      (node (ref "R533") (pin "1") (pinfunction "1_1") (pintype "passive"))
    )
    (net (code "190") (name "Net-(D511--)") (class "Default")
      (node (ref "D511") (pin "2") (pinfunction "-_2") (pintype "passive"))
      (node (ref "IC508") (pin "2") (pinfunction "OUT_2") (pintype "open_collector"))
      (node (ref "JP505") (pin "1") (pinfunction "1_1") (pintype "passive"))
      (node (ref "Q507") (pin "1") (pinfunction "G_1") (pintype "passive"))
      (node (ref "R535") (pin "2") (pinfunction "2_2") (pintype "passive"))
    )
    (net (code "191") (name "Net-(D512-+)") (class "Default")
      (node (ref "D512") (pin "1") (pinfunction "+_1") (pintype "passive"))
      (node (ref "R540") (pin "1") (pinfunction "1_1") (pintype "passive"))
    )
    (net (code "192") (name "Net-(D512--)") (class "Default")
      (node (ref "C509") (pin "2") (pinfunction "2_2") (pintype "passive"))
      (node (ref "D512") (pin "2") (pinfunction "-_2") (pintype "passive"))
      (node (ref "IC506") (pin "6") (pinfunction "D2_6") (pintype "passive"))
      (node (ref "IC510") (pin "2") (pinfunction "TR_2") (pintype "input"))
      (node (ref "IC510") (pin "6") (pinfunction "THR_6") (pintype "input"))
      (node (ref "R541") (pin "1") (pinfunction "1_1") (pintype "passive"))
    )
    (net (code "193") (name "Net-(D604-PadC)") (class "Default")
      (node (ref "D604") (pin "C") (pinfunction "C_C") (pintype "passive"))
      (node (ref "R605") (pin "2") (pinfunction "2_2") (pintype "passive"))
      (node (ref "X601") (pin "22") (pinfunction "22_22") (pintype "passive"))
    )
    (net (code "194") (name "Net-(D605--)") (class "Default")
      (node (ref "D605") (pin "2") (pinfunction "-_2") (pintype "passive"))
      (node (ref "Q604") (pin "2") (pinfunction "C_2") (pintype "passive"))
      (node (ref "START601") (pin "TP") (pinfunction "PP_TP") (pintype "input"))
      (node (ref "X601") (pin "5") (pinfunction "5_5") (pintype "passive"))
    )
    (net (code "195") (name "Net-(D606-+)") (class "Default")
      (node (ref "D606") (pin "1") (pinfunction "+_1") (pintype "passive"))
      (node (ref "R627") (pin "1") (pinfunction "1_1") (pintype "passive"))
    )
    (net (code "196") (name "Net-(D609-+)") (class "Default")
      (node (ref "D609") (pin "1") (pinfunction "+_1") (pintype "passive"))
      (node (ref "JP602") (pin "2") (pinfunction "2_2") (pintype "passive"))
    )
    (net (code "197") (name "Net-(D610-+)") (class "Default")
      (node (ref "D610") (pin "1") (pinfunction "+_1") (pintype "passive"))
      (node (ref "JP603") (pin "1") (pinfunction "1_1") (pintype "passive"))
    )
    (net (code "198") (name "Net-(D611-+)") (class "Default")
      (node (ref "D611") (pin "1") (pinfunction "+_1") (pintype "passive"))
      (node (ref "R633") (pin "1") (pinfunction "1_1") (pintype "passive"))
    )
    (net (code "199") (name "Net-(D611--)") (class "Default")
      (node (ref "D611") (pin "2") (pinfunction "-_2") (pintype "passive"))
      (node (ref "IC608") (pin "2") (pinfunction "OUT_2") (pintype "open_collector"))
      (node (ref "JP605") (pin "1") (pinfunction "1_1") (pintype "passive"))
      (node (ref "Q607") (pin "1") (pinfunction "G_1") (pintype "passive"))
      (node (ref "R635") (pin "2") (pinfunction "2_2") (pintype "passive"))
    )
    (net (code "200") (name "Net-(D612-+)") (class "Default")
      (node (ref "D612") (pin "1") (pinfunction "+_1") (pintype "passive"))
      (node (ref "R640") (pin "1") (pinfunction "1_1") (pintype "passive"))
    )
    (net (code "201") (name "Net-(D612--)") (class "Default")
      (node (ref "C609") (pin "2") (pinfunction "2_2") (pintype "passive"))
      (node (ref "D612") (pin "2") (pinfunction "-_2") (pintype "passive"))
      (node (ref "IC606") (pin "6") (pinfunction "D2_6") (pintype "passive"))
      (node (ref "IC610") (pin "2") (pinfunction "TR_2") (pintype "input"))
      (node (ref "IC610") (pin "6") (pinfunction "THR_6") (pintype "input"))
      (node (ref "R641") (pin "1") (pinfunction "1_1") (pintype "passive"))
    )
    (net (code "202") (name "Net-(IC101A-+IN)") (class "Default")
      (node (ref "C101") (pin "1") (pinfunction "1_1") (pintype "passive"))
      (node (ref "IC101") (pin "3") (pinfunction "+IN_3") (pintype "input"))
      (node (ref "R105") (pin "1") (pinfunction "1_1") (pintype "passive"))
    )
    (net (code "203") (name "Net-(IC101A--IN)") (class "Default")
      (node (ref "IC101") (pin "2") (pinfunction "-IN_2") (pintype "input"))
      (node (ref "R107") (pin "2") (pinfunction "2_2") (pintype "passive"))
    )
    (net (code "204") (name "Net-(IC101A-OUT)") (class "Default")
      (node (ref "IC101") (pin "1") (pinfunction "OUT_1") (pintype "output"))
      (node (ref "R108") (pin "2") (pinfunction "2_2") (pintype "passive"))
    )
    (net (code "205") (name "Net-(IC101B-+IN)") (class "Default")
      (node (ref "IC101") (pin "5") (pinfunction "+IN_5") (pintype "input"))
      (node (ref "R112") (pin "2") (pinfunction "2_2") (pintype "passive"))
      (node (ref "R117") (pin "2") (pinfunction "2_2") (pintype "passive"))
    )
    (net (code "206") (name "Net-(IC101B--IN)") (class "Default")
      (node (ref "IC101") (pin "6") (pinfunction "-IN_6") (pintype "input"))
      (node (ref "R113") (pin "1") (pinfunction "1_1") (pintype "passive"))
      (node (ref "R114") (pin "2") (pinfunction "2_2") (pintype "passive"))
    )
    (net (code "207") (name "Net-(IC101B-OUT)") (class "Default")
      (node (ref "IC101") (pin "7") (pinfunction "OUT_7") (pintype "output"))
      (node (ref "R116") (pin "1") (pinfunction "1_1") (pintype "passive"))
      (node (ref "R117") (pin "1") (pinfunction "1_1") (pintype "passive"))
    )
    (net (code "208") (name "Net-(IC105A-A)") (class "Default")
      (node (ref "IC105") (pin "10") (pinfunction "A_10") (pintype "input"))
      (node (ref "IC106") (pin "1") (pinfunction "D1_1") (pintype "passive"))
      (node (ref "R111") (pin "1") (pinfunction "1_1") (pintype "passive"))
      (node (ref "X101") (pin "4") (pinfunction "4_4") (pintype "passive"))
      (node (ref "X103") (pin "2") (pinfunction "S_2") (pintype "passive"))
    )
    (net (code "209") (name "Net-(IC105A-B)") (class "Default")
      (node (ref "IC105") (pin "13") (pinfunction "B_13") (pintype "input"))
      (node (ref "IC106") (pin "4") (pinfunction "D4_4") (pintype "passive"))
      (node (ref "R110") (pin "1") (pinfunction "1_1") (pintype "passive"))
      (node (ref "X101") (pin "3") (pinfunction "3_3") (pintype "passive"))
      (node (ref "X103") (pin "3") (pinfunction "S_3") (pintype "passive"))
    )
    (net (code "210") (name "Net-(IC105A-C)") (class "Default")
      (node (ref "IC105") (pin "12") (pinfunction "C_12") (pintype "input"))
      (node (ref "IC106") (pin "3") (pinfunction "D3_3") (pintype "passive"))
      (node (ref "R109") (pin "1") (pinfunction "1_1") (pintype "passive"))
      (node (ref "X101") (pin "2") (pinfunction "2_2") (pintype "passive"))
      (node (ref "X103") (pin "4") (pinfunction "S_4") (pintype "passive"))
    )
    (net (code "211") (name "Net-(IC105A-Q0)") (class "Default")
      (node (ref "IC105") (pin "3") (pinfunction "Q0_3") (pintype "output"))
      (node (ref "IC107") (pin "1") (pinfunction "I1_1") (pintype "input"))
      (node (ref "IC107") (pin "2") (pinfunction "I2_2") (pintype "input"))
      (node (ref "Q106") (pin "1") (pinfunction "G_1") (pintype "passive"))
    )
    (net (code "212") (name "Net-(IC105A-Q1)") (class "Default")
      (node (ref "IC105") (pin "14") (pinfunction "Q1_14") (pintype "output"))
      (node (ref "IC107") (pin "6") (pinfunction "I6_6") (pintype "input"))
    )
    (net (code "213") (name "Net-(IC105A-Q2)") (class "Default")
      (node (ref "IC105") (pin "2") (pinfunction "Q2_2") (pintype "output"))
      (node (ref "IC107") (pin "7") (pinfunction "I7_7") (pintype "input"))
    )
    (net (code "214") (name "Net-(IC105A-Q3)") (class "Default")
      (node (ref "IC105") (pin "15") (pinfunction "Q3_15") (pintype "output"))
      (node (ref "IC107") (pin "5") (pinfunction "I5_5") (pintype "input"))
    )
    (net (code "215") (name "Net-(IC105A-Q4)") (class "Default")
      (node (ref "IC105") (pin "1") (pinfunction "Q4_1") (pintype "output"))
      (node (ref "IC107") (pin "4") (pinfunction "I4_4") (pintype "input"))
    )
    (net (code "216") (name "Net-(IC105A-Q5)") (class "Default")
      (node (ref "IC105") (pin "6") (pinfunction "Q5_6") (pintype "output"))
      (node (ref "IC107") (pin "3") (pinfunction "I3_3") (pintype "input"))
    )
    (net (code "217") (name "Net-(IC107-O2)") (class "Default")
      (node (ref "IC107") (pin "15") (pinfunction "O2_15") (pintype "open_collector"))
      (node (ref "R128") (pin "1") (pinfunction "1_1") (pintype "passive"))
    )
    (net (code "218") (name "Net-(IC108A-+IN)") (class "Default")
      (node (ref "IC108") (pin "5") (pinfunction "+IN_5") (pintype "input"))
      (node (ref "R131") (pin "1") (pinfunction "1_1") (pintype "passive"))
      (node (ref "R132") (pin "2") (pinfunction "2_2") (pintype "passive"))
      (node (ref "R133") (pin "2") (pinfunction "2_2") (pintype "passive"))
    )
    (net (code "219") (name "Net-(IC108A--IN)") (class "Default")
      (node (ref "C108") (pin "1") (pinfunction "1_1") (pintype "passive"))
      (node (ref "IC108") (pin "4") (pinfunction "-IN_4") (pintype "input"))
      (node (ref "R130") (pin "1") (pinfunction "1_1") (pintype "passive"))
    )
    (net (code "220") (name "Net-(IC108B-+IN)") (class "Default")
      (node (ref "IC108") (pin "7") (pinfunction "+IN_7") (pintype "input"))
      (node (ref "R121") (pin "1") (pinfunction "1_1") (pintype "passive"))
      (node (ref "R122") (pin "1") (pinfunction "1_1") (pintype "passive"))
    )
    (net (code "221") (name "Net-(IC108B--IN)") (class "Default")
      (node (ref "IC108") (pin "6") (pinfunction "-IN_6") (pintype "input"))
      (node (ref "IC108") (pin "8") (pinfunction "-IN_8") (pintype "input"))
      (node (ref "R120") (pin "1") (pinfunction "1_1") (pintype "passive"))
    )
    (net (code "222") (name "Net-(IC108B-OUT)") (class "Default")
      (node (ref "IC108") (pin "1") (pinfunction "OUT_1") (pintype "open_collector"))
      (node (ref "R124") (pin "2") (pinfunction "2_2") (pintype "passive"))
      (node (ref "R125") (pin "2") (pinfunction "2_2") (pintype "passive"))
    )
    (net (code "223") (name "Net-(IC108C-+IN)") (class "Default")
      (node (ref "C105") (pin "1") (pinfunction "1_1") (pintype "passive"))
      (node (ref "IC108") (pin "9") (pinfunction "+IN_9") (pintype "input"))
      (node (ref "R122") (pin "2") (pinfunction "2_2") (pintype "passive"))
      (node (ref "R123") (pin "2") (pinfunction "2_2") (pintype "passive"))
    )
    (net (code "224") (name "Net-(IC108C-OUT)") (class "Default")
      (node (ref "C106") (pin "2") (pinfunction "2_2") (pintype "passive"))
      (node (ref "IC108") (pin "14") (pinfunction "OUT_14") (pintype "open_collector"))
      (node (ref "R126") (pin "2") (pinfunction "2_2") (pintype "passive"))
    )
    (net (code "225") (name "Net-(IC109-ADJ)") (class "Default")
      (node (ref "IC109") (pin "1") (pinfunction "ADJ_1") (pintype "input"))
      (node (ref "R120") (pin "2") (pinfunction "2_2") (pintype "passive"))
      (node (ref "R134") (pin "1") (pinfunction "1_1") (pintype "passive"))
      (node (ref "X101") (pin "7") (pinfunction "7_7") (pintype "passive"))
    )
    (net (code "226") (name "Net-(IC109-VI)") (class "Default")
      (node (ref "IC109") (pin "3") (pinfunction "VI_3") (pintype "input"))
      (node (ref "Q105") (pin "2") (pinfunction "C_2") (pintype "passive"))
    )
    (net (code "227") (name "Net-(IC109-VO)") (class "Default")
      (node (ref "IC109") (pin "2") (pinfunction "VO_2") (pintype "passive"))
      (node (ref "R134") (pin "2") (pinfunction "2_2") (pintype "passive"))
    )
    (net (code "228") (name "Net-(IC110-CV)") (class "Default")
      (node (ref "IC110") (pin "5") (pinfunction "CV_5") (pintype "input"))
      (node (ref "R144") (pin "2") (pinfunction "2_2") (pintype "passive"))
    )
    (net (code "229") (name "Net-(IC110-Q)") (class "Default")
      (node (ref "IC110") (pin "3") (pinfunction "Q_3") (pintype "output"))
      (node (ref "IC111") (pin "12") (pinfunction "A_12") (pintype "input"))
      (node (ref "R144") (pin "1") (pinfunction "1_1") (pintype "passive"))
    )
    (net (code "230") (name "Net-(IC111B-B)") (class "Default")
      (node (ref "IC111") (pin "11") (pinfunction "B_11") (pintype "input"))
      (node (ref "IC111") (pin "9") (pinfunction "~{Q}_9") (pintype "output"))
      (node (ref "R146") (pin "2") (pinfunction "2_2") (pintype "passive"))
    )
    (net (code "231") (name "Net-(IC111B-T2)") (class "Default")
      (node (ref "C110") (pin "1") (pinfunction "1_1") (pintype "passive"))
      (node (ref "IC111") (pin "14") (pinfunction "T2_14") (pintype "input"))
      (node (ref "R145") (pin "1") (pinfunction "1_1") (pintype "passive"))
    )
    (net (code "232") (name "Net-(IC201A-+IN)") (class "Default")
      (node (ref "C201") (pin "1") (pinfunction "1_1") (pintype "passive"))
      (node (ref "IC201") (pin "3") (pinfunction "+IN_3") (pintype "input"))
      (node (ref "R205") (pin "1") (pinfunction "1_1") (pintype "passive"))
    )
    (net (code "233") (name "Net-(IC201A--IN)") (class "Default")
      (node (ref "IC201") (pin "2") (pinfunction "-IN_2") (pintype "input"))
      (node (ref "R207") (pin "2") (pinfunction "2_2") (pintype "passive"))
    )
    (net (code "234") (name "Net-(IC201A-OUT)") (class "Default")
      (node (ref "IC201") (pin "1") (pinfunction "OUT_1") (pintype "output"))
      (node (ref "R208") (pin "2") (pinfunction "2_2") (pintype "passive"))
    )
    (net (code "235") (name "Net-(IC201B-+IN)") (class "Default")
      (node (ref "IC201") (pin "5") (pinfunction "+IN_5") (pintype "input"))
      (node (ref "R212") (pin "2") (pinfunction "2_2") (pintype "passive"))
      (node (ref "R217") (pin "2") (pinfunction "2_2") (pintype "passive"))
    )
    (net (code "236") (name "Net-(IC201B--IN)") (class "Default")
      (node (ref "IC201") (pin "6") (pinfunction "-IN_6") (pintype "input"))
      (node (ref "R213") (pin "1") (pinfunction "1_1") (pintype "passive"))
      (node (ref "R214") (pin "2") (pinfunction "2_2") (pintype "passive"))
    )
    (net (code "237") (name "Net-(IC201B-OUT)") (class "Default")
      (node (ref "IC201") (pin "7") (pinfunction "OUT_7") (pintype "output"))
      (node (ref "R216") (pin "1") (pinfunction "1_1") (pintype "passive"))
      (node (ref "R217") (pin "1") (pinfunction "1_1") (pintype "passive"))
    )
    (net (code "238") (name "Net-(IC205A-A)") (class "Default")
      (node (ref "IC205") (pin "10") (pinfunction "A_10") (pintype "input"))
      (node (ref "IC206") (pin "1") (pinfunction "D1_1") (pintype "passive"))
      (node (ref "R211") (pin "1") (pinfunction "1_1") (pintype "passive"))
      (node (ref "X201") (pin "4") (pinfunction "4_4") (pintype "passive"))
      (node (ref "X203") (pin "2") (pinfunction "S_2") (pintype "passive"))
    )
    (net (code "239") (name "Net-(IC205A-B)") (class "Default")
      (node (ref "IC205") (pin "13") (pinfunction "B_13") (pintype "input"))
      (node (ref "IC206") (pin "4") (pinfunction "D4_4") (pintype "passive"))
      (node (ref "R210") (pin "1") (pinfunction "1_1") (pintype "passive"))
      (node (ref "X201") (pin "3") (pinfunction "3_3") (pintype "passive"))
      (node (ref "X203") (pin "3") (pinfunction "S_3") (pintype "passive"))
    )
    (net (code "240") (name "Net-(IC205A-C)") (class "Default")
      (node (ref "IC205") (pin "12") (pinfunction "C_12") (pintype "input"))
      (node (ref "IC206") (pin "3") (pinfunction "D3_3") (pintype "passive"))
      (node (ref "R209") (pin "1") (pinfunction "1_1") (pintype "passive"))
      (node (ref "X201") (pin "2") (pinfunction "2_2") (pintype "passive"))
      (node (ref "X203") (pin "4") (pinfunction "S_4") (pintype "passive"))
    )
    (net (code "241") (name "Net-(IC205A-Q0)") (class "Default")
      (node (ref "IC205") (pin "3") (pinfunction "Q0_3") (pintype "output"))
      (node (ref "IC207") (pin "1") (pinfunction "I1_1") (pintype "input"))
      (node (ref "IC207") (pin "2") (pinfunction "I2_2") (pintype "input"))
      (node (ref "Q206") (pin "1") (pinfunction "G_1") (pintype "passive"))
    )
    (net (code "242") (name "Net-(IC205A-Q1)") (class "Default")
      (node (ref "IC205") (pin "14") (pinfunction "Q1_14") (pintype "output"))
      (node (ref "IC207") (pin "6") (pinfunction "I6_6") (pintype "input"))
    )
    (net (code "243") (name "Net-(IC205A-Q2)") (class "Default")
      (node (ref "IC205") (pin "2") (pinfunction "Q2_2") (pintype "output"))
      (node (ref "IC207") (pin "7") (pinfunction "I7_7") (pintype "input"))
    )
    (net (code "244") (name "Net-(IC205A-Q3)") (class "Default")
      (node (ref "IC205") (pin "15") (pinfunction "Q3_15") (pintype "output"))
      (node (ref "IC207") (pin "5") (pinfunction "I5_5") (pintype "input"))
    )
    (net (code "245") (name "Net-(IC205A-Q4)") (class "Default")
      (node (ref "IC205") (pin "1") (pinfunction "Q4_1") (pintype "output"))
      (node (ref "IC207") (pin "4") (pinfunction "I4_4") (pintype "input"))
    )
    (net (code "246") (name "Net-(IC205A-Q5)") (class "Default")
      (node (ref "IC205") (pin "6") (pinfunction "Q5_6") (pintype "output"))
      (node (ref "IC207") (pin "3") (pinfunction "I3_3") (pintype "input"))
    )
    (net (code "247") (name "Net-(IC207-O2)") (class "Default")
      (node (ref "IC207") (pin "15") (pinfunction "O2_15") (pintype "open_collector"))
      (node (ref "R228") (pin "1") (pinfunction "1_1") (pintype "passive"))
    )
    (net (code "248") (name "Net-(IC208A-+IN)") (class "Default")
      (node (ref "IC208") (pin "5") (pinfunction "+IN_5") (pintype "input"))
      (node (ref "R231") (pin "1") (pinfunction "1_1") (pintype "passive"))
      (node (ref "R232") (pin "2") (pinfunction "2_2") (pintype "passive"))
      (node (ref "R233") (pin "2") (pinfunction "2_2") (pintype "passive"))
    )
    (net (code "249") (name "Net-(IC208A--IN)") (class "Default")
      (node (ref "C208") (pin "1") (pinfunction "1_1") (pintype "passive"))
      (node (ref "IC208") (pin "4") (pinfunction "-IN_4") (pintype "input"))
      (node (ref "R230") (pin "1") (pinfunction "1_1") (pintype "passive"))
    )
    (net (code "250") (name "Net-(IC208B-+IN)") (class "Default")
      (node (ref "IC208") (pin "7") (pinfunction "+IN_7") (pintype "input"))
      (node (ref "R221") (pin "1") (pinfunction "1_1") (pintype "passive"))
      (node (ref "R222") (pin "1") (pinfunction "1_1") (pintype "passive"))
    )
    (net (code "251") (name "Net-(IC208B--IN)") (class "Default")
      (node (ref "IC208") (pin "6") (pinfunction "-IN_6") (pintype "input"))
      (node (ref "IC208") (pin "8") (pinfunction "-IN_8") (pintype "input"))
      (node (ref "R220") (pin "1") (pinfunction "1_1") (pintype "passive"))
    )
    (net (code "252") (name "Net-(IC208B-OUT)") (class "Default")
      (node (ref "IC208") (pin "1") (pinfunction "OUT_1") (pintype "open_collector"))
      (node (ref "R224") (pin "2") (pinfunction "2_2") (pintype "passive"))
      (node (ref "R225") (pin "2") (pinfunction "2_2") (pintype "passive"))
    )
    (net (code "253") (name "Net-(IC208C-+IN)") (class "Default")
      (node (ref "C205") (pin "1") (pinfunction "1_1") (pintype "passive"))
      (node (ref "IC208") (pin "9") (pinfunction "+IN_9") (pintype "input"))
      (node (ref "R222") (pin "2") (pinfunction "2_2") (pintype "passive"))
      (node (ref "R223") (pin "2") (pinfunction "2_2") (pintype "passive"))
    )
    (net (code "254") (name "Net-(IC208C-OUT)") (class "Default")
      (node (ref "C206") (pin "2") (pinfunction "2_2") (pintype "passive"))
      (node (ref "IC208") (pin "14") (pinfunction "OUT_14") (pintype "open_collector"))
      (node (ref "R226") (pin "2") (pinfunction "2_2") (pintype "passive"))
    )
    (net (code "255") (name "Net-(IC209-ADJ)") (class "Default")
      (node (ref "IC209") (pin "1") (pinfunction "ADJ_1") (pintype "input"))
      (node (ref "R220") (pin "2") (pinfunction "2_2") (pintype "passive"))
      (node (ref "R234") (pin "1") (pinfunction "1_1") (pintype "passive"))
      (node (ref "X201") (pin "7") (pinfunction "7_7") (pintype "passive"))
    )
    (net (code "256") (name "Net-(IC209-VI)") (class "Default")
      (node (ref "IC209") (pin "3") (pinfunction "VI_3") (pintype "input"))
      (node (ref "Q205") (pin "2") (pinfunction "C_2") (pintype "passive"))
    )
    (net (code "257") (name "Net-(IC209-VO)") (class "Default")
      (node (ref "IC209") (pin "2") (pinfunction "VO_2") (pintype "passive"))
      (node (ref "R234") (pin "2") (pinfunction "2_2") (pintype "passive"))
    )
    (net (code "258") (name "Net-(IC210-CV)") (class "Default")
      (node (ref "IC210") (pin "5") (pinfunction "CV_5") (pintype "input"))
      (node (ref "R244") (pin "2") (pinfunction "2_2") (pintype "passive"))
    )
    (net (code "259") (name "Net-(IC210-Q)") (class "Default")
      (node (ref "IC210") (pin "3") (pinfunction "Q_3") (pintype "output"))
      (node (ref "IC211") (pin "12") (pinfunction "A_12") (pintype "input"))
      (node (ref "R244") (pin "1") (pinfunction "1_1") (pintype "passive"))
    )
    (net (code "260") (name "Net-(IC211B-B)") (class "Default")
      (node (ref "IC211") (pin "11") (pinfunction "B_11") (pintype "input"))
      (node (ref "IC211") (pin "9") (pinfunction "~{Q}_9") (pintype "output"))
      (node (ref "R246") (pin "2") (pinfunction "2_2") (pintype "passive"))
    )
    (net (code "261") (name "Net-(IC211B-T2)") (class "Default")
      (node (ref "C210") (pin "1") (pinfunction "1_1") (pintype "passive"))
      (node (ref "IC211") (pin "14") (pinfunction "T2_14") (pintype "input"))
      (node (ref "R245") (pin "1") (pinfunction "1_1") (pintype "passive"))
    )
    (net (code "262") (name "Net-(IC301A-+IN)") (class "Default")
      (node (ref "C301") (pin "1") (pinfunction "1_1") (pintype "passive"))
      (node (ref "IC301") (pin "3") (pinfunction "+IN_3") (pintype "input"))
      (node (ref "R305") (pin "1") (pinfunction "1_1") (pintype "passive"))
    )
    (net (code "263") (name "Net-(IC301A--IN)") (class "Default")
      (node (ref "IC301") (pin "2") (pinfunction "-IN_2") (pintype "input"))
      (node (ref "R307") (pin "2") (pinfunction "2_2") (pintype "passive"))
    )
    (net (code "264") (name "Net-(IC301A-OUT)") (class "Default")
      (node (ref "IC301") (pin "1") (pinfunction "OUT_1") (pintype "output"))
      (node (ref "R308") (pin "2") (pinfunction "2_2") (pintype "passive"))
    )
    (net (code "265") (name "Net-(IC301B-+IN)") (class "Default")
      (node (ref "IC301") (pin "5") (pinfunction "+IN_5") (pintype "input"))
      (node (ref "R312") (pin "2") (pinfunction "2_2") (pintype "passive"))
      (node (ref "R317") (pin "2") (pinfunction "2_2") (pintype "passive"))
    )
    (net (code "266") (name "Net-(IC301B--IN)") (class "Default")
      (node (ref "IC301") (pin "6") (pinfunction "-IN_6") (pintype "input"))
      (node (ref "R313") (pin "1") (pinfunction "1_1") (pintype "passive"))
      (node (ref "R314") (pin "2") (pinfunction "2_2") (pintype "passive"))
    )
    (net (code "267") (name "Net-(IC301B-OUT)") (class "Default")
      (node (ref "IC301") (pin "7") (pinfunction "OUT_7") (pintype "output"))
      (node (ref "R316") (pin "1") (pinfunction "1_1") (pintype "passive"))
      (node (ref "R317") (pin "1") (pinfunction "1_1") (pintype "passive"))
    )
    (net (code "268") (name "Net-(IC305A-A)") (class "Default")
      (node (ref "IC305") (pin "10") (pinfunction "A_10") (pintype "input"))
      (node (ref "IC306") (pin "1") (pinfunction "D1_1") (pintype "passive"))
      (node (ref "R311") (pin "1") (pinfunction "1_1") (pintype "passive"))
      (node (ref "X301") (pin "4") (pinfunction "4_4") (pintype "passive"))
      (node (ref "X303") (pin "2") (pinfunction "S_2") (pintype "passive"))
    )
    (net (code "269") (name "Net-(IC305A-B)") (class "Default")
      (node (ref "IC305") (pin "13") (pinfunction "B_13") (pintype "input"))
      (node (ref "IC306") (pin "4") (pinfunction "D4_4") (pintype "passive"))
      (node (ref "R310") (pin "1") (pinfunction "1_1") (pintype "passive"))
      (node (ref "X301") (pin "3") (pinfunction "3_3") (pintype "passive"))
      (node (ref "X303") (pin "3") (pinfunction "S_3") (pintype "passive"))
    )
    (net (code "270") (name "Net-(IC305A-C)") (class "Default")
      (node (ref "IC305") (pin "12") (pinfunction "C_12") (pintype "input"))
      (node (ref "IC306") (pin "3") (pinfunction "D3_3") (pintype "passive"))
      (node (ref "R309") (pin "1") (pinfunction "1_1") (pintype "passive"))
      (node (ref "X301") (pin "2") (pinfunction "2_2") (pintype "passive"))
      (node (ref "X303") (pin "4") (pinfunction "S_4") (pintype "passive"))
    )
    (net (code "271") (name "Net-(IC305A-Q0)") (class "Default")
      (node (ref "IC305") (pin "3") (pinfunction "Q0_3") (pintype "output"))
      (node (ref "IC307") (pin "1") (pinfunction "I1_1") (pintype "input"))
      (node (ref "IC307") (pin "2") (pinfunction "I2_2") (pintype "input"))
      (node (ref "Q306") (pin "1") (pinfunction "G_1") (pintype "passive"))
    )
    (net (code "272") (name "Net-(IC305A-Q1)") (class "Default")
      (node (ref "IC305") (pin "14") (pinfunction "Q1_14") (pintype "output"))
      (node (ref "IC307") (pin "6") (pinfunction "I6_6") (pintype "input"))
    )
    (net (code "273") (name "Net-(IC305A-Q2)") (class "Default")
      (node (ref "IC305") (pin "2") (pinfunction "Q2_2") (pintype "output"))
      (node (ref "IC307") (pin "7") (pinfunction "I7_7") (pintype "input"))
    )
    (net (code "274") (name "Net-(IC305A-Q3)") (class "Default")
      (node (ref "IC305") (pin "15") (pinfunction "Q3_15") (pintype "output"))
      (node (ref "IC307") (pin "5") (pinfunction "I5_5") (pintype "input"))
    )
    (net (code "275") (name "Net-(IC305A-Q4)") (class "Default")
      (node (ref "IC305") (pin "1") (pinfunction "Q4_1") (pintype "output"))
      (node (ref "IC307") (pin "4") (pinfunction "I4_4") (pintype "input"))
    )
    (net (code "276") (name "Net-(IC305A-Q5)") (class "Default")
      (node (ref "IC305") (pin "6") (pinfunction "Q5_6") (pintype "output"))
      (node (ref "IC307") (pin "3") (pinfunction "I3_3") (pintype "input"))
    )
    (net (code "277") (name "Net-(IC307-O2)") (class "Default")
      (node (ref "IC307") (pin "15") (pinfunction "O2_15") (pintype "open_collector"))
      (node (ref "R328") (pin "1") (pinfunction "1_1") (pintype "passive"))
    )
    (net (code "278") (name "Net-(IC308A-+IN)") (class "Default")
      (node (ref "IC308") (pin "5") (pinfunction "+IN_5") (pintype "input"))
      (node (ref "R331") (pin "1") (pinfunction "1_1") (pintype "passive"))
      (node (ref "R332") (pin "2") (pinfunction "2_2") (pintype "passive"))
      (node (ref "R333") (pin "2") (pinfunction "2_2") (pintype "passive"))
    )
    (net (code "279") (name "Net-(IC308A--IN)") (class "Default")
      (node (ref "C308") (pin "1") (pinfunction "1_1") (pintype "passive"))
      (node (ref "IC308") (pin "4") (pinfunction "-IN_4") (pintype "input"))
      (node (ref "R330") (pin "1") (pinfunction "1_1") (pintype "passive"))
    )
    (net (code "280") (name "Net-(IC308B-+IN)") (class "Default")
      (node (ref "IC308") (pin "7") (pinfunction "+IN_7") (pintype "input"))
      (node (ref "R321") (pin "1") (pinfunction "1_1") (pintype "passive"))
      (node (ref "R322") (pin "1") (pinfunction "1_1") (pintype "passive"))
    )
    (net (code "281") (name "Net-(IC308B--IN)") (class "Default")
      (node (ref "IC308") (pin "6") (pinfunction "-IN_6") (pintype "input"))
      (node (ref "IC308") (pin "8") (pinfunction "-IN_8") (pintype "input"))
      (node (ref "R320") (pin "1") (pinfunction "1_1") (pintype "passive"))
    )
    (net (code "282") (name "Net-(IC308B-OUT)") (class "Default")
      (node (ref "IC308") (pin "1") (pinfunction "OUT_1") (pintype "open_collector"))
      (node (ref "R324") (pin "2") (pinfunction "2_2") (pintype "passive"))
      (node (ref "R325") (pin "2") (pinfunction "2_2") (pintype "passive"))
    )
    (net (code "283") (name "Net-(IC308C-+IN)") (class "Default")
      (node (ref "C305") (pin "1") (pinfunction "1_1") (pintype "passive"))
      (node (ref "IC308") (pin "9") (pinfunction "+IN_9") (pintype "input"))
      (node (ref "R322") (pin "2") (pinfunction "2_2") (pintype "passive"))
      (node (ref "R323") (pin "2") (pinfunction "2_2") (pintype "passive"))
    )
    (net (code "284") (name "Net-(IC308C-OUT)") (class "Default")
      (node (ref "C306") (pin "2") (pinfunction "2_2") (pintype "passive"))
      (node (ref "IC308") (pin "14") (pinfunction "OUT_14") (pintype "open_collector"))
      (node (ref "R326") (pin "2") (pinfunction "2_2") (pintype "passive"))
    )
    (net (code "285") (name "Net-(IC309-ADJ)") (class "Default")
      (node (ref "IC309") (pin "1") (pinfunction "ADJ_1") (pintype "input"))
      (node (ref "R320") (pin "2") (pinfunction "2_2") (pintype "passive"))
      (node (ref "R334") (pin "1") (pinfunction "1_1") (pintype "passive"))
      (node (ref "X301") (pin "7") (pinfunction "7_7") (pintype "passive"))
    )
    (net (code "286") (name "Net-(IC309-VI)") (class "Default")
      (node (ref "IC309") (pin "3") (pinfunction "VI_3") (pintype "input"))
      (node (ref "Q305") (pin "2") (pinfunction "C_2") (pintype "passive"))
    )
    (net (code "287") (name "Net-(IC309-VO)") (class "Default")
      (node (ref "IC309") (pin "2") (pinfunction "VO_2") (pintype "passive"))
      (node (ref "R334") (pin "2") (pinfunction "2_2") (pintype "passive"))
    )
    (net (code "288") (name "Net-(IC310-CV)") (class "Default")
      (node (ref "IC310") (pin "5") (pinfunction "CV_5") (pintype "input"))
      (node (ref "R344") (pin "2") (pinfunction "2_2") (pintype "passive"))
    )
    (net (code "289") (name "Net-(IC310-Q)") (class "Default")
      (node (ref "IC310") (pin "3") (pinfunction "Q_3") (pintype "output"))
      (node (ref "IC311") (pin "12") (pinfunction "A_12") (pintype "input"))
      (node (ref "R344") (pin "1") (pinfunction "1_1") (pintype "passive"))
    )
    (net (code "290") (name "Net-(IC311B-B)") (class "Default")
      (node (ref "IC311") (pin "11") (pinfunction "B_11") (pintype "input"))
      (node (ref "IC311") (pin "9") (pinfunction "~{Q}_9") (pintype "output"))
      (node (ref "R346") (pin "2") (pinfunction "2_2") (pintype "passive"))
    )
    (net (code "291") (name "Net-(IC311B-T2)") (class "Default")
      (node (ref "C310") (pin "1") (pinfunction "1_1") (pintype "passive"))
      (node (ref "IC311") (pin "14") (pinfunction "T2_14") (pintype "input"))
      (node (ref "R345") (pin "1") (pinfunction "1_1") (pintype "passive"))
    )
    (net (code "292") (name "Net-(IC401A-+IN)") (class "Default")
      (node (ref "C401") (pin "1") (pinfunction "1_1") (pintype "passive"))
      (node (ref "IC401") (pin "3") (pinfunction "+IN_3") (pintype "input"))
      (node (ref "R405") (pin "1") (pinfunction "1_1") (pintype "passive"))
    )
    (net (code "293") (name "Net-(IC401A--IN)") (class "Default")
      (node (ref "IC401") (pin "2") (pinfunction "-IN_2") (pintype "input"))
      (node (ref "R407") (pin "2") (pinfunction "2_2") (pintype "passive"))
    )
    (net (code "294") (name "Net-(IC401A-OUT)") (class "Default")
      (node (ref "IC401") (pin "1") (pinfunction "OUT_1") (pintype "output"))
      (node (ref "R408") (pin "2") (pinfunction "2_2") (pintype "passive"))
    )
    (net (code "295") (name "Net-(IC401B-+IN)") (class "Default")
      (node (ref "IC401") (pin "5") (pinfunction "+IN_5") (pintype "input"))
      (node (ref "R412") (pin "2") (pinfunction "2_2") (pintype "passive"))
      (node (ref "R417") (pin "2") (pinfunction "2_2") (pintype "passive"))
    )
    (net (code "296") (name "Net-(IC401B--IN)") (class "Default")
      (node (ref "IC401") (pin "6") (pinfunction "-IN_6") (pintype "input"))
      (node (ref "R413") (pin "1") (pinfunction "1_1") (pintype "passive"))
      (node (ref "R414") (pin "2") (pinfunction "2_2") (pintype "passive"))
    )
    (net (code "297") (name "Net-(IC401B-OUT)") (class "Default")
      (node (ref "IC401") (pin "7") (pinfunction "OUT_7") (pintype "output"))
      (node (ref "R416") (pin "1") (pinfunction "1_1") (pintype "passive"))
      (node (ref "R417") (pin "1") (pinfunction "1_1") (pintype "passive"))
    )
    (net (code "298") (name "Net-(IC405A-A)") (class "Default")
      (node (ref "IC405") (pin "10") (pinfunction "A_10") (pintype "input"))
      (node (ref "IC406") (pin "1") (pinfunction "D1_1") (pintype "passive"))
      (node (ref "R411") (pin "1") (pinfunction "1_1") (pintype "passive"))
      (node (ref "X401") (pin "4") (pinfunction "4_4") (pintype "passive"))
      (node (ref "X403") (pin "2") (pinfunction "S_2") (pintype "passive"))
    )
    (net (code "299") (name "Net-(IC405A-B)") (class "Default")
      (node (ref "IC405") (pin "13") (pinfunction "B_13") (pintype "input"))
      (node (ref "IC406") (pin "4") (pinfunction "D4_4") (pintype "passive"))
      (node (ref "R410") (pin "1") (pinfunction "1_1") (pintype "passive"))
      (node (ref "X401") (pin "3") (pinfunction "3_3") (pintype "passive"))
      (node (ref "X403") (pin "3") (pinfunction "S_3") (pintype "passive"))
    )
    (net (code "300") (name "Net-(IC405A-C)") (class "Default")
      (node (ref "IC405") (pin "12") (pinfunction "C_12") (pintype "input"))
      (node (ref "IC406") (pin "3") (pinfunction "D3_3") (pintype "passive"))
      (node (ref "R409") (pin "1") (pinfunction "1_1") (pintype "passive"))
      (node (ref "X401") (pin "2") (pinfunction "2_2") (pintype "passive"))
      (node (ref "X403") (pin "4") (pinfunction "S_4") (pintype "passive"))
    )
    (net (code "301") (name "Net-(IC405A-Q0)") (class "Default")
      (node (ref "IC405") (pin "3") (pinfunction "Q0_3") (pintype "output"))
      (node (ref "IC407") (pin "1") (pinfunction "I1_1") (pintype "input"))
      (node (ref "IC407") (pin "2") (pinfunction "I2_2") (pintype "input"))
      (node (ref "Q406") (pin "1") (pinfunction "G_1") (pintype "passive"))
    )
    (net (code "302") (name "Net-(IC405A-Q1)") (class "Default")
      (node (ref "IC405") (pin "14") (pinfunction "Q1_14") (pintype "output"))
      (node (ref "IC407") (pin "6") (pinfunction "I6_6") (pintype "input"))
    )
    (net (code "303") (name "Net-(IC405A-Q2)") (class "Default")
      (node (ref "IC405") (pin "2") (pinfunction "Q2_2") (pintype "output"))
      (node (ref "IC407") (pin "7") (pinfunction "I7_7") (pintype "input"))
    )
    (net (code "304") (name "Net-(IC405A-Q3)") (class "Default")
      (node (ref "IC405") (pin "15") (pinfunction "Q3_15") (pintype "output"))
      (node (ref "IC407") (pin "5") (pinfunction "I5_5") (pintype "input"))
    )
    (net (code "305") (name "Net-(IC405A-Q4)") (class "Default")
      (node (ref "IC405") (pin "1") (pinfunction "Q4_1") (pintype "output"))
      (node (ref "IC407") (pin "4") (pinfunction "I4_4") (pintype "input"))
    )
    (net (code "306") (name "Net-(IC405A-Q5)") (class "Default")
      (node (ref "IC405") (pin "6") (pinfunction "Q5_6") (pintype "output"))
      (node (ref "IC407") (pin "3") (pinfunction "I3_3") (pintype "input"))
    )
    (net (code "307") (name "Net-(IC407-O2)") (class "Default")
      (node (ref "IC407") (pin "15") (pinfunction "O2_15") (pintype "open_collector"))
      (node (ref "R428") (pin "1") (pinfunction "1_1") (pintype "passive"))
    )
    (net (code "308") (name "Net-(IC408A-+IN)") (class "Default")
      (node (ref "IC408") (pin "5") (pinfunction "+IN_5") (pintype "input"))
      (node (ref "R431") (pin "1") (pinfunction "1_1") (pintype "passive"))
      (node (ref "R432") (pin "2") (pinfunction "2_2") (pintype "passive"))
      (node (ref "R433") (pin "2") (pinfunction "2_2") (pintype "passive"))
    )
    (net (code "309") (name "Net-(IC408A--IN)") (class "Default")
      (node (ref "C408") (pin "1") (pinfunction "1_1") (pintype "passive"))
      (node (ref "IC408") (pin "4") (pinfunction "-IN_4") (pintype "input"))
      (node (ref "R430") (pin "1") (pinfunction "1_1") (pintype "passive"))
    )
    (net (code "310") (name "Net-(IC408B-+IN)") (class "Default")
      (node (ref "IC408") (pin "7") (pinfunction "+IN_7") (pintype "input"))
      (node (ref "R421") (pin "1") (pinfunction "1_1") (pintype "passive"))
      (node (ref "R422") (pin "1") (pinfunction "1_1") (pintype "passive"))
    )
    (net (code "311") (name "Net-(IC408B--IN)") (class "Default")
      (node (ref "IC408") (pin "6") (pinfunction "-IN_6") (pintype "input"))
      (node (ref "IC408") (pin "8") (pinfunction "-IN_8") (pintype "input"))
      (node (ref "R420") (pin "1") (pinfunction "1_1") (pintype "passive"))
    )
    (net (code "312") (name "Net-(IC408B-OUT)") (class "Default")
      (node (ref "IC408") (pin "1") (pinfunction "OUT_1") (pintype "open_collector"))
      (node (ref "R424") (pin "2") (pinfunction "2_2") (pintype "passive"))
      (node (ref "R425") (pin "2") (pinfunction "2_2") (pintype "passive"))
    )
    (net (code "313") (name "Net-(IC408C-+IN)") (class "Default")
      (node (ref "C405") (pin "1") (pinfunction "1_1") (pintype "passive"))
      (node (ref "IC408") (pin "9") (pinfunction "+IN_9") (pintype "input"))
      (node (ref "R422") (pin "2") (pinfunction "2_2") (pintype "passive"))
      (node (ref "R423") (pin "2") (pinfunction "2_2") (pintype "passive"))
    )
    (net (code "314") (name "Net-(IC408C-OUT)") (class "Default")
      (node (ref "C406") (pin "2") (pinfunction "2_2") (pintype "passive"))
      (node (ref "IC408") (pin "14") (pinfunction "OUT_14") (pintype "open_collector"))
      (node (ref "R426") (pin "2") (pinfunction "2_2") (pintype "passive"))
    )
    (net (code "315") (name "Net-(IC409-ADJ)") (class "Default")
      (node (ref "IC409") (pin "1") (pinfunction "ADJ_1") (pintype "input"))
      (node (ref "R420") (pin "2") (pinfunction "2_2") (pintype "passive"))
      (node (ref "R434") (pin "1") (pinfunction "1_1") (pintype "passive"))
      (node (ref "X401") (pin "7") (pinfunction "7_7") (pintype "passive"))
    )
    (net (code "316") (name "Net-(IC409-VI)") (class "Default")
      (node (ref "IC409") (pin "3") (pinfunction "VI_3") (pintype "input"))
      (node (ref "Q405") (pin "2") (pinfunction "C_2") (pintype "passive"))
    )
    (net (code "317") (name "Net-(IC409-VO)") (class "Default")
      (node (ref "IC409") (pin "2") (pinfunction "VO_2") (pintype "passive"))
      (node (ref "R434") (pin "2") (pinfunction "2_2") (pintype "passive"))
    )
    (net (code "318") (name "Net-(IC410-CV)") (class "Default")
      (node (ref "IC410") (pin "5") (pinfunction "CV_5") (pintype "input"))
      (node (ref "R444") (pin "2") (pinfunction "2_2") (pintype "passive"))
    )
    (net (code "319") (name "Net-(IC410-Q)") (class "Default")
      (node (ref "IC410") (pin "3") (pinfunction "Q_3") (pintype "output"))
      (node (ref "IC411") (pin "12") (pinfunction "A_12") (pintype "input"))
      (node (ref "R444") (pin "1") (pinfunction "1_1") (pintype "passive"))
    )
    (net (code "320") (name "Net-(IC411B-B)") (class "Default")
      (node (ref "IC411") (pin "11") (pinfunction "B_11") (pintype "input"))
      (node (ref "IC411") (pin "9") (pinfunction "~{Q}_9") (pintype "output"))
      (node (ref "R446") (pin "2") (pinfunction "2_2") (pintype "passive"))
    )
    (net (code "321") (name "Net-(IC411B-T2)") (class "Default")
      (node (ref "C410") (pin "1") (pinfunction "1_1") (pintype "passive"))
      (node (ref "IC411") (pin "14") (pinfunction "T2_14") (pintype "input"))
      (node (ref "R445") (pin "1") (pinfunction "1_1") (pintype "passive"))
    )
    (net (code "322") (name "Net-(IC501A-+IN)") (class "Default")
      (node (ref "C501") (pin "1") (pinfunction "1_1") (pintype "passive"))
      (node (ref "IC501") (pin "3") (pinfunction "+IN_3") (pintype "input"))
      (node (ref "R505") (pin "1") (pinfunction "1_1") (pintype "passive"))
    )
    (net (code "323") (name "Net-(IC501A--IN)") (class "Default")
      (node (ref "IC501") (pin "2") (pinfunction "-IN_2") (pintype "input"))
      (node (ref "R507") (pin "2") (pinfunction "2_2") (pintype "passive"))
    )
    (net (code "324") (name "Net-(IC501A-OUT)") (class "Default")
      (node (ref "IC501") (pin "1") (pinfunction "OUT_1") (pintype "output"))
      (node (ref "R508") (pin "2") (pinfunction "2_2") (pintype "passive"))
    )
    (net (code "325") (name "Net-(IC501B-+IN)") (class "Default")
      (node (ref "IC501") (pin "5") (pinfunction "+IN_5") (pintype "input"))
      (node (ref "R512") (pin "2") (pinfunction "2_2") (pintype "passive"))
      (node (ref "R517") (pin "2") (pinfunction "2_2") (pintype "passive"))
    )
    (net (code "326") (name "Net-(IC501B--IN)") (class "Default")
      (node (ref "IC501") (pin "6") (pinfunction "-IN_6") (pintype "input"))
      (node (ref "R513") (pin "1") (pinfunction "1_1") (pintype "passive"))
      (node (ref "R514") (pin "2") (pinfunction "2_2") (pintype "passive"))
    )
    (net (code "327") (name "Net-(IC501B-OUT)") (class "Default")
      (node (ref "IC501") (pin "7") (pinfunction "OUT_7") (pintype "output"))
      (node (ref "R516") (pin "1") (pinfunction "1_1") (pintype "passive"))
      (node (ref "R517") (pin "1") (pinfunction "1_1") (pintype "passive"))
    )
    (net (code "328") (name "Net-(IC505A-A)") (class "Default")
      (node (ref "IC505") (pin "10") (pinfunction "A_10") (pintype "input"))
      (node (ref "IC506") (pin "1") (pinfunction "D1_1") (pintype "passive"))
      (node (ref "R511") (pin "1") (pinfunction "1_1") (pintype "passive"))
      (node (ref "X501") (pin "4") (pinfunction "4_4") (pintype "passive"))
      (node (ref "X503") (pin "2") (pinfunction "S_2") (pintype "passive"))
    )
    (net (code "329") (name "Net-(IC505A-B)") (class "Default")
      (node (ref "IC505") (pin "13") (pinfunction "B_13") (pintype "input"))
      (node (ref "IC506") (pin "4") (pinfunction "D4_4") (pintype "passive"))
      (node (ref "R510") (pin "1") (pinfunction "1_1") (pintype "passive"))
      (node (ref "X501") (pin "3") (pinfunction "3_3") (pintype "passive"))
      (node (ref "X503") (pin "3") (pinfunction "S_3") (pintype "passive"))
    )
    (net (code "330") (name "Net-(IC505A-C)") (class "Default")
      (node (ref "IC505") (pin "12") (pinfunction "C_12") (pintype "input"))
      (node (ref "IC506") (pin "3") (pinfunction "D3_3") (pintype "passive"))
      (node (ref "R509") (pin "1") (pinfunction "1_1") (pintype "passive"))
      (node (ref "X501") (pin "2") (pinfunction "2_2") (pintype "passive"))
      (node (ref "X503") (pin "4") (pinfunction "S_4") (pintype "passive"))
    )
    (net (code "331") (name "Net-(IC505A-Q0)") (class "Default")
      (node (ref "IC505") (pin "3") (pinfunction "Q0_3") (pintype "output"))
      (node (ref "IC507") (pin "1") (pinfunction "I1_1") (pintype "input"))
      (node (ref "IC507") (pin "2") (pinfunction "I2_2") (pintype "input"))
      (node (ref "Q506") (pin "1") (pinfunction "G_1") (pintype "passive"))
    )
    (net (code "332") (name "Net-(IC505A-Q1)") (class "Default")
      (node (ref "IC505") (pin "14") (pinfunction "Q1_14") (pintype "output"))
      (node (ref "IC507") (pin "6") (pinfunction "I6_6") (pintype "input"))
    )
    (net (code "333") (name "Net-(IC505A-Q2)") (class "Default")
      (node (ref "IC505") (pin "2") (pinfunction "Q2_2") (pintype "output"))
      (node (ref "IC507") (pin "7") (pinfunction "I7_7") (pintype "input"))
    )
    (net (code "334") (name "Net-(IC505A-Q3)") (class "Default")
      (node (ref "IC505") (pin "15") (pinfunction "Q3_15") (pintype "output"))
      (node (ref "IC507") (pin "5") (pinfunction "I5_5") (pintype "input"))
    )
    (net (code "335") (name "Net-(IC505A-Q4)") (class "Default")
      (node (ref "IC505") (pin "1") (pinfunction "Q4_1") (pintype "output"))
      (node (ref "IC507") (pin "4") (pinfunction "I4_4") (pintype "input"))
    )
    (net (code "336") (name "Net-(IC505A-Q5)") (class "Default")
      (node (ref "IC505") (pin "6") (pinfunction "Q5_6") (pintype "output"))
      (node (ref "IC507") (pin "3") (pinfunction "I3_3") (pintype "input"))
    )
    (net (code "337") (name "Net-(IC507-O2)") (class "Default")
      (node (ref "IC507") (pin "15") (pinfunction "O2_15") (pintype "open_collector"))
      (node (ref "R528") (pin "1") (pinfunction "1_1") (pintype "passive"))
    )
    (net (code "338") (name "Net-(IC508A-+IN)") (class "Default")
      (node (ref "IC508") (pin "5") (pinfunction "+IN_5") (pintype "input"))
      (node (ref "R531") (pin "1") (pinfunction "1_1") (pintype "passive"))
      (node (ref "R532") (pin "2") (pinfunction "2_2") (pintype "passive"))
      (node (ref "R533") (pin "2") (pinfunction "2_2") (pintype "passive"))
    )
    (net (code "339") (name "Net-(IC508A--IN)") (class "Default")
      (node (ref "C508") (pin "1") (pinfunction "1_1") (pintype "passive"))
      (node (ref "IC508") (pin "4") (pinfunction "-IN_4") (pintype "input"))
      (node (ref "R530") (pin "1") (pinfunction "1_1") (pintype "passive"))
    )
    (net (code "340") (name "Net-(IC508B-+IN)") (class "Default")
      (node (ref "IC508") (pin "7") (pinfunction "+IN_7") (pintype "input"))
      (node (ref "R521") (pin "1") (pinfunction "1_1") (pintype "passive"))
      (node (ref "R522") (pin "1") (pinfunction "1_1") (pintype "passive"))
    )
    (net (code "341") (name "Net-(IC508B--IN)") (class "Default")
      (node (ref "IC508") (pin "6") (pinfunction "-IN_6") (pintype "input"))
      (node (ref "IC508") (pin "8") (pinfunction "-IN_8") (pintype "input"))
      (node (ref "R520") (pin "1") (pinfunction "1_1") (pintype "passive"))
    )
    (net (code "342") (name "Net-(IC508B-OUT)") (class "Default")
      (node (ref "IC508") (pin "1") (pinfunction "OUT_1") (pintype "open_collector"))
      (node (ref "R524") (pin "2") (pinfunction "2_2") (pintype "passive"))
      (node (ref "R525") (pin "2") (pinfunction "2_2") (pintype "passive"))
    )
    (net (code "343") (name "Net-(IC508C-+IN)") (class "Default")
      (node (ref "C505") (pin "1") (pinfunction "1_1") (pintype "passive"))
      (node (ref "IC508") (pin "9") (pinfunction "+IN_9") (pintype "input"))
      (node (ref "R522") (pin "2") (pinfunction "2_2") (pintype "passive"))
      (node (ref "R523") (pin "2") (pinfunction "2_2") (pintype "passive"))
    )
    (net (code "344") (name "Net-(IC508C-OUT)") (class "Default")
      (node (ref "C506") (pin "2") (pinfunction "2_2") (pintype "passive"))
      (node (ref "IC508") (pin "14") (pinfunction "OUT_14") (pintype "open_collector"))
      (node (ref "R526") (pin "2") (pinfunction "2_2") (pintype "passive"))
    )
    (net (code "345") (name "Net-(IC509-ADJ)") (class "Default")
      (node (ref "IC509") (pin "1") (pinfunction "ADJ_1") (pintype "input"))
      (node (ref "R520") (pin "2") (pinfunction "2_2") (pintype "passive"))
      (node (ref "R534") (pin "1") (pinfunction "1_1") (pintype "passive"))
      (node (ref "X501") (pin "7") (pinfunction "7_7") (pintype "passive"))
    )
    (net (code "346") (name "Net-(IC509-VI)") (class "Default")
      (node (ref "IC509") (pin "3") (pinfunction "VI_3") (pintype "input"))
      (node (ref "Q505") (pin "2") (pinfunction "C_2") (pintype "passive"))
    )
    (net (code "347") (name "Net-(IC509-VO)") (class "Default")
      (node (ref "IC509") (pin "2") (pinfunction "VO_2") (pintype "passive"))
      (node (ref "R534") (pin "2") (pinfunction "2_2") (pintype "passive"))
    )
    (net (code "348") (name "Net-(IC510-CV)") (class "Default")
      (node (ref "IC510") (pin "5") (pinfunction "CV_5") (pintype "input"))
      (node (ref "R544") (pin "2") (pinfunction "2_2") (pintype "passive"))
    )
    (net (code "349") (name "Net-(IC510-Q)") (class "Default")
      (node (ref "IC510") (pin "3") (pinfunction "Q_3") (pintype "output"))
      (node (ref "IC511") (pin "12") (pinfunction "A_12") (pintype "input"))
      (node (ref "R544") (pin "1") (pinfunction "1_1") (pintype "passive"))
    )
    (net (code "350") (name "Net-(IC511B-B)") (class "Default")
      (node (ref "IC511") (pin "11") (pinfunction "B_11") (pintype "input"))
      (node (ref "IC511") (pin "9") (pinfunction "~{Q}_9") (pintype "output"))
      (node (ref "R546") (pin "2") (pinfunction "2_2") (pintype "passive"))
    )
    (net (code "351") (name "Net-(IC511B-T2)") (class "Default")
      (node (ref "C510") (pin "1") (pinfunction "1_1") (pintype "passive"))
      (node (ref "IC511") (pin "14") (pinfunction "T2_14") (pintype "input"))
      (node (ref "R545") (pin "1") (pinfunction "1_1") (pintype "passive"))
    )
    (net (code "352") (name "Net-(IC601A-+IN)") (class "Default")
      (node (ref "C601") (pin "1") (pinfunction "1_1") (pintype "passive"))
      (node (ref "IC601") (pin "3") (pinfunction "+IN_3") (pintype "input"))
      (node (ref "R605") (pin "1") (pinfunction "1_1") (pintype "passive"))
    )
    (net (code "353") (name "Net-(IC601A--IN)") (class "Default")
      (node (ref "IC601") (pin "2") (pinfunction "-IN_2") (pintype "input"))
      (node (ref "R607") (pin "2") (pinfunction "2_2") (pintype "passive"))
    )
    (net (code "354") (name "Net-(IC601A-OUT)") (class "Default")
      (node (ref "IC601") (pin "1") (pinfunction "OUT_1") (pintype "output"))
      (node (ref "R608") (pin "2") (pinfunction "2_2") (pintype "passive"))
    )
    (net (code "355") (name "Net-(IC601B-+IN)") (class "Default")
      (node (ref "IC601") (pin "5") (pinfunction "+IN_5") (pintype "input"))
      (node (ref "R612") (pin "2") (pinfunction "2_2") (pintype "passive"))
      (node (ref "R617") (pin "2") (pinfunction "2_2") (pintype "passive"))
    )
    (net (code "356") (name "Net-(IC601B--IN)") (class "Default")
      (node (ref "IC601") (pin "6") (pinfunction "-IN_6") (pintype "input"))
      (node (ref "R613") (pin "1") (pinfunction "1_1") (pintype "passive"))
      (node (ref "R614") (pin "2") (pinfunction "2_2") (pintype "passive"))
    )
    (net (code "357") (name "Net-(IC601B-OUT)") (class "Default")
      (node (ref "IC601") (pin "7") (pinfunction "OUT_7") (pintype "output"))
      (node (ref "R616") (pin "1") (pinfunction "1_1") (pintype "passive"))
      (node (ref "R617") (pin "1") (pinfunction "1_1") (pintype "passive"))
    )
    (net (code "358") (name "Net-(IC605A-A)") (class "Default")
      (node (ref "IC605") (pin "10") (pinfunction "A_10") (pintype "input"))
      (node (ref "IC606") (pin "1") (pinfunction "D1_1") (pintype "passive"))
      (node (ref "R611") (pin "1") (pinfunction "1_1") (pintype "passive"))
      (node (ref "X601") (pin "4") (pinfunction "4_4") (pintype "passive"))
      (node (ref "X603") (pin "2") (pinfunction "S_2") (pintype "passive"))
    )
    (net (code "359") (name "Net-(IC605A-B)") (class "Default")
      (node (ref "IC605") (pin "13") (pinfunction "B_13") (pintype "input"))
      (node (ref "IC606") (pin "4") (pinfunction "D4_4") (pintype "passive"))
      (node (ref "R610") (pin "1") (pinfunction "1_1") (pintype "passive"))
      (node (ref "X601") (pin "3") (pinfunction "3_3") (pintype "passive"))
      (node (ref "X603") (pin "3") (pinfunction "S_3") (pintype "passive"))
    )
    (net (code "360") (name "Net-(IC605A-C)") (class "Default")
      (node (ref "IC605") (pin "12") (pinfunction "C_12") (pintype "input"))
      (node (ref "IC606") (pin "3") (pinfunction "D3_3") (pintype "passive"))
      (node (ref "R609") (pin "1") (pinfunction "1_1") (pintype "passive"))
      (node (ref "X601") (pin "2") (pinfunction "2_2") (pintype "passive"))
      (node (ref "X603") (pin "4") (pinfunction "S_4") (pintype "passive"))
    )
    (net (code "361") (name "Net-(IC605A-Q0)") (class "Default")
      (node (ref "IC605") (pin "3") (pinfunction "Q0_3") (pintype "output"))
      (node (ref "IC607") (pin "1") (pinfunction "I1_1") (pintype "input"))
      (node (ref "IC607") (pin "2") (pinfunction "I2_2") (pintype "input"))
      (node (ref "Q606") (pin "1") (pinfunction "G_1") (pintype "passive"))
    )
    (net (code "362") (name "Net-(IC605A-Q1)") (class "Default")
      (node (ref "IC605") (pin "14") (pinfunction "Q1_14") (pintype "output"))
      (node (ref "IC607") (pin "6") (pinfunction "I6_6") (pintype "input"))
    )
    (net (code "363") (name "Net-(IC605A-Q2)") (class "Default")
      (node (ref "IC605") (pin "2") (pinfunction "Q2_2") (pintype "output"))
      (node (ref "IC607") (pin "7") (pinfunction "I7_7") (pintype "input"))
    )
    (net (code "364") (name "Net-(IC605A-Q3)") (class "Default")
      (node (ref "IC605") (pin "15") (pinfunction "Q3_15") (pintype "output"))
      (node (ref "IC607") (pin "5") (pinfunction "I5_5") (pintype "input"))
    )
    (net (code "365") (name "Net-(IC605A-Q4)") (class "Default")
      (node (ref "IC605") (pin "1") (pinfunction "Q4_1") (pintype "output"))
      (node (ref "IC607") (pin "4") (pinfunction "I4_4") (pintype "input"))
    )
    (net (code "366") (name "Net-(IC605A-Q5)") (class "Default")
      (node (ref "IC605") (pin "6") (pinfunction "Q5_6") (pintype "output"))
      (node (ref "IC607") (pin "3") (pinfunction "I3_3") (pintype "input"))
    )
    (net (code "367") (name "Net-(IC607-O2)") (class "Default")
      (node (ref "IC607") (pin "15") (pinfunction "O2_15") (pintype "open_collector"))
      (node (ref "R628") (pin "1") (pinfunction "1_1") (pintype "passive"))
    )
    (net (code "368") (name "Net-(IC608A-+IN)") (class "Default")
      (node (ref "IC608") (pin "5") (pinfunction "+IN_5") (pintype "input"))
      (node (ref "R631") (pin "1") (pinfunction "1_1") (pintype "passive"))
      (node (ref "R632") (pin "2") (pinfunction "2_2") (pintype "passive"))
      (node (ref "R633") (pin "2") (pinfunction "2_2") (pintype "passive"))
    )
    (net (code "369") (name "Net-(IC608A--IN)") (class "Default")
      (node (ref "C608") (pin "1") (pinfunction "1_1") (pintype "passive"))
      (node (ref "IC608") (pin "4") (pinfunction "-IN_4") (pintype "input"))
      (node (ref "R630") (pin "1") (pinfunction "1_1") (pintype "passive"))
    )
    (net (code "370") (name "Net-(IC608B-+IN)") (class "Default")
      (node (ref "IC608") (pin "7") (pinfunction "+IN_7") (pintype "input"))
      (node (ref "R621") (pin "1") (pinfunction "1_1") (pintype "passive"))
      (node (ref "R622") (pin "1") (pinfunction "1_1") (pintype "passive"))
    )
    (net (code "371") (name "Net-(IC608B--IN)") (class "Default")
      (node (ref "IC608") (pin "6") (pinfunction "-IN_6") (pintype "input"))
      (node (ref "IC608") (pin "8") (pinfunction "-IN_8") (pintype "input"))
      (node (ref "R620") (pin "1") (pinfunction "1_1") (pintype "passive"))
    )
    (net (code "372") (name "Net-(IC608B-OUT)") (class "Default")
      (node (ref "IC608") (pin "1") (pinfunction "OUT_1") (pintype "open_collector"))
      (node (ref "R624") (pin "2") (pinfunction "2_2") (pintype "passive"))
      (node (ref "R625") (pin "2") (pinfunction "2_2") (pintype "passive"))
    )
    (net (code "373") (name "Net-(IC608C-+IN)") (class "Default")
      (node (ref "C605") (pin "1") (pinfunction "1_1") (pintype "passive"))
      (node (ref "IC608") (pin "9") (pinfunction "+IN_9") (pintype "input"))
      (node (ref "R622") (pin "2") (pinfunction "2_2") (pintype "passive"))
      (node (ref "R623") (pin "2") (pinfunction "2_2") (pintype "passive"))
    )
    (net (code "374") (name "Net-(IC608C-OUT)") (class "Default")
      (node (ref "C606") (pin "2") (pinfunction "2_2") (pintype "passive"))
      (node (ref "IC608") (pin "14") (pinfunction "OUT_14") (pintype "open_collector"))
      (node (ref "R626") (pin "2") (pinfunction "2_2") (pintype "passive"))
    )
    (net (code "375") (name "Net-(IC609-ADJ)") (class "Default")
      (node (ref "IC609") (pin "1") (pinfunction "ADJ_1") (pintype "input"))
      (node (ref "R620") (pin "2") (pinfunction "2_2") (pintype "passive"))
      (node (ref "R634") (pin "1") (pinfunction "1_1") (pintype "passive"))
      (node (ref "X601") (pin "7") (pinfunction "7_7") (pintype "passive"))
    )
    (net (code "376") (name "Net-(IC609-VI)") (class "Default")
      (node (ref "IC609") (pin "3") (pinfunction "VI_3") (pintype "input"))
      (node (ref "Q605") (pin "2") (pinfunction "C_2") (pintype "passive"))
    )
    (net (code "377") (name "Net-(IC609-VO)") (class "Default")
      (node (ref "IC609") (pin "2") (pinfunction "VO_2") (pintype "passive"))
      (node (ref "R634") (pin "2") (pinfunction "2_2") (pintype "passive"))
    )
    (net (code "378") (name "Net-(IC610-CV)") (class "Default")
      (node (ref "IC610") (pin "5") (pinfunction "CV_5") (pintype "input"))
      (node (ref "R644") (pin "2") (pinfunction "2_2") (pintype "passive"))
    )
    (net (code "379") (name "Net-(IC610-Q)") (class "Default")
      (node (ref "IC610") (pin "3") (pinfunction "Q_3") (pintype "output"))
      (node (ref "IC611") (pin "12") (pinfunction "A_12") (pintype "input"))
      (node (ref "R644") (pin "1") (pinfunction "1_1") (pintype "passive"))
    )
    (net (code "380") (name "Net-(IC611B-B)") (class "Default")
      (node (ref "IC611") (pin "11") (pinfunction "B_11") (pintype "input"))
      (node (ref "IC611") (pin "9") (pinfunction "~{Q}_9") (pintype "output"))
      (node (ref "R646") (pin "2") (pinfunction "2_2") (pintype "passive"))
    )
    (net (code "381") (name "Net-(IC611B-T2)") (class "Default")
      (node (ref "C610") (pin "1") (pinfunction "1_1") (pintype "passive"))
      (node (ref "IC611") (pin "14") (pinfunction "T2_14") (pintype "input"))
      (node (ref "R645") (pin "1") (pinfunction "1_1") (pintype "passive"))
    )
    (net (code "382") (name "Net-(JP101-Pad1)") (class "Default")
      (node (ref "JP101") (pin "1") (pinfunction "1_1") (pintype "passive"))
      (node (ref "R119") (pin "2") (pinfunction "2_2") (pintype "passive"))
    )
    (net (code "383") (name "Net-(JP104-Pad2)") (class "Default")
      (node (ref "JP104") (pin "2") (pinfunction "2_2") (pintype "passive"))
      (node (ref "R136") (pin "2") (pinfunction "2_2") (pintype "passive"))
      (node (ref "R137") (pin "2") (pinfunction "2_2") (pintype "passive"))
      (node (ref "SJ101") (pin "2") (pinfunction "2_2") (pintype "passive"))
    )
    (net (code "384") (name "Net-(JP105-Pad3)") (class "Default")
      (node (ref "JP105") (pin "3") (pinfunction "3_3") (pintype "passive"))
      (node (ref "R138") (pin "1") (pinfunction "1_1") (pintype "passive"))
      (node (ref "R139") (pin "1") (pinfunction "1_1") (pintype "passive"))
    )
    (net (code "385") (name "Net-(JP201-Pad1)") (class "Default")
      (node (ref "JP201") (pin "1") (pinfunction "1_1") (pintype "passive"))
      (node (ref "R219") (pin "2") (pinfunction "2_2") (pintype "passive"))
    )
    (net (code "386") (name "Net-(JP204-Pad2)") (class "Default")
      (node (ref "JP204") (pin "2") (pinfunction "2_2") (pintype "passive"))
      (node (ref "R236") (pin "2") (pinfunction "2_2") (pintype "passive"))
      (node (ref "R237") (pin "2") (pinfunction "2_2") (pintype "passive"))
      (node (ref "SJ201") (pin "2") (pinfunction "2_2") (pintype "passive"))
    )
    (net (code "387") (name "Net-(JP205-Pad3)") (class "Default")
      (node (ref "JP205") (pin "3") (pinfunction "3_3") (pintype "passive"))
      (node (ref "R238") (pin "1") (pinfunction "1_1") (pintype "passive"))
      (node (ref "R239") (pin "1") (pinfunction "1_1") (pintype "passive"))
    )
    (net (code "388") (name "Net-(JP301-Pad1)") (class "Default")
      (node (ref "JP301") (pin "1") (pinfunction "1_1") (pintype "passive"))
      (node (ref "R319") (pin "2") (pinfunction "2_2") (pintype "passive"))
    )
    (net (code "389") (name "Net-(JP304-Pad2)") (class "Default")
      (node (ref "JP304") (pin "2") (pinfunction "2_2") (pintype "passive"))
      (node (ref "R336") (pin "2") (pinfunction "2_2") (pintype "passive"))
      (node (ref "R337") (pin "2") (pinfunction "2_2") (pintype "passive"))
      (node (ref "SJ301") (pin "2") (pinfunction "2_2") (pintype "passive"))
    )
    (net (code "390") (name "Net-(JP305-Pad3)") (class "Default")
      (node (ref "JP305") (pin "3") (pinfunction "3_3") (pintype "passive"))
      (node (ref "R338") (pin "1") (pinfunction "1_1") (pintype "passive"))
      (node (ref "R339") (pin "1") (pinfunction "1_1") (pintype "passive"))
    )
    (net (code "391") (name "Net-(JP401-Pad1)") (class "Default")
      (node (ref "JP401") (pin "1") (pinfunction "1_1") (pintype "passive"))
      (node (ref "R419") (pin "2") (pinfunction "2_2") (pintype "passive"))
    )
    (net (code "392") (name "Net-(JP404-Pad2)") (class "Default")
      (node (ref "JP404") (pin "2") (pinfunction "2_2") (pintype "passive"))
      (node (ref "R436") (pin "2") (pinfunction "2_2") (pintype "passive"))
      (node (ref "R437") (pin "2") (pinfunction "2_2") (pintype "passive"))
      (node (ref "SJ401") (pin "2") (pinfunction "2_2") (pintype "passive"))
    )
    (net (code "393") (name "Net-(JP405-Pad3)") (class "Default")
      (node (ref "JP405") (pin "3") (pinfunction "3_3") (pintype "passive"))
      (node (ref "R438") (pin "1") (pinfunction "1_1") (pintype "passive"))
      (node (ref "R439") (pin "1") (pinfunction "1_1") (pintype "passive"))
    )
    (net (code "394") (name "Net-(JP501-Pad1)") (class "Default")
      (node (ref "JP501") (pin "1") (pinfunction "1_1") (pintype "passive"))
      (node (ref "R519") (pin "2") (pinfunction "2_2") (pintype "passive"))
    )
    (net (code "395") (name "Net-(JP504-Pad2)") (class "Default")
      (node (ref "JP504") (pin "2") (pinfunction "2_2") (pintype "passive"))
      (node (ref "R536") (pin "2") (pinfunction "2_2") (pintype "passive"))
      (node (ref "R537") (pin "2") (pinfunction "2_2") (pintype "passive"))
      (node (ref "SJ501") (pin "2") (pinfunction "2_2") (pintype "passive"))
    )
    (net (code "396") (name "Net-(JP505-Pad3)") (class "Default")
      (node (ref "JP505") (pin "3") (pinfunction "3_3") (pintype "passive"))
      (node (ref "R538") (pin "1") (pinfunction "1_1") (pintype "passive"))
      (node (ref "R539") (pin "1") (pinfunction "1_1") (pintype "passive"))
    )
    (net (code "397") (name "Net-(JP601-Pad1)") (class "Default")
      (node (ref "JP601") (pin "1") (pinfunction "1_1") (pintype "passive"))
      (node (ref "R619") (pin "2") (pinfunction "2_2") (pintype "passive"))
    )
    (net (code "398") (name "Net-(JP604-Pad2)") (class "Default")
      (node (ref "JP604") (pin "2") (pinfunction "2_2") (pintype "passive"))
      (node (ref "R636") (pin "2") (pinfunction "2_2") (pintype "passive"))
      (node (ref "R637") (pin "2") (pinfunction "2_2") (pintype "passive"))
      (node (ref "SJ601") (pin "2") (pinfunction "2_2") (pintype "passive"))
    )
    (net (code "399") (name "Net-(JP605-Pad3)") (class "Default")
      (node (ref "JP605") (pin "3") (pinfunction "3_3") (pintype "passive"))
      (node (ref "R638") (pin "1") (pinfunction "1_1") (pintype "passive"))
      (node (ref "R639") (pin "1") (pinfunction "1_1") (pintype "passive"))
    )
    (net (code "400") (name "Net-(LED101-C)") (class "Default")
      (node (ref "LED101") (pin "K") (pinfunction "C_K") (pintype "passive"))
      (node (ref "R143") (pin "1") (pinfunction "1_1") (pintype "passive"))
    )
    (net (code "401") (name "Net-(LED102-PadA)") (class "Default")
      (node (ref "LED102") (pin "A") (pinfunction "A_A") (pintype "passive"))
      (node (ref "LED103") (pin "A") (pinfunction "A_A") (pintype "passive"))
      (node (ref "LED104") (pin "A") (pinfunction "A_A") (pintype "passive"))
      (node (ref "LED105") (pin "A") (pinfunction "A_A") (pintype "passive"))
      (node (ref "LED106") (pin "A") (pinfunction "A_A") (pintype "passive"))
      (node (ref "R142") (pin "1") (pinfunction "1_1") (pintype "passive"))
    )
    (net (code "402") (name "Net-(LED201-C)") (class "Default")
      (node (ref "LED201") (pin "K") (pinfunction "C_K") (pintype "passive"))
      (node (ref "R243") (pin "1") (pinfunction "1_1") (pintype "passive"))
    )
    (net (code "403") (name "Net-(LED202-PadA)") (class "Default")
      (node (ref "LED202") (pin "A") (pinfunction "A_A") (pintype "passive"))
      (node (ref "LED203") (pin "A") (pinfunction "A_A") (pintype "passive"))
      (node (ref "LED204") (pin "A") (pinfunction "A_A") (pintype "passive"))
      (node (ref "LED205") (pin "A") (pinfunction "A_A") (pintype "passive"))
      (node (ref "LED206") (pin "A") (pinfunction "A_A") (pintype "passive"))
      (node (ref "R242") (pin "1") (pinfunction "1_1") (pintype "passive"))
    )
    (net (code "404") (name "Net-(LED301-C)") (class "Default")
      (node (ref "LED301") (pin "K") (pinfunction "C_K") (pintype "passive"))
      (node (ref "R343") (pin "1") (pinfunction "1_1") (pintype "passive"))
    )
    (net (code "405") (name "Net-(LED302-PadA)") (class "Default")
      (node (ref "LED302") (pin "A") (pinfunction "A_A") (pintype "passive"))
      (node (ref "LED303") (pin "A") (pinfunction "A_A") (pintype "passive"))
      (node (ref "LED304") (pin "A") (pinfunction "A_A") (pintype "passive"))
      (node (ref "LED305") (pin "A") (pinfunction "A_A") (pintype "passive"))
      (node (ref "LED306") (pin "A") (pinfunction "A_A") (pintype "passive"))
      (node (ref "R342") (pin "1") (pinfunction "1_1") (pintype "passive"))
    )
    (net (code "406") (name "Net-(LED401-C)") (class "Default")
      (node (ref "LED401") (pin "K") (pinfunction "C_K") (pintype "passive"))
      (node (ref "R443") (pin "1") (pinfunction "1_1") (pintype "passive"))
    )
    (net (code "407") (name "Net-(LED402-PadA)") (class "Default")
      (node (ref "LED402") (pin "A") (pinfunction "A_A") (pintype "passive"))
      (node (ref "LED403") (pin "A") (pinfunction "A_A") (pintype "passive"))
      (node (ref "LED404") (pin "A") (pinfunction "A_A") (pintype "passive"))
      (node (ref "LED405") (pin "A") (pinfunction "A_A") (pintype "passive"))
      (node (ref "LED406") (pin "A") (pinfunction "A_A") (pintype "passive"))
      (node (ref "R442") (pin "1") (pinfunction "1_1") (pintype "passive"))
    )
    (net (code "408") (name "Net-(LED501-C)") (class "Default")
      (node (ref "LED501") (pin "K") (pinfunction "C_K") (pintype "passive"))
      (node (ref "R543") (pin "1") (pinfunction "1_1") (pintype "passive"))
    )
    (net (code "409") (name "Net-(LED502-PadA)") (class "Default")
      (node (ref "LED502") (pin "A") (pinfunction "A_A") (pintype "passive"))
      (node (ref "LED503") (pin "A") (pinfunction "A_A") (pintype "passive"))
      (node (ref "LED504") (pin "A") (pinfunction "A_A") (pintype "passive"))
      (node (ref "LED505") (pin "A") (pinfunction "A_A") (pintype "passive"))
      (node (ref "LED506") (pin "A") (pinfunction "A_A") (pintype "passive"))
      (node (ref "R542") (pin "1") (pinfunction "1_1") (pintype "passive"))
    )
    (net (code "410") (name "Net-(LED601-C)") (class "Default")
      (node (ref "LED601") (pin "K") (pinfunction "C_K") (pintype "passive"))
      (node (ref "R643") (pin "1") (pinfunction "1_1") (pintype "passive"))
    )
    (net (code "411") (name "Net-(LED602-PadA)") (class "Default")
      (node (ref "LED602") (pin "A") (pinfunction "A_A") (pintype "passive"))
      (node (ref "LED603") (pin "A") (pinfunction "A_A") (pintype "passive"))
      (node (ref "LED604") (pin "A") (pinfunction "A_A") (pintype "passive"))
      (node (ref "LED605") (pin "A") (pinfunction "A_A") (pintype "passive"))
      (node (ref "LED606") (pin "A") (pinfunction "A_A") (pintype "passive"))
      (node (ref "R642") (pin "1") (pinfunction "1_1") (pintype "passive"))
    )
    (net (code "412") (name "Net-(Q101-B)") (class "Default")
      (node (ref "Q101") (pin "1") (pinfunction "B_1") (pintype "passive"))
      (node (ref "Q102") (pin "1") (pinfunction "B_1") (pintype "passive"))
      (node (ref "Q102") (pin "2") (pinfunction "C_2") (pintype "passive"))
      (node (ref "R101") (pin "1") (pinfunction "1_1") (pintype "passive"))
      (node (ref "R103") (pin "1") (pinfunction "1_1") (pintype "passive"))
      (node (ref "R104") (pin "1") (pinfunction "1_1") (pintype "passive"))
      (node (ref "X102") (pin "2") (pinfunction "S_2") (pintype "passive"))
    )
    (net (code "413") (name "Net-(Q101-E)") (class "Default")
      (node (ref "Q101") (pin "3") (pinfunction "E_3") (pintype "passive"))
      (node (ref "R102") (pin "2") (pinfunction "2_2") (pintype "passive"))
    )
    (net (code "414") (name "Net-(Q102-E)") (class "Default")
      (node (ref "Q102") (pin "3") (pinfunction "E_3") (pintype "passive"))
      (node (ref "R106") (pin "2") (pinfunction "2_2") (pintype "passive"))
    )
    (net (code "415") (name "Net-(Q103-B)") (class "Default")
      (node (ref "Q103") (pin "1") (pinfunction "B_1") (pintype "passive"))
      (node (ref "R116") (pin "2") (pinfunction "2_2") (pintype "passive"))
    )
    (net (code "416") (name "Net-(Q103-C)") (class "Default")
      (node (ref "Q103") (pin "2") (pinfunction "C_2") (pintype "passive"))
      (node (ref "R115") (pin "2") (pinfunction "2_2") (pintype "passive"))
      (node (ref "R118") (pin "1") (pinfunction "1_1") (pintype "passive"))
    )
    (net (code "417") (name "Net-(Q104-B)") (class "Default")
      (node (ref "Q104") (pin "1") (pinfunction "B_1") (pintype "passive"))
      (node (ref "R128") (pin "2") (pinfunction "2_2") (pintype "passive"))
    )
    (net (code "418") (name "Net-(Q105-B)") (class "Default")
      (node (ref "Q105") (pin "1") (pinfunction "B_1") (pintype "passive"))
      (node (ref "R126") (pin "1") (pinfunction "1_1") (pintype "passive"))
    )
    (net (code "419") (name "Net-(Q107-D)") (class "Default")
      (node (ref "Q107") (pin "3") (pinfunction "D_3") (pintype "passive"))
      (node (ref "R138") (pin "2") (pinfunction "2_2") (pintype "passive"))
    )
    (net (code "420") (name "Net-(Q201-B)") (class "Default")
      (node (ref "Q201") (pin "1") (pinfunction "B_1") (pintype "passive"))
      (node (ref "Q202") (pin "1") (pinfunction "B_1") (pintype "passive"))
      (node (ref "Q202") (pin "2") (pinfunction "C_2") (pintype "passive"))
      (node (ref "R201") (pin "1") (pinfunction "1_1") (pintype "passive"))
      (node (ref "R203") (pin "1") (pinfunction "1_1") (pintype "passive"))
      (node (ref "R204") (pin "1") (pinfunction "1_1") (pintype "passive"))
      (node (ref "X202") (pin "2") (pinfunction "S_2") (pintype "passive"))
    )
    (net (code "421") (name "Net-(Q201-E)") (class "Default")
      (node (ref "Q201") (pin "3") (pinfunction "E_3") (pintype "passive"))
      (node (ref "R202") (pin "2") (pinfunction "2_2") (pintype "passive"))
    )
    (net (code "422") (name "Net-(Q202-E)") (class "Default")
      (node (ref "Q202") (pin "3") (pinfunction "E_3") (pintype "passive"))
      (node (ref "R206") (pin "2") (pinfunction "2_2") (pintype "passive"))
    )
    (net (code "423") (name "Net-(Q203-B)") (class "Default")
      (node (ref "Q203") (pin "1") (pinfunction "B_1") (pintype "passive"))
      (node (ref "R216") (pin "2") (pinfunction "2_2") (pintype "passive"))
    )
    (net (code "424") (name "Net-(Q203-C)") (class "Default")
      (node (ref "Q203") (pin "2") (pinfunction "C_2") (pintype "passive"))
      (node (ref "R215") (pin "2") (pinfunction "2_2") (pintype "passive"))
      (node (ref "R218") (pin "1") (pinfunction "1_1") (pintype "passive"))
    )
    (net (code "425") (name "Net-(Q204-B)") (class "Default")
      (node (ref "Q204") (pin "1") (pinfunction "B_1") (pintype "passive"))
      (node (ref "R228") (pin "2") (pinfunction "2_2") (pintype "passive"))
    )
    (net (code "426") (name "Net-(Q205-B)") (class "Default")
      (node (ref "Q205") (pin "1") (pinfunction "B_1") (pintype "passive"))
      (node (ref "R226") (pin "1") (pinfunction "1_1") (pintype "passive"))
    )
    (net (code "427") (name "Net-(Q207-D)") (class "Default")
      (node (ref "Q207") (pin "3") (pinfunction "D_3") (pintype "passive"))
      (node (ref "R238") (pin "2") (pinfunction "2_2") (pintype "passive"))
    )
    (net (code "428") (name "Net-(Q301-B)") (class "Default")
      (node (ref "Q301") (pin "1") (pinfunction "B_1") (pintype "passive"))
      (node (ref "Q302") (pin "1") (pinfunction "B_1") (pintype "passive"))
      (node (ref "Q302") (pin "2") (pinfunction "C_2") (pintype "passive"))
      (node (ref "R301") (pin "1") (pinfunction "1_1") (pintype "passive"))
      (node (ref "R303") (pin "1") (pinfunction "1_1") (pintype "passive"))
      (node (ref "R304") (pin "1") (pinfunction "1_1") (pintype "passive"))
      (node (ref "X302") (pin "2") (pinfunction "S_2") (pintype "passive"))
    )
    (net (code "429") (name "Net-(Q301-E)") (class "Default")
      (node (ref "Q301") (pin "3") (pinfunction "E_3") (pintype "passive"))
      (node (ref "R302") (pin "2") (pinfunction "2_2") (pintype "passive"))
    )
    (net (code "430") (name "Net-(Q302-E)") (class "Default")
      (node (ref "Q302") (pin "3") (pinfunction "E_3") (pintype "passive"))
      (node (ref "R306") (pin "2") (pinfunction "2_2") (pintype "passive"))
    )
    (net (code "431") (name "Net-(Q303-B)") (class "Default")
      (node (ref "Q303") (pin "1") (pinfunction "B_1") (pintype "passive"))
      (node (ref "R316") (pin "2") (pinfunction "2_2") (pintype "passive"))
    )
    (net (code "432") (name "Net-(Q303-C)") (class "Default")
      (node (ref "Q303") (pin "2") (pinfunction "C_2") (pintype "passive"))
      (node (ref "R315") (pin "2") (pinfunction "2_2") (pintype "passive"))
      (node (ref "R318") (pin "1") (pinfunction "1_1") (pintype "passive"))
    )
    (net (code "433") (name "Net-(Q304-B)") (class "Default")
      (node (ref "Q304") (pin "1") (pinfunction "B_1") (pintype "passive"))
      (node (ref "R328") (pin "2") (pinfunction "2_2") (pintype "passive"))
    )
    (net (code "434") (name "Net-(Q305-B)") (class "Default")
      (node (ref "Q305") (pin "1") (pinfunction "B_1") (pintype "passive"))
      (node (ref "R326") (pin "1") (pinfunction "1_1") (pintype "passive"))
    )
    (net (code "435") (name "Net-(Q307-D)") (class "Default")
      (node (ref "Q307") (pin "3") (pinfunction "D_3") (pintype "passive"))
      (node (ref "R338") (pin "2") (pinfunction "2_2") (pintype "passive"))
    )
    (net (code "436") (name "Net-(Q401-B)") (class "Default")
      (node (ref "Q401") (pin "1") (pinfunction "B_1") (pintype "passive"))
      (node (ref "Q402") (pin "1") (pinfunction "B_1") (pintype "passive"))
      (node (ref "Q402") (pin "2") (pinfunction "C_2") (pintype "passive"))
      (node (ref "R401") (pin "1") (pinfunction "1_1") (pintype "passive"))
      (node (ref "R403") (pin "1") (pinfunction "1_1") (pintype "passive"))
      (node (ref "R404") (pin "1") (pinfunction "1_1") (pintype "passive"))
      (node (ref "X402") (pin "2") (pinfunction "S_2") (pintype "passive"))
    )
    (net (code "437") (name "Net-(Q401-E)") (class "Default")
      (node (ref "Q401") (pin "3") (pinfunction "E_3") (pintype "passive"))
      (node (ref "R402") (pin "2") (pinfunction "2_2") (pintype "passive"))
    )
    (net (code "438") (name "Net-(Q402-E)") (class "Default")
      (node (ref "Q402") (pin "3") (pinfunction "E_3") (pintype "passive"))
      (node (ref "R406") (pin "2") (pinfunction "2_2") (pintype "passive"))
    )
    (net (code "439") (name "Net-(Q403-B)") (class "Default")
      (node (ref "Q403") (pin "1") (pinfunction "B_1") (pintype "passive"))
      (node (ref "R416") (pin "2") (pinfunction "2_2") (pintype "passive"))
    )
    (net (code "440") (name "Net-(Q403-C)") (class "Default")
      (node (ref "Q403") (pin "2") (pinfunction "C_2") (pintype "passive"))
      (node (ref "R415") (pin "2") (pinfunction "2_2") (pintype "passive"))
      (node (ref "R418") (pin "1") (pinfunction "1_1") (pintype "passive"))
    )
    (net (code "441") (name "Net-(Q404-B)") (class "Default")
      (node (ref "Q404") (pin "1") (pinfunction "B_1") (pintype "passive"))
      (node (ref "R428") (pin "2") (pinfunction "2_2") (pintype "passive"))
    )
    (net (code "442") (name "Net-(Q405-B)") (class "Default")
      (node (ref "Q405") (pin "1") (pinfunction "B_1") (pintype "passive"))
      (node (ref "R426") (pin "1") (pinfunction "1_1") (pintype "passive"))
    )
    (net (code "443") (name "Net-(Q407-D)") (class "Default")
      (node (ref "Q407") (pin "3") (pinfunction "D_3") (pintype "passive"))
      (node (ref "R438") (pin "2") (pinfunction "2_2") (pintype "passive"))
    )
    (net (code "444") (name "Net-(Q501-B)") (class "Default")
      (node (ref "Q501") (pin "1") (pinfunction "B_1") (pintype "passive"))
      (node (ref "Q502") (pin "1") (pinfunction "B_1") (pintype "passive"))
      (node (ref "Q502") (pin "2") (pinfunction "C_2") (pintype "passive"))
      (node (ref "R501") (pin "1") (pinfunction "1_1") (pintype "passive"))
      (node (ref "R503") (pin "1") (pinfunction "1_1") (pintype "passive"))
      (node (ref "R504") (pin "1") (pinfunction "1_1") (pintype "passive"))
      (node (ref "X502") (pin "2") (pinfunction "S_2") (pintype "passive"))
    )
    (net (code "445") (name "Net-(Q501-E)") (class "Default")
      (node (ref "Q501") (pin "3") (pinfunction "E_3") (pintype "passive"))
      (node (ref "R502") (pin "2") (pinfunction "2_2") (pintype "passive"))
    )
    (net (code "446") (name "Net-(Q502-E)") (class "Default")
      (node (ref "Q502") (pin "3") (pinfunction "E_3") (pintype "passive"))
      (node (ref "R506") (pin "2") (pinfunction "2_2") (pintype "passive"))
    )
    (net (code "447") (name "Net-(Q503-B)") (class "Default")
      (node (ref "Q503") (pin "1") (pinfunction "B_1") (pintype "passive"))
      (node (ref "R516") (pin "2") (pinfunction "2_2") (pintype "passive"))
    )
    (net (code "448") (name "Net-(Q503-C)") (class "Default")
      (node (ref "Q503") (pin "2") (pinfunction "C_2") (pintype "passive"))
      (node (ref "R515") (pin "2") (pinfunction "2_2") (pintype "passive"))
      (node (ref "R518") (pin "1") (pinfunction "1_1") (pintype "passive"))
    )
    (net (code "449") (name "Net-(Q504-B)") (class "Default")
      (node (ref "Q504") (pin "1") (pinfunction "B_1") (pintype "passive"))
      (node (ref "R528") (pin "2") (pinfunction "2_2") (pintype "passive"))
    )
    (net (code "450") (name "Net-(Q505-B)") (class "Default")
      (node (ref "Q505") (pin "1") (pinfunction "B_1") (pintype "passive"))
      (node (ref "R526") (pin "1") (pinfunction "1_1") (pintype "passive"))
    )
    (net (code "451") (name "Net-(Q507-D)") (class "Default")
      (node (ref "Q507") (pin "3") (pinfunction "D_3") (pintype "passive"))
      (node (ref "R538") (pin "2") (pinfunction "2_2") (pintype "passive"))
    )
    (net (code "452") (name "Net-(Q601-B)") (class "Default")
      (node (ref "Q601") (pin "1") (pinfunction "B_1") (pintype "passive"))
      (node (ref "Q602") (pin "1") (pinfunction "B_1") (pintype "passive"))
      (node (ref "Q602") (pin "2") (pinfunction "C_2") (pintype "passive"))
      (node (ref "R601") (pin "1") (pinfunction "1_1") (pintype "passive"))
      (node (ref "R603") (pin "1") (pinfunction "1_1") (pintype "passive"))
      (node (ref "R604") (pin "1") (pinfunction "1_1") (pintype "passive"))
      (node (ref "X602") (pin "2") (pinfunction "S_2") (pintype "passive"))
    )
    (net (code "453") (name "Net-(Q601-E)") (class "Default")
      (node (ref "Q601") (pin "3") (pinfunction "E_3") (pintype "passive"))
      (node (ref "R602") (pin "2") (pinfunction "2_2") (pintype "passive"))
    )
    (net (code "454") (name "Net-(Q602-E)") (class "Default")
      (node (ref "Q602") (pin "3") (pinfunction "E_3") (pintype "passive"))
      (node (ref "R606") (pin "2") (pinfunction "2_2") (pintype "passive"))
    )
    (net (code "455") (name "Net-(Q603-B)") (class "Default")
      (node (ref "Q603") (pin "1") (pinfunction "B_1") (pintype "passive"))
      (node (ref "R616") (pin "2") (pinfunction "2_2") (pintype "passive"))
    )
    (net (code "456") (name "Net-(Q603-C)") (class "Default")
      (node (ref "Q603") (pin "2") (pinfunction "C_2") (pintype "passive"))
      (node (ref "R615") (pin "2") (pinfunction "2_2") (pintype "passive"))
      (node (ref "R618") (pin "1") (pinfunction "1_1") (pintype "passive"))
    )
    (net (code "457") (name "Net-(Q604-B)") (class "Default")
      (node (ref "Q604") (pin "1") (pinfunction "B_1") (pintype "passive"))
      (node (ref "R628") (pin "2") (pinfunction "2_2") (pintype "passive"))
    )
    (net (code "458") (name "Net-(Q605-B)") (class "Default")
      (node (ref "Q605") (pin "1") (pinfunction "B_1") (pintype "passive"))
      (node (ref "R626") (pin "1") (pinfunction "1_1") (pintype "passive"))
    )
    (net (code "459") (name "Net-(Q607-D)") (class "Default")
      (node (ref "Q607") (pin "3") (pinfunction "D_3") (pintype "passive"))
      (node (ref "R638") (pin "2") (pinfunction "2_2") (pintype "passive"))
    )
    (net (code "460") (name "Net-(R115-Pad1)") (class "Default")
      (node (ref "R115") (pin "1") (pinfunction "1_1") (pintype "passive"))
      (node (ref "X101") (pin "21") (pinfunction "21_21") (pintype "passive"))
    )
    (net (code "461") (name "Net-(R127-Pad2)") (class "Default")
      (node (ref "R127") (pin "2") (pinfunction "2_2") (pintype "passive"))
      (node (ref "R129") (pin "1") (pinfunction "1_1") (pintype "passive"))
    )
    (net (code "462") (name "Net-(R140-Pad2)") (class "Default")
      (node (ref "R140") (pin "2") (pinfunction "2_2") (pintype "passive"))
      (node (ref "X101") (pin "16") (pinfunction "16_16") (pintype "passive"))
    )
    (net (code "463") (name "Net-(R215-Pad1)") (class "Default")
      (node (ref "R215") (pin "1") (pinfunction "1_1") (pintype "passive"))
      (node (ref "X201") (pin "21") (pinfunction "21_21") (pintype "passive"))
    )
    (net (code "464") (name "Net-(R227-Pad2)") (class "Default")
      (node (ref "R227") (pin "2") (pinfunction "2_2") (pintype "passive"))
      (node (ref "R229") (pin "1") (pinfunction "1_1") (pintype "passive"))
    )
    (net (code "465") (name "Net-(R240-Pad2)") (class "Default")
      (node (ref "R240") (pin "2") (pinfunction "2_2") (pintype "passive"))
      (node (ref "X201") (pin "16") (pinfunction "16_16") (pintype "passive"))
    )
    (net (code "466") (name "Net-(R315-Pad1)") (class "Default")
      (node (ref "R315") (pin "1") (pinfunction "1_1") (pintype "passive"))
      (node (ref "X301") (pin "21") (pinfunction "21_21") (pintype "passive"))
    )
    (net (code "467") (name "Net-(R327-Pad2)") (class "Default")
      (node (ref "R327") (pin "2") (pinfunction "2_2") (pintype "passive"))
      (node (ref "R329") (pin "1") (pinfunction "1_1") (pintype "passive"))
    )
    (net (code "468") (name "Net-(R340-Pad2)") (class "Default")
      (node (ref "R340") (pin "2") (pinfunction "2_2") (pintype "passive"))
      (node (ref "X301") (pin "16") (pinfunction "16_16") (pintype "passive"))
    )
    (net (code "469") (name "Net-(R415-Pad1)") (class "Default")
      (node (ref "R415") (pin "1") (pinfunction "1_1") (pintype "passive"))
      (node (ref "X401") (pin "21") (pinfunction "21_21") (pintype "passive"))
    )
    (net (code "470") (name "Net-(R427-Pad2)") (class "Default")
      (node (ref "R427") (pin "2") (pinfunction "2_2") (pintype "passive"))
      (node (ref "R429") (pin "1") (pinfunction "1_1") (pintype "passive"))
    )
    (net (code "471") (name "Net-(R440-Pad2)") (class "Default")
      (node (ref "R440") (pin "2") (pinfunction "2_2") (pintype "passive"))
      (node (ref "X401") (pin "16") (pinfunction "16_16") (pintype "passive"))
    )
    (net (code "472") (name "Net-(R515-Pad1)") (class "Default")
      (node (ref "R515") (pin "1") (pinfunction "1_1") (pintype "passive"))
      (node (ref "X501") (pin "21") (pinfunction "21_21") (pintype "passive"))
    )
    (net (code "473") (name "Net-(R527-Pad2)") (class "Default")
      (node (ref "R527") (pin "2") (pinfunction "2_2") (pintype "passive"))
      (node (ref "R529") (pin "1") (pinfunction "1_1") (pintype "passive"))
    )
    (net (code "474") (name "Net-(R540-Pad2)") (class "Default")
      (node (ref "R540") (pin "2") (pinfunction "2_2") (pintype "passive"))
      (node (ref "X501") (pin "16") (pinfunction "16_16") (pintype "passive"))
    )
    (net (code "475") (name "Net-(R615-Pad1)") (class "Default")
      (node (ref "R615") (pin "1") (pinfunction "1_1") (pintype "passive"))
      (node (ref "X601") (pin "21") (pinfunction "21_21") (pintype "passive"))
    )
    (net (code "476") (name "Net-(R627-Pad2)") (class "Default")
      (node (ref "R627") (pin "2") (pinfunction "2_2") (pintype "passive"))
      (node (ref "R629") (pin "1") (pinfunction "1_1") (pintype "passive"))
    )
    (net (code "477") (name "Net-(R640-Pad2)") (class "Default")
      (node (ref "R640") (pin "2") (pinfunction "2_2") (pintype "passive"))
      (node (ref "X601") (pin "16") (pinfunction "16_16") (pintype "passive"))
    )
    (net (code "478") (name "VCC") (class "Default")
      (node (ref "6V") (pin "TP") (pinfunction "PP_TP") (pintype "input"))
      (node (ref "6V201") (pin "TP") (pinfunction "PP_TP") (pintype "input"))
      (node (ref "6V301") (pin "TP") (pinfunction "PP_TP") (pintype "input"))
      (node (ref "6V401") (pin "TP") (pinfunction "PP_TP") (pintype "input"))
      (node (ref "6V501") (pin "TP") (pinfunction "PP_TP") (pintype "input"))
      (node (ref "6V601") (pin "TP") (pinfunction "PP_TP") (pintype "input"))
      (node (ref "C104") (pin "1") (pinfunction "1_1") (pintype "passive"))
      (node (ref "C204") (pin "1") (pinfunction "1_1") (pintype "passive"))
      (node (ref "C304") (pin "1") (pinfunction "1_1") (pintype "passive"))
      (node (ref "C404") (pin "1") (pinfunction "1_1") (pintype "passive"))
      (node (ref "C504") (pin "1") (pinfunction "1_1") (pintype "passive"))
      (node (ref "C604") (pin "1") (pinfunction "1_1") (pintype "passive"))
      (node (ref "IC101") (pin "8") (pinfunction "V+_8") (pintype "power_in"))
      (node (ref "IC102") (pin "1") (pinfunction "OUT_1") (pintype "passive"))
      (node (ref "IC103") (pin "OUT") (pinfunction "OUT_OUT") (pintype "passive"))
      (node (ref "IC108") (pin "3") (pinfunction "V+_3") (pintype "power_in"))
      (node (ref "IC201") (pin "8") (pinfunction "V+_8") (pintype "power_in"))
      (node (ref "IC202") (pin "1") (pinfunction "OUT_1") (pintype "passive"))
      (node (ref "IC203") (pin "OUT") (pinfunction "OUT_OUT") (pintype "passive"))
      (node (ref "IC208") (pin "3") (pinfunction "V+_3") (pintype "power_in"))
      (node (ref "IC301") (pin "8") (pinfunction "V+_8") (pintype "power_in"))
      (node (ref "IC302") (pin "1") (pinfunction "OUT_1") (pintype "passive"))
      (node (ref "IC303") (pin "OUT") (pinfunction "OUT_OUT") (pintype "passive"))
      (node (ref "IC308") (pin "3") (pinfunction "V+_3") (pintype "power_in"))
      (node (ref "IC401") (pin "8") (pinfunction "V+_8") (pintype "power_in"))
      (node (ref "IC402") (pin "1") (pinfunction "OUT_1") (pintype "passive"))
      (node (ref "IC403") (pin "OUT") (pinfunction "OUT_OUT") (pintype "passive"))
      (node (ref "IC408") (pin "3") (pinfunction "V+_3") (pintype "power_in"))
      (node (ref "IC501") (pin "8") (pinfunction "V+_8") (pintype "power_in"))
      (node (ref "IC502") (pin "1") (pinfunction "OUT_1") (pintype "passive"))
      (node (ref "IC503") (pin "OUT") (pinfunction "OUT_OUT") (pintype "passive"))
      (node (ref "IC508") (pin "3") (pinfunction "V+_3") (pintype "power_in"))
      (node (ref "IC601") (pin "8") (pinfunction "V+_8") (pintype "power_in"))
      (node (ref "IC602") (pin "1") (pinfunction "OUT_1") (pintype "passive"))
      (node (ref "IC603") (pin "OUT") (pinfunction "OUT_OUT") (pintype "passive"))
      (node (ref "IC608") (pin "3") (pinfunction "V+_3") (pintype "power_in"))
      (node (ref "R113") (pin "2") (pinfunction "2_2") (pintype "passive"))
      (node (ref "R121") (pin "2") (pinfunction "2_2") (pintype "passive"))
      (node (ref "R124") (pin "1") (pinfunction "1_1") (pintype "passive"))
      (node (ref "R131") (pin "2") (pinfunction "2_2") (pintype "passive"))
      (node (ref "R142") (pin "2") (pinfunction "2_2") (pintype "passive"))
      (node (ref "R213") (pin "2") (pinfunction "2_2") (pintype "passive"))
      (node (ref "R221") (pin "2") (pinfunction "2_2") (pintype "passive"))
      (node (ref "R224") (pin "1") (pinfunction "1_1") (pintype "passive"))
      (node (ref "R231") (pin "2") (pinfunction "2_2") (pintype "passive"))
      (node (ref "R242") (pin "2") (pinfunction "2_2") (pintype "passive"))
      (node (ref "R313") (pin "2") (pinfunction "2_2") (pintype "passive"))
      (node (ref "R321") (pin "2") (pinfunction "2_2") (pintype "passive"))
      (node (ref "R324") (pin "1") (pinfunction "1_1") (pintype "passive"))
      (node (ref "R331") (pin "2") (pinfunction "2_2") (pintype "passive"))
      (node (ref "R342") (pin "2") (pinfunction "2_2") (pintype "passive"))
      (node (ref "R413") (pin "2") (pinfunction "2_2") (pintype "passive"))
      (node (ref "R421") (pin "2") (pinfunction "2_2") (pintype "passive"))
      (node (ref "R424") (pin "1") (pinfunction "1_1") (pintype "passive"))
      (node (ref "R431") (pin "2") (pinfunction "2_2") (pintype "passive"))
      (node (ref "R442") (pin "2") (pinfunction "2_2") (pintype "passive"))
      (node (ref "R513") (pin "2") (pinfunction "2_2") (pintype "passive"))
      (node (ref "R521") (pin "2") (pinfunction "2_2") (pintype "passive"))
      (node (ref "R524") (pin "1") (pinfunction "1_1") (pintype "passive"))
      (node (ref "R531") (pin "2") (pinfunction "2_2") (pintype "passive"))
      (node (ref "R542") (pin "2") (pinfunction "2_2") (pintype "passive"))
      (node (ref "R613") (pin "2") (pinfunction "2_2") (pintype "passive"))
      (node (ref "R621") (pin "2") (pinfunction "2_2") (pintype "passive"))
      (node (ref "R624") (pin "1") (pinfunction "1_1") (pintype "passive"))
      (node (ref "R631") (pin "2") (pinfunction "2_2") (pintype "passive"))
      (node (ref "R642") (pin "2") (pinfunction "2_2") (pintype "passive"))
    )
    (net (code "479") (name "unconnected-(IC105A-Q6-Pad7)") (class "Default")
      (node (ref "IC105") (pin "7") (pinfunction "Q6_7") (pintype "output"))
    )
    (net (code "480") (name "unconnected-(IC105A-Q7-Pad4)") (class "Default")
      (node (ref "IC105") (pin "4") (pinfunction "Q7_4") (pintype "output"))
    )
    (net (code "481") (name "unconnected-(IC105A-Q8-Pad9)") (class "Default")
      (node (ref "IC105") (pin "9") (pinfunction "Q8_9") (pintype "output"))
    )
    (net (code "482") (name "unconnected-(IC105A-Q9-Pad5)") (class "Default")
      (node (ref "IC105") (pin "5") (pinfunction "Q9_5") (pintype "output"))
    )
    (net (code "483") (name "unconnected-(IC108D-OUT-Pad13)") (class "Default")
      (node (ref "IC108") (pin "13") (pinfunction "OUT_13") (pintype "open_collector"))
    )
    (net (code "484") (name "unconnected-(IC110-DIS-Pad7)") (class "Default")
      (node (ref "IC110") (pin "7") (pinfunction "DIS_7") (pintype "input"))
    )
    (net (code "485") (name "unconnected-(IC111A-Q-Pad6)") (class "Default")
      (node (ref "IC111") (pin "6") (pinfunction "Q_6") (pintype "output"))
    )
    (net (code "486") (name "unconnected-(IC111A-T2-Pad2)") (class "Default")
      (node (ref "IC111") (pin "2") (pinfunction "T2_2") (pintype "input"))
    )
    (net (code "487") (name "unconnected-(IC111A-~{Q}-Pad7)") (class "Default")
      (node (ref "IC111") (pin "7") (pinfunction "~{Q}_7") (pintype "output"))
    )
    (net (code "488") (name "unconnected-(IC111B-Q-Pad10)") (class "Default")
      (node (ref "IC111") (pin "10") (pinfunction "Q_10") (pintype "output"))
    )
    (net (code "489") (name "unconnected-(IC205A-Q6-Pad7)") (class "Default")
      (node (ref "IC205") (pin "7") (pinfunction "Q6_7") (pintype "output"))
    )
    (net (code "490") (name "unconnected-(IC205A-Q7-Pad4)") (class "Default")
      (node (ref "IC205") (pin "4") (pinfunction "Q7_4") (pintype "output"))
    )
    (net (code "491") (name "unconnected-(IC205A-Q8-Pad9)") (class "Default")
      (node (ref "IC205") (pin "9") (pinfunction "Q8_9") (pintype "output"))
    )
    (net (code "492") (name "unconnected-(IC205A-Q9-Pad5)") (class "Default")
      (node (ref "IC205") (pin "5") (pinfunction "Q9_5") (pintype "output"))
    )
    (net (code "493") (name "unconnected-(IC208D-OUT-Pad13)") (class "Default")
      (node (ref "IC208") (pin "13") (pinfunction "OUT_13") (pintype "open_collector"))
    )
    (net (code "494") (name "unconnected-(IC210-DIS-Pad7)") (class "Default")
      (node (ref "IC210") (pin "7") (pinfunction "DIS_7") (pintype "input"))
    )
    (net (code "495") (name "unconnected-(IC211A-Q-Pad6)") (class "Default")
      (node (ref "IC211") (pin "6") (pinfunction "Q_6") (pintype "output"))
    )
    (net (code "496") (name "unconnected-(IC211A-T2-Pad2)") (class "Default")
      (node (ref "IC211") (pin "2") (pinfunction "T2_2") (pintype "input"))
    )
    (net (code "497") (name "unconnected-(IC211A-~{Q}-Pad7)") (class "Default")
      (node (ref "IC211") (pin "7") (pinfunction "~{Q}_7") (pintype "output"))
    )
    (net (code "498") (name "unconnected-(IC211B-Q-Pad10)") (class "Default")
      (node (ref "IC211") (pin "10") (pinfunction "Q_10") (pintype "output"))
    )
    (net (code "499") (name "unconnected-(IC305A-Q6-Pad7)") (class "Default")
      (node (ref "IC305") (pin "7") (pinfunction "Q6_7") (pintype "output"))
    )
    (net (code "500") (name "unconnected-(IC305A-Q7-Pad4)") (class "Default")
      (node (ref "IC305") (pin "4") (pinfunction "Q7_4") (pintype "output"))
    )
    (net (code "501") (name "unconnected-(IC305A-Q8-Pad9)") (class "Default")
      (node (ref "IC305") (pin "9") (pinfunction "Q8_9") (pintype "output"))
    )
    (net (code "502") (name "unconnected-(IC305A-Q9-Pad5)") (class "Default")
      (node (ref "IC305") (pin "5") (pinfunction "Q9_5") (pintype "output"))
    )
    (net (code "503") (name "unconnected-(IC308D-OUT-Pad13)") (class "Default")
      (node (ref "IC308") (pin "13") (pinfunction "OUT_13") (pintype "open_collector"))
    )
    (net (code "504") (name "unconnected-(IC310-DIS-Pad7)") (class "Default")
      (node (ref "IC310") (pin "7") (pinfunction "DIS_7") (pintype "input"))
    )
    (net (code "505") (name "unconnected-(IC311A-Q-Pad6)") (class "Default")
      (node (ref "IC311") (pin "6") (pinfunction "Q_6") (pintype "output"))
    )
    (net (code "506") (name "unconnected-(IC311A-T2-Pad2)") (class "Default")
      (node (ref "IC311") (pin "2") (pinfunction "T2_2") (pintype "input"))
    )
    (net (code "507") (name "unconnected-(IC311A-~{Q}-Pad7)") (class "Default")
      (node (ref "IC311") (pin "7") (pinfunction "~{Q}_7") (pintype "output"))
    )
    (net (code "508") (name "unconnected-(IC311B-Q-Pad10)") (class "Default")
      (node (ref "IC311") (pin "10") (pinfunction "Q_10") (pintype "output"))
    )
    (net (code "509") (name "unconnected-(IC405A-Q6-Pad7)") (class "Default")
      (node (ref "IC405") (pin "7") (pinfunction "Q6_7") (pintype "output"))
    )
    (net (code "510") (name "unconnected-(IC405A-Q7-Pad4)") (class "Default")
      (node (ref "IC405") (pin "4") (pinfunction "Q7_4") (pintype "output"))
    )
    (net (code "511") (name "unconnected-(IC405A-Q8-Pad9)") (class "Default")
      (node (ref "IC405") (pin "9") (pinfunction "Q8_9") (pintype "output"))
    )
    (net (code "512") (name "unconnected-(IC405A-Q9-Pad5)") (class "Default")
      (node (ref "IC405") (pin "5") (pinfunction "Q9_5") (pintype "output"))
    )
    (net (code "513") (name "unconnected-(IC408D-OUT-Pad13)") (class "Default")
      (node (ref "IC408") (pin "13") (pinfunction "OUT_13") (pintype "open_collector"))
    )
    (net (code "514") (name "unconnected-(IC410-DIS-Pad7)") (class "Default")
      (node (ref "IC410") (pin "7") (pinfunction "DIS_7") (pintype "input"))
    )
    (net (code "515") (name "unconnected-(IC411A-Q-Pad6)") (class "Default")
      (node (ref "IC411") (pin "6") (pinfunction "Q_6") (pintype "output"))
    )
    (net (code "516") (name "unconnected-(IC411A-T2-Pad2)") (class "Default")
      (node (ref "IC411") (pin "2") (pinfunction "T2_2") (pintype "input"))
    )
    (net (code "517") (name "unconnected-(IC411A-~{Q}-Pad7)") (class "Default")
      (node (ref "IC411") (pin "7") (pinfunction "~{Q}_7") (pintype "output"))
    )
    (net (code "518") (name "unconnected-(IC411B-Q-Pad10)") (class "Default")
      (node (ref "IC411") (pin "10") (pinfunction "Q_10") (pintype "output"))
    )
    (net (code "519") (name "unconnected-(IC505A-Q6-Pad7)") (class "Default")
      (node (ref "IC505") (pin "7") (pinfunction "Q6_7") (pintype "output"))
    )
    (net (code "520") (name "unconnected-(IC505A-Q7-Pad4)") (class "Default")
      (node (ref "IC505") (pin "4") (pinfunction "Q7_4") (pintype "output"))
    )
    (net (code "521") (name "unconnected-(IC505A-Q8-Pad9)") (class "Default")
      (node (ref "IC505") (pin "9") (pinfunction "Q8_9") (pintype "output"))
    )
    (net (code "522") (name "unconnected-(IC505A-Q9-Pad5)") (class "Default")
      (node (ref "IC505") (pin "5") (pinfunction "Q9_5") (pintype "output"))
    )
    (net (code "523") (name "unconnected-(IC508D-OUT-Pad13)") (class "Default")
      (node (ref "IC508") (pin "13") (pinfunction "OUT_13") (pintype "open_collector"))
    )
    (net (code "524") (name "unconnected-(IC510-DIS-Pad7)") (class "Default")
      (node (ref "IC510") (pin "7") (pinfunction "DIS_7") (pintype "input"))
    )
    (net (code "525") (name "unconnected-(IC511A-Q-Pad6)") (class "Default")
      (node (ref "IC511") (pin "6") (pinfunction "Q_6") (pintype "output"))
    )
    (net (code "526") (name "unconnected-(IC511A-T2-Pad2)") (class "Default")
      (node (ref "IC511") (pin "2") (pinfunction "T2_2") (pintype "input"))
    )
    (net (code "527") (name "unconnected-(IC511A-~{Q}-Pad7)") (class "Default")
      (node (ref "IC511") (pin "7") (pinfunction "~{Q}_7") (pintype "output"))
    )
    (net (code "528") (name "unconnected-(IC511B-Q-Pad10)") (class "Default")
      (node (ref "IC511") (pin "10") (pinfunction "Q_10") (pintype "output"))
    )
    (net (code "529") (name "unconnected-(IC605A-Q6-Pad7)") (class "Default")
      (node (ref "IC605") (pin "7") (pinfunction "Q6_7") (pintype "output"))
    )
    (net (code "530") (name "unconnected-(IC605A-Q7-Pad4)") (class "Default")
      (node (ref "IC605") (pin "4") (pinfunction "Q7_4") (pintype "output"))
    )
    (net (code "531") (name "unconnected-(IC605A-Q8-Pad9)") (class "Default")
      (node (ref "IC605") (pin "9") (pinfunction "Q8_9") (pintype "output"))
    )
    (net (code "532") (name "unconnected-(IC605A-Q9-Pad5)") (class "Default")
      (node (ref "IC605") (pin "5") (pinfunction "Q9_5") (pintype "output"))
    )
    (net (code "533") (name "unconnected-(IC608D-OUT-Pad13)") (class "Default")
      (node (ref "IC608") (pin "13") (pinfunction "OUT_13") (pintype "open_collector"))
    )
    (net (code "534") (name "unconnected-(IC610-DIS-Pad7)") (class "Default")
      (node (ref "IC610") (pin "7") (pinfunction "DIS_7") (pintype "input"))
    )
    (net (code "535") (name "unconnected-(IC611A-Q-Pad6)") (class "Default")
      (node (ref "IC611") (pin "6") (pinfunction "Q_6") (pintype "output"))
    )
    (net (code "536") (name "unconnected-(IC611A-T2-Pad2)") (class "Default")
      (node (ref "IC611") (pin "2") (pinfunction "T2_2") (pintype "input"))
    )
    (net (code "537") (name "unconnected-(IC611A-~{Q}-Pad7)") (class "Default")
      (node (ref "IC611") (pin "7") (pinfunction "~{Q}_7") (pintype "output"))
    )
    (net (code "538") (name "unconnected-(IC611B-Q-Pad10)") (class "Default")
      (node (ref "IC611") (pin "10") (pinfunction "Q_10") (pintype "output"))
    )
    (net (code "539") (name "unconnected-(X101-Pad20)") (class "Default")
      (node (ref "X101") (pin "20") (pinfunction "20_20") (pintype "passive"))
    )
    (net (code "540") (name "unconnected-(X101-Pad24)") (class "Default")
      (node (ref "X101") (pin "24") (pinfunction "24_24") (pintype "passive"))
    )
    (net (code "541") (name "unconnected-(X201-Pad20)") (class "Default")
      (node (ref "X201") (pin "20") (pinfunction "20_20") (pintype "passive"))
    )
    (net (code "542") (name "unconnected-(X201-Pad24)") (class "Default")
      (node (ref "X201") (pin "24") (pinfunction "24_24") (pintype "passive"))
    )
    (net (code "543") (name "unconnected-(X301-Pad20)") (class "Default")
      (node (ref "X301") (pin "20") (pinfunction "20_20") (pintype "passive"))
    )
    (net (code "544") (name "unconnected-(X301-Pad24)") (class "Default")
      (node (ref "X301") (pin "24") (pinfunction "24_24") (pintype "passive"))
    )
    (net (code "545") (name "unconnected-(X401-Pad20)") (class "Default")
      (node (ref "X401") (pin "20") (pinfunction "20_20") (pintype "passive"))
    )
    (net (code "546") (name "unconnected-(X401-Pad24)") (class "Default")
      (node (ref "X401") (pin "24") (pinfunction "24_24") (pintype "passive"))
    )
    (net (code "547") (name "unconnected-(X501-Pad20)") (class "Default")
      (node (ref "X501") (pin "20") (pinfunction "20_20") (pintype "passive"))
    )
    (net (code "548") (name "unconnected-(X501-Pad24)") (class "Default")
      (node (ref "X501") (pin "24") (pinfunction "24_24") (pintype "passive"))
    )
    (net (code "549") (name "unconnected-(X601-Pad20)") (class "Default")
      (node (ref "X601") (pin "20") (pinfunction "20_20") (pintype "passive"))
    )
    (net (code "550") (name "unconnected-(X601-Pad24)") (class "Default")
      (node (ref "X601") (pin "24") (pinfunction "24_24") (pintype "passive"))
    )
  )
)
